# pdp8l.net
KiCad netlist of a schematic drawn in EAGLE
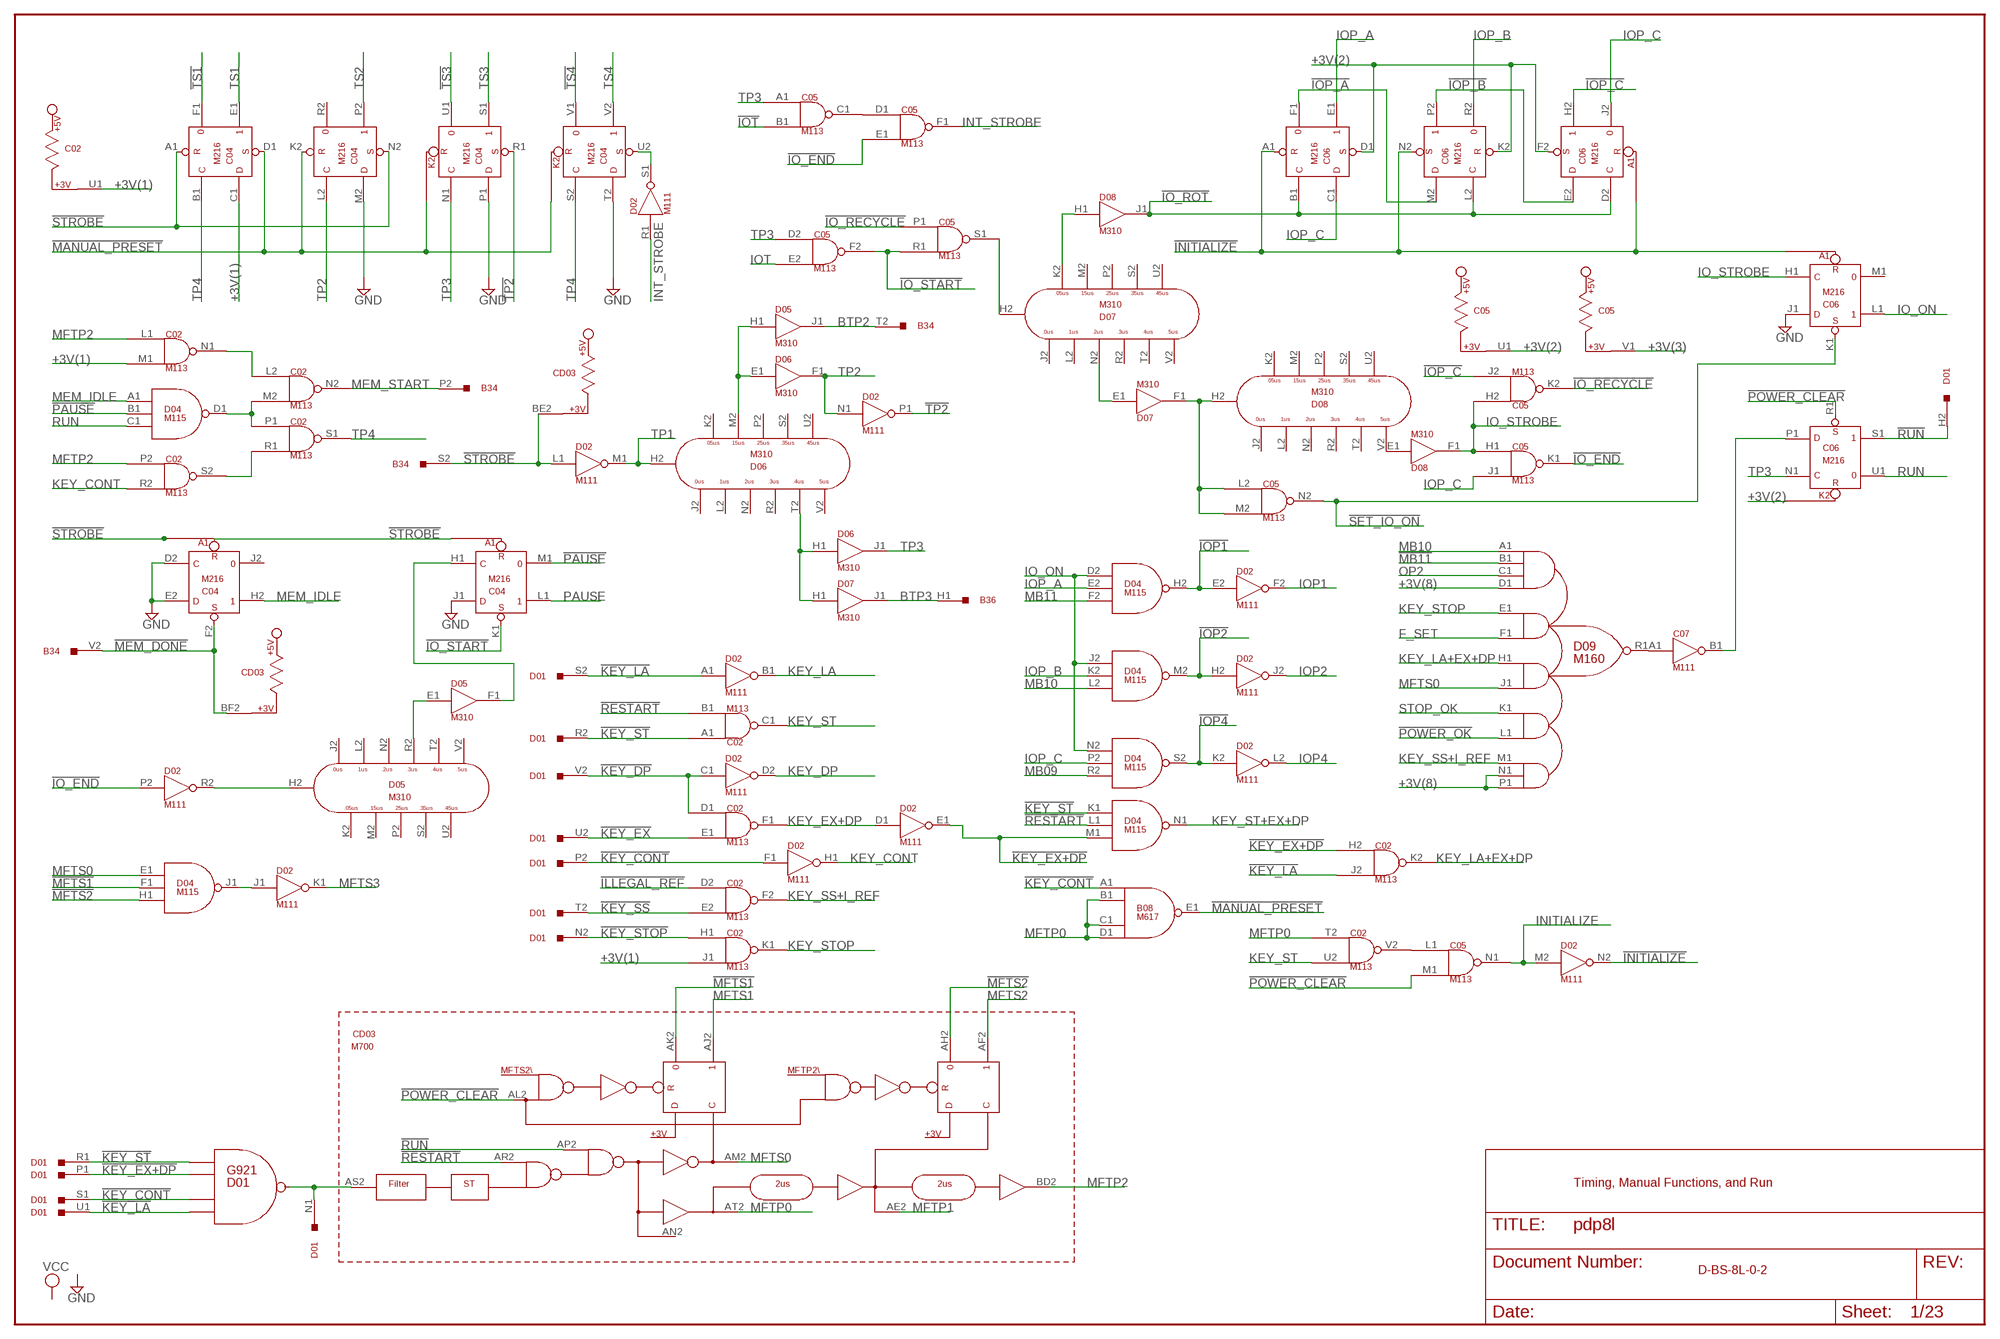
[diagram p0: schematic, sheet 1]
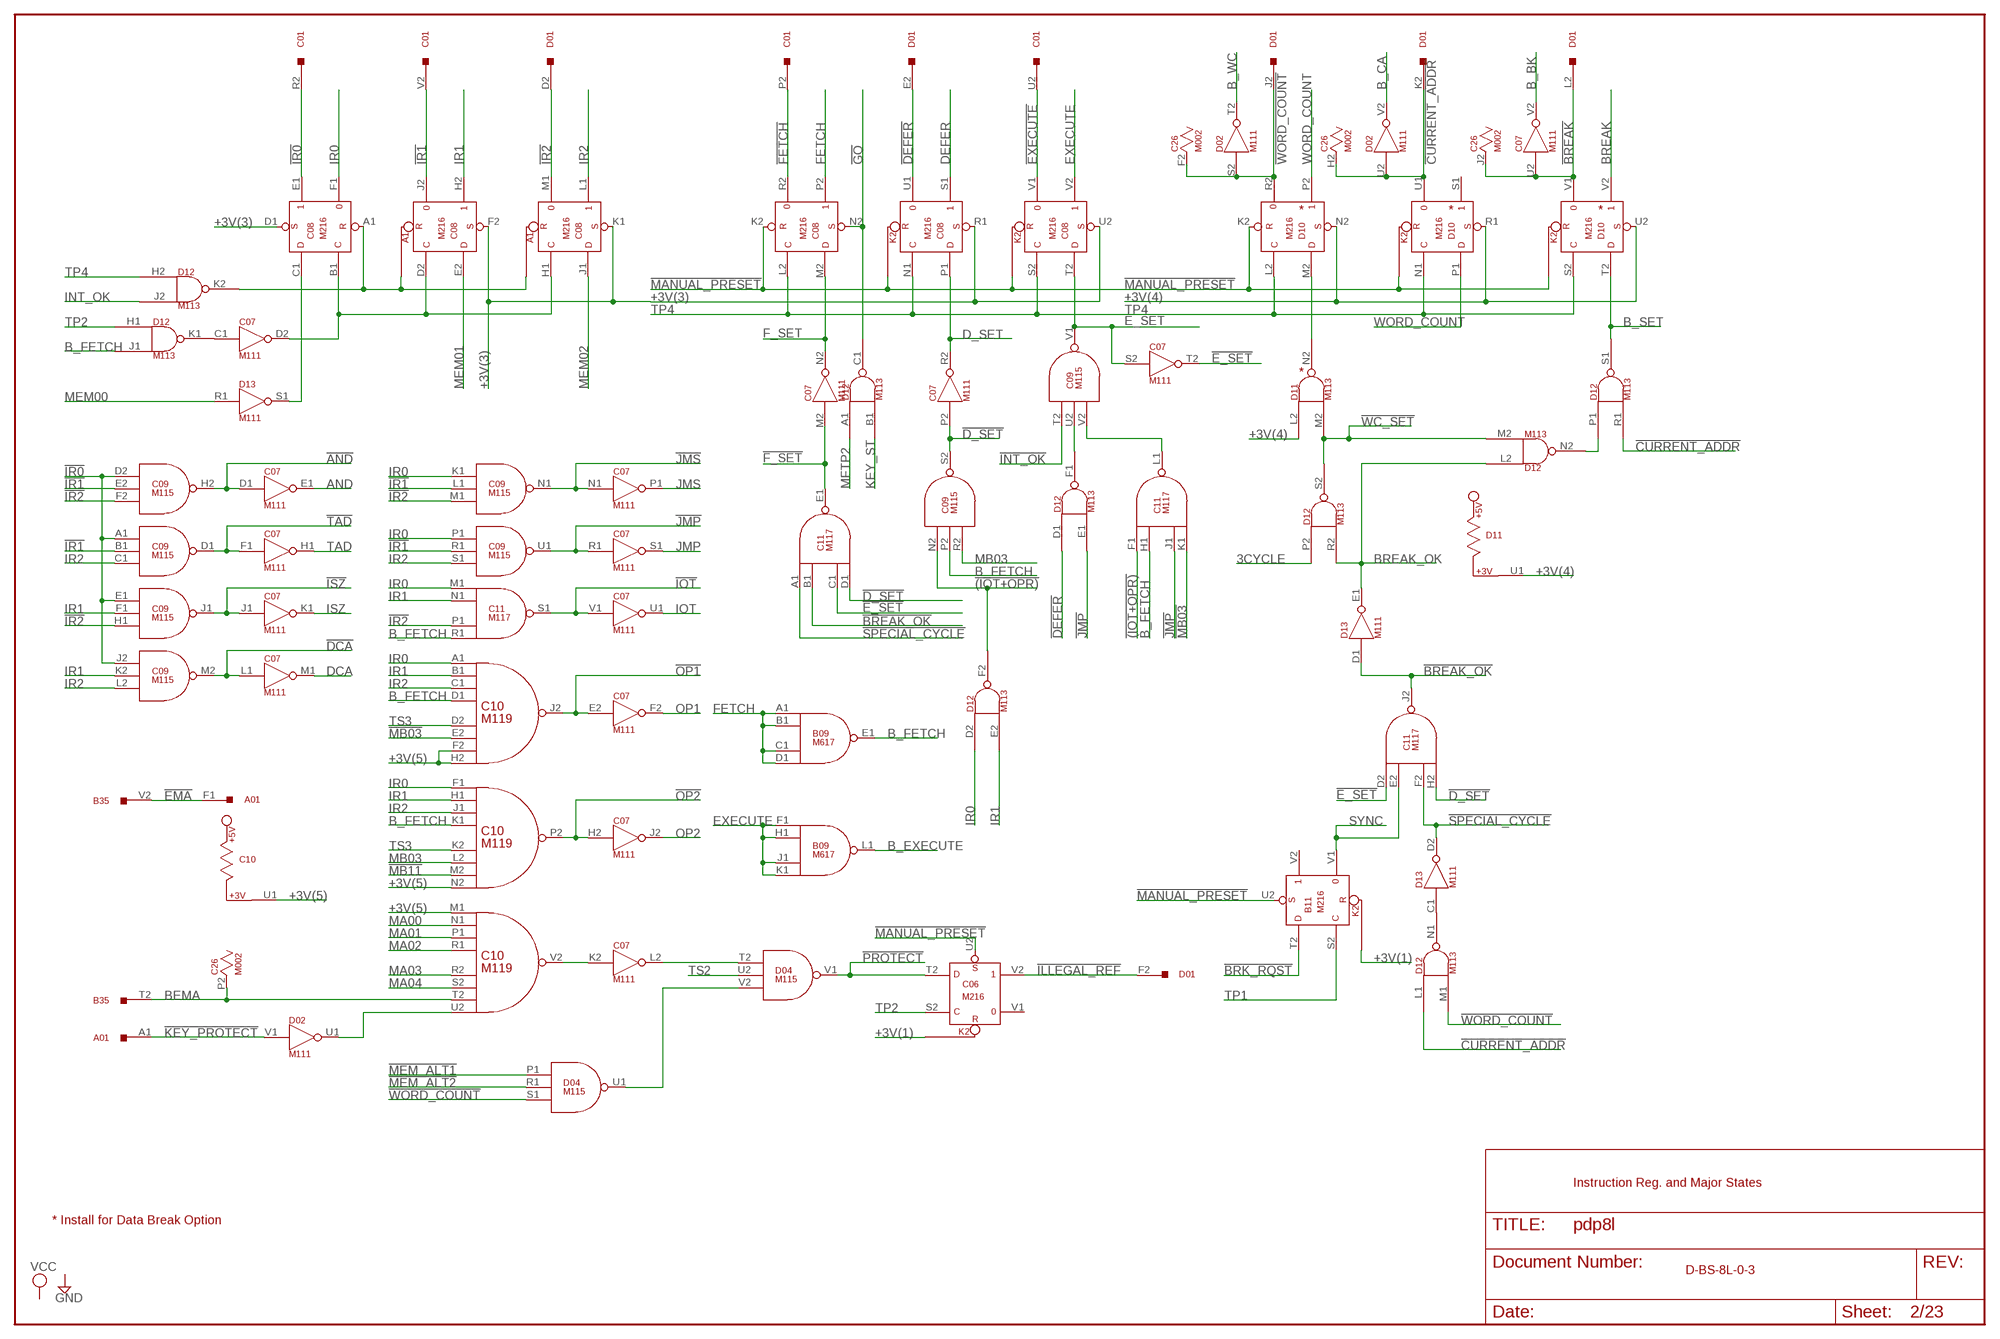
[diagram p1: schematic, sheet 2]
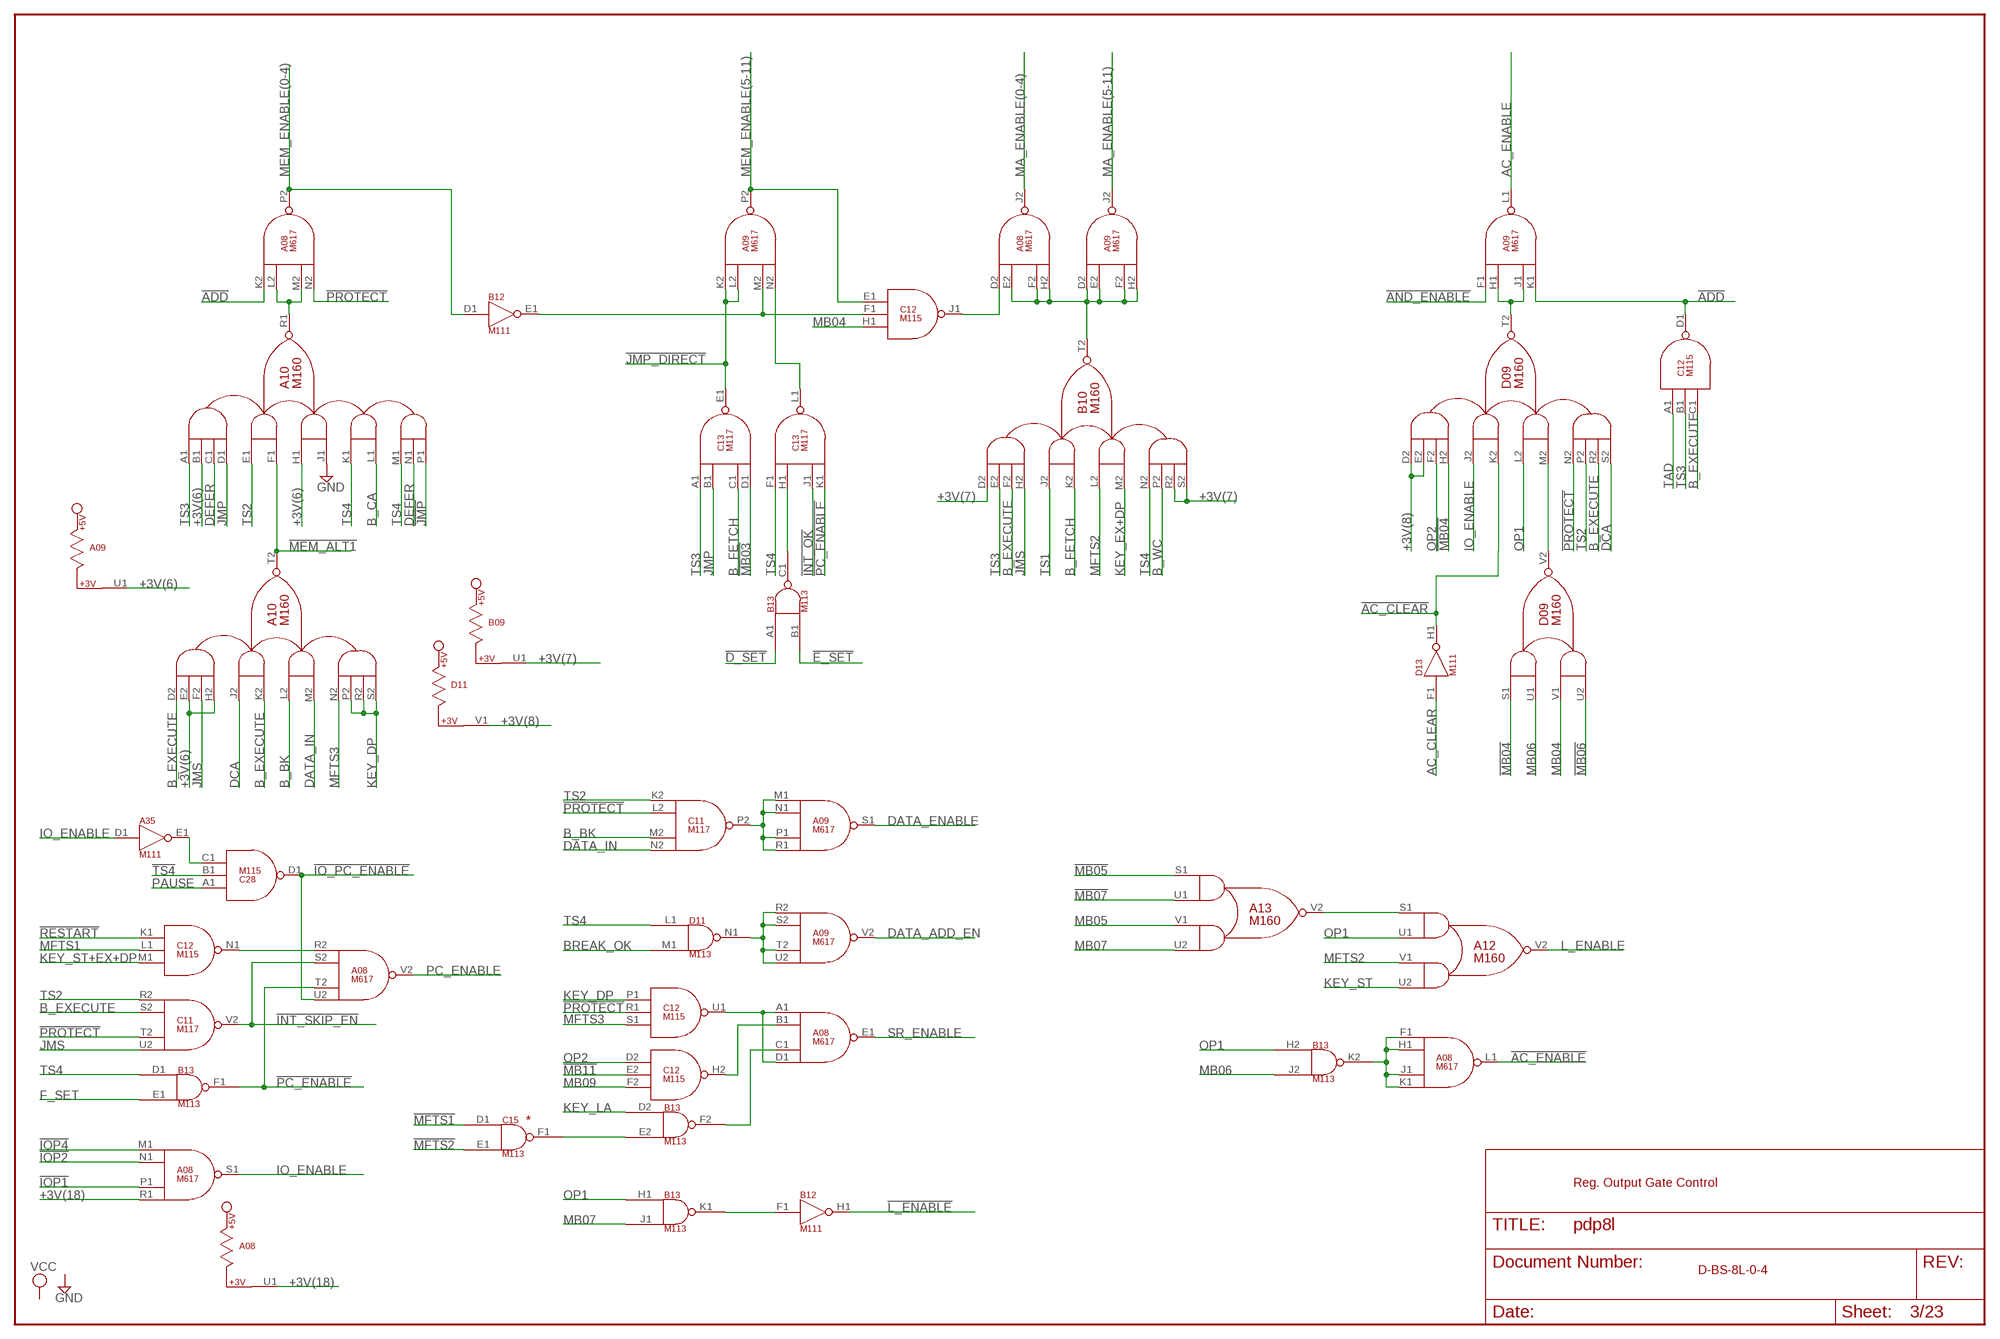
[diagram p2: schematic, sheet 3]
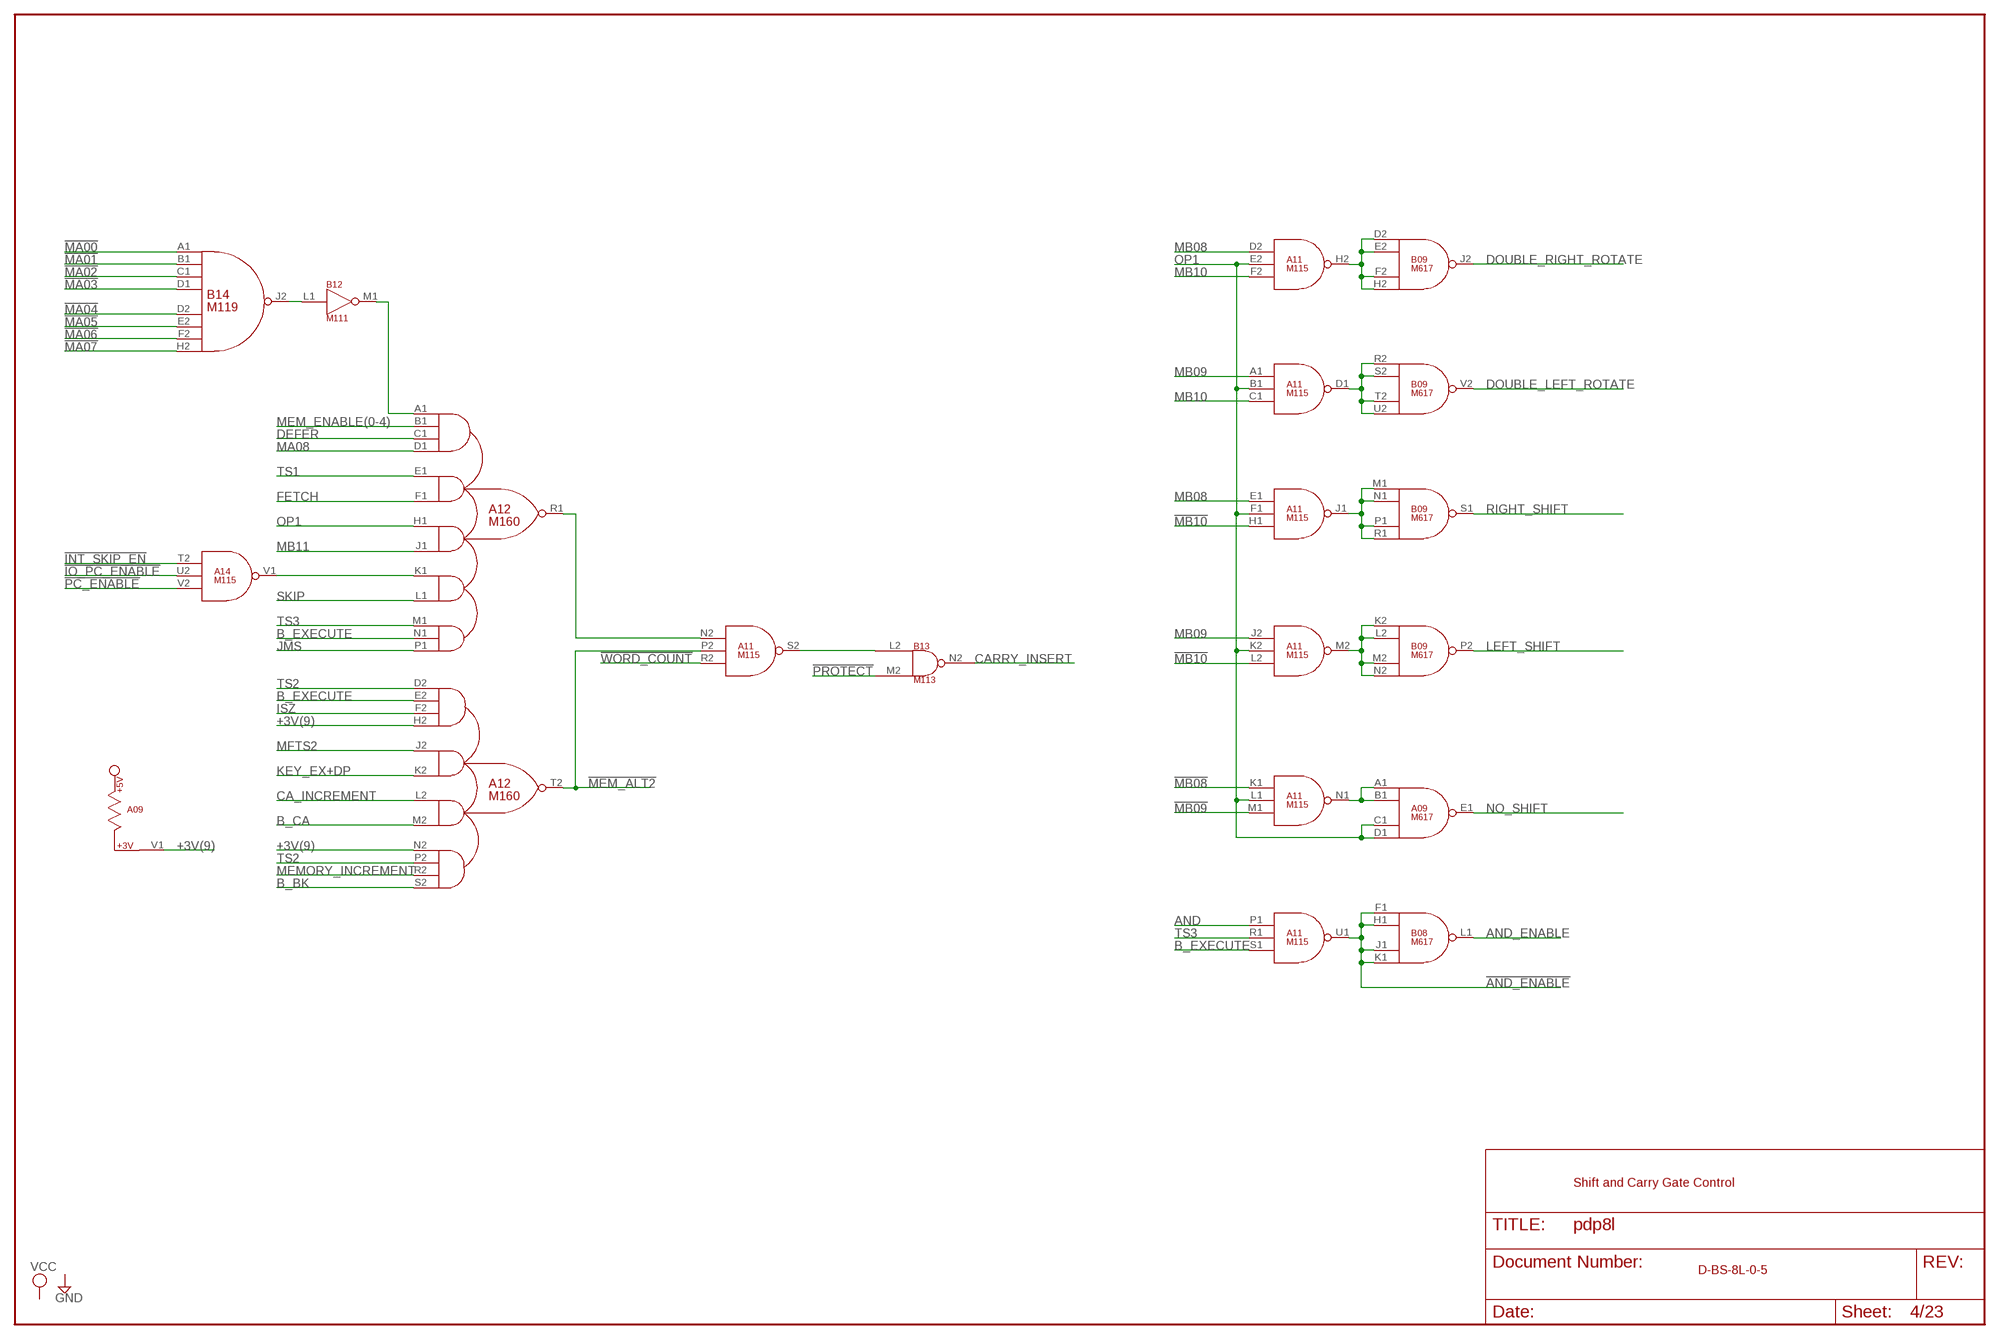
[diagram p3: schematic, sheet 4]
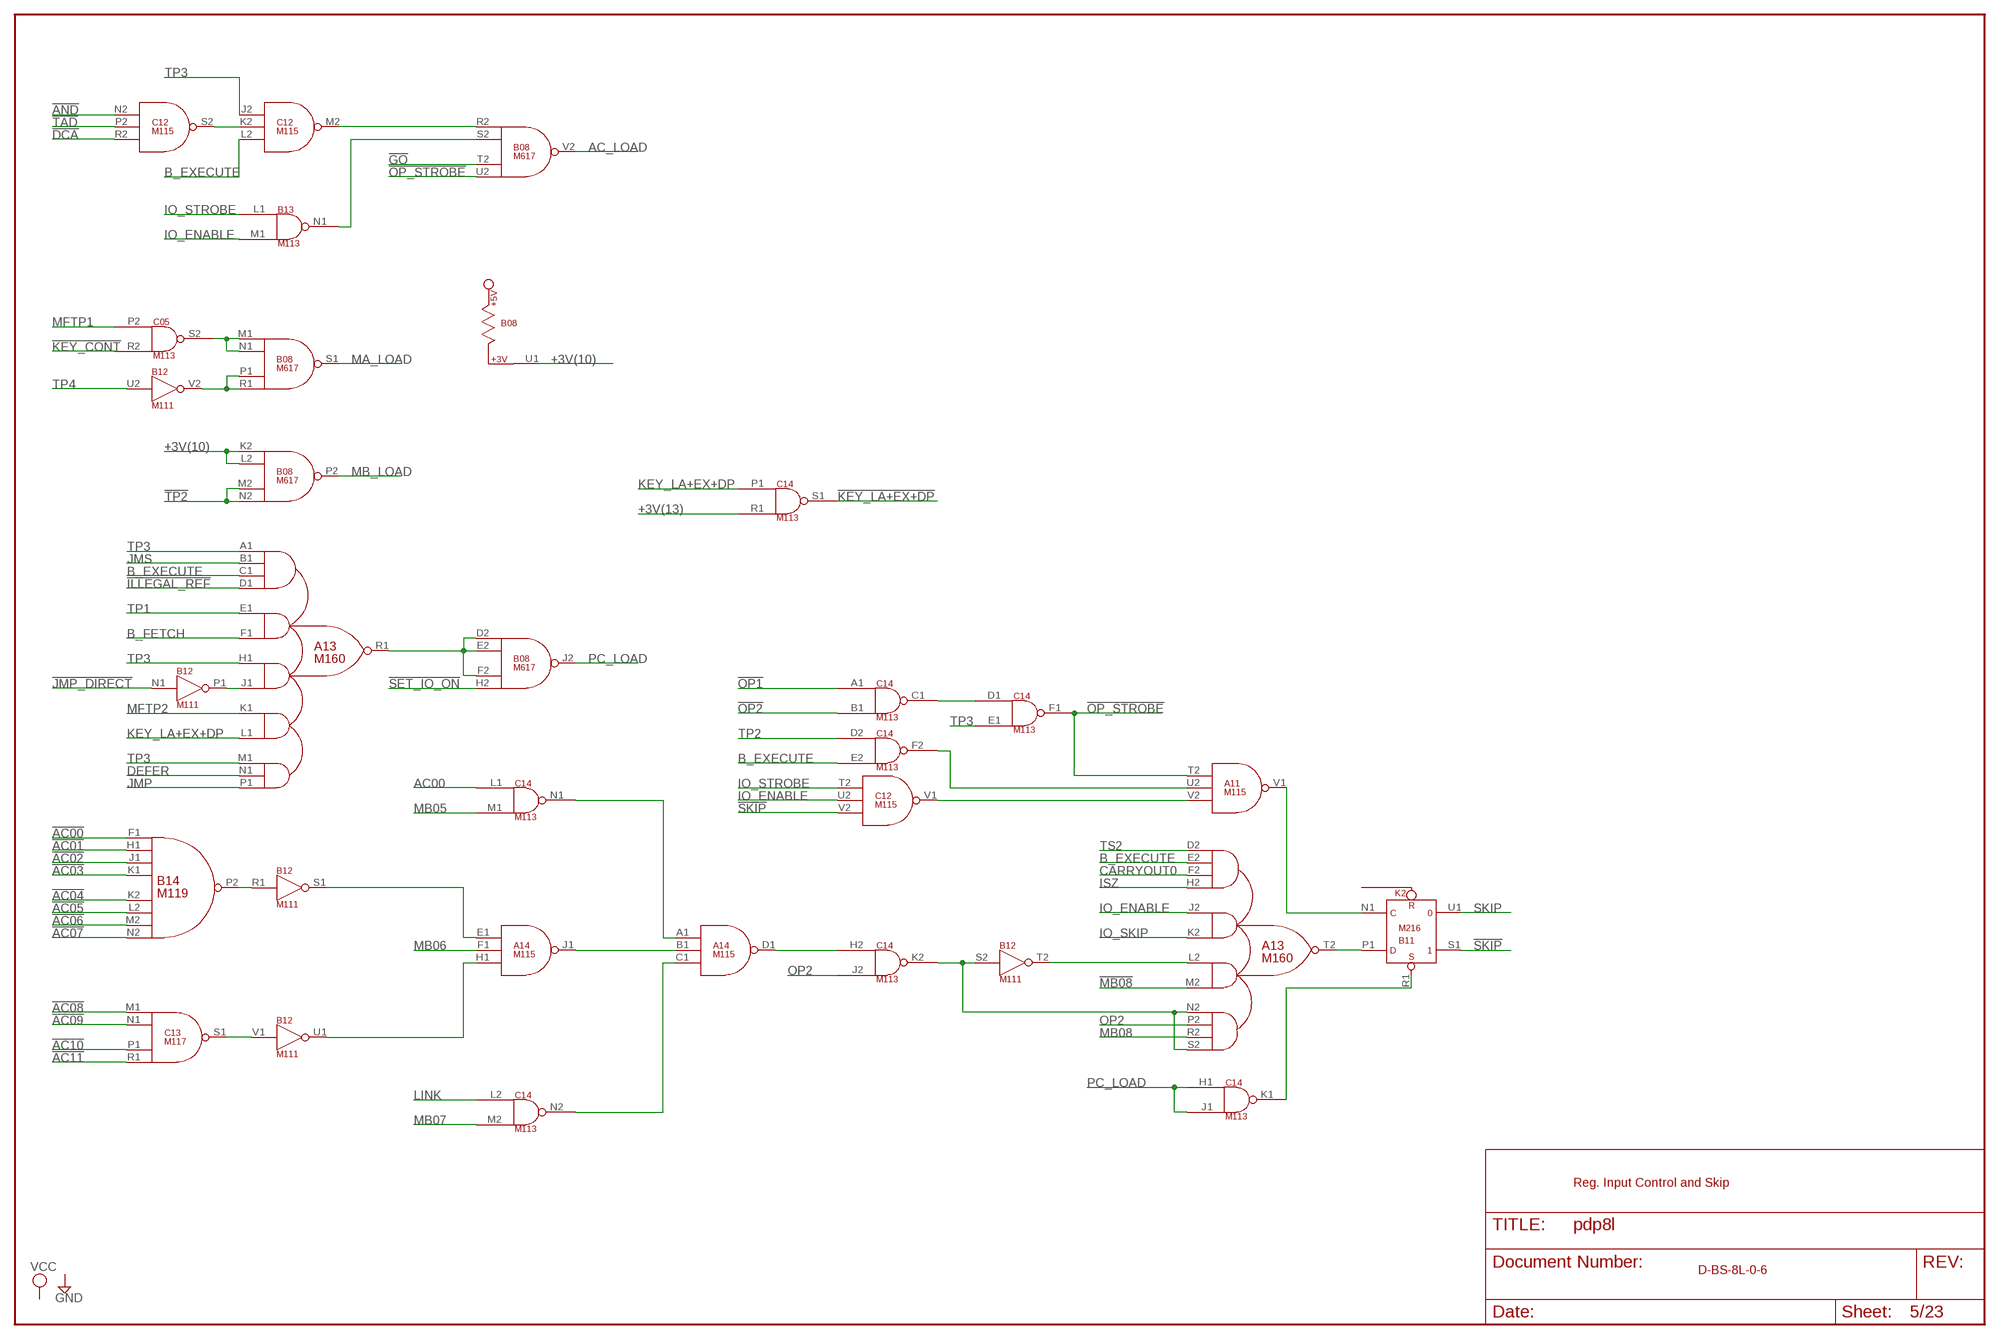
[diagram p4: schematic, sheet 5]
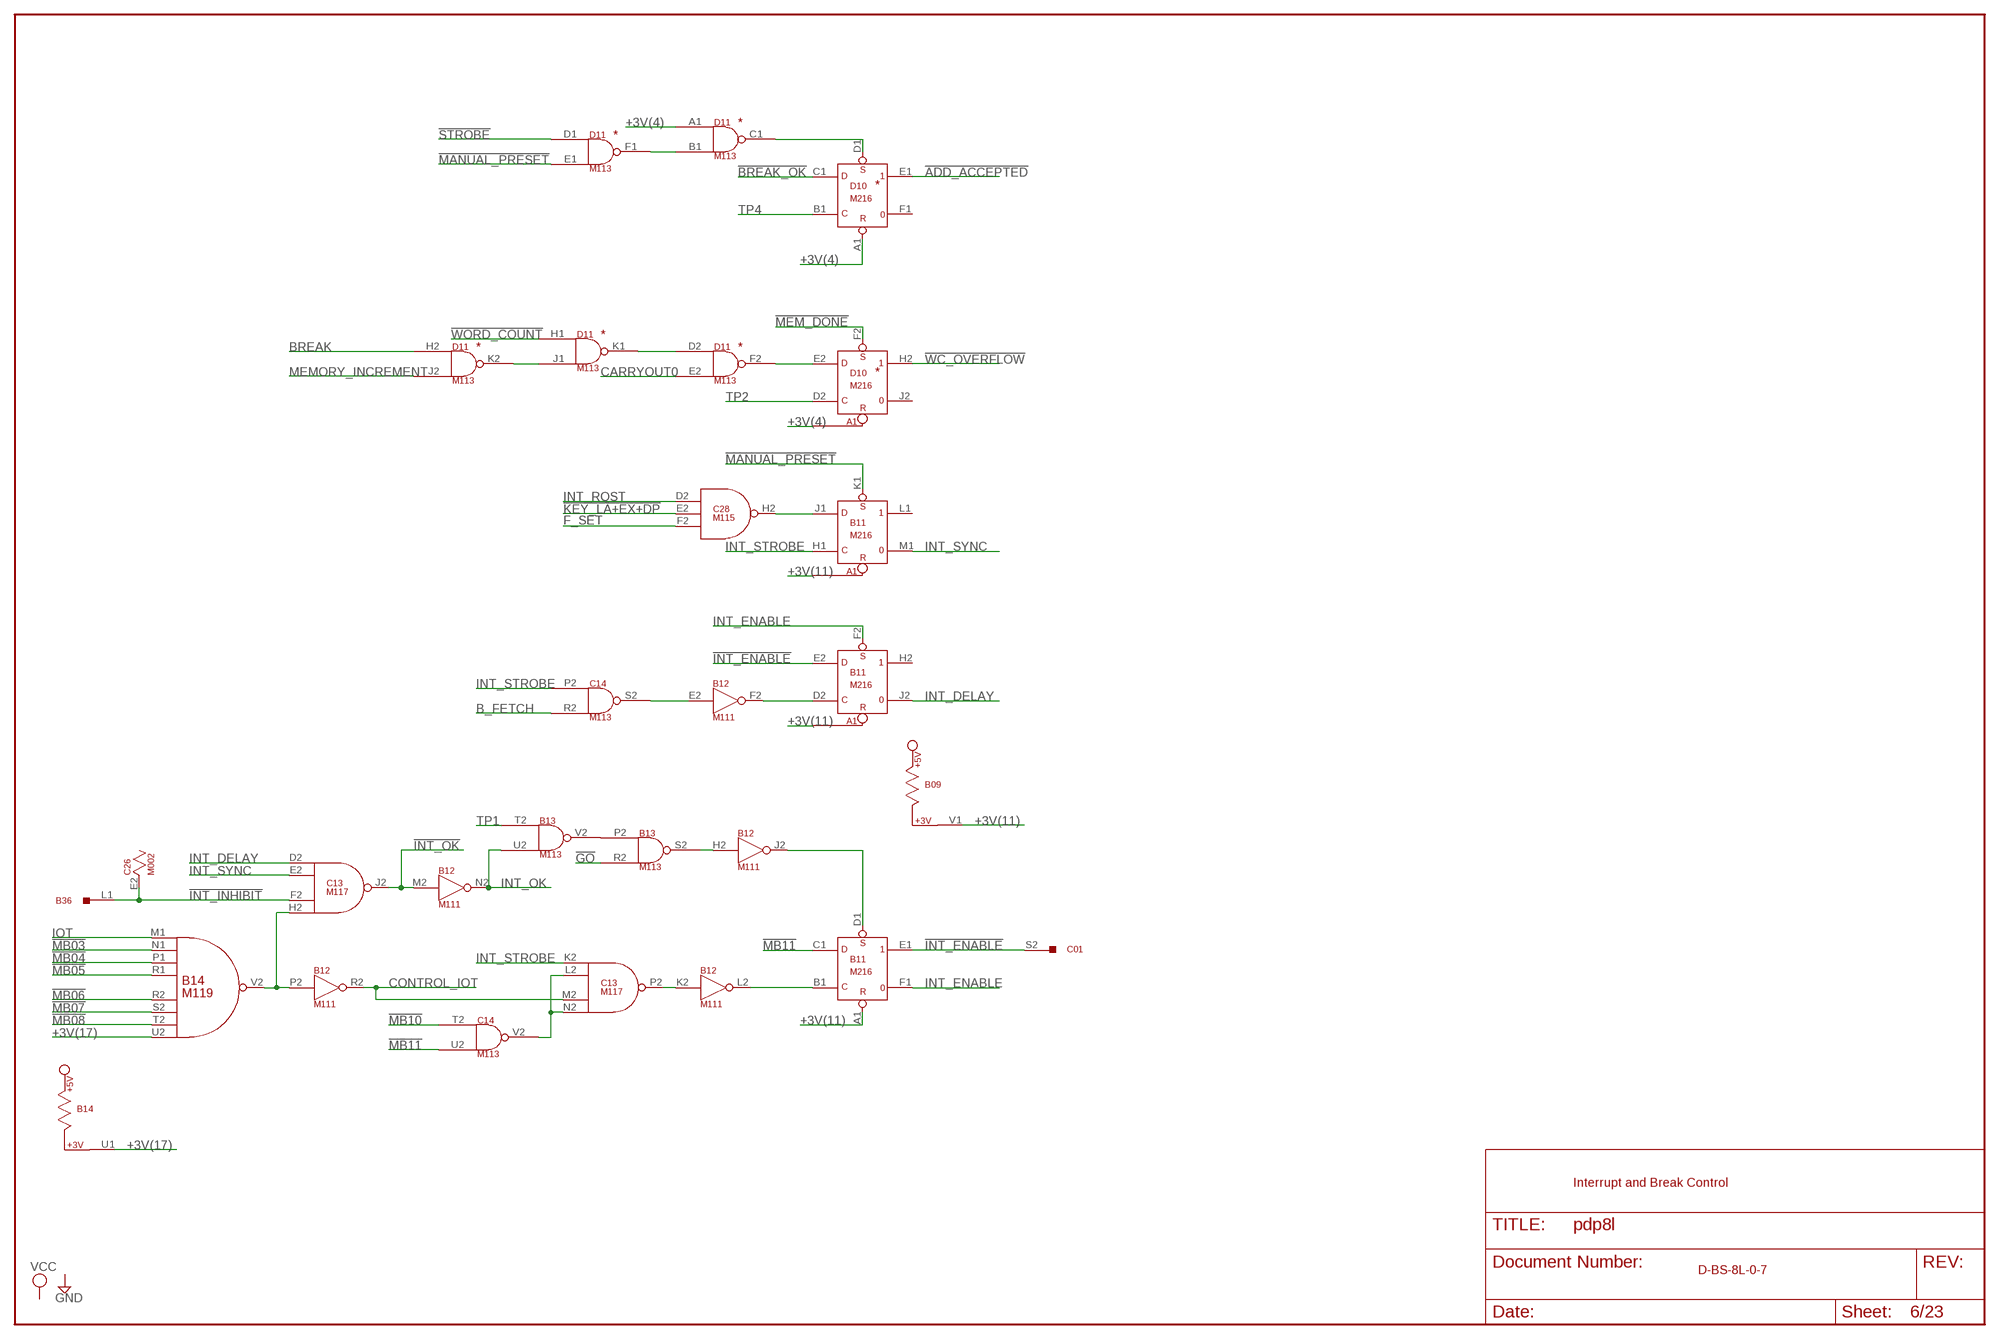
[diagram p5: schematic, sheet 6]
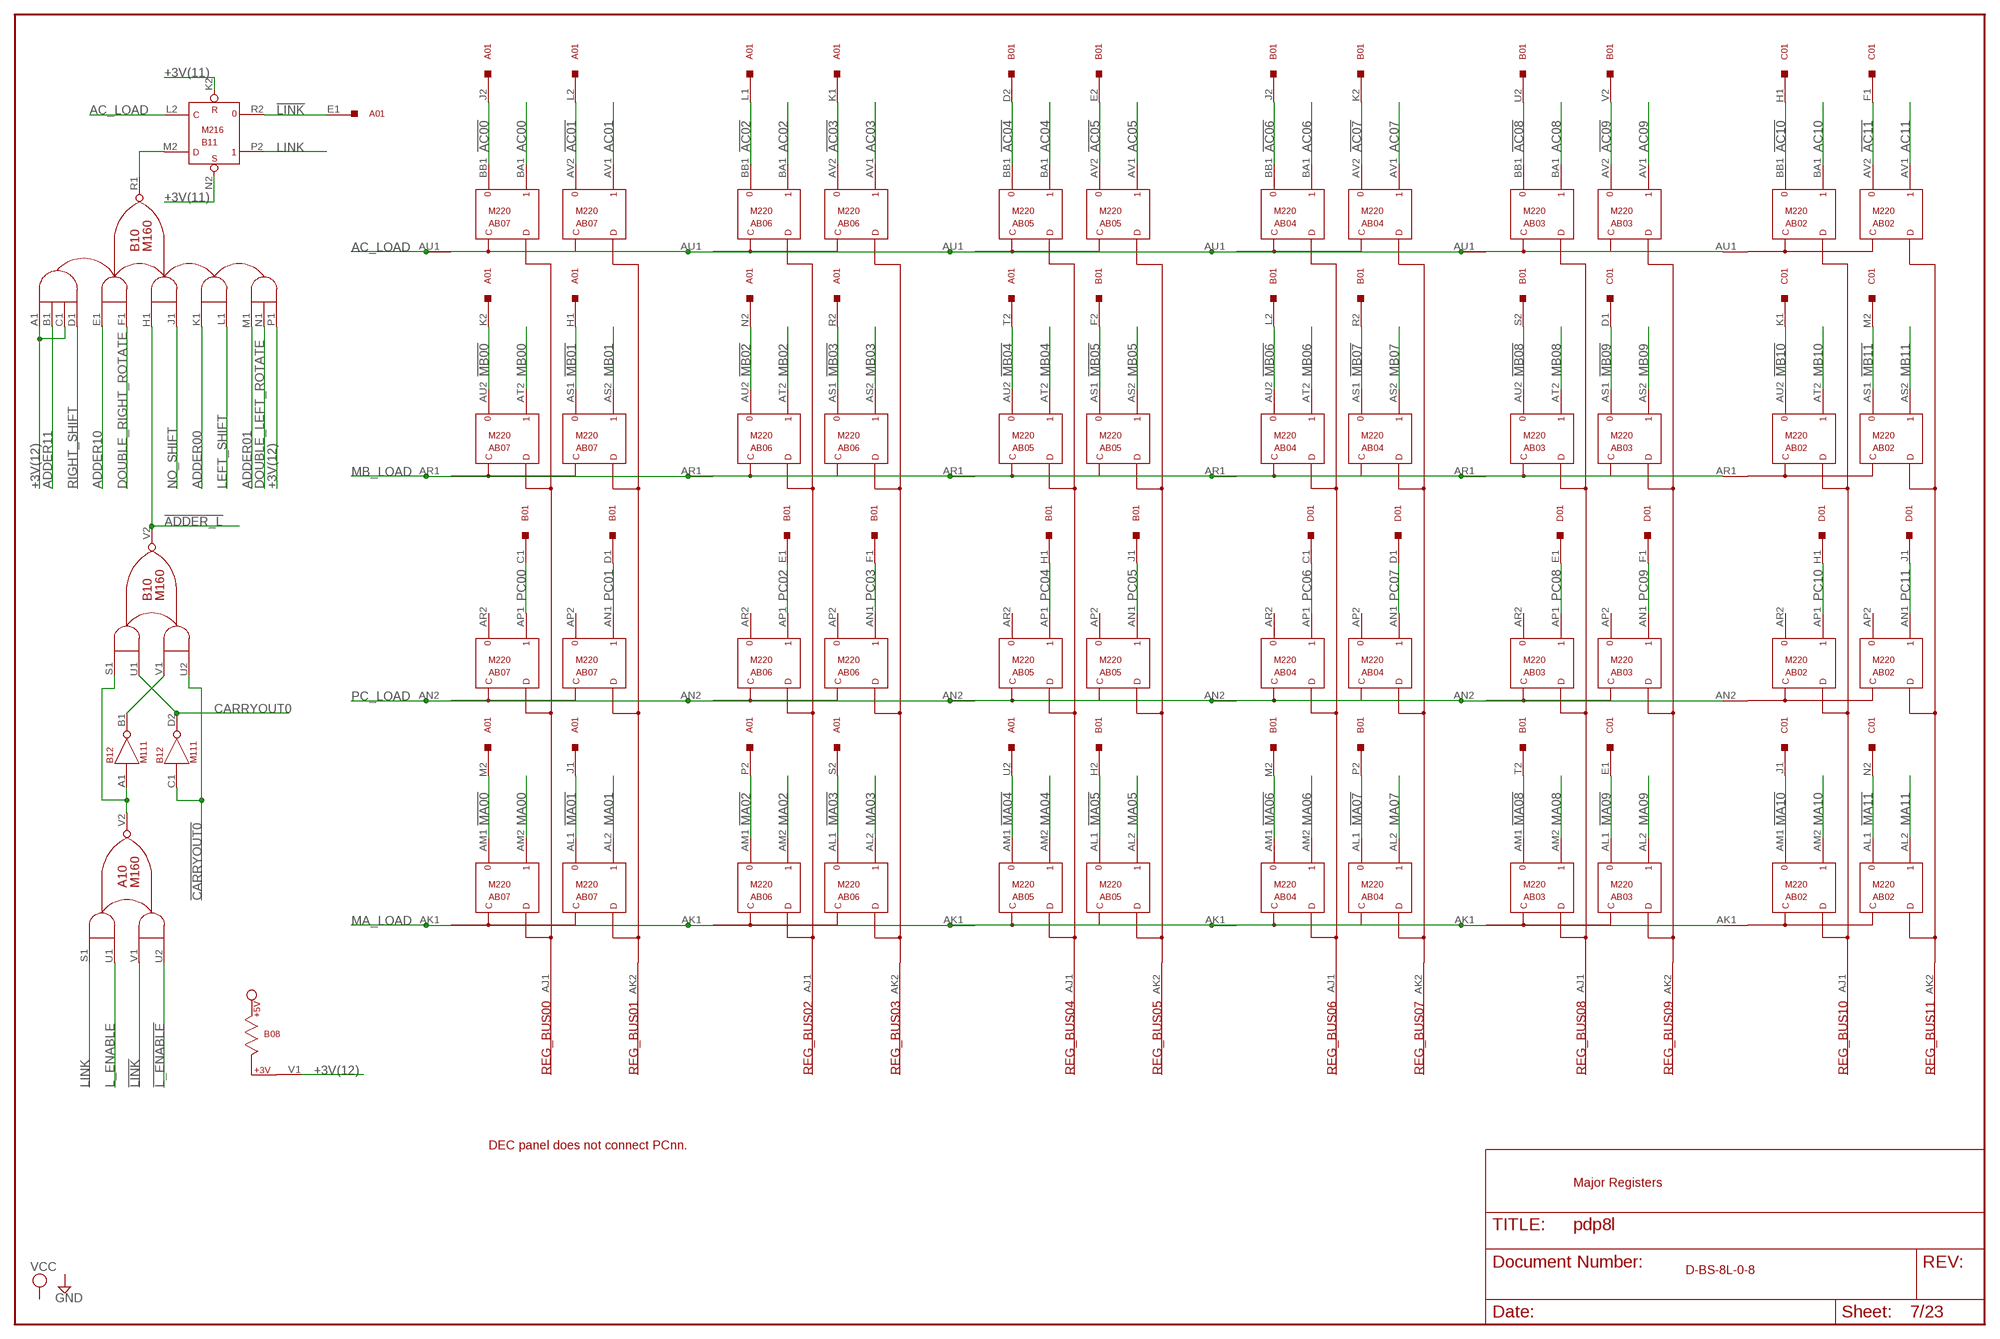
[diagram p6: schematic, sheet 7]
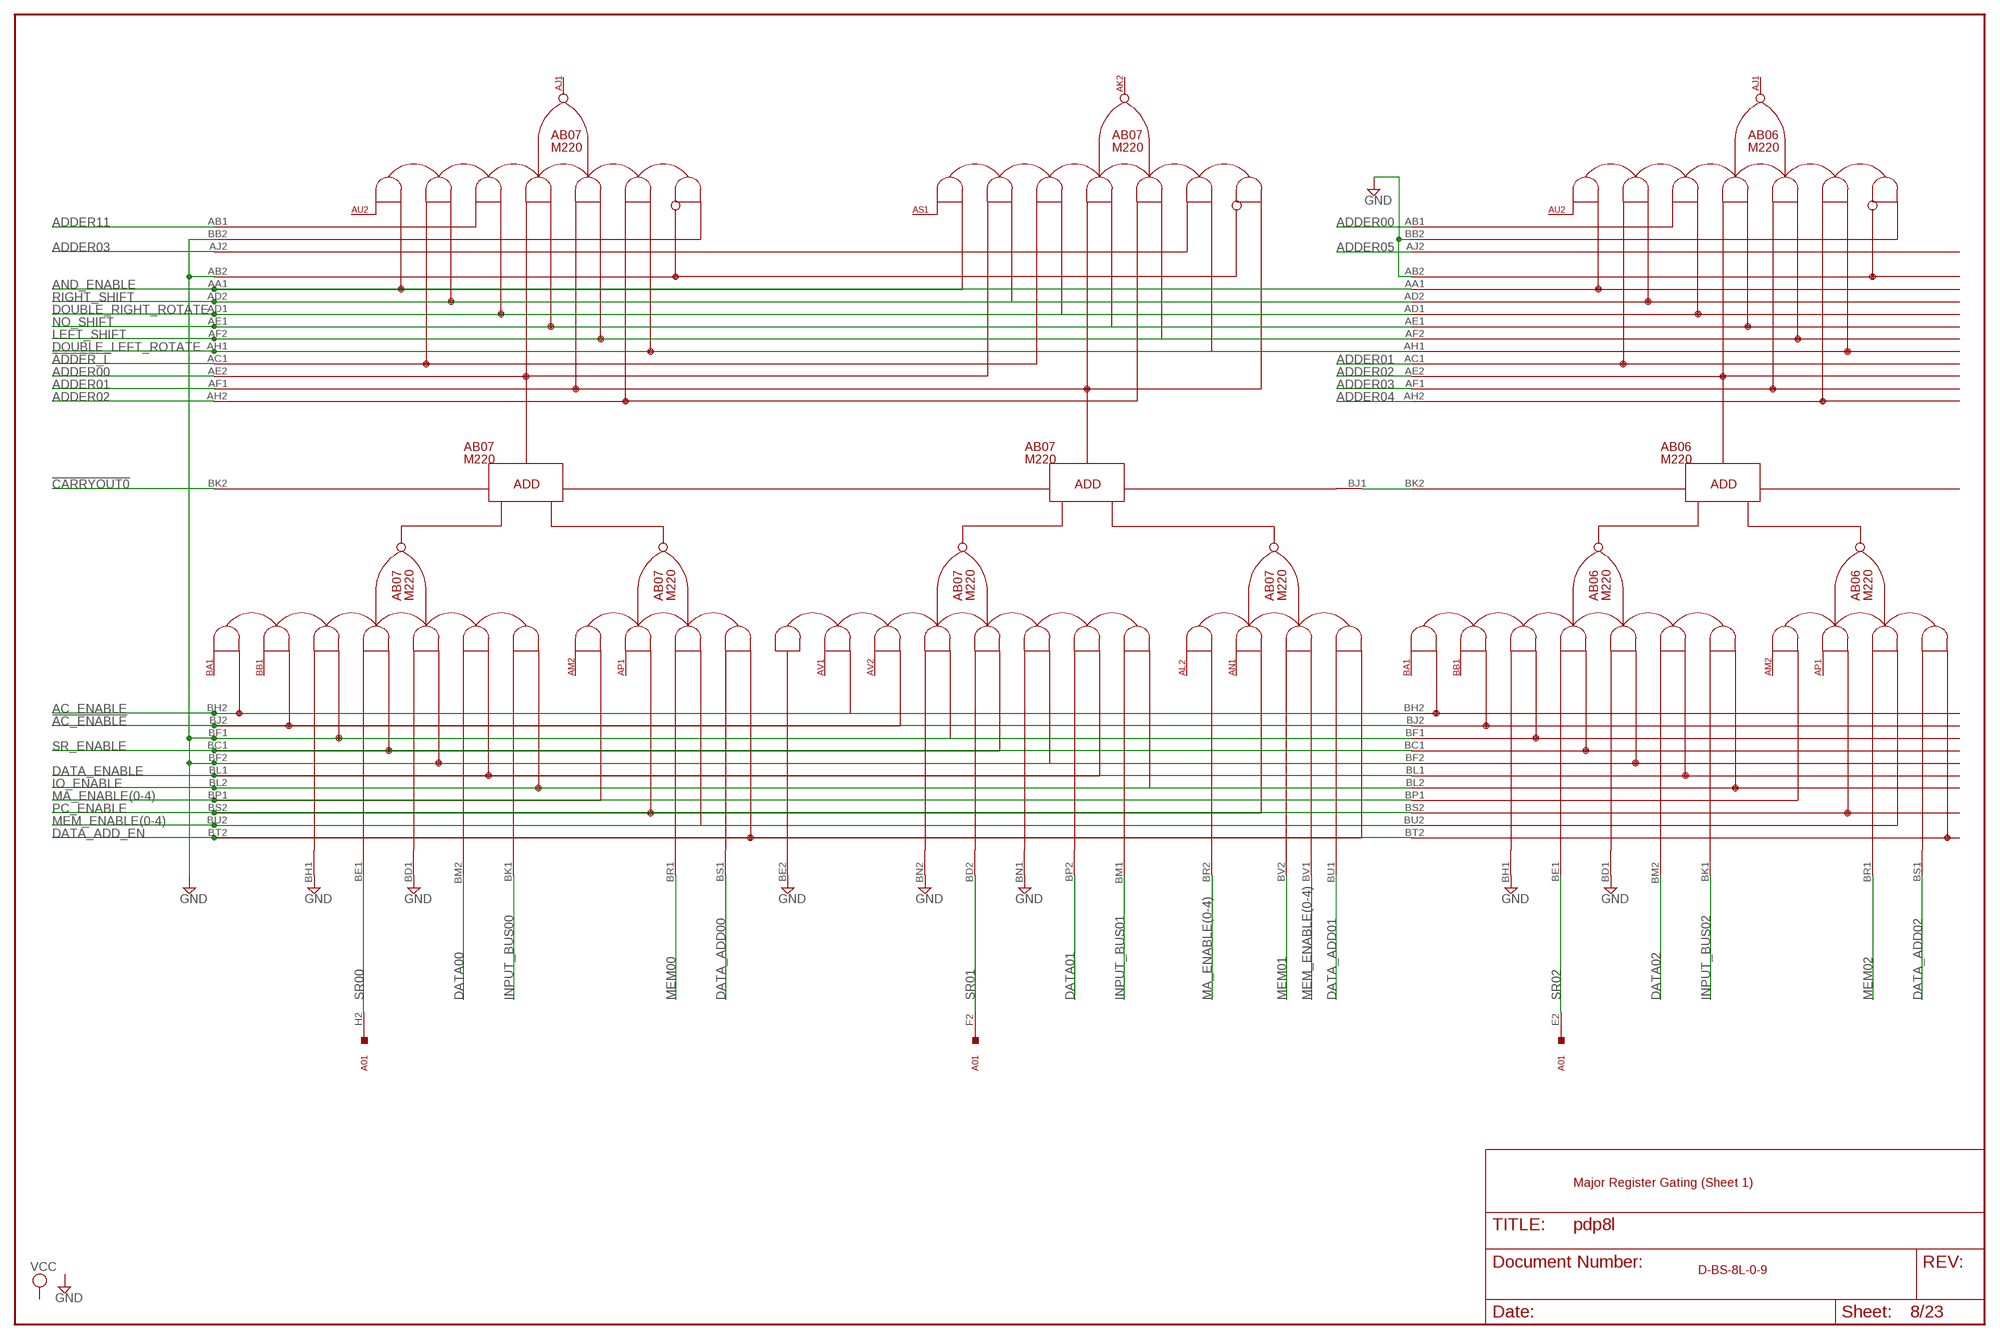
[diagram p7: schematic, sheet 8]
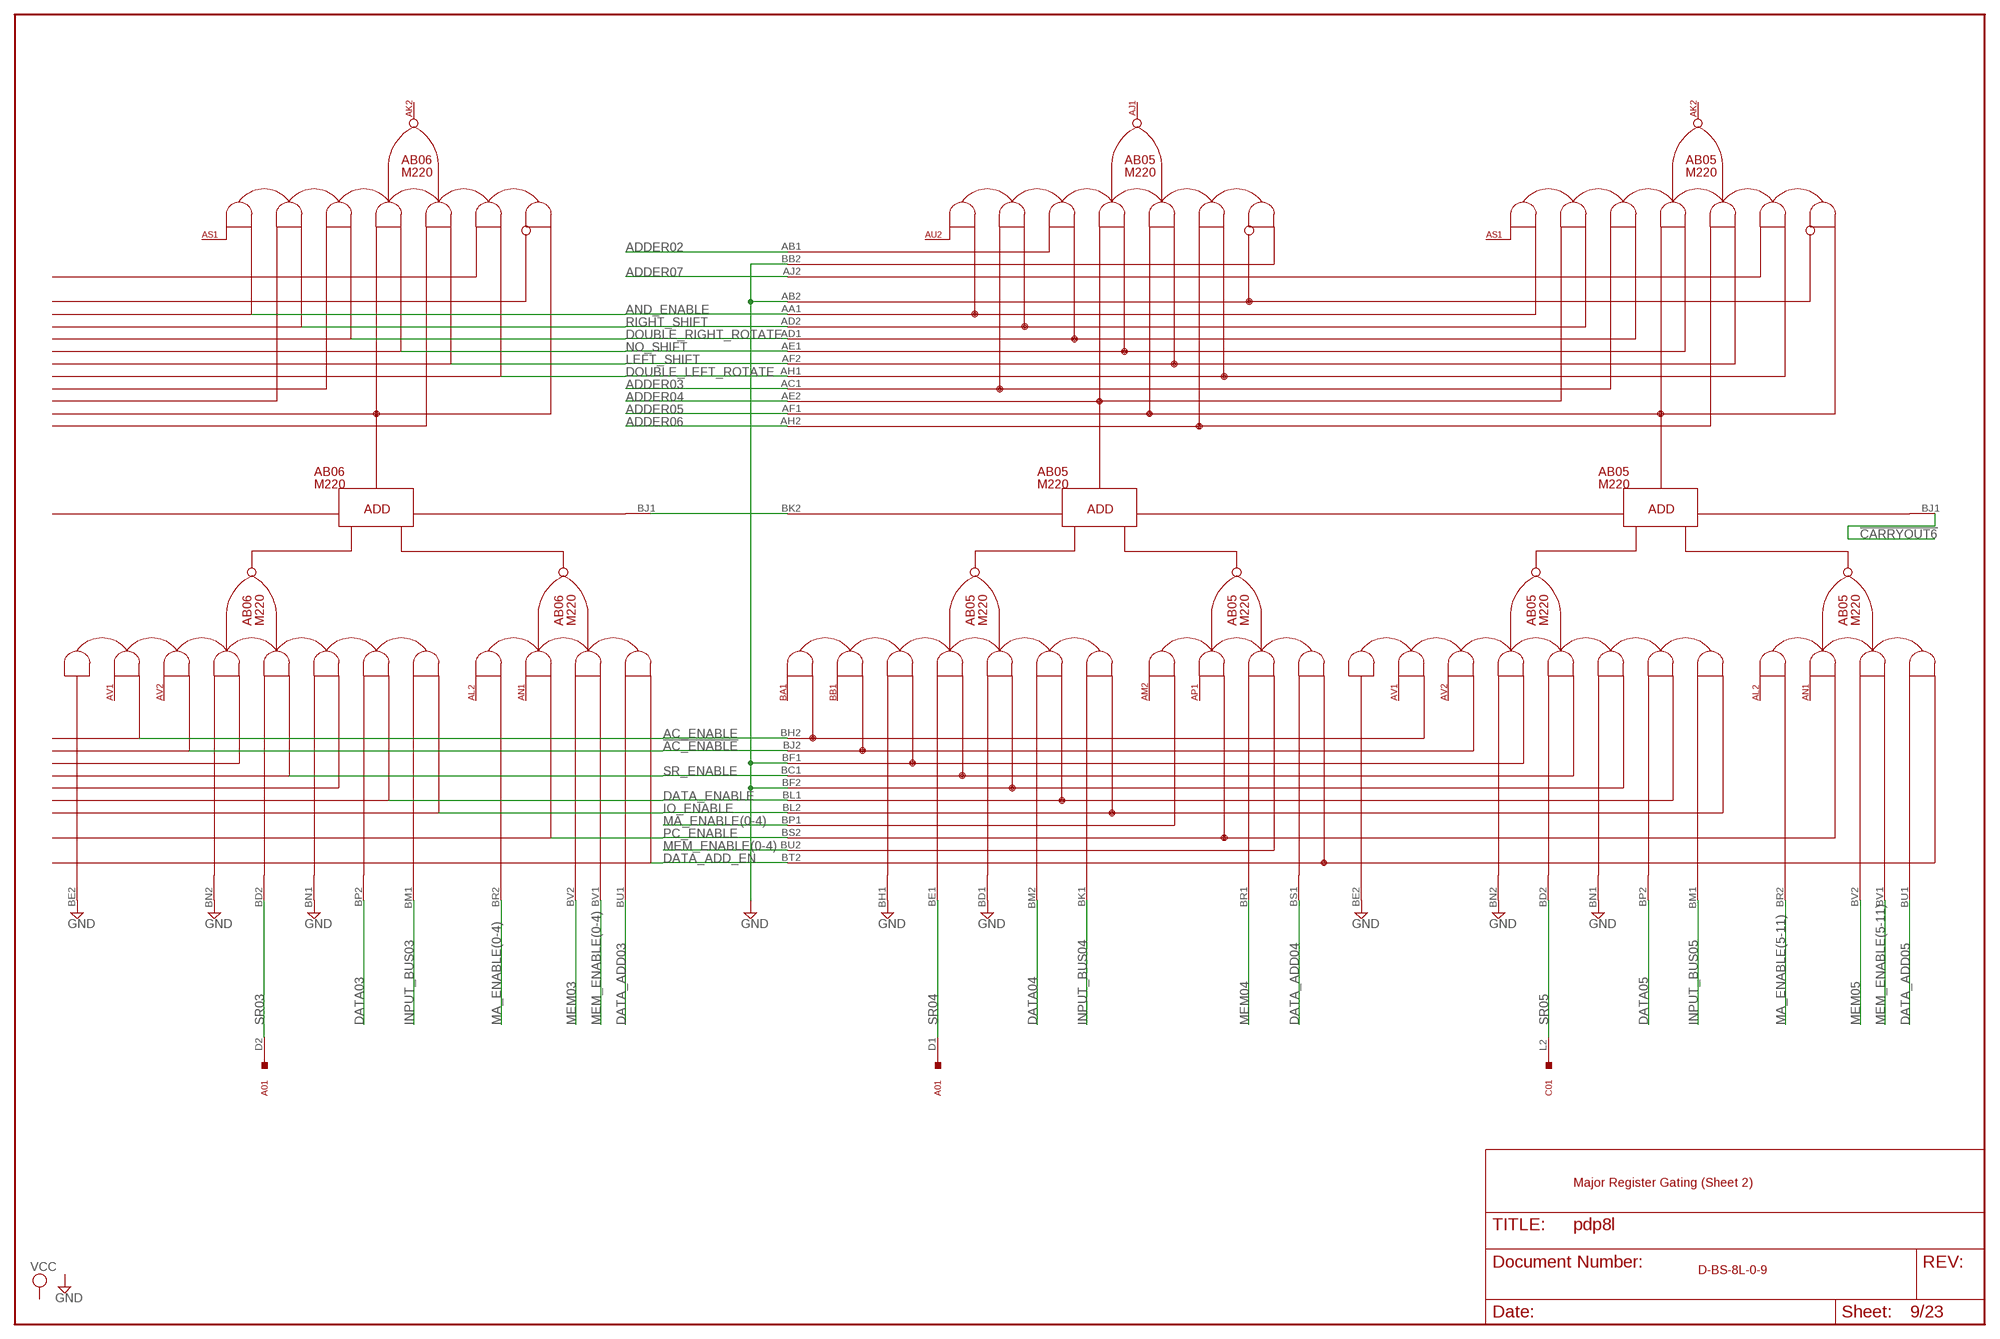
[diagram p8: schematic, sheet 9]
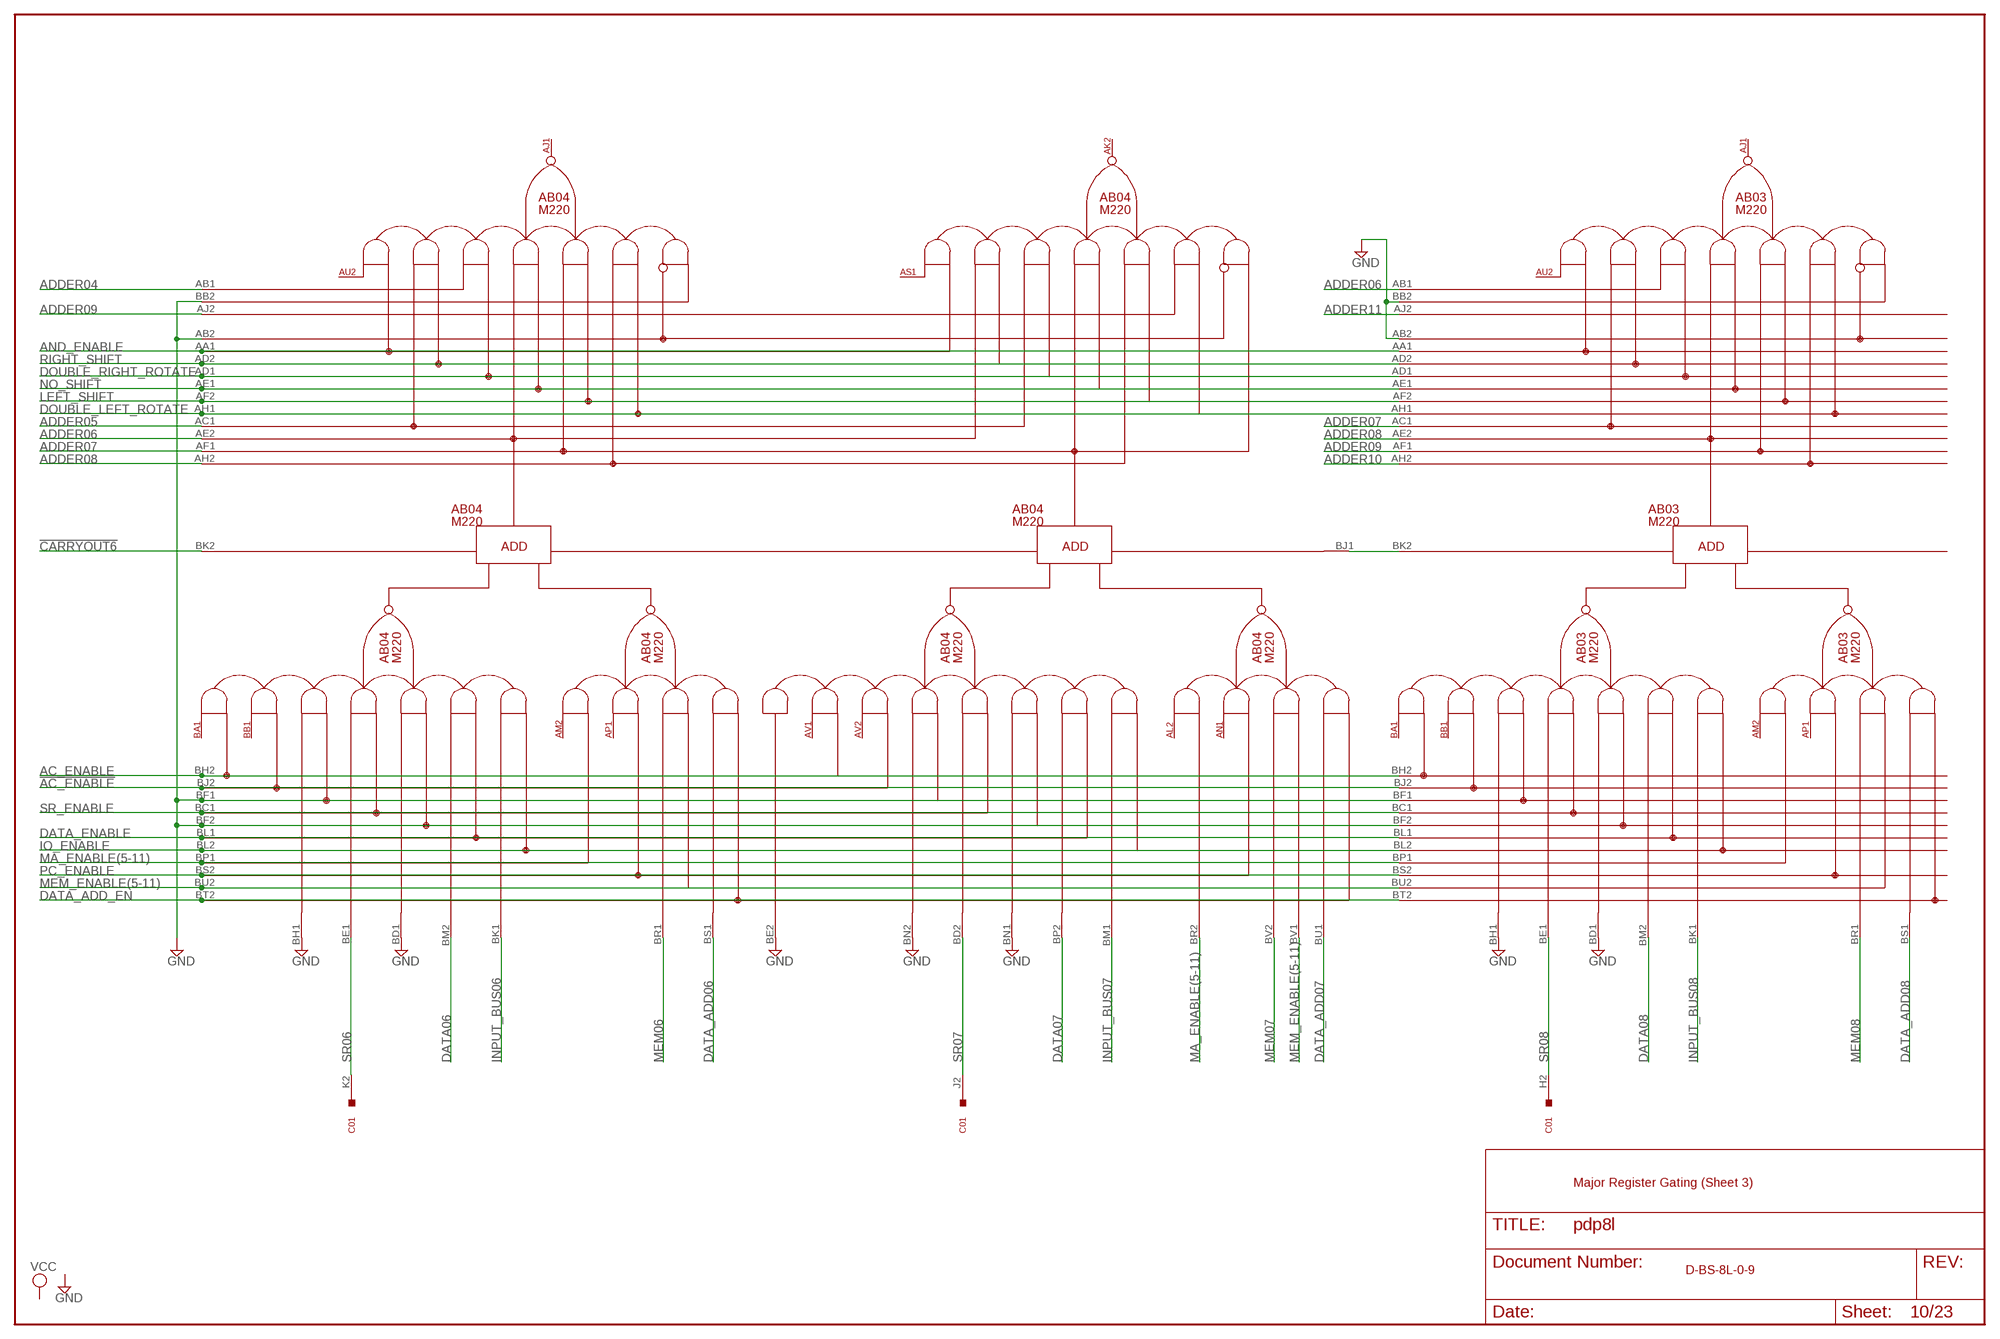
[diagram p9: schematic, sheet 10]
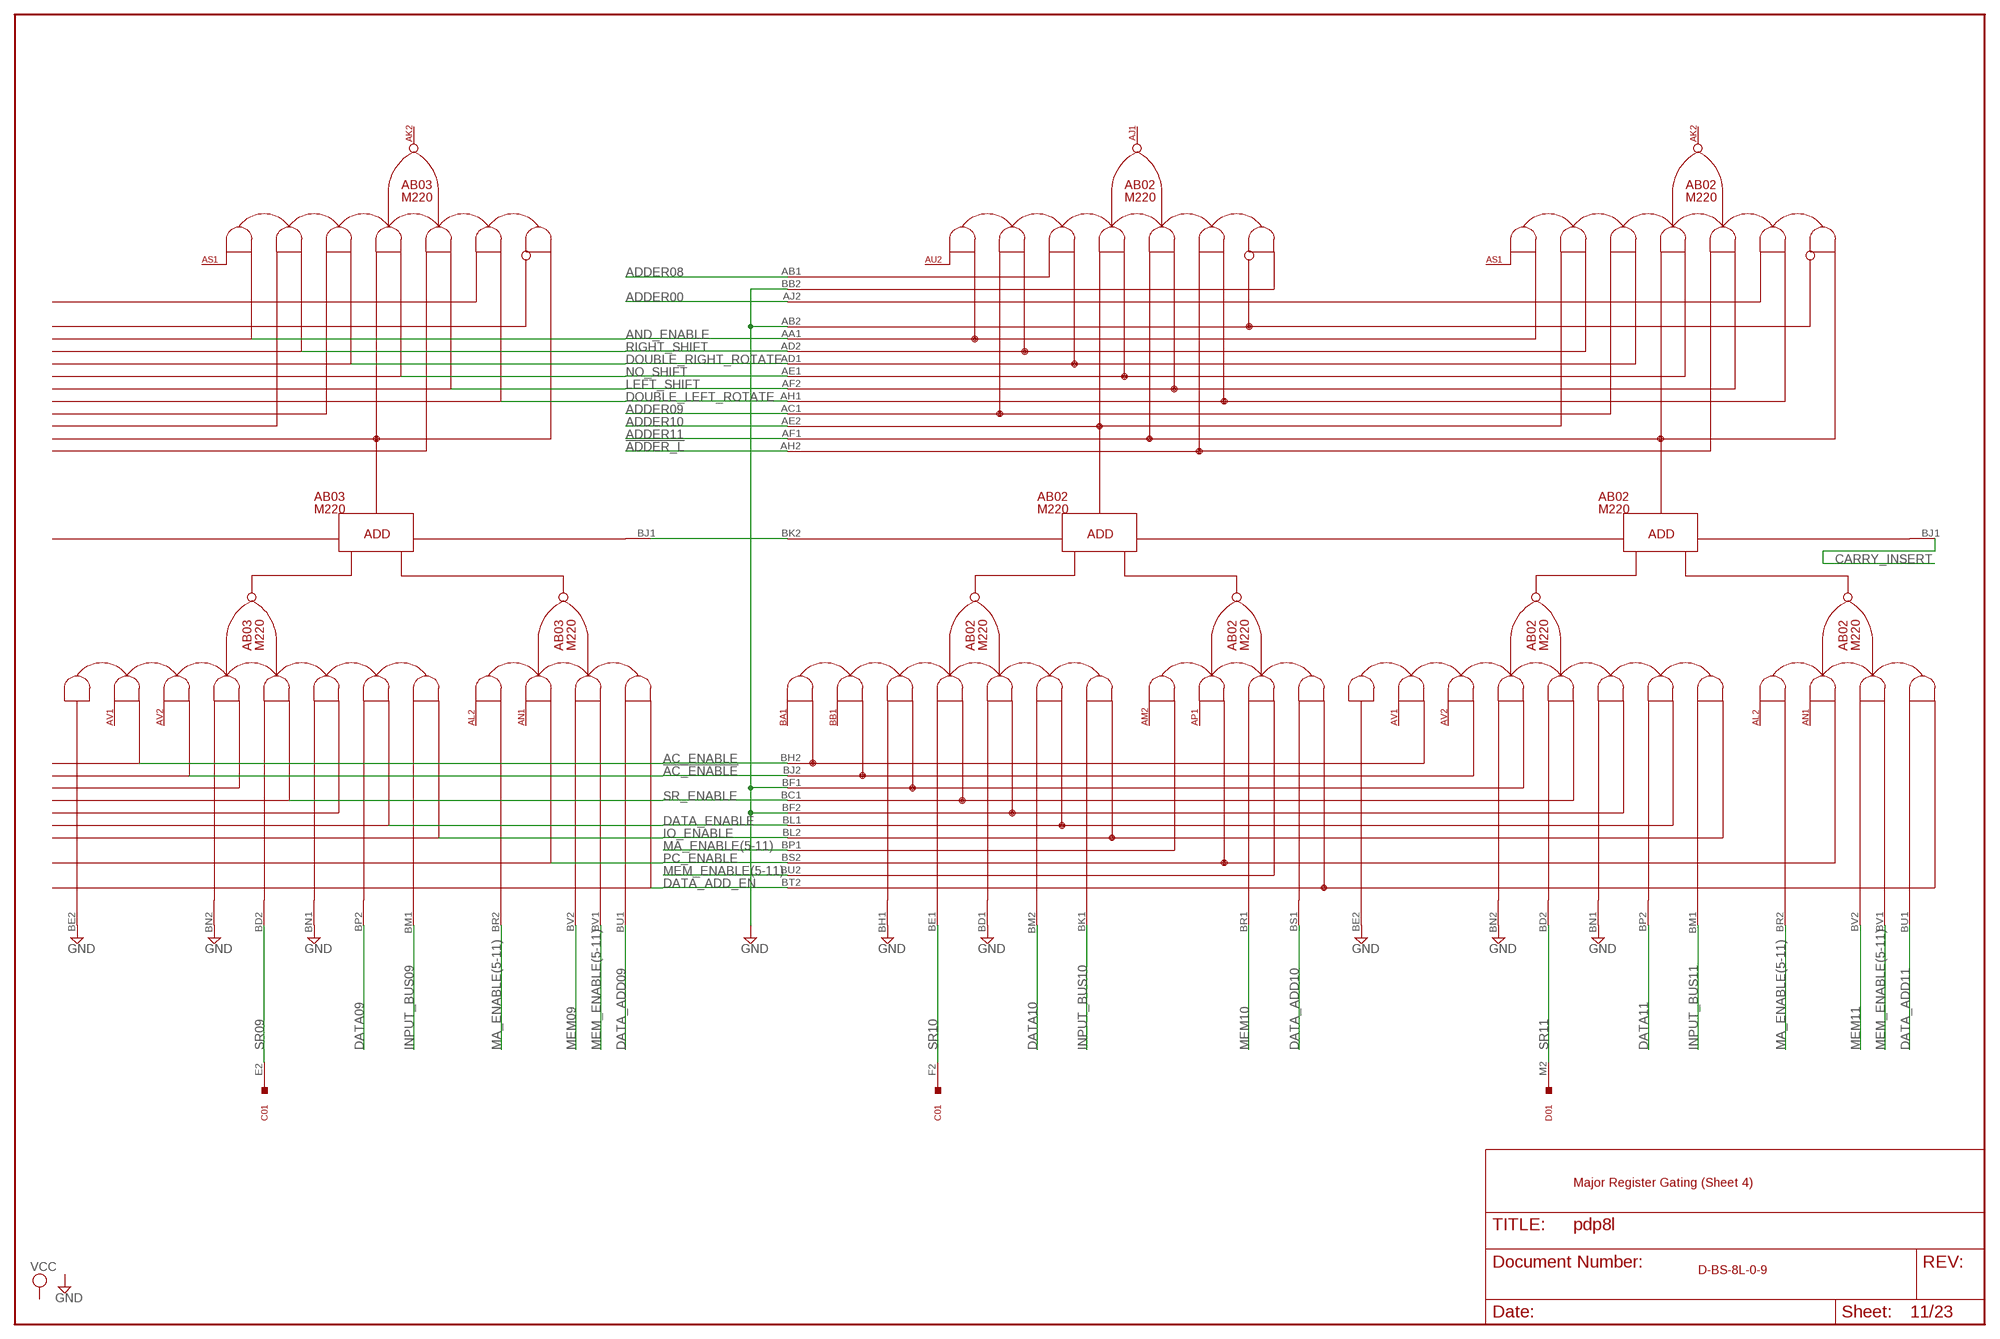
[diagram p10: schematic, sheet 11]
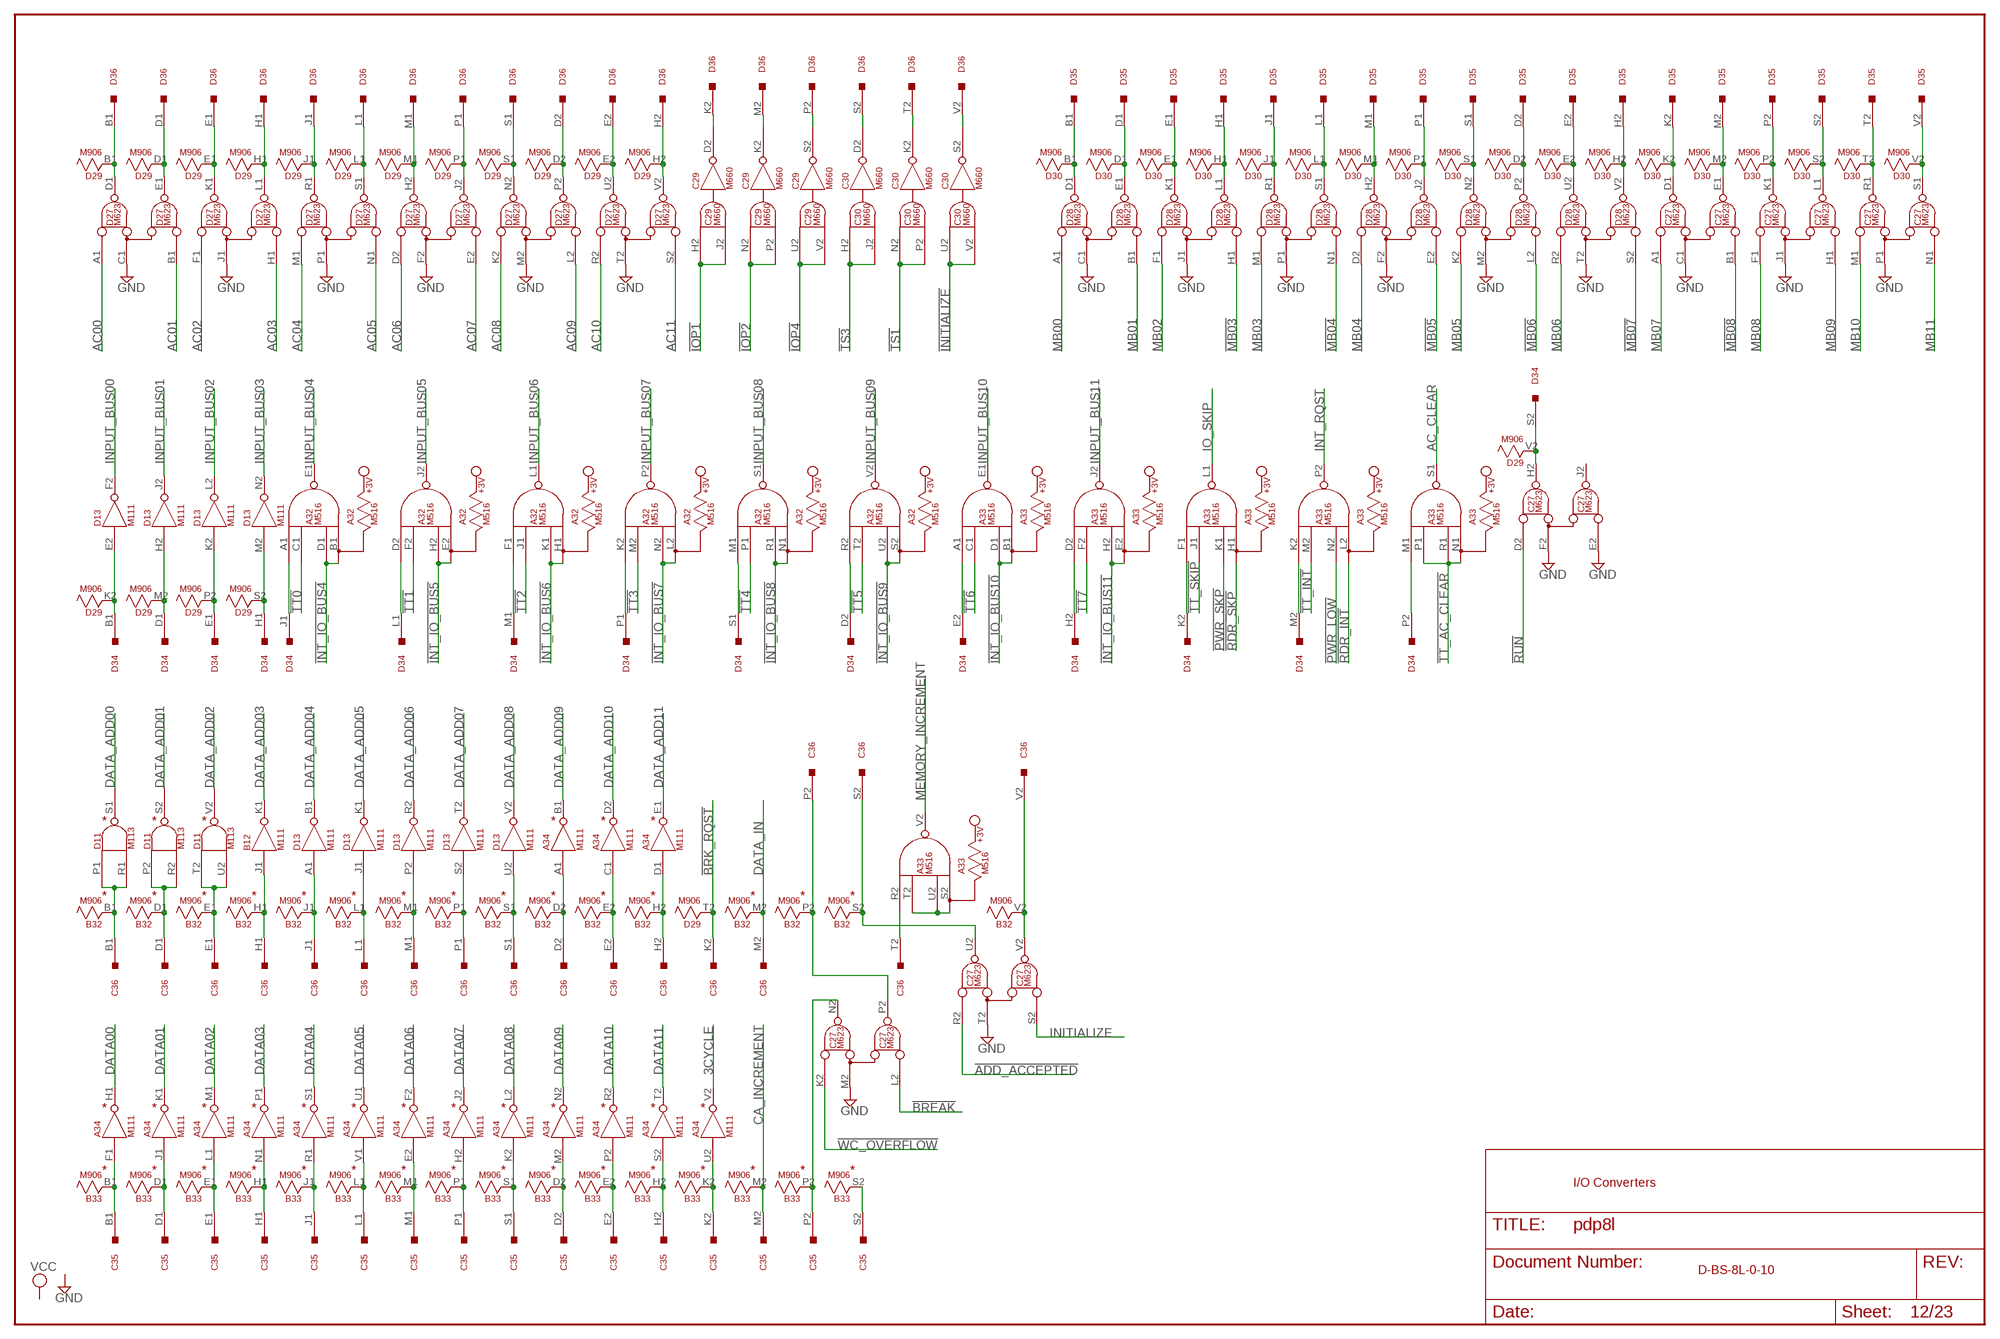
[diagram p11: schematic, sheet 12]
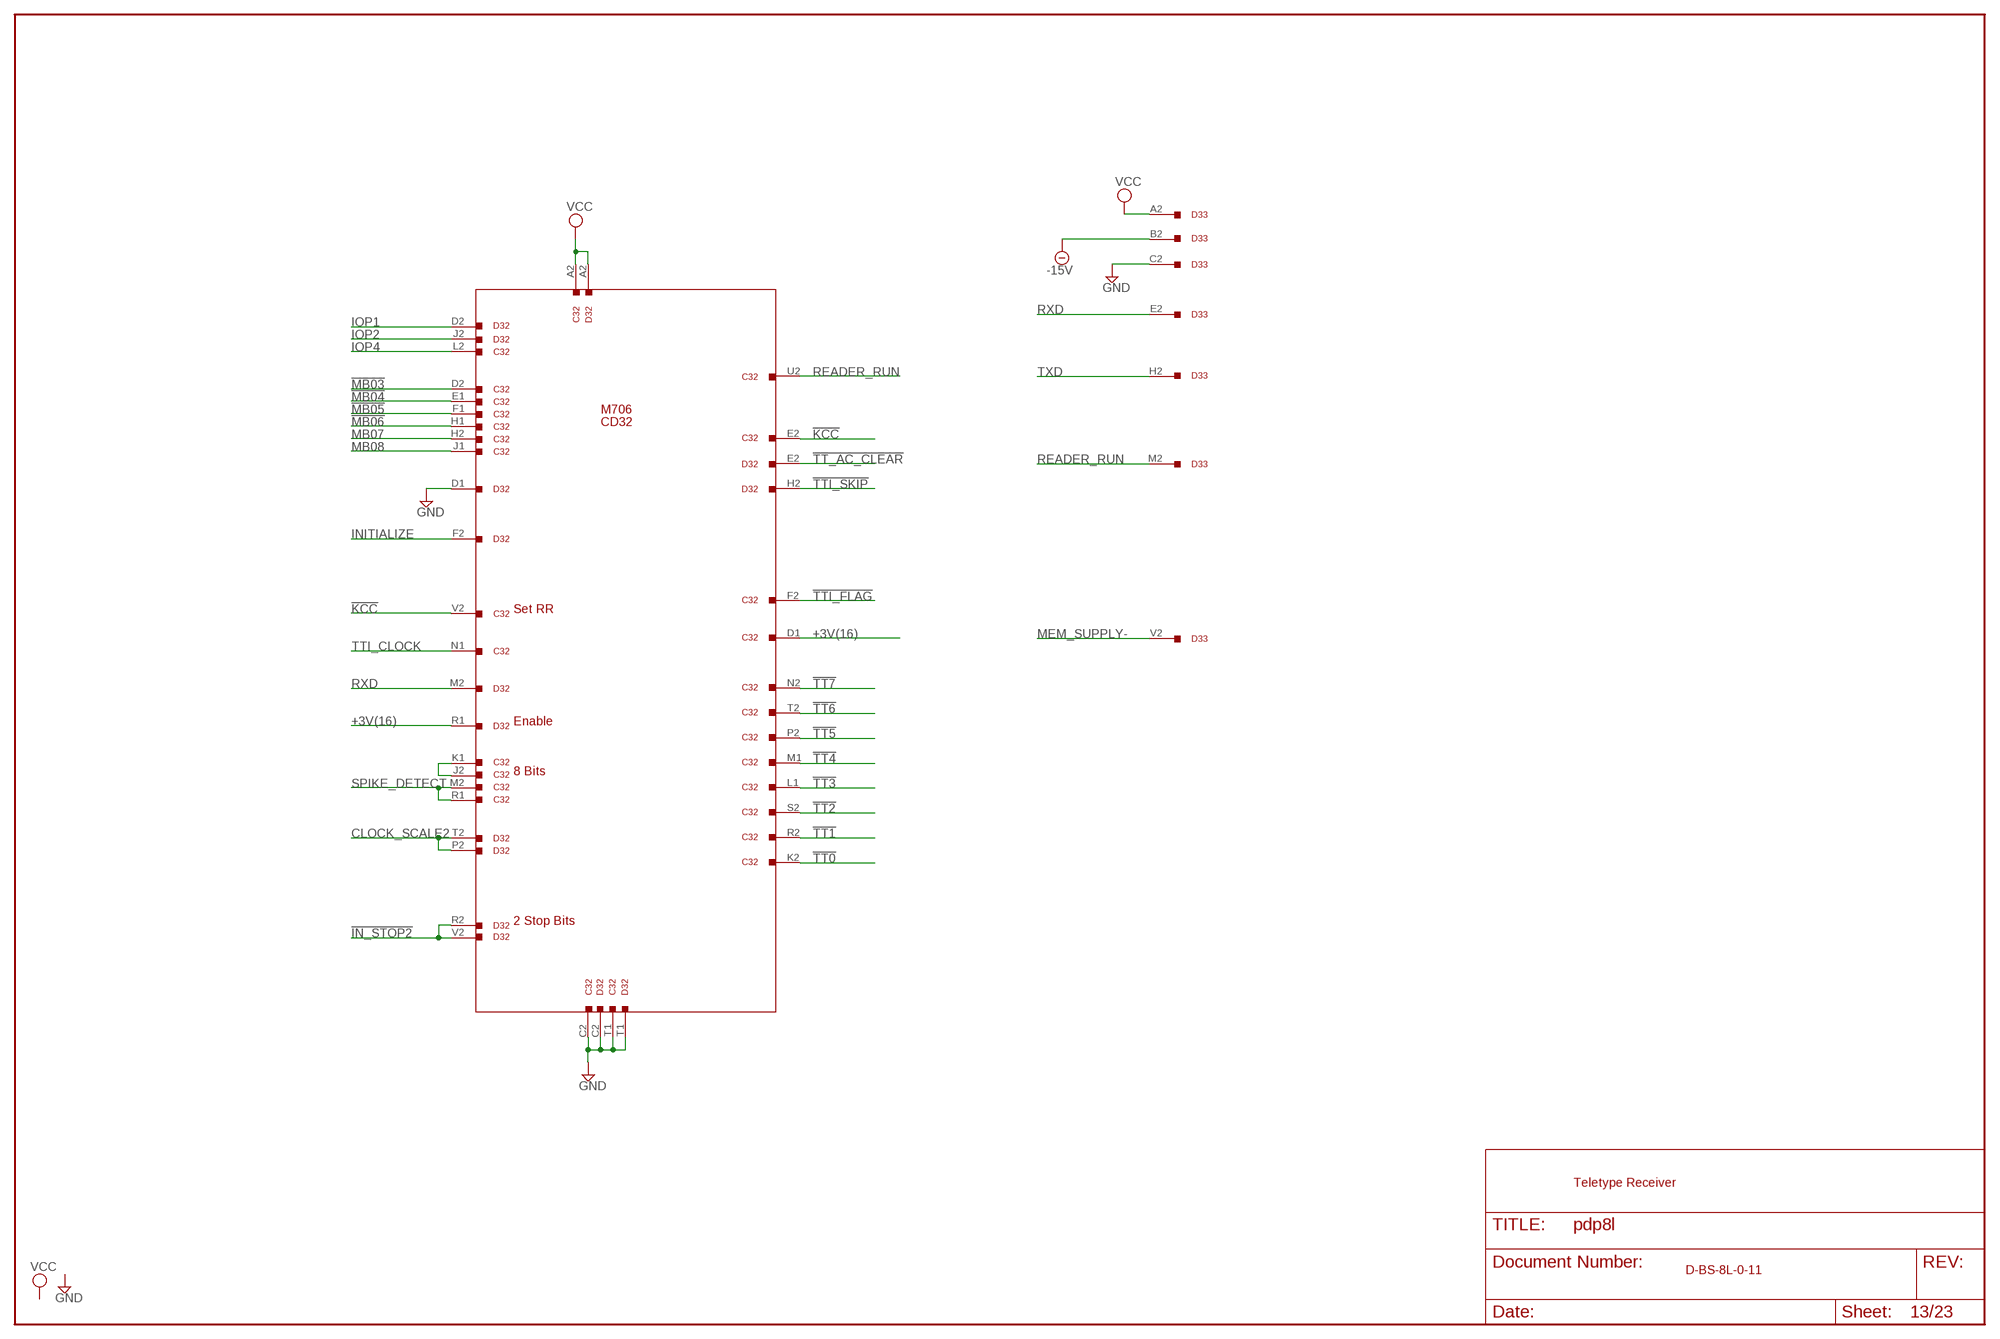
[diagram p12: schematic, sheet 13]
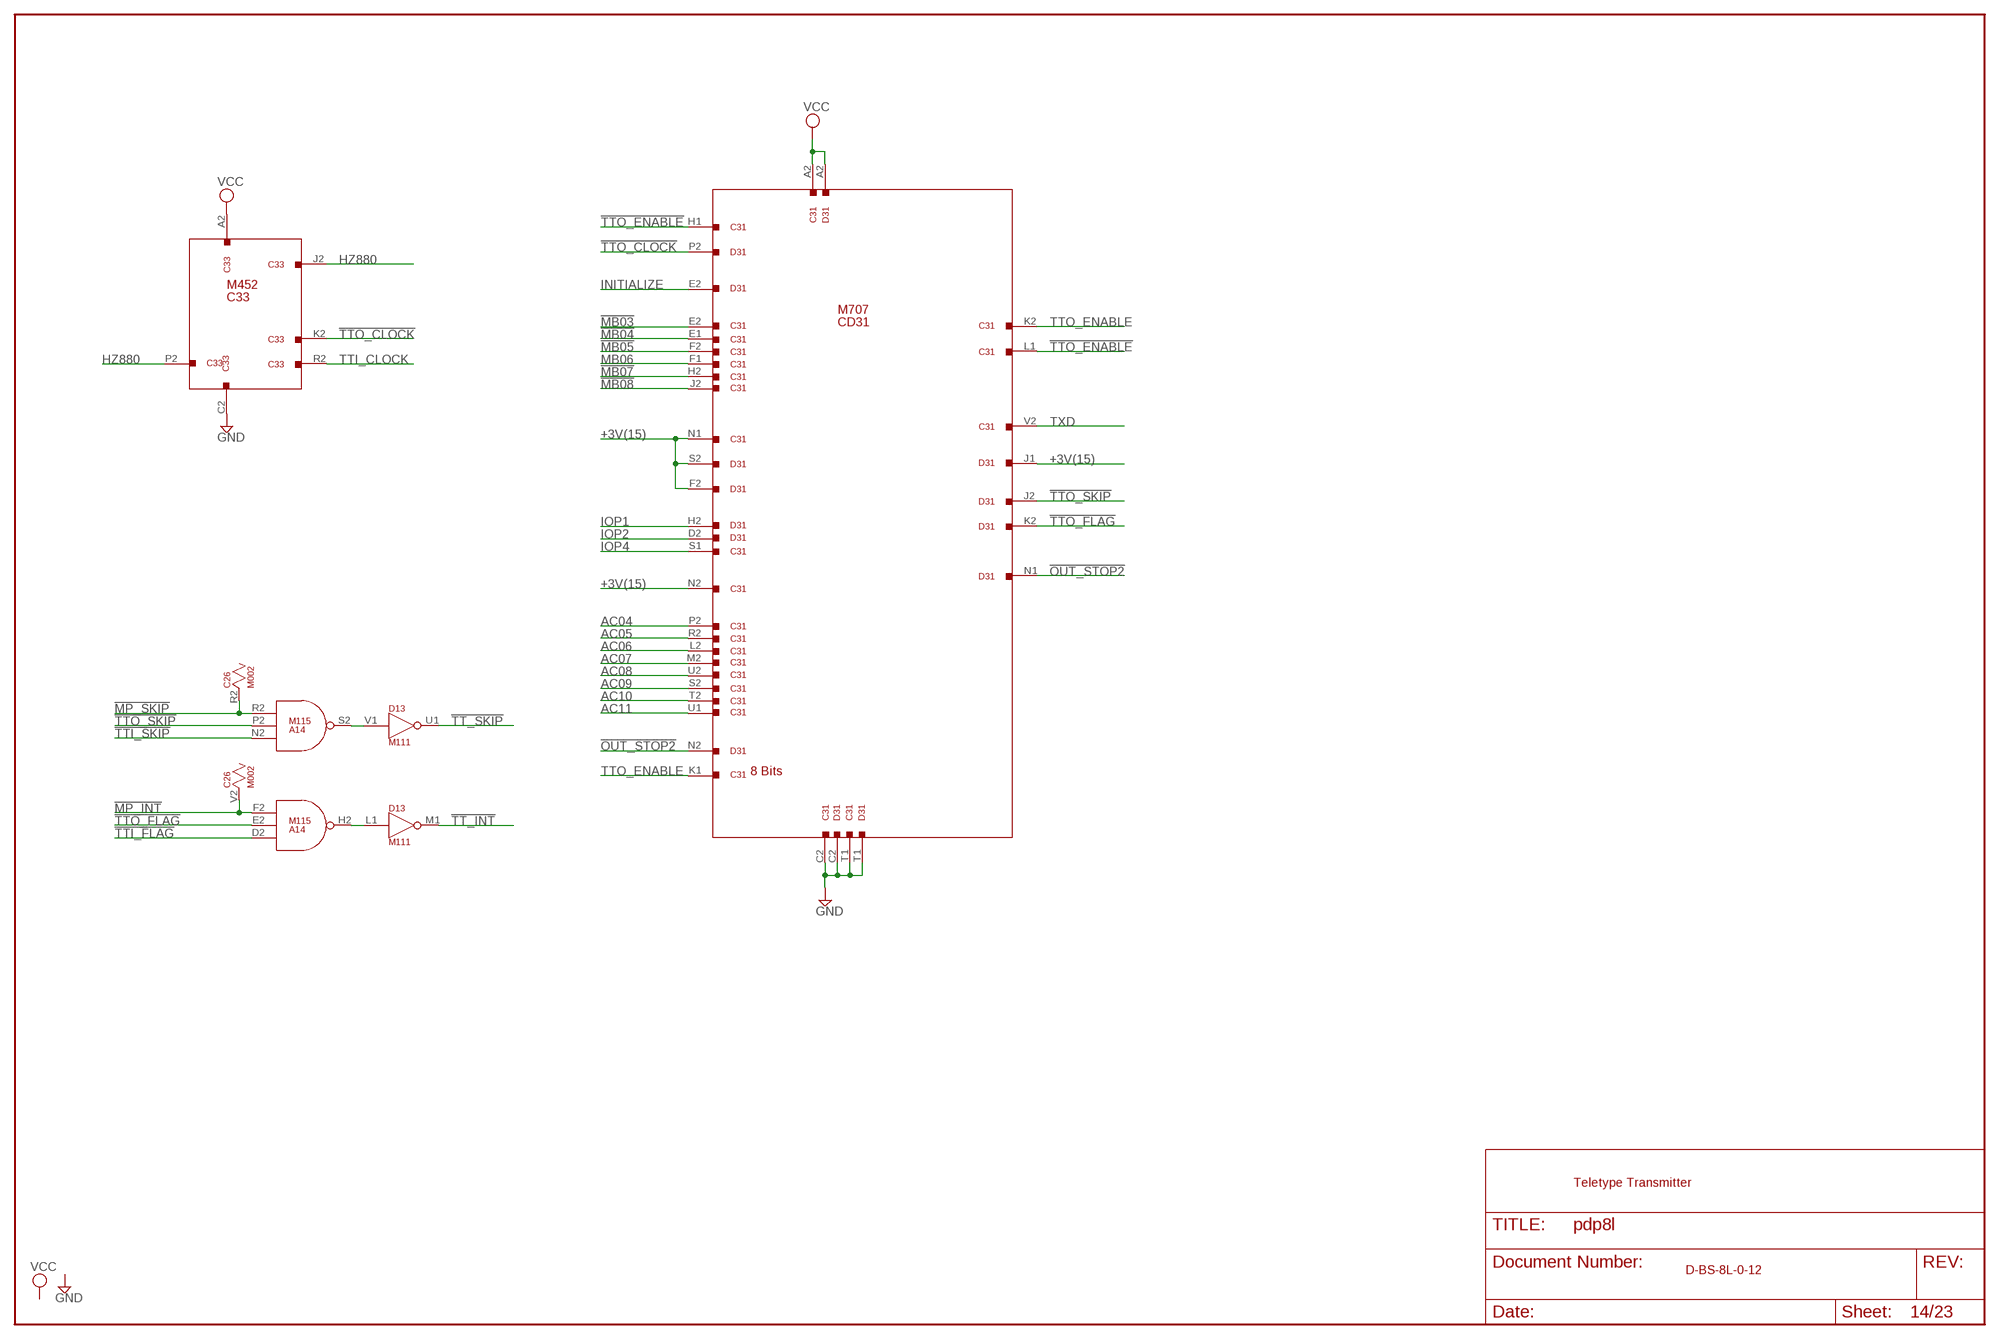
[diagram p13: schematic, sheet 14]
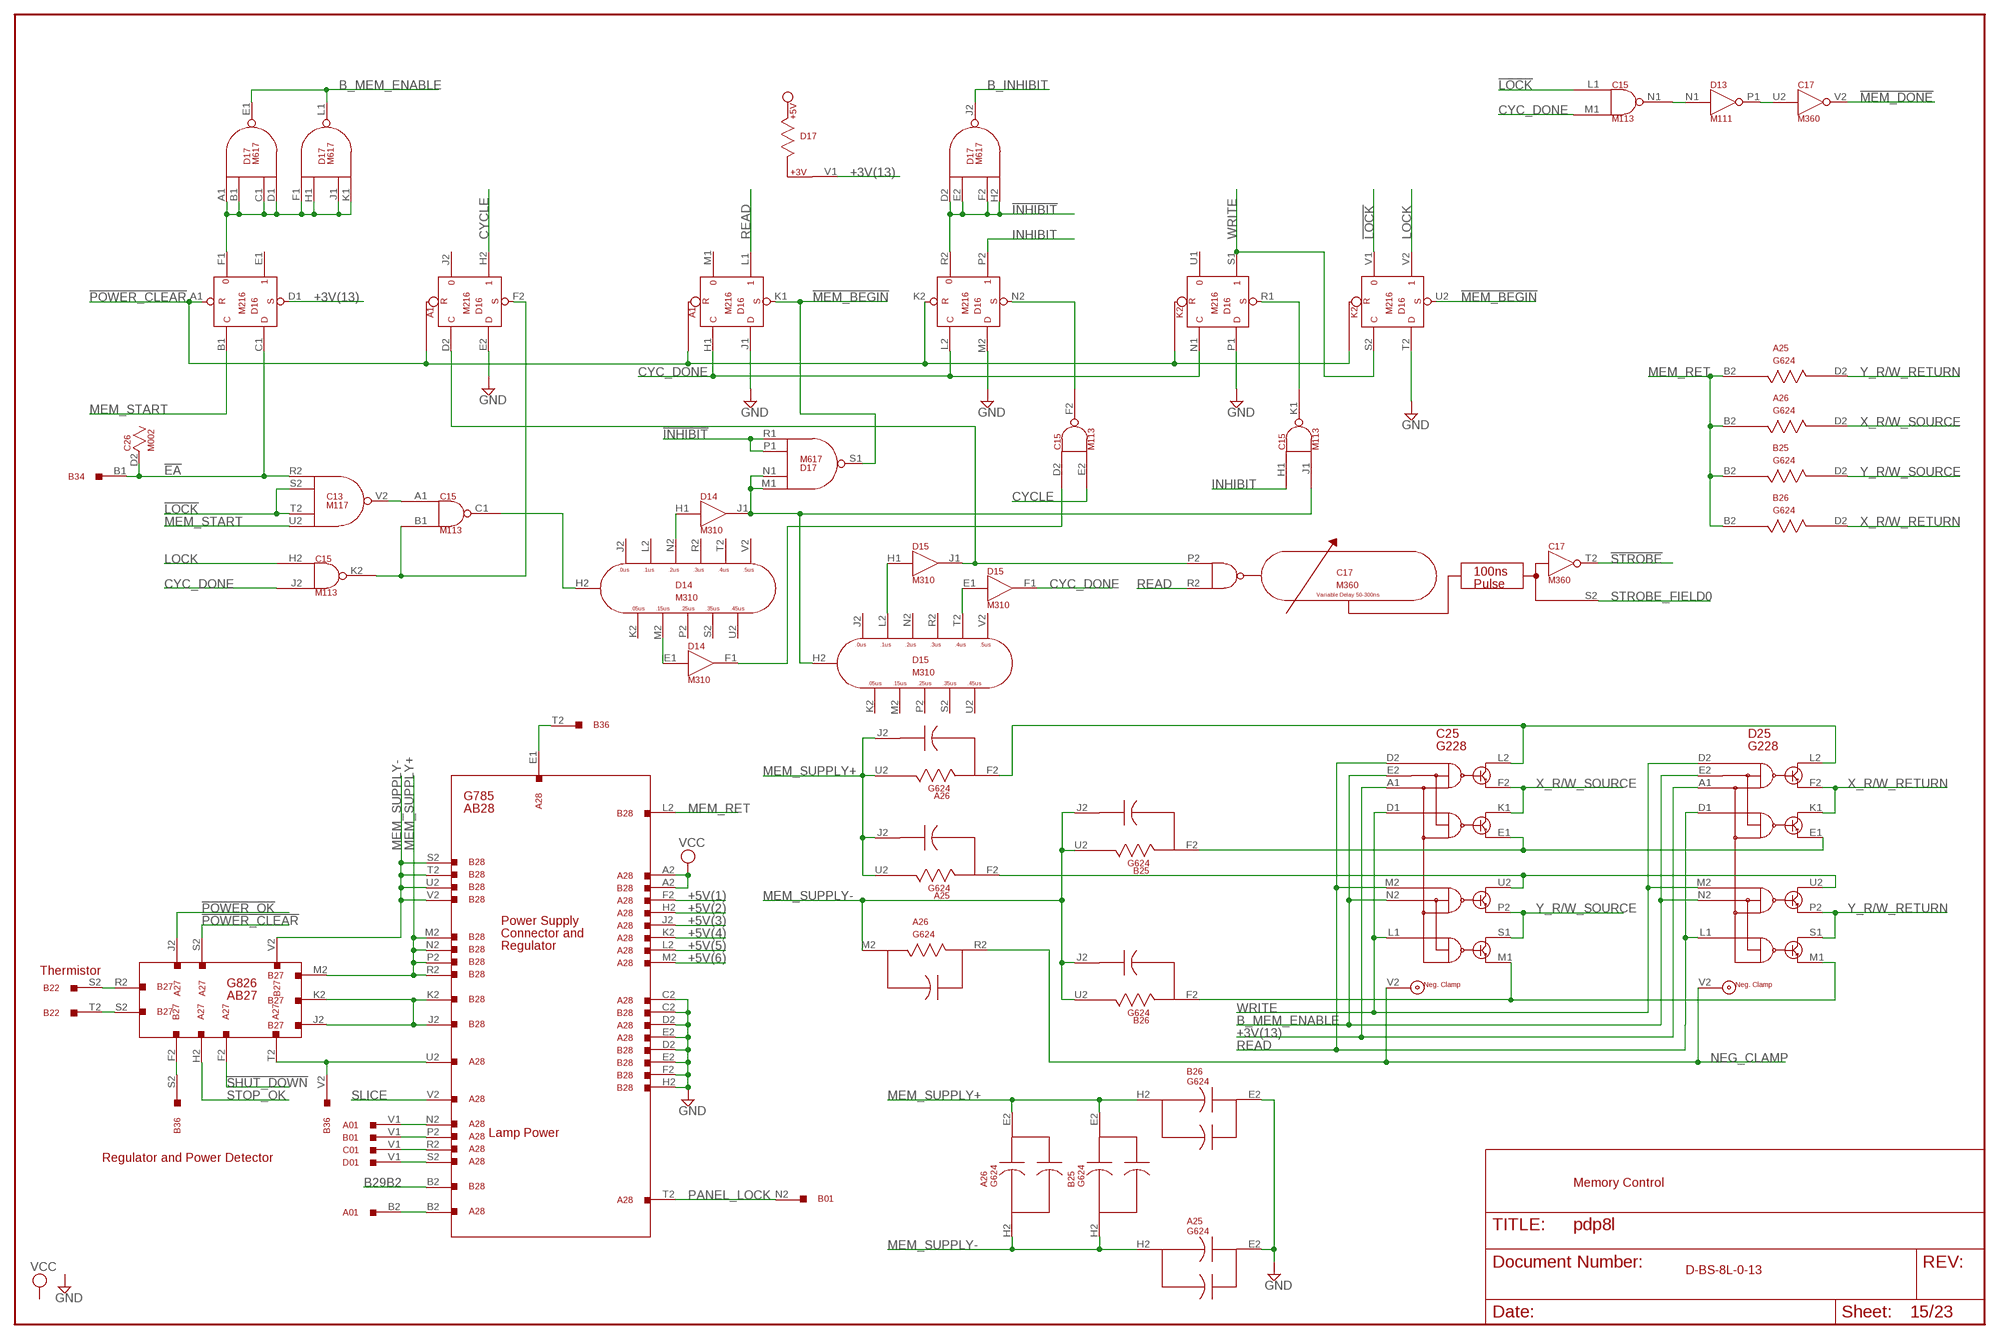
[diagram p14: schematic, sheet 15]
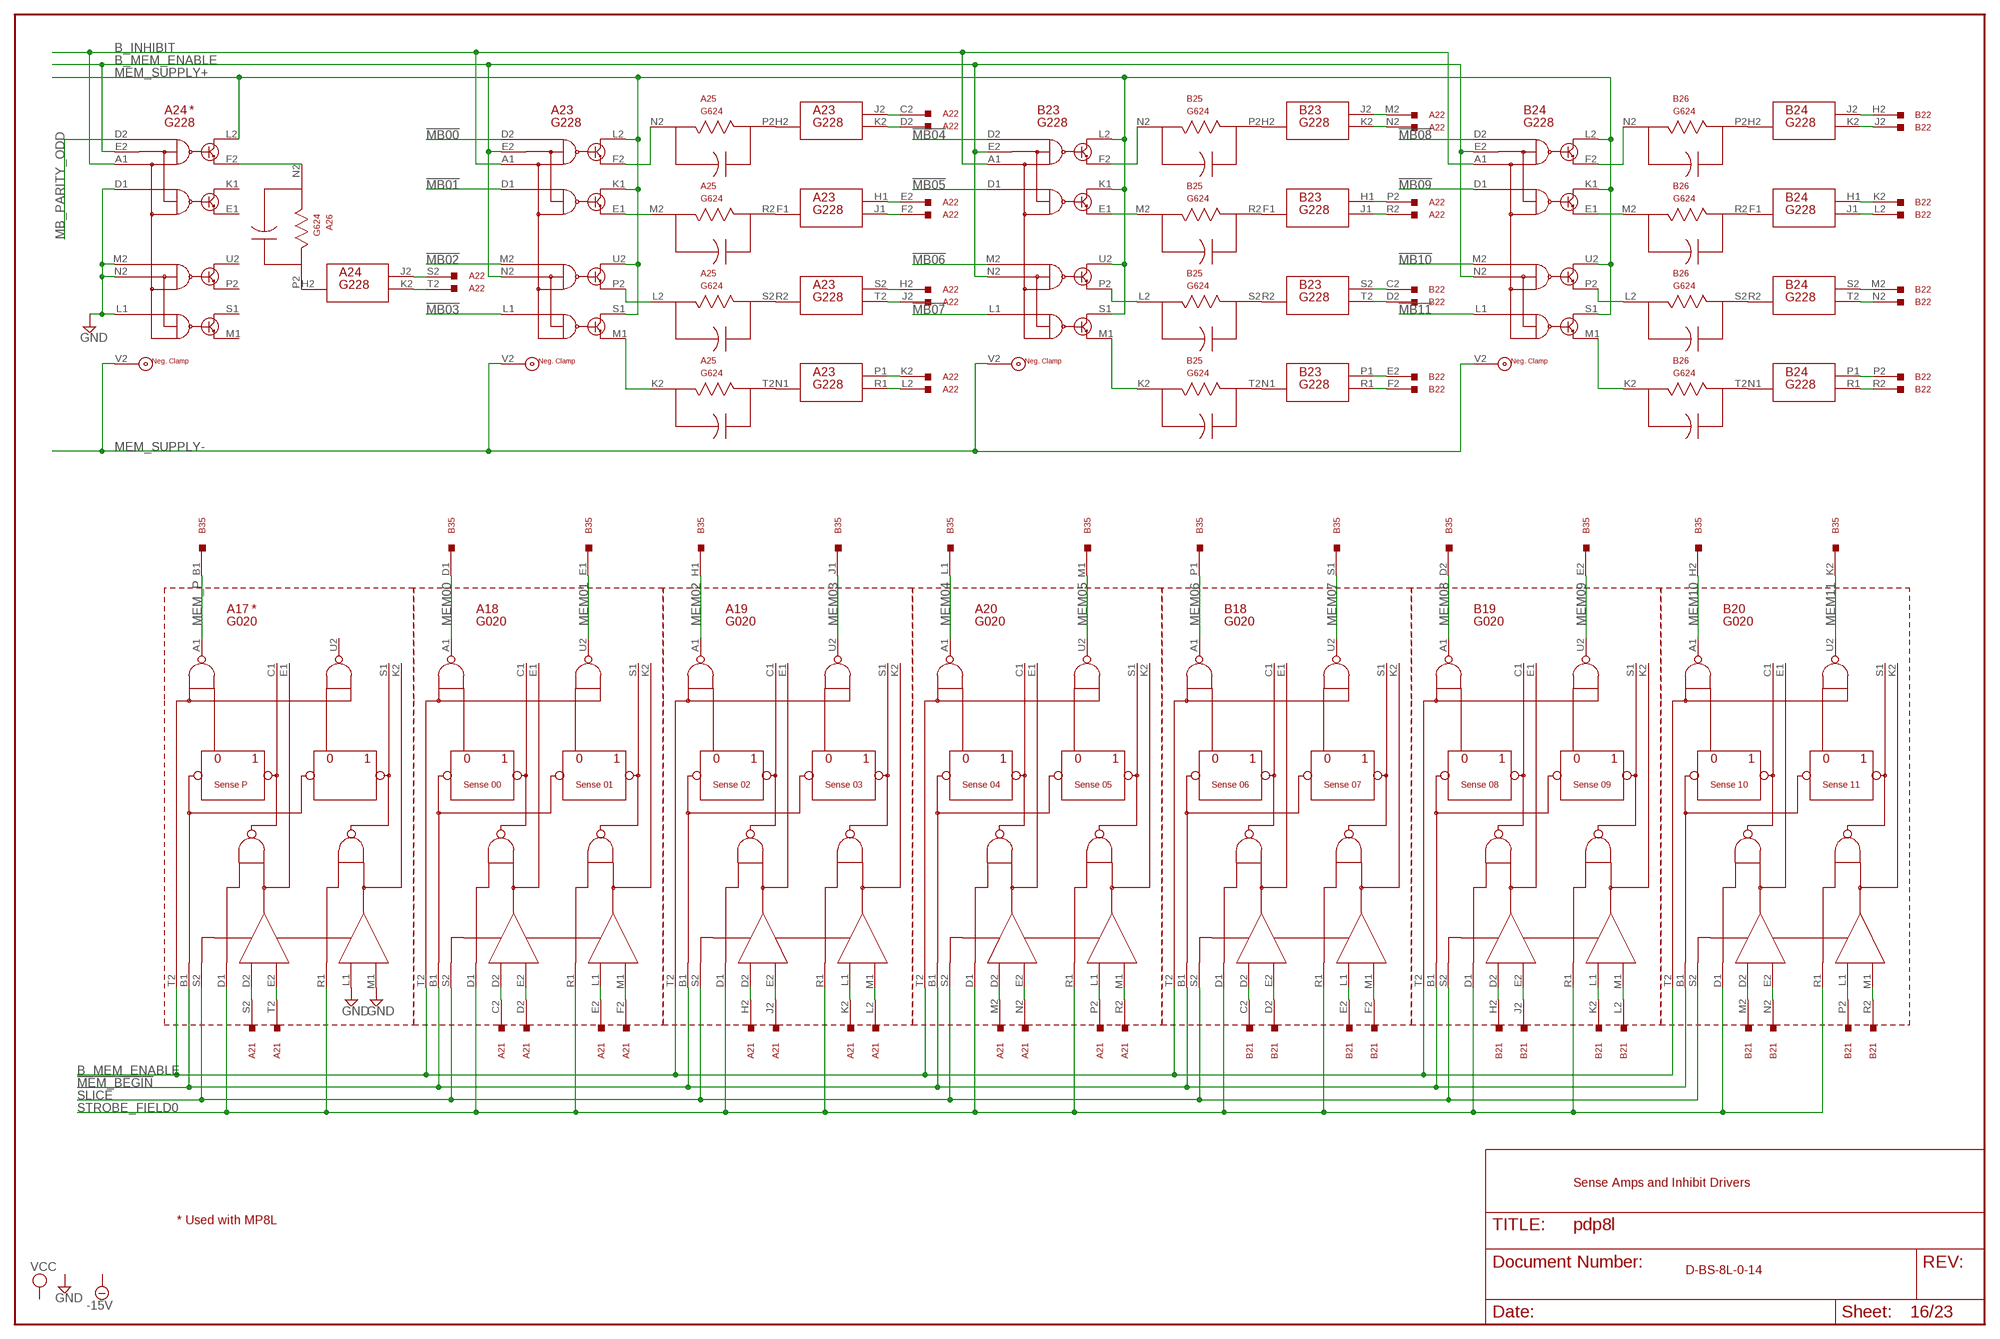
[diagram p15: schematic, sheet 16]
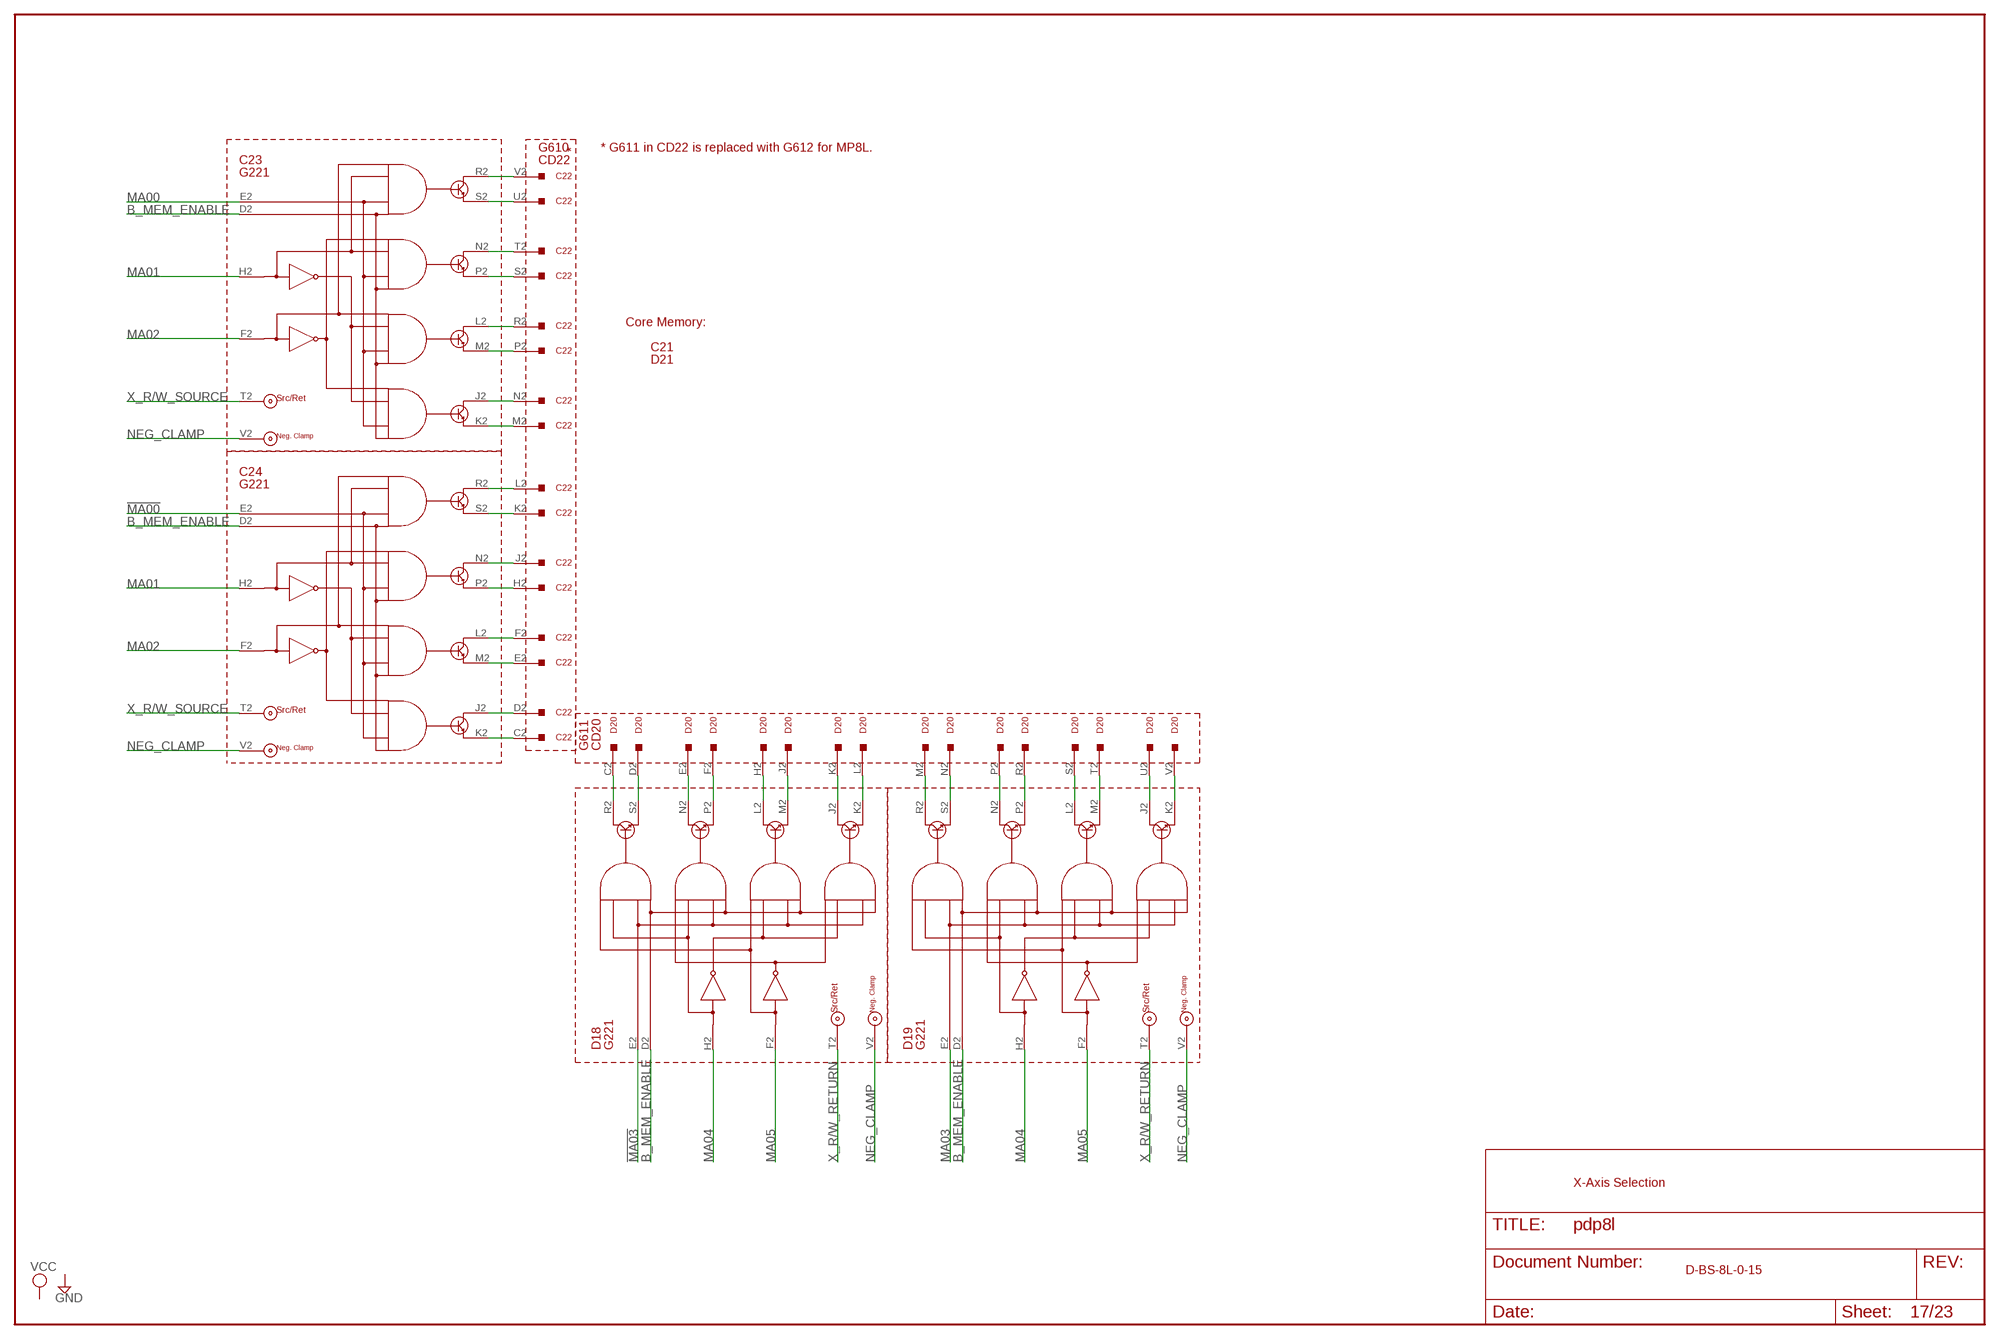
[diagram p16: schematic, sheet 17]
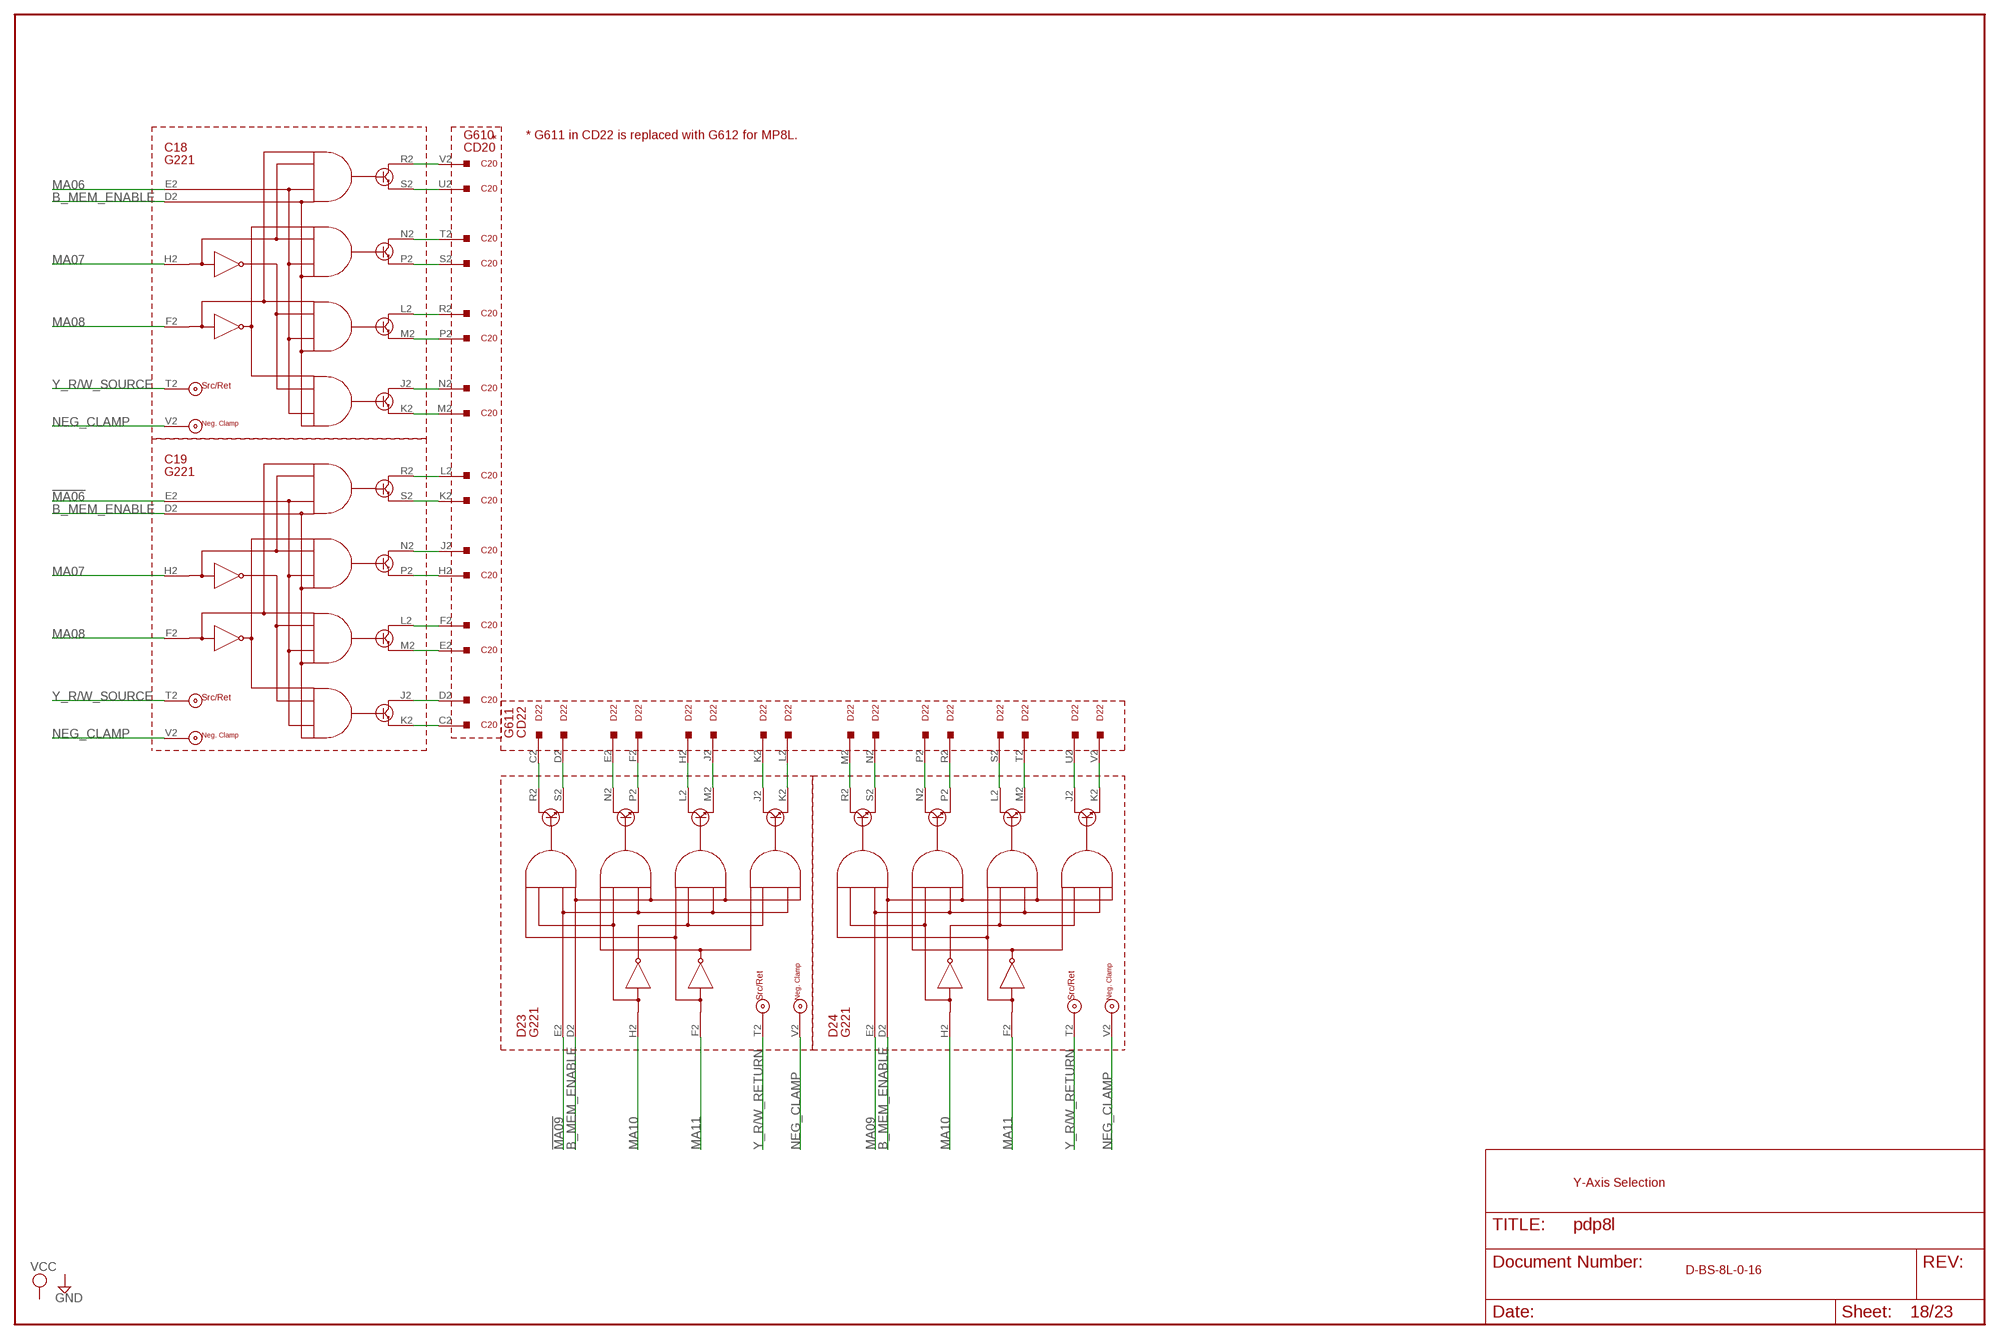
[diagram p17: schematic, sheet 18]
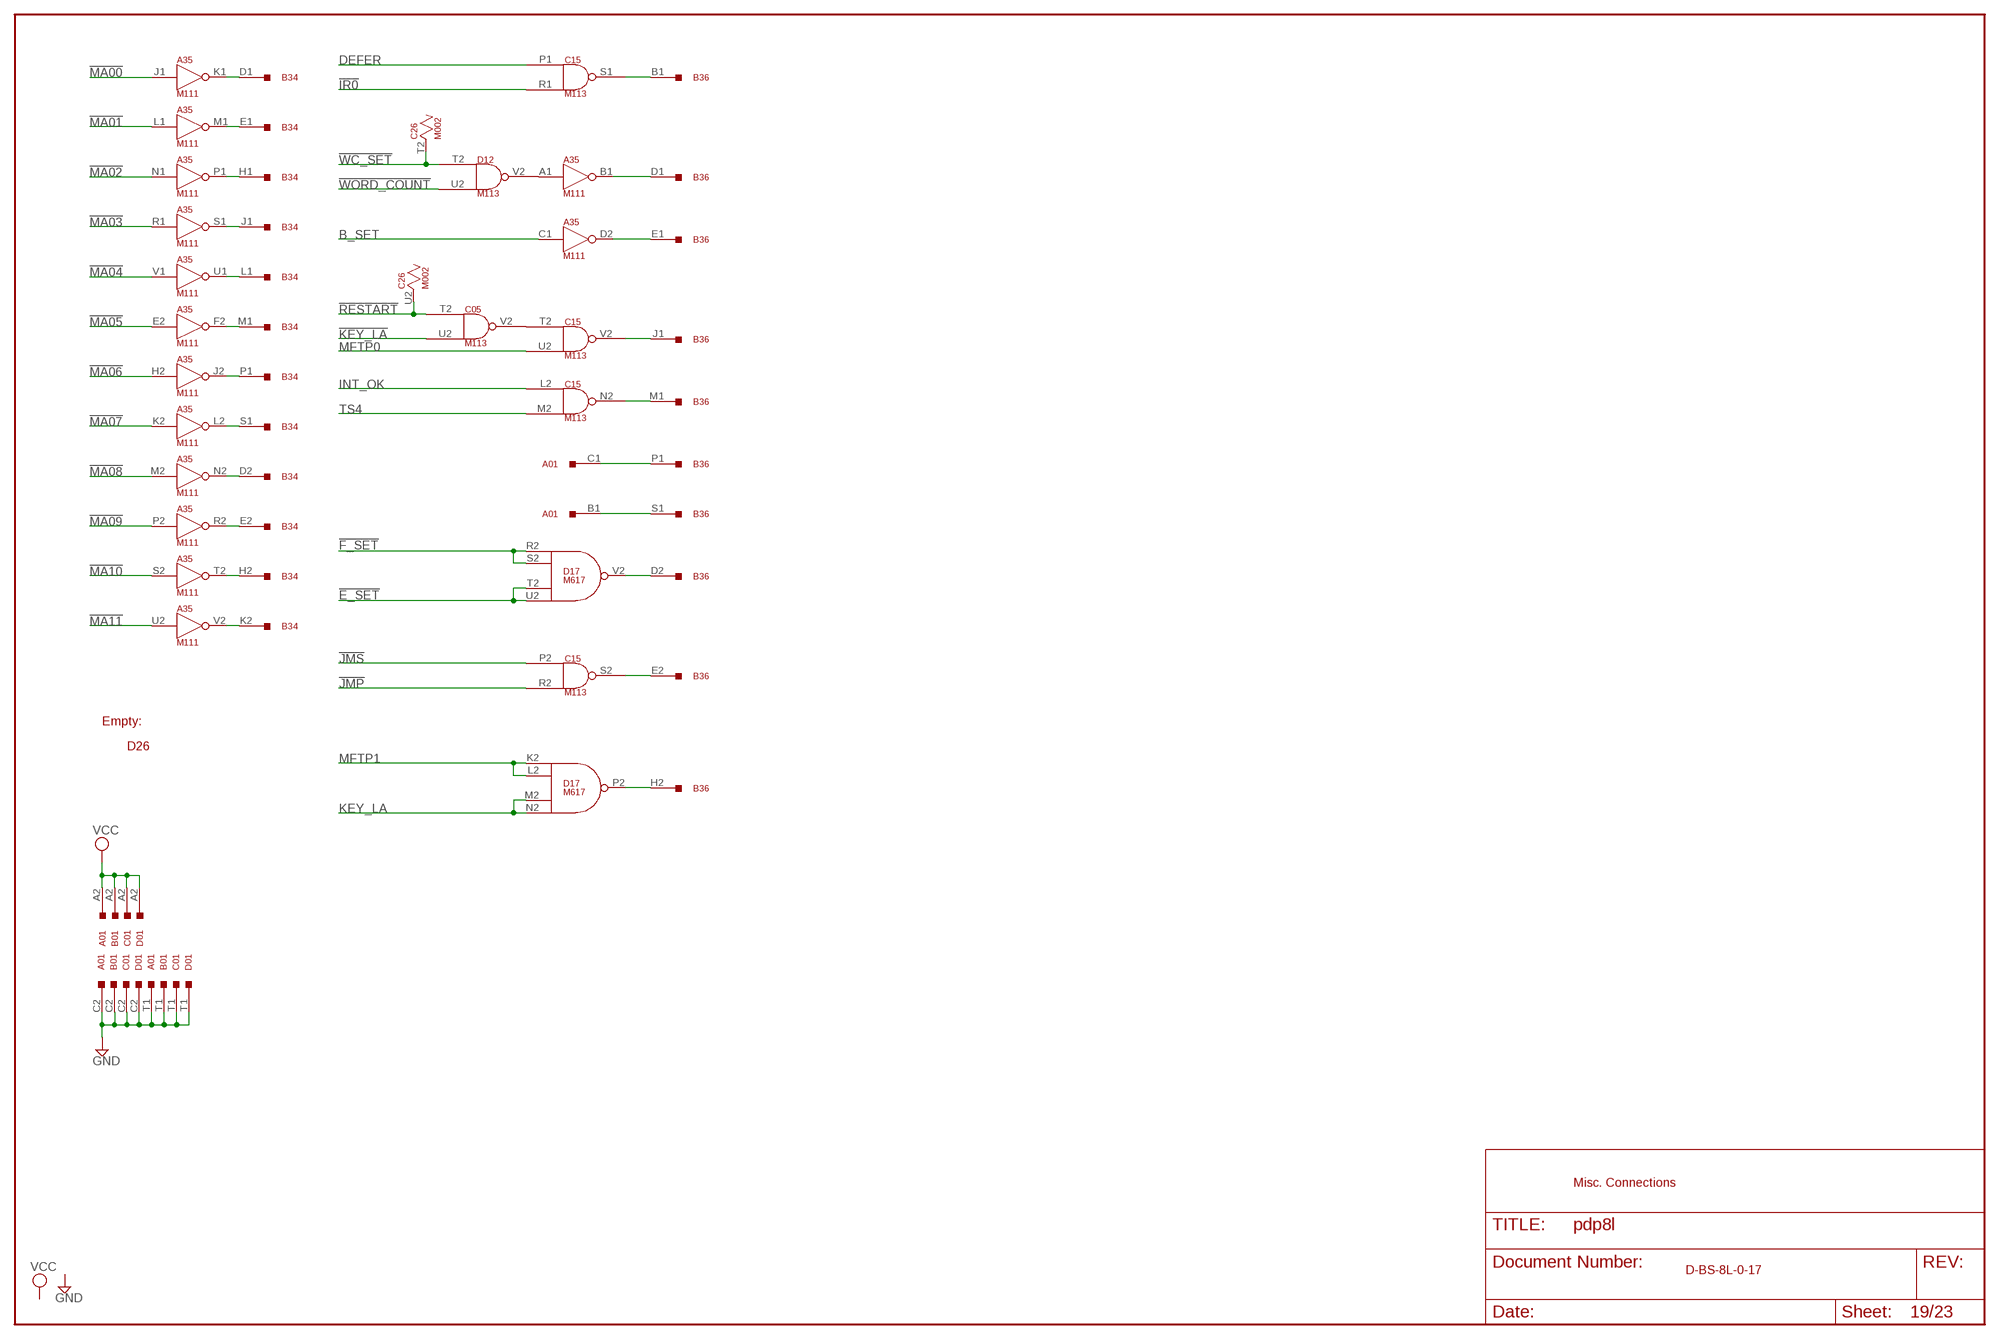
[diagram p18: schematic, sheet 19]
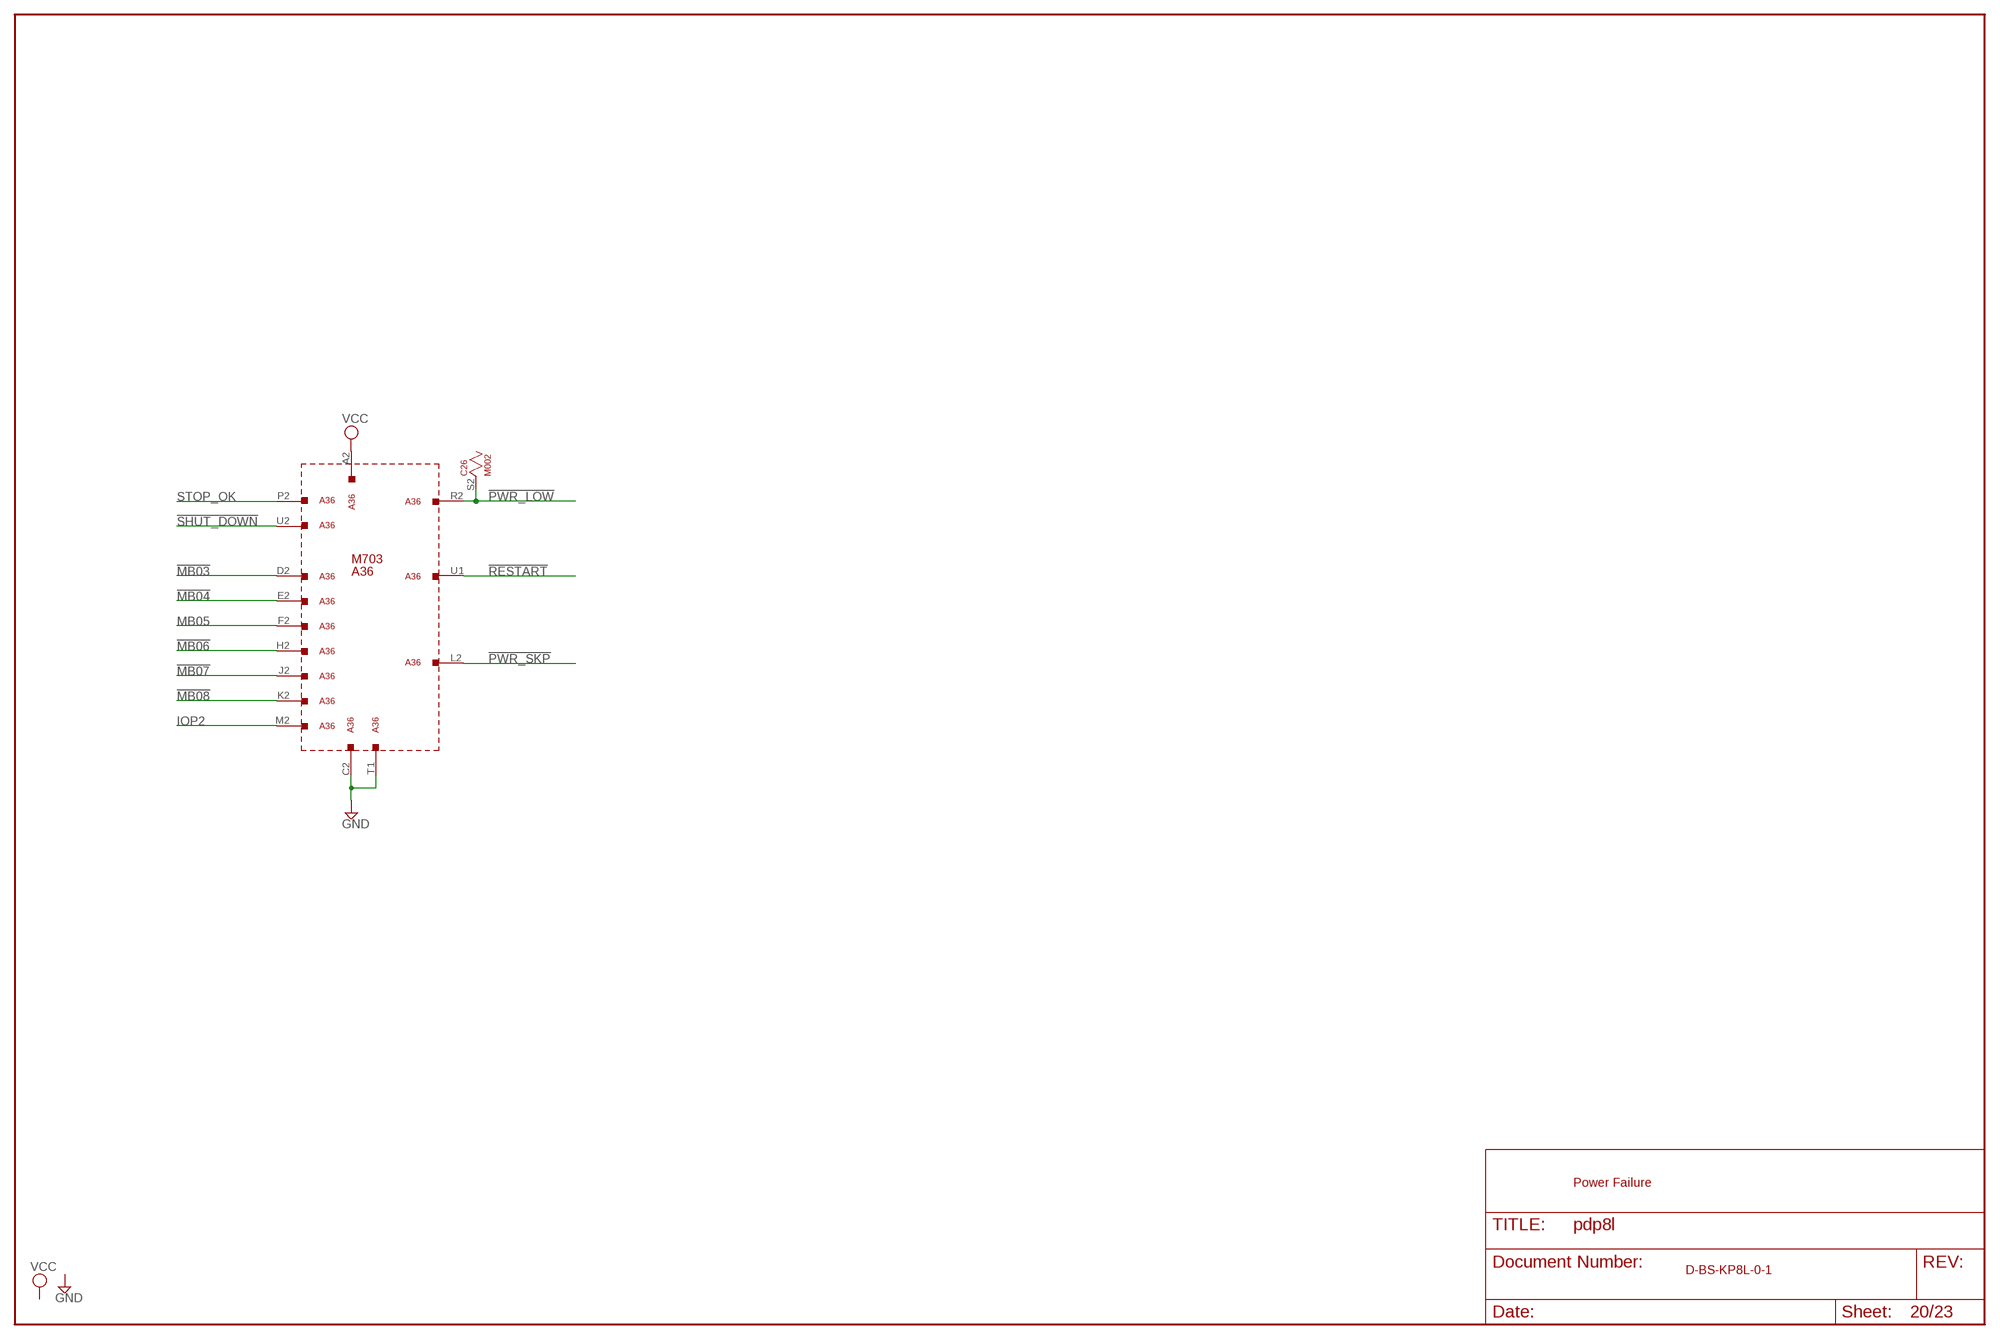
[diagram p19: schematic, sheet 20]
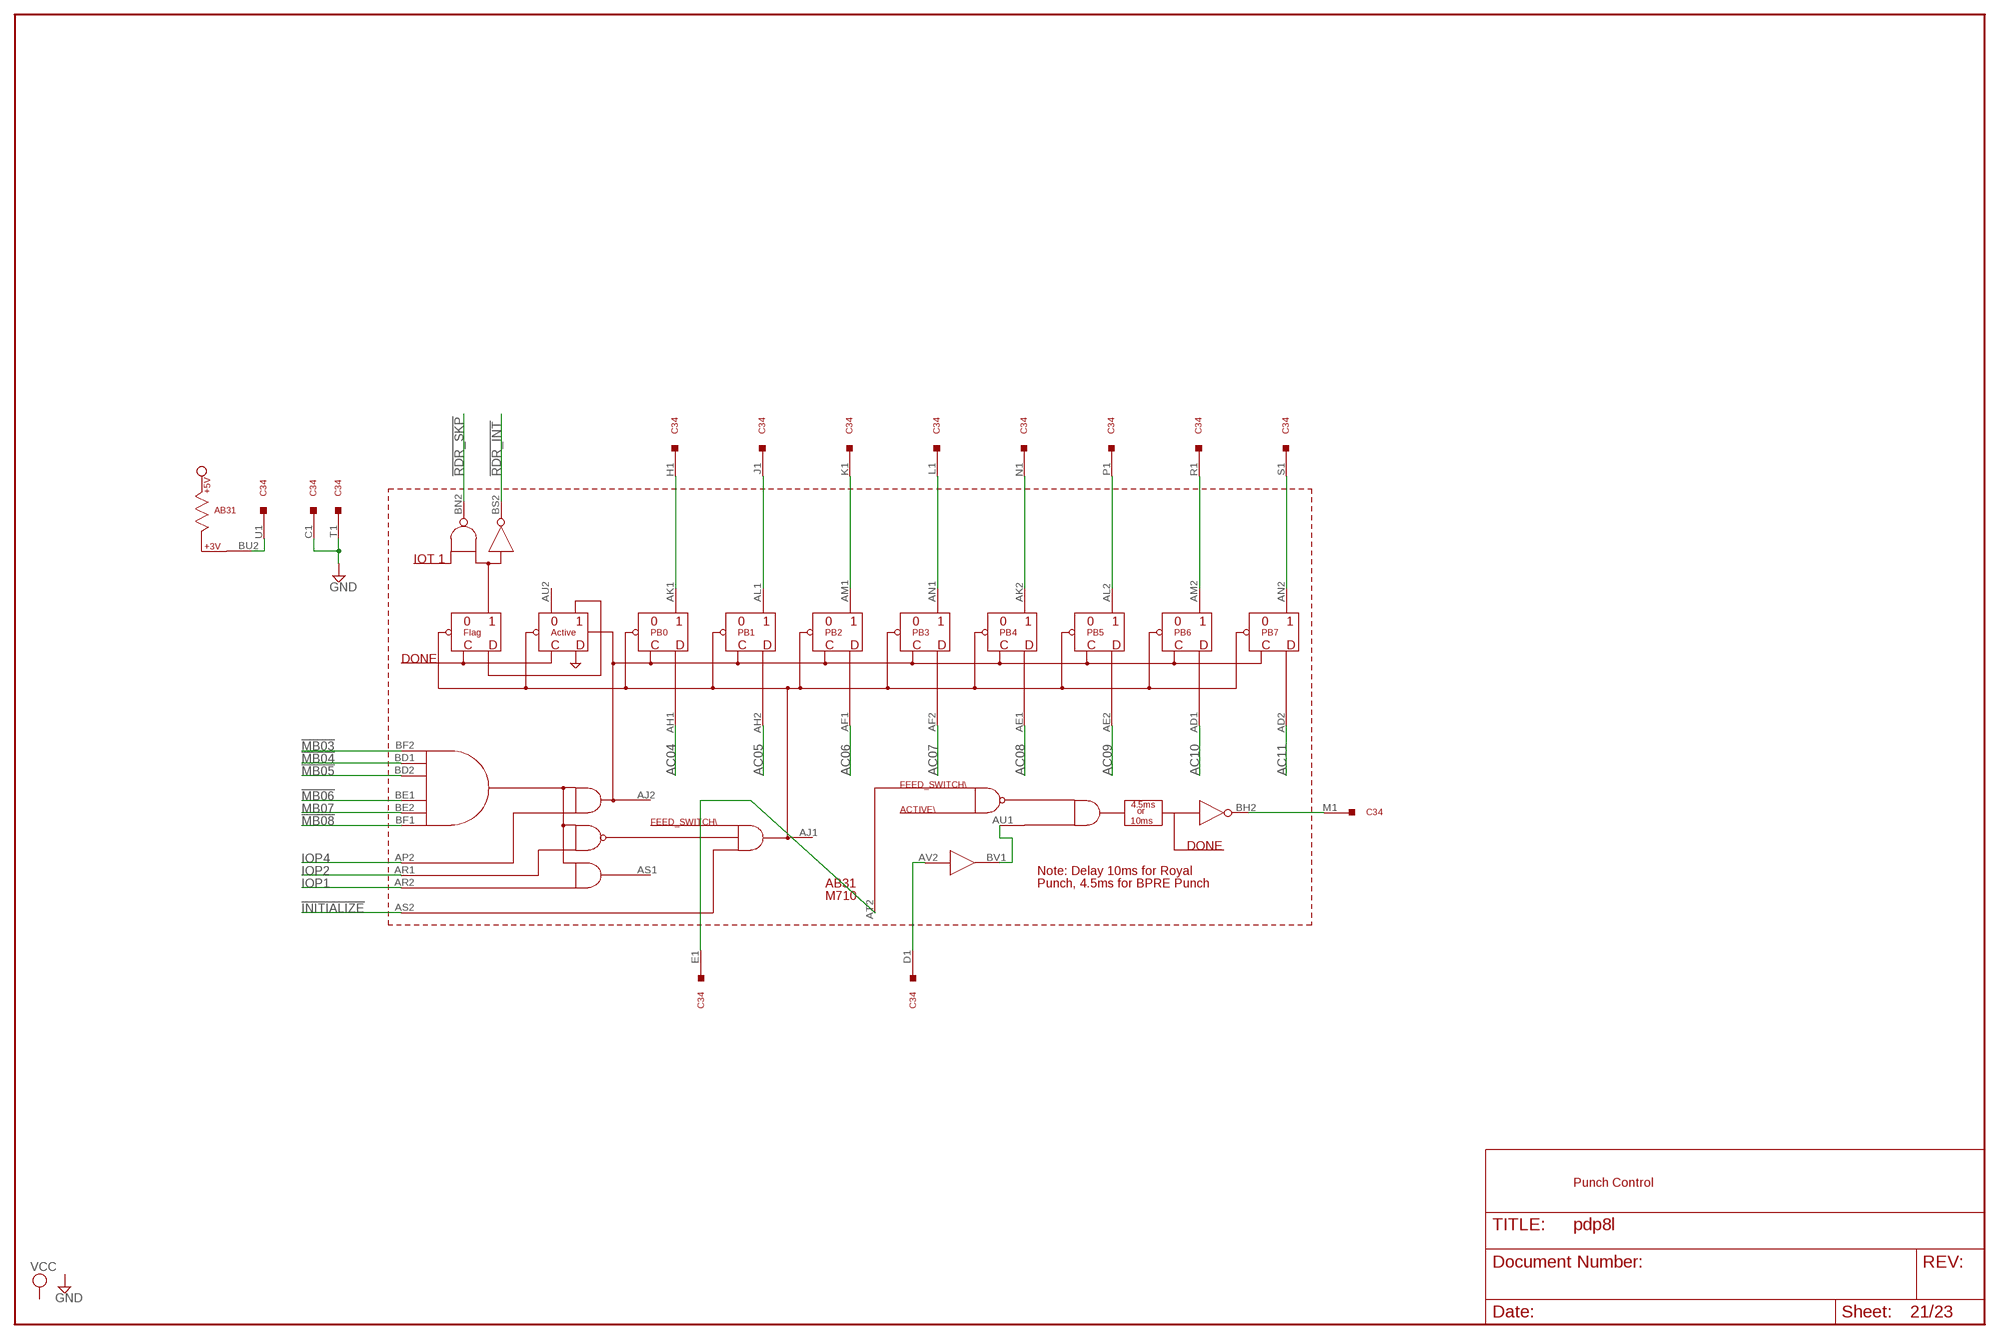
[diagram p20: schematic, sheet 21]
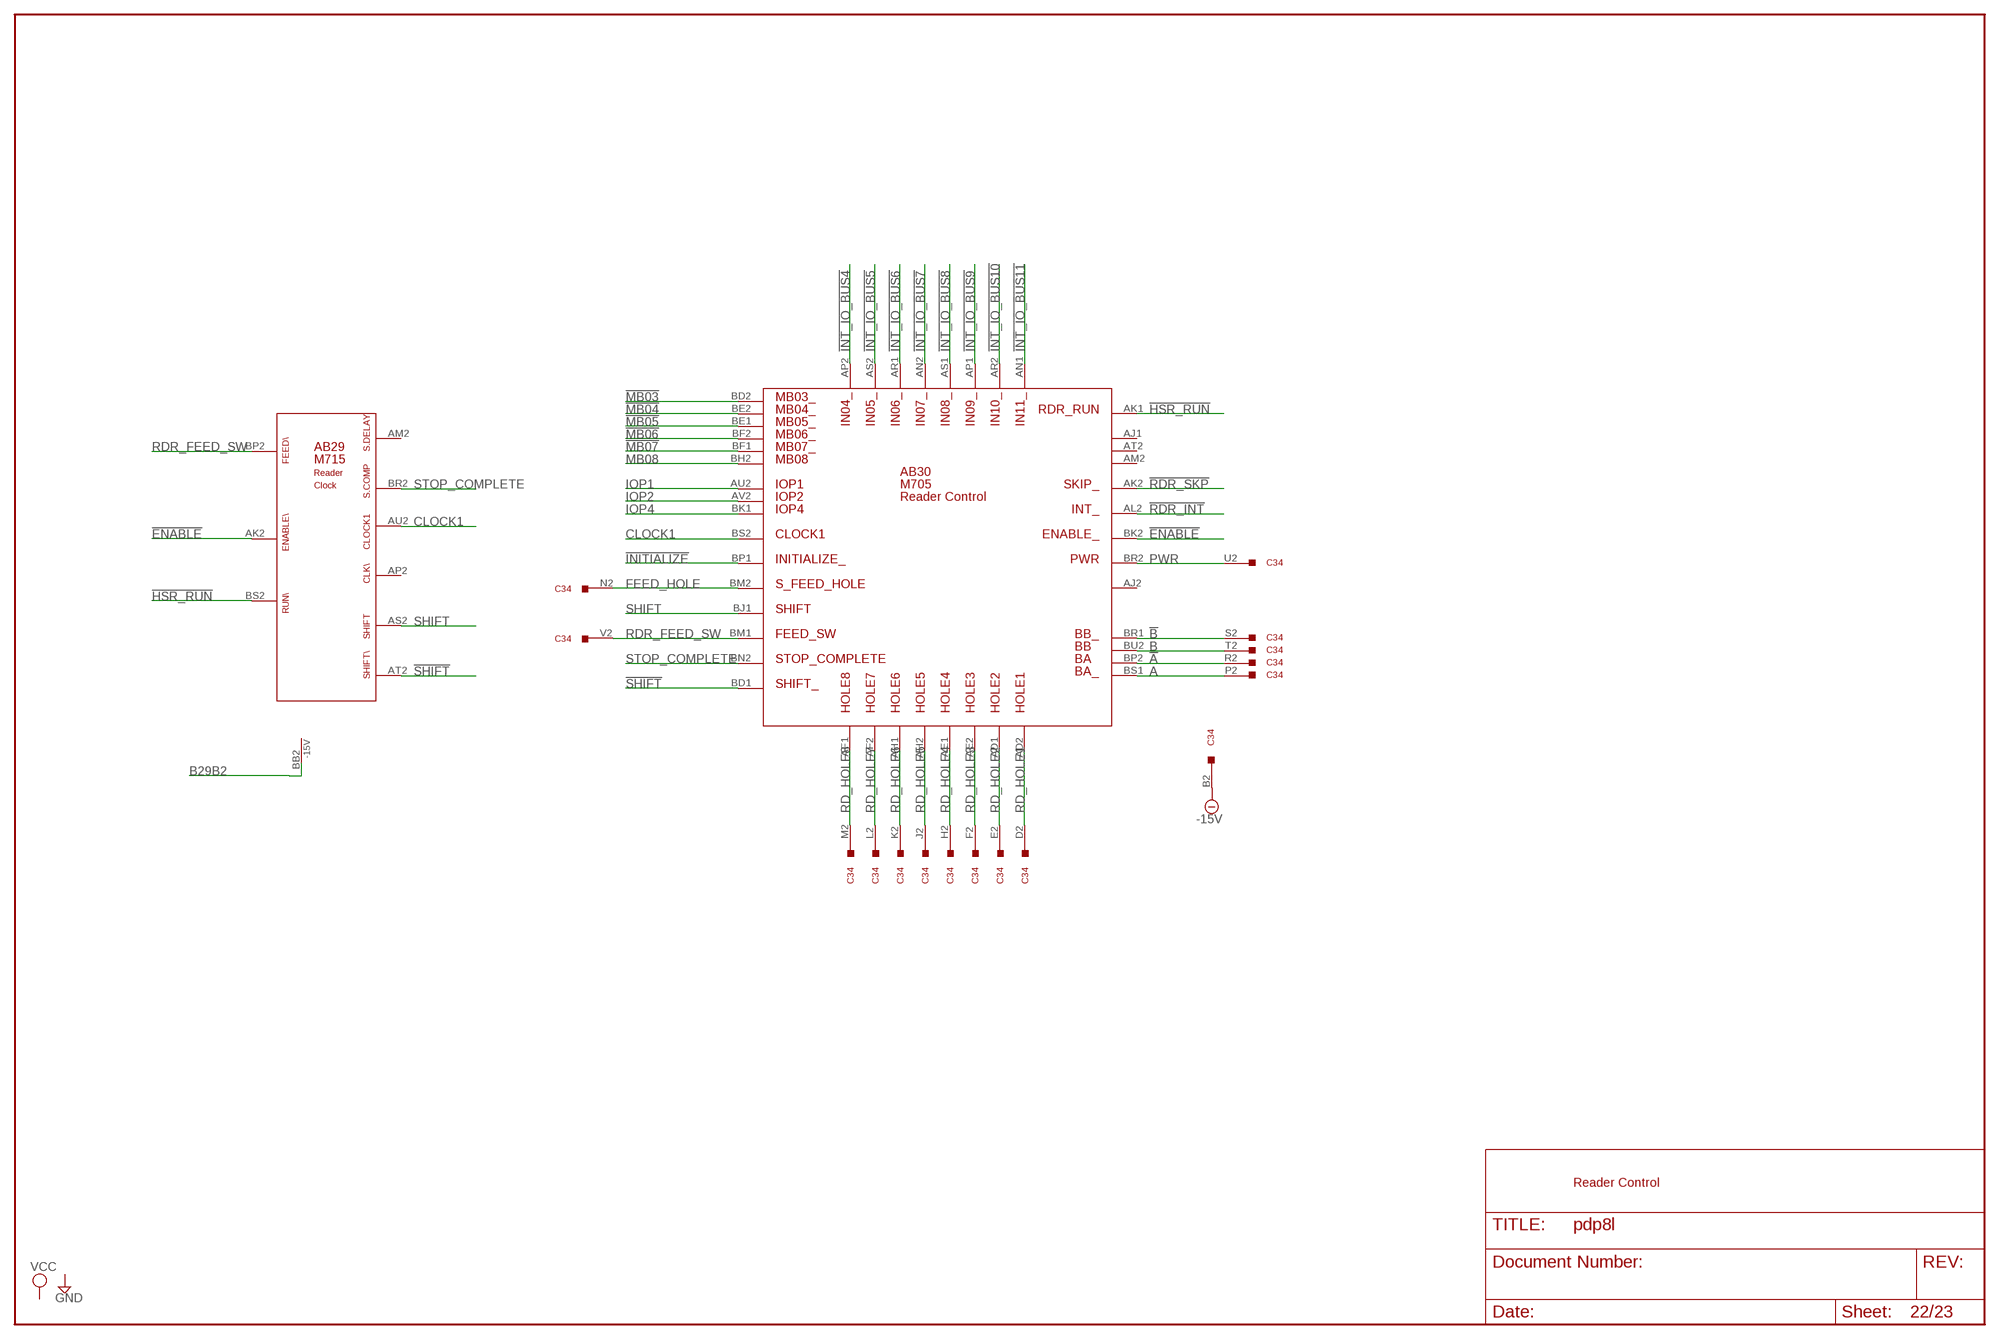
[diagram p21: schematic, sheet 22]
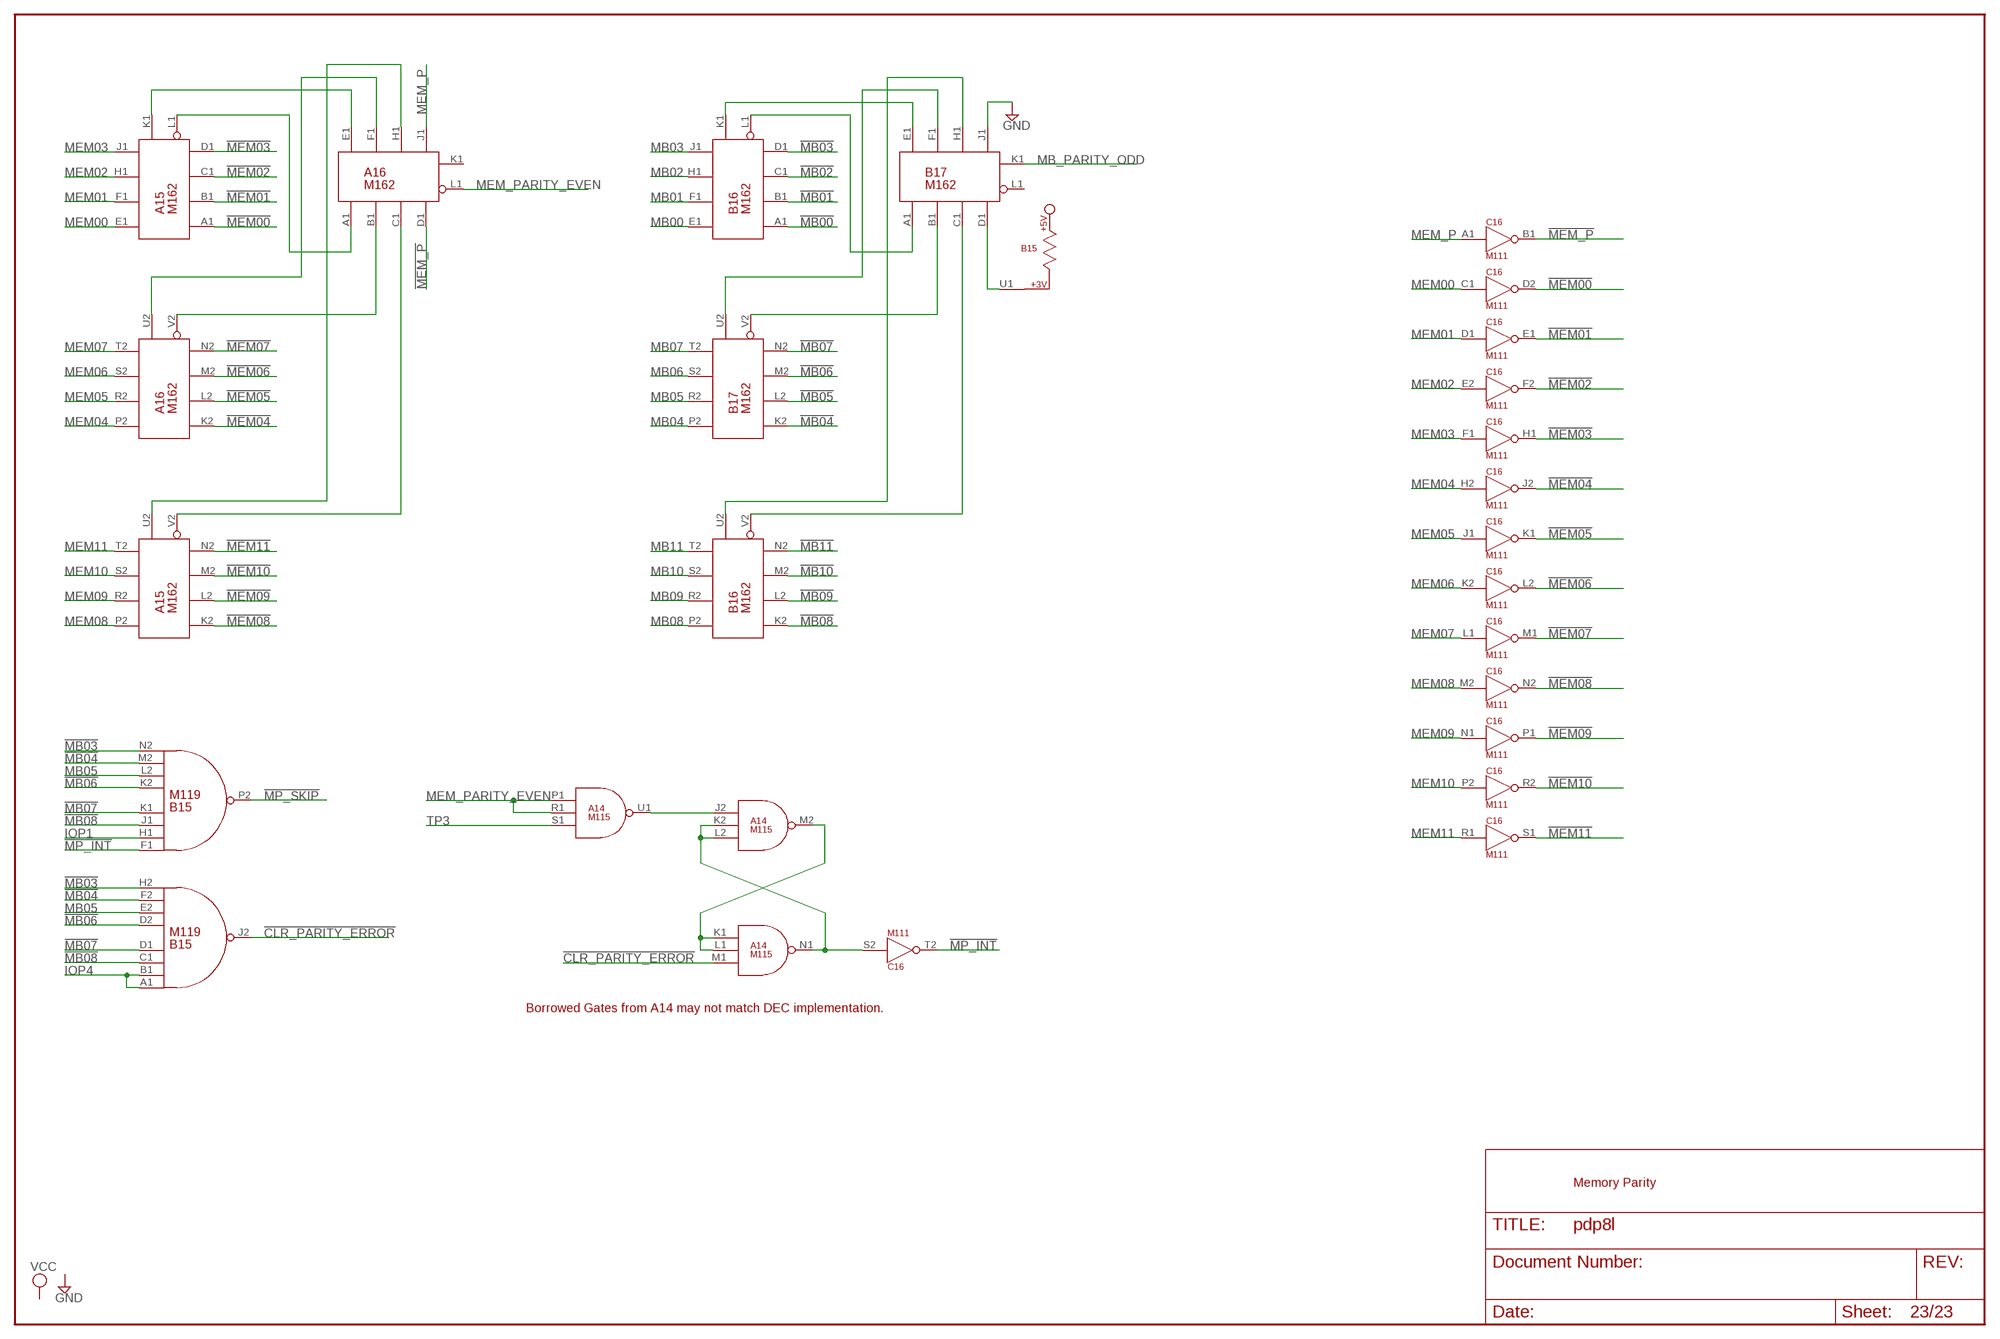
[diagram p22: schematic, sheet 23]

(export (version "E")
  (design (tool "Eeschema 10.0.6"))
  (components
    (comp (ref "A01")
      (value "G921")
      (footprint "eagle-import:H807")
      (libsource (lib "eagle-import") (part "M916"))
    )
    (comp (ref "B09")
      (value "M617")
      (footprint "eagle-import:H807")
      (libsource (lib "eagle-import") (part "M617"))
    )
    (comp (ref "B11")
      (value "M216")
      (footprint "eagle-import:H807")
      (libsource (lib "eagle-import") (part "M206X"))
    )
    (comp (ref "B35")
      (value "M903")
      (footprint "eagle-import:H807")
      (libsource (lib "eagle-import") (part "M903"))
    )
    (comp (ref "C01")
      (value "G921")
      (footprint "eagle-import:H807")
      (libsource (lib "eagle-import") (part "M916"))
    )
    (comp (ref "C06")
      (value "M216")
      (footprint "eagle-import:H807")
      (libsource (lib "eagle-import") (part "M206X"))
    )
    (comp (ref "C07")
      (value "M111")
      (footprint "eagle-import:H807")
      (libsource (lib "eagle-import") (part "M111"))
    )
    (comp (ref "C08")
      (value "M216")
      (footprint "eagle-import:H807")
      (libsource (lib "eagle-import") (part "M206X"))
    )
    (comp (ref "C09")
      (value "M115")
      (footprint "eagle-import:H807")
      (libsource (lib "eagle-import") (part "M115"))
    )
    (comp (ref "C10")
      (value "M119")
      (footprint "eagle-import:H807")
      (libsource (lib "eagle-import") (part "M119"))
    )
    (comp (ref "C11")
      (value "M117")
      (footprint "eagle-import:H807")
      (libsource (lib "eagle-import") (part "M117"))
    )
    (comp (ref "C26")
      (value "M002")
      (footprint "eagle-import:H807")
      (libsource (lib "eagle-import") (part "M002"))
    )
    (comp (ref "D01")
      (value "G921")
      (footprint "eagle-import:H807")
      (libsource (lib "eagle-import") (part "M916"))
    )
    (comp (ref "D02")
      (value "M111")
      (footprint "eagle-import:H807")
      (libsource (lib "eagle-import") (part "M111"))
    )
    (comp (ref "D04")
      (value "M115")
      (footprint "eagle-import:H807")
      (libsource (lib "eagle-import") (part "M115"))
    )
    (comp (ref "D10")
      (value "M216")
      (footprint "eagle-import:H807")
      (libsource (lib "eagle-import") (part "M206X"))
    )
    (comp (ref "D11")
      (value "M113")
      (footprint "eagle-import:H807")
      (libsource (lib "eagle-import") (part "M113"))
    )
    (comp (ref "D12")
      (value "M113")
      (footprint "eagle-import:H807")
      (libsource (lib "eagle-import") (part "M113"))
    )
    (comp (ref "D13")
      (value "M111")
      (footprint "eagle-import:H807")
      (libsource (lib "eagle-import") (part "M111"))
    )
    (comp (ref "AB06")
      (value "M220")
      (footprint "eagle-import:H807-2")
      (libsource (lib "eagle-import") (part "M220"))
    )
    (comp (ref "AB07")
      (value "M220")
      (footprint "eagle-import:H807-2")
      (libsource (lib "eagle-import") (part "M220"))
    )
    (comp (ref "A32")
      (value "M516")
      (footprint "eagle-import:H807")
      (libsource (lib "eagle-import") (part "M516"))
    )
    (comp (ref "A33")
      (value "M516")
      (footprint "eagle-import:H807")
      (libsource (lib "eagle-import") (part "M516"))
    )
    (comp (ref "A34")
      (value "M111")
      (footprint "eagle-import:H807")
      (libsource (lib "eagle-import") (part "M111"))
    )
    (comp (ref "B12")
      (value "M111")
      (footprint "eagle-import:H807")
      (libsource (lib "eagle-import") (part "M111"))
    )
    (comp (ref "B32")
      (value "M906")
      (footprint "eagle-import:H807")
      (libsource (lib "eagle-import") (part "M906"))
    )
    (comp (ref "B33")
      (value "M906")
      (footprint "eagle-import:H807")
      (libsource (lib "eagle-import") (part "M906"))
    )
    (comp (ref "C27")
      (value "M623")
      (footprint "eagle-import:H807")
      (libsource (lib "eagle-import") (part "M623"))
    )
    (comp (ref "C29")
      (value "M660")
      (footprint "eagle-import:H807")
      (libsource (lib "eagle-import") (part "M660"))
    )
    (comp (ref "C30")
      (value "M660")
      (footprint "eagle-import:H807")
      (libsource (lib "eagle-import") (part "M660"))
    )
    (comp (ref "C35")
      (value "M903")
      (footprint "eagle-import:H807")
      (libsource (lib "eagle-import") (part "M903"))
    )
    (comp (ref "C36")
      (value "M903")
      (footprint "eagle-import:H807")
      (libsource (lib "eagle-import") (part "M903"))
    )
    (comp (ref "D27")
      (value "M623")
      (footprint "eagle-import:H807")
      (libsource (lib "eagle-import") (part "M623"))
    )
    (comp (ref "D28")
      (value "M623")
      (footprint "eagle-import:H807")
      (libsource (lib "eagle-import") (part "M623"))
    )
    (comp (ref "D29")
      (value "M906")
      (footprint "eagle-import:H807")
      (libsource (lib "eagle-import") (part "M906"))
    )
    (comp (ref "D30")
      (value "M906")
      (footprint "eagle-import:H807")
      (libsource (lib "eagle-import") (part "M906"))
    )
    (comp (ref "D34")
      (value "M903")
      (footprint "eagle-import:H807")
      (libsource (lib "eagle-import") (part "M903"))
    )
    (comp (ref "D35")
      (value "M903")
      (footprint "eagle-import:H807")
      (libsource (lib "eagle-import") (part "M903"))
    )
    (comp (ref "D36")
      (value "M903")
      (footprint "eagle-import:H807")
      (libsource (lib "eagle-import") (part "M903"))
    )
    (comp (ref "B13")
      (value "M113")
      (footprint "eagle-import:H807")
      (libsource (lib "eagle-import") (part "M113"))
    )
    (comp (ref "B14")
      (value "M119")
      (footprint "eagle-import:H807")
      (libsource (lib "eagle-import") (part "M119"))
    )
    (comp (ref "B36")
      (value "M903")
      (footprint "eagle-import:H807")
      (libsource (lib "eagle-import") (part "M903"))
    )
    (comp (ref "C13")
      (value "M117")
      (footprint "eagle-import:H807")
      (libsource (lib "eagle-import") (part "M117"))
    )
    (comp (ref "C14")
      (value "M113")
      (footprint "eagle-import:H807")
      (libsource (lib "eagle-import") (part "M113"))
    )
    (comp (ref "C28")
      (value "M115")
      (footprint "eagle-import:H807")
      (libsource (lib "eagle-import") (part "M115"))
    )
    (comp (ref "A35")
      (value "M111")
      (footprint "eagle-import:H807")
      (libsource (lib "eagle-import") (part "M111"))
    )
    (comp (ref "B01")
      (value "G921")
      (footprint "eagle-import:H807")
      (libsource (lib "eagle-import") (part "M916"))
    )
    (comp (ref "B34")
      (value "M903")
      (footprint "eagle-import:H807")
      (libsource (lib "eagle-import") (part "M903"))
    )
    (comp (ref "C05")
      (value "M113")
      (footprint "eagle-import:H807")
      (libsource (lib "eagle-import") (part "M113"))
    )
    (comp (ref "C15")
      (value "M113")
      (footprint "eagle-import:H807")
      (libsource (lib "eagle-import") (part "M113"))
    )
    (comp (ref "D17")
      (value "M617")
      (footprint "eagle-import:H807")
      (libsource (lib "eagle-import") (part "M617"))
    )
    (comp (ref "D26")
      (value "H807")
      (footprint "eagle-import:H807")
      (libsource (lib "eagle-import") (part "H807"))
    )
    (comp (ref "A36")
      (value "M703")
      (footprint "eagle-import:H807")
      (libsource (lib "eagle-import") (part "M916"))
    )
    (comp (ref "AB31")
      (value "M710")
      (footprint "eagle-import:H807-2")
      (libsource (lib "eagle-import") (part "M710"))
    )
    (comp (ref "C34")
      (value "M916")
      (footprint "eagle-import:H807")
      (libsource (lib "eagle-import") (part "M916"))
    )
    (comp (ref "C32")
      (value "M706A")
      (footprint "eagle-import:H807")
      (libsource (lib "eagle-import") (part "M916"))
    )
    (comp (ref "D32")
      (value "M706B")
      (footprint "eagle-import:H807")
      (libsource (lib "eagle-import") (part "M916"))
    )
    (comp (ref "D33")
      (value "W076")
      (footprint "eagle-import:H807")
      (libsource (lib "eagle-import") (part "W023"))
    )
    (comp (ref "AB02")
      (value "M220")
      (footprint "eagle-import:H807-2")
      (libsource (lib "eagle-import") (part "M220"))
    )
    (comp (ref "AB03")
      (value "M220")
      (footprint "eagle-import:H807-2")
      (libsource (lib "eagle-import") (part "M220"))
    )
    (comp (ref "AB04")
      (value "M220")
      (footprint "eagle-import:H807-2")
      (libsource (lib "eagle-import") (part "M220"))
    )
    (comp (ref "A25")
      (value "G624")
      (footprint "eagle-import:H807")
      (libsource (lib "eagle-import") (part "G624"))
    )
    (comp (ref "A26")
      (value "G624")
      (footprint "eagle-import:H807")
      (libsource (lib "eagle-import") (part "G624"))
    )
    (comp (ref "A27")
      (value "G826A")
      (footprint "eagle-import:H807")
      (libsource (lib "eagle-import") (part "W023"))
    )
    (comp (ref "A28")
      (value "G785A")
      (footprint "eagle-import:H807")
      (libsource (lib "eagle-import") (part "M916"))
    )
    (comp (ref "B22")
      (value "W025B")
      (footprint "eagle-import:H807")
      (libsource (lib "eagle-import") (part "W023"))
    )
    (comp (ref "B25")
      (value "G624")
      (footprint "eagle-import:H807")
      (libsource (lib "eagle-import") (part "G624"))
    )
    (comp (ref "B26")
      (value "G624")
      (footprint "eagle-import:H807")
      (libsource (lib "eagle-import") (part "G624"))
    )
    (comp (ref "B27")
      (value "G826B")
      (footprint "eagle-import:H807")
      (libsource (lib "eagle-import") (part "W023"))
    )
    (comp (ref "B28")
      (value "G785B")
      (footprint "eagle-import:H807")
      (libsource (lib "eagle-import") (part "W023"))
    )
    (comp (ref "C17")
      (value "M360")
      (footprint "eagle-import:H807")
      (libsource (lib "eagle-import") (part "M360"))
    )
    (comp (ref "C25")
      (value "G228")
      (footprint "eagle-import:H807")
      (libsource (lib "eagle-import") (part "G228"))
    )
    (comp (ref "D14")
      (value "M310")
      (footprint "eagle-import:H807")
      (libsource (lib "eagle-import") (part "M310"))
    )
    (comp (ref "D15")
      (value "M310")
      (footprint "eagle-import:H807")
      (libsource (lib "eagle-import") (part "M310"))
    )
    (comp (ref "D16")
      (value "M216")
      (footprint "eagle-import:H807")
      (libsource (lib "eagle-import") (part "M206X"))
    )
    (comp (ref "D25")
      (value "G228")
      (footprint "eagle-import:H807")
      (libsource (lib "eagle-import") (part "G228"))
    )
    (comp (ref "A17")
      (value "G020")
      (footprint "eagle-import:H807")
      (libsource (lib "eagle-import") (part "G020"))
    )
    (comp (ref "A18")
      (value "G020")
      (footprint "eagle-import:H807")
      (libsource (lib "eagle-import") (part "G020"))
    )
    (comp (ref "A19")
      (value "G020")
      (footprint "eagle-import:H807")
      (libsource (lib "eagle-import") (part "G020"))
    )
    (comp (ref "A20")
      (value "G020")
      (footprint "eagle-import:H807")
      (libsource (lib "eagle-import") (part "G020"))
    )
    (comp (ref "A21")
      (value "W025A")
      (footprint "eagle-import:H807")
      (libsource (lib "eagle-import") (part "W023"))
    )
    (comp (ref "A22")
      (value "W025A")
      (footprint "eagle-import:H807")
      (libsource (lib "eagle-import") (part "W023"))
    )
    (comp (ref "A23")
      (value "G228")
      (footprint "eagle-import:H807")
      (libsource (lib "eagle-import") (part "G228"))
    )
    (comp (ref "A24")
      (value "G228")
      (footprint "eagle-import:H807")
      (libsource (lib "eagle-import") (part "G228"))
    )
    (comp (ref "B18")
      (value "G020")
      (footprint "eagle-import:H807")
      (libsource (lib "eagle-import") (part "G020"))
    )
    (comp (ref "B19")
      (value "G020")
      (footprint "eagle-import:H807")
      (libsource (lib "eagle-import") (part "G020"))
    )
    (comp (ref "B20")
      (value "G020")
      (footprint "eagle-import:H807")
      (libsource (lib "eagle-import") (part "G020"))
    )
    (comp (ref "B21")
      (value "W025B")
      (footprint "eagle-import:H807")
      (libsource (lib "eagle-import") (part "W023"))
    )
    (comp (ref "B23")
      (value "G228")
      (footprint "eagle-import:H807")
      (libsource (lib "eagle-import") (part "G228"))
    )
    (comp (ref "B24")
      (value "G228")
      (footprint "eagle-import:H807")
      (libsource (lib "eagle-import") (part "G228"))
    )
    (comp (ref "A11")
      (value "M115")
      (footprint "eagle-import:H807")
      (libsource (lib "eagle-import") (part "M115"))
    )
    (comp (ref "A13")
      (value "M160")
      (footprint "eagle-import:H807")
      (libsource (lib "eagle-import") (part "M160"))
    )
    (comp (ref "A14")
      (value "M115")
      (footprint "eagle-import:H807")
      (libsource (lib "eagle-import") (part "M115"))
    )
    (comp (ref "B08")
      (value "M617")
      (footprint "eagle-import:H807")
      (libsource (lib "eagle-import") (part "M617"))
    )
    (comp (ref "C12")
      (value "M115")
      (footprint "eagle-import:H807")
      (libsource (lib "eagle-import") (part "M115"))
    )
    (comp (ref "C21")
      (value "H807")
      (footprint "eagle-import:H807")
      (libsource (lib "eagle-import") (part "H807"))
    )
    (comp (ref "C22")
      (value "G610A")
      (footprint "eagle-import:H807")
      (libsource (lib "eagle-import") (part "W023"))
    )
    (comp (ref "C23")
      (value "G221")
      (footprint "eagle-import:H807")
      (libsource (lib "eagle-import") (part "G221"))
    )
    (comp (ref "C24")
      (value "G221")
      (footprint "eagle-import:H807")
      (libsource (lib "eagle-import") (part "G221"))
    )
    (comp (ref "D18")
      (value "G221")
      (footprint "eagle-import:H807")
      (libsource (lib "eagle-import") (part "G221"))
    )
    (comp (ref "D19")
      (value "G221")
      (footprint "eagle-import:H807")
      (libsource (lib "eagle-import") (part "G221"))
    )
    (comp (ref "D20")
      (value "G611B")
      (footprint "eagle-import:H807")
      (libsource (lib "eagle-import") (part "W023"))
    )
    (comp (ref "D21")
      (value "H807")
      (footprint "eagle-import:H807")
      (libsource (lib "eagle-import") (part "H807"))
    )
    (comp (ref "A08")
      (value "M617")
      (footprint "eagle-import:H807")
      (libsource (lib "eagle-import") (part "M617"))
    )
    (comp (ref "A09")
      (value "M617")
      (footprint "eagle-import:H807")
      (libsource (lib "eagle-import") (part "M617"))
    )
    (comp (ref "A10")
      (value "M160")
      (footprint "eagle-import:H807")
      (libsource (lib "eagle-import") (part "M160"))
    )
    (comp (ref "A12")
      (value "M160")
      (footprint "eagle-import:H807")
      (libsource (lib "eagle-import") (part "M160"))
    )
    (comp (ref "B10")
      (value "M160")
      (footprint "eagle-import:H807")
      (libsource (lib "eagle-import") (part "M160"))
    )
    (comp (ref "D09")
      (value "M160")
      (footprint "eagle-import:H807")
      (libsource (lib "eagle-import") (part "M160"))
    )
    (comp (ref "AB05")
      (value "M220")
      (footprint "eagle-import:H807-2")
      (libsource (lib "eagle-import") (part "M220"))
    )
    (comp (ref "AB29")
      (value "M715")
      (footprint "eagle-import:H807-2")
      (libsource (lib "eagle-import") (part "M715"))
    )
    (comp (ref "AB30")
      (value "M705")
      (footprint "eagle-import:H807-2")
      (libsource (lib "eagle-import") (part "M705"))
    )
    (comp (ref "C02")
      (value "M113")
      (footprint "eagle-import:H807")
      (libsource (lib "eagle-import") (part "M113"))
    )
    (comp (ref "C04")
      (value "M216")
      (footprint "eagle-import:H807")
      (libsource (lib "eagle-import") (part "M206X"))
    )
    (comp (ref "CD03")
      (value "M700")
      (footprint "eagle-import:H807-2")
      (libsource (lib "eagle-import") (part "M700"))
    )
    (comp (ref "D05")
      (value "M310")
      (footprint "eagle-import:H807")
      (libsource (lib "eagle-import") (part "M310"))
    )
    (comp (ref "D06")
      (value "M310")
      (footprint "eagle-import:H807")
      (libsource (lib "eagle-import") (part "M310"))
    )
    (comp (ref "D07")
      (value "M310")
      (footprint "eagle-import:H807")
      (libsource (lib "eagle-import") (part "M310"))
    )
    (comp (ref "D08")
      (value "M310")
      (footprint "eagle-import:H807")
      (libsource (lib "eagle-import") (part "M310"))
    )
    (comp (ref "A15")
      (value "M162")
      (footprint "eagle-import:H807")
      (libsource (lib "eagle-import") (part "M162"))
    )
    (comp (ref "A16")
      (value "M162")
      (footprint "eagle-import:H807")
      (libsource (lib "eagle-import") (part "M162"))
    )
    (comp (ref "B15")
      (value "M119")
      (footprint "eagle-import:H807")
      (libsource (lib "eagle-import") (part "M119"))
    )
    (comp (ref "B16")
      (value "M162")
      (footprint "eagle-import:H807")
      (libsource (lib "eagle-import") (part "M162"))
    )
    (comp (ref "B17")
      (value "M162")
      (footprint "eagle-import:H807")
      (libsource (lib "eagle-import") (part "M162"))
    )
    (comp (ref "C16")
      (value "M111")
      (footprint "eagle-import:H807")
      (libsource (lib "eagle-import") (part "M111"))
    )
    (comp (ref "C18")
      (value "G221")
      (footprint "eagle-import:H807")
      (libsource (lib "eagle-import") (part "G221"))
    )
    (comp (ref "C19")
      (value "G221")
      (footprint "eagle-import:H807")
      (libsource (lib "eagle-import") (part "G221"))
    )
    (comp (ref "C20")
      (value "G610A")
      (footprint "eagle-import:H807")
      (libsource (lib "eagle-import") (part "W023"))
    )
    (comp (ref "D22")
      (value "G611B")
      (footprint "eagle-import:H807")
      (libsource (lib "eagle-import") (part "W023"))
    )
    (comp (ref "D23")
      (value "G221")
      (footprint "eagle-import:H807")
      (libsource (lib "eagle-import") (part "G221"))
    )
    (comp (ref "D24")
      (value "G221")
      (footprint "eagle-import:H807")
      (libsource (lib "eagle-import") (part "G221"))
    )
    (comp (ref "C31")
      (value "M707A")
      (footprint "eagle-import:H807")
      (libsource (lib "eagle-import") (part "M916"))
    )
    (comp (ref "C33")
      (value "M452")
      (footprint "eagle-import:H807")
      (libsource (lib "eagle-import") (part "W023"))
    )
    (comp (ref "D31")
      (value "M707B")
      (footprint "eagle-import:H807")
      (libsource (lib "eagle-import") (part "M916"))
    )
  )
  (nets
    (net (code "1") (name "+3V(1)") (class "Default")
      (node (ref "C02") (pin "J1") (pinfunction "IN2_J1") (pintype "input"))
      (node (ref "C02") (pin "M1") (pinfunction "IN2_M1") (pintype "input"))
      (node (ref "C02") (pin "U1") (pinfunction "P$1_U1") (pintype "passive"))
      (node (ref "C04") (pin "C1") (pinfunction "D_C1") (pintype "input"))
    )
    (net (code "2") (name "+3V(2)") (class "Default")
      (node (ref "C05") (pin "U1") (pinfunction "P$1_U1") (pintype "passive"))
      (node (ref "C06") (pin "D1") (pinfunction "S_D1") (pintype "input"))
      (node (ref "C06") (pin "F2") (pinfunction "S_F2") (pintype "input"))
      (node (ref "C06") (pin "K2") (pinfunction "R_K2") (pintype "input"))
    )
    (net (code "3") (name "+3V(3)") (class "Default")
      (node (ref "C05") (pin "V1") (pinfunction "P$1_V1") (pintype "passive"))
      (node (ref "C08") (pin "D1") (pinfunction "S_D1") (pintype "input"))
      (node (ref "C08") (pin "F2") (pinfunction "S_F2") (pintype "input"))
      (node (ref "C08") (pin "K1") (pinfunction "S_K1") (pintype "input"))
      (node (ref "C08") (pin "R1") (pinfunction "S_R1") (pintype "input"))
      (node (ref "C08") (pin "U2") (pinfunction "S_U2") (pintype "input"))
    )
    (net (code "4") (name "+3V(4)") (class "Default")
      (node (ref "D10") (pin "A1") (pinfunction "R_A1") (pintype "input"))
      (node (ref "D10") (pin "N2") (pinfunction "S_N2") (pintype "input"))
      (node (ref "D10") (pin "R1") (pinfunction "S_R1") (pintype "input"))
      (node (ref "D10") (pin "U2") (pinfunction "S_U2") (pintype "input"))
      (node (ref "D11") (pin "A1") (pinfunction "IN1_A1") (pintype "input"))
      (node (ref "D11") (pin "L2") (pinfunction "IN1_L2") (pintype "input"))
      (node (ref "D11") (pin "U1") (pinfunction "P$1_U1") (pintype "passive"))
    )
    (net (code "5") (name "+3V(5)") (class "Default")
      (node (ref "C10") (pin "F2") (pinfunction "IN7_F2") (pintype "input"))
      (node (ref "C10") (pin "H2") (pinfunction "IN8_H2") (pintype "input"))
      (node (ref "C10") (pin "M1") (pinfunction "IN1_M1") (pintype "input"))
      (node (ref "C10") (pin "N2") (pinfunction "IN8_N2") (pintype "input"))
      (node (ref "C10") (pin "U1") (pinfunction "P$1_U1") (pintype "passive"))
    )
    (net (code "6") (name "+3V(6)") (class "Default")
      (node (ref "A09") (pin "U1") (pinfunction "P$1_U1") (pintype "passive"))
      (node (ref "A10") (pin "B1") (pinfunction "IN1B_B1") (pintype "input"))
      (node (ref "A10") (pin "E2") (pinfunction "IN1B_E2") (pintype "input"))
      (node (ref "A10") (pin "H1") (pinfunction "IN3A_H1") (pintype "input"))
      (node (ref "A10") (pin "H2") (pinfunction "IN1D_H2") (pintype "input"))
    )
    (net (code "7") (name "+3V(7)") (class "Default")
      (node (ref "B09") (pin "U1") (pinfunction "P$1_U1") (pintype "passive"))
      (node (ref "B10") (pin "D2") (pinfunction "IN1A_D2") (pintype "input"))
      (node (ref "B10") (pin "R2") (pinfunction "IN4C_R2") (pintype "input"))
      (node (ref "B10") (pin "S2") (pinfunction "IN4D_S2") (pintype "input"))
    )
    (net (code "8") (name "+3V(8)") (class "Default")
      (node (ref "D09") (pin "D1") (pinfunction "IN1D_D1") (pintype "input"))
      (node (ref "D09") (pin "D2") (pinfunction "IN1A_D2") (pintype "input"))
      (node (ref "D09") (pin "E2") (pinfunction "IN1B_E2") (pintype "input"))
      (node (ref "D09") (pin "N1") (pinfunction "IN5B_N1") (pintype "input"))
      (node (ref "D09") (pin "P1") (pinfunction "IN5C_P1") (pintype "input"))
      (node (ref "D11") (pin "V1") (pinfunction "P$1_V1") (pintype "passive"))
    )
    (net (code "9") (name "+3V(9)") (class "Default")
      (node (ref "A09") (pin "V1") (pinfunction "P$1_V1") (pintype "passive"))
      (node (ref "A12") (pin "H2") (pinfunction "IN1D_H2") (pintype "input"))
      (node (ref "A12") (pin "N2") (pinfunction "IN4A_N2") (pintype "input"))
    )
    (net (code "10") (name "+3V(10)") (class "Default")
      (node (ref "B08") (pin "K2") (pinfunction "IN1_K2") (pintype "input"))
      (node (ref "B08") (pin "L2") (pinfunction "IN2_L2") (pintype "input"))
      (node (ref "B08") (pin "U1") (pinfunction "P$1_U1") (pintype "passive"))
    )
    (net (code "11") (name "+3V(11)") (class "Default")
      (node (ref "B09") (pin "V1") (pinfunction "P$1_V1") (pintype "passive"))
      (node (ref "B11") (pin "A1") (pinfunction "R_A1") (pintype "input"))
      (node (ref "B11") (pin "K2") (pinfunction "R_K2") (pintype "input"))
      (node (ref "B11") (pin "N2") (pinfunction "S_N2") (pintype "input"))
    )
    (net (code "12") (name "+3V(12)") (class "Default")
      (node (ref "B08") (pin "V1") (pinfunction "P$1_V1") (pintype "passive"))
      (node (ref "B10") (pin "A1") (pinfunction "IN1A_A1") (pintype "input"))
      (node (ref "B10") (pin "C1") (pinfunction "IN1C_C1") (pintype "input"))
      (node (ref "B10") (pin "P1") (pinfunction "IN5C_P1") (pintype "input"))
    )
    (net (code "13") (name "+3V(13)") (class "Default")
      (node (ref "C14") (pin "R1") (pinfunction "IN2_R1") (pintype "input"))
      (node (ref "C25") (pin "A1") (pinfunction "A1_A1") (pintype "input"))
      (node (ref "D16") (pin "D1") (pinfunction "S_D1") (pintype "input"))
      (node (ref "D17") (pin "V1") (pinfunction "P$1_V1") (pintype "passive"))
      (node (ref "D25") (pin "A1") (pinfunction "A1_A1") (pintype "input"))
    )
    (net (code "14") (name "+3V(15)") (class "Default")
      (node (ref "C31") (pin "N1") (pinfunction "P$2_N1") (pintype "bidirectional"))
      (node (ref "C31") (pin "N2") (pinfunction "P$2_N2") (pintype "bidirectional"))
      (node (ref "D31") (pin "F2") (pinfunction "P$2_F2") (pintype "bidirectional"))
      (node (ref "D31") (pin "J1") (pinfunction "P$2_J1") (pintype "bidirectional"))
      (node (ref "D31") (pin "S2") (pinfunction "P$2_S2") (pintype "bidirectional"))
    )
    (net (code "15") (name "+3V(16)") (class "Default")
      (node (ref "C32") (pin "D1") (pinfunction "P$2_D1") (pintype "bidirectional"))
      (node (ref "D32") (pin "R1") (pinfunction "P$2_R1") (pintype "bidirectional"))
    )
    (net (code "16") (name "+3V(17)") (class "Default")
      (node (ref "B14") (pin "U1") (pinfunction "P$1_U1") (pintype "passive"))
      (node (ref "B14") (pin "U2") (pinfunction "IN8_U2") (pintype "input"))
    )
    (net (code "17") (name "+3V(18)") (class "Default")
      (node (ref "A08") (pin "R1") (pinfunction "IN4_R1") (pintype "input"))
      (node (ref "A08") (pin "U1") (pinfunction "P$1_U1") (pintype "passive"))
    )
    (net (code "18") (name "+5V(1)") (class "Default")
      (node (ref "A28") (pin "F2") (pinfunction "P$2_F2") (pintype "bidirectional"))
    )
    (net (code "19") (name "+5V(2)") (class "Default")
      (node (ref "A28") (pin "H2") (pinfunction "P$2_H2") (pintype "bidirectional"))
    )
    (net (code "20") (name "+5V(3)") (class "Default")
      (node (ref "A28") (pin "J2") (pinfunction "P$2_J2") (pintype "bidirectional"))
    )
    (net (code "21") (name "+5V(4)") (class "Default")
      (node (ref "A28") (pin "K2") (pinfunction "P$2_K2") (pintype "bidirectional"))
    )
    (net (code "22") (name "+5V(5)") (class "Default")
      (node (ref "A28") (pin "L2") (pinfunction "P$2_L2") (pintype "bidirectional"))
    )
    (net (code "23") (name "+5V(6)") (class "Default")
      (node (ref "A28") (pin "M2") (pinfunction "P$2_M2") (pintype "bidirectional"))
    )
    (net (code "24") (name "-15V") (class "Default")
      (node (ref "C34") (pin "B2") (pinfunction "P$2_B2") (pintype "bidirectional"))
      (node (ref "D33") (pin "B2") (pinfunction "P$2_B2") (pintype "bidirectional"))
    )
    (net (code "25") (name "3CYCLE") (class "Default")
      (node (ref "A34") (pin "V2") (pinfunction "OUT_V2") (pintype "output"))
      (node (ref "D12") (pin "P2") (pinfunction "IN1_P2") (pintype "input"))
    )
    (net (code "26") (name "A") (class "Default")
      (node (ref "AB30") (pin "BS1") (pinfunction "BS1_BS1") (pintype "output"))
      (node (ref "C34") (pin "P2") (pinfunction "P$2_P2") (pintype "bidirectional"))
    )
    (net (code "27") (name "AC00") (class "Default")
      (node (ref "AB07") (pin "BA1") (pinfunction "BA1_BA1") (pintype "output"))
      (node (ref "C14") (pin "L1") (pinfunction "IN1_L1") (pintype "input"))
      (node (ref "D27") (pin "A1") (pinfunction "A_A1") (pintype "input"))
    )
    (net (code "28") (name "AC01") (class "Default")
      (node (ref "AB07") (pin "AV1") (pinfunction "AV1_AV1") (pintype "output"))
      (node (ref "D27") (pin "B1") (pinfunction "B_B1") (pintype "input"))
    )
    (net (code "29") (name "AC02") (class "Default")
      (node (ref "AB06") (pin "BA1") (pinfunction "BA1_BA1") (pintype "output"))
      (node (ref "D27") (pin "F1") (pinfunction "A_F1") (pintype "input"))
    )
    (net (code "30") (name "AC03") (class "Default")
      (node (ref "AB06") (pin "AV1") (pinfunction "AV1_AV1") (pintype "output"))
      (node (ref "D27") (pin "H1") (pinfunction "B_H1") (pintype "input"))
    )
    (net (code "31") (name "AC04") (class "Default")
      (node (ref "AB05") (pin "BA1") (pinfunction "BA1_BA1") (pintype "output"))
      (node (ref "AB31") (pin "AH1") (pinfunction "AH1_AH1") (pintype "input"))
      (node (ref "C31") (pin "P2") (pinfunction "P$2_P2") (pintype "bidirectional"))
      (node (ref "D27") (pin "M1") (pinfunction "A_M1") (pintype "input"))
    )
    (net (code "32") (name "AC05") (class "Default")
      (node (ref "AB05") (pin "AV1") (pinfunction "AV1_AV1") (pintype "output"))
      (node (ref "AB31") (pin "AH2") (pinfunction "AH2_AH2") (pintype "input"))
      (node (ref "C31") (pin "R2") (pinfunction "P$2_R2") (pintype "bidirectional"))
      (node (ref "D27") (pin "N1") (pinfunction "B_N1") (pintype "input"))
    )
    (net (code "33") (name "AC06") (class "Default")
      (node (ref "AB04") (pin "BA1") (pinfunction "BA1_BA1") (pintype "output"))
      (node (ref "AB31") (pin "AF1") (pinfunction "AF1_AF1") (pintype "input"))
      (node (ref "C31") (pin "L2") (pinfunction "P$2_L2") (pintype "bidirectional"))
      (node (ref "D27") (pin "D2") (pinfunction "A_D2") (pintype "input"))
    )
    (net (code "34") (name "AC07") (class "Default")
      (node (ref "AB04") (pin "AV1") (pinfunction "AV1_AV1") (pintype "output"))
      (node (ref "AB31") (pin "AF2") (pinfunction "AF2_AF2") (pintype "input"))
      (node (ref "C31") (pin "M2") (pinfunction "P$2_M2") (pintype "bidirectional"))
      (node (ref "D27") (pin "E2") (pinfunction "B_E2") (pintype "input"))
    )
    (net (code "35") (name "AC08") (class "Default")
      (node (ref "AB03") (pin "BA1") (pinfunction "BA1_BA1") (pintype "output"))
      (node (ref "AB31") (pin "AE1") (pinfunction "AE1_AE1") (pintype "input"))
      (node (ref "C31") (pin "U2") (pinfunction "P$2_U2") (pintype "bidirectional"))
      (node (ref "D27") (pin "K2") (pinfunction "A_K2") (pintype "input"))
    )
    (net (code "36") (name "AC09") (class "Default")
      (node (ref "AB03") (pin "AV1") (pinfunction "AV1_AV1") (pintype "output"))
      (node (ref "AB31") (pin "AE2") (pinfunction "AE2_AE2") (pintype "input"))
      (node (ref "C31") (pin "S2") (pinfunction "P$2_S2") (pintype "bidirectional"))
      (node (ref "D27") (pin "L2") (pinfunction "B_L2") (pintype "input"))
    )
    (net (code "37") (name "AC10") (class "Default")
      (node (ref "AB02") (pin "BA1") (pinfunction "BA1_BA1") (pintype "output"))
      (node (ref "AB31") (pin "AD1") (pinfunction "AD1_AD1") (pintype "input"))
      (node (ref "C31") (pin "T2") (pinfunction "P$2_T2") (pintype "bidirectional"))
      (node (ref "D27") (pin "R2") (pinfunction "A_R2") (pintype "input"))
    )
    (net (code "38") (name "AC11") (class "Default")
      (node (ref "AB02") (pin "AV1") (pinfunction "AV1_AV1") (pintype "output"))
      (node (ref "AB31") (pin "AD2") (pinfunction "AD2_AD2") (pintype "input"))
      (node (ref "C31") (pin "U1") (pinfunction "P$2_U1") (pintype "bidirectional"))
      (node (ref "D27") (pin "S2") (pinfunction "B_S2") (pintype "input"))
    )
    (net (code "39") (name "AC_CLEAR") (class "Default")
      (node (ref "A33") (pin "S1") (pinfunction "OUT_S1") (pintype "output"))
      (node (ref "D13") (pin "F1") (pinfunction "IN_F1") (pintype "input"))
    )
    (net (code "40") (name "AC_ENABLE") (class "Default")
      (node (ref "A09") (pin "L1") (pinfunction "OUT_L1") (pintype "open_collector"))
      (node (ref "AB02") (pin "BH2") (pinfunction "BH2_BH2") (pintype "input"))
      (node (ref "AB03") (pin "BH2") (pinfunction "BH2_BH2") (pintype "input"))
      (node (ref "AB04") (pin "BH2") (pinfunction "BH2_BH2") (pintype "input"))
      (node (ref "AB05") (pin "BH2") (pinfunction "BH2_BH2") (pintype "input"))
      (node (ref "AB06") (pin "BH2") (pinfunction "BH2_BH2") (pintype "input"))
      (node (ref "AB07") (pin "BH2") (pinfunction "BH2_BH2") (pintype "input"))
    )
    (net (code "41") (name "AC_LOAD") (class "Default")
      (node (ref "AB02") (pin "AU1") (pinfunction "AU1_AU1") (pintype "input"))
      (node (ref "AB03") (pin "AU1") (pinfunction "AU1_AU1") (pintype "input"))
      (node (ref "AB04") (pin "AU1") (pinfunction "AU1_AU1") (pintype "input"))
      (node (ref "AB05") (pin "AU1") (pinfunction "AU1_AU1") (pintype "input"))
      (node (ref "AB06") (pin "AU1") (pinfunction "AU1_AU1") (pintype "input"))
      (node (ref "AB07") (pin "AU1") (pinfunction "AU1_AU1") (pintype "input"))
      (node (ref "B08") (pin "V2") (pinfunction "OUT_V2") (pintype "open_collector"))
      (node (ref "B11") (pin "L2") (pinfunction "C_L2") (pintype "input"))
    )
    (net (code "42") (name "ADDER00") (class "Default")
      (node (ref "AB02") (pin "AJ2") (pinfunction "AJ2_AJ2") (pintype "input"))
      (node (ref "AB06") (pin "AB1") (pinfunction "AB1_AB1") (pintype "input"))
      (node (ref "AB07") (pin "AE2") (pinfunction "AE2_AE2") (pintype "output"))
      (node (ref "B10") (pin "K1") (pinfunction "IN4A_K1") (pintype "input"))
    )
    (net (code "43") (name "ADDER01") (class "Default")
      (node (ref "AB06") (pin "AC1") (pinfunction "AC1_AC1") (pintype "input"))
      (node (ref "AB07") (pin "AF1") (pinfunction "AF1_AF1") (pintype "output"))
      (node (ref "B10") (pin "M1") (pinfunction "IN5A_M1") (pintype "input"))
    )
    (net (code "44") (name "ADDER02") (class "Default")
      (node (ref "AB05") (pin "AB1") (pinfunction "AB1_AB1") (pintype "input"))
      (node (ref "AB06") (pin "AE2") (pinfunction "AE2_AE2") (pintype "output"))
      (node (ref "AB07") (pin "AH2") (pinfunction "AH2_AH2") (pintype "input"))
    )
    (net (code "45") (name "ADDER03") (class "Default")
      (node (ref "AB05") (pin "AC1") (pinfunction "AC1_AC1") (pintype "input"))
      (node (ref "AB06") (pin "AF1") (pinfunction "AF1_AF1") (pintype "output"))
      (node (ref "AB07") (pin "AJ2") (pinfunction "AJ2_AJ2") (pintype "input"))
    )
    (net (code "46") (name "ADDER04") (class "Default")
      (node (ref "AB04") (pin "AB1") (pinfunction "AB1_AB1") (pintype "input"))
      (node (ref "AB05") (pin "AE2") (pinfunction "AE2_AE2") (pintype "output"))
      (node (ref "AB06") (pin "AH2") (pinfunction "AH2_AH2") (pintype "input"))
    )
    (net (code "47") (name "ADDER05") (class "Default")
      (node (ref "AB04") (pin "AC1") (pinfunction "AC1_AC1") (pintype "input"))
      (node (ref "AB05") (pin "AF1") (pinfunction "AF1_AF1") (pintype "output"))
      (node (ref "AB06") (pin "AJ2") (pinfunction "AJ2_AJ2") (pintype "input"))
    )
    (net (code "48") (name "ADDER06") (class "Default")
      (node (ref "AB03") (pin "AB1") (pinfunction "AB1_AB1") (pintype "input"))
      (node (ref "AB04") (pin "AE2") (pinfunction "AE2_AE2") (pintype "output"))
      (node (ref "AB05") (pin "AH2") (pinfunction "AH2_AH2") (pintype "input"))
    )
    (net (code "49") (name "ADDER07") (class "Default")
      (node (ref "AB03") (pin "AC1") (pinfunction "AC1_AC1") (pintype "input"))
      (node (ref "AB04") (pin "AF1") (pinfunction "AF1_AF1") (pintype "output"))
      (node (ref "AB05") (pin "AJ2") (pinfunction "AJ2_AJ2") (pintype "input"))
    )
    (net (code "50") (name "ADDER08") (class "Default")
      (node (ref "AB02") (pin "AB1") (pinfunction "AB1_AB1") (pintype "input"))
      (node (ref "AB03") (pin "AE2") (pinfunction "AE2_AE2") (pintype "output"))
      (node (ref "AB04") (pin "AH2") (pinfunction "AH2_AH2") (pintype "input"))
    )
    (net (code "51") (name "ADDER09") (class "Default")
      (node (ref "AB02") (pin "AC1") (pinfunction "AC1_AC1") (pintype "input"))
      (node (ref "AB03") (pin "AF1") (pinfunction "AF1_AF1") (pintype "output"))
      (node (ref "AB04") (pin "AJ2") (pinfunction "AJ2_AJ2") (pintype "input"))
    )
    (net (code "52") (name "ADDER10") (class "Default")
      (node (ref "AB02") (pin "AE2") (pinfunction "AE2_AE2") (pintype "output"))
      (node (ref "AB03") (pin "AH2") (pinfunction "AH2_AH2") (pintype "input"))
      (node (ref "B10") (pin "E1") (pinfunction "IN2A_E1") (pintype "input"))
    )
    (net (code "53") (name "ADDER11") (class "Default")
      (node (ref "AB02") (pin "AF1") (pinfunction "AF1_AF1") (pintype "output"))
      (node (ref "AB03") (pin "AJ2") (pinfunction "AJ2_AJ2") (pintype "input"))
      (node (ref "AB07") (pin "AB1") (pinfunction "AB1_AB1") (pintype "input"))
      (node (ref "B10") (pin "B1") (pinfunction "IN1B_B1") (pintype "input"))
    )
    (net (code "54") (name "AND") (class "Default")
      (node (ref "A11") (pin "P1") (pinfunction "IN1_P1") (pintype "input"))
      (node (ref "C07") (pin "E1") (pinfunction "OUT_E1") (pintype "output"))
    )
    (net (code "55") (name "AND_ENABLE") (class "Default")
      (node (ref "AB02") (pin "AA1") (pinfunction "AA1_AA1") (pintype "input"))
      (node (ref "AB03") (pin "AA1") (pinfunction "AA1_AA1") (pintype "input"))
      (node (ref "AB04") (pin "AA1") (pinfunction "AA1_AA1") (pintype "input"))
      (node (ref "AB05") (pin "AA1") (pinfunction "AA1_AA1") (pintype "input"))
      (node (ref "AB06") (pin "AA1") (pinfunction "AA1_AA1") (pintype "input"))
      (node (ref "AB07") (pin "AA1") (pinfunction "AA1_AA1") (pintype "input"))
      (node (ref "B08") (pin "L1") (pinfunction "OUT_L1") (pintype "open_collector"))
    )
    (net (code "56") (name "B") (class "Default")
      (node (ref "AB30") (pin "BU2") (pinfunction "BU2_BU2") (pintype "output"))
      (node (ref "C34") (pin "T2") (pinfunction "P$2_T2") (pintype "bidirectional"))
    )
    (net (code "57") (name "B29B2") (class "Default")
      (node (ref "AB29") (pin "BB2") (pinfunction "-15V_BB2") (pintype "power_in"))
      (node (ref "B28") (pin "B2") (pinfunction "P$2_B2") (pintype "bidirectional"))
    )
    (net (code "58") (name "BEMA") (class "Default")
      (node (ref "B35") (pin "T2") (pinfunction "P$2_T2") (pintype "bidirectional"))
      (node (ref "C10") (pin "T2") (pinfunction "IN7_T2") (pintype "input"))
      (node (ref "C26") (pin "P2") (pinfunction "P$1_P2") (pintype "passive"))
    )
    (net (code "59") (name "BREAK") (class "Default")
      (node (ref "D10") (pin "V2") (pinfunction "1_V2") (pintype "output"))
      (node (ref "D11") (pin "H2") (pinfunction "IN1_H2") (pintype "input"))
    )
    (net (code "60") (name "BREAK_OK") (class "Default")
      (node (ref "D11") (pin "M1") (pinfunction "IN2_M1") (pintype "input"))
      (node (ref "D12") (pin "L2") (pinfunction "IN1_L2") (pintype "input"))
      (node (ref "D12") (pin "R2") (pinfunction "IN2_R2") (pintype "input"))
      (node (ref "D13") (pin "E1") (pinfunction "OUT_E1") (pintype "output"))
    )
    (net (code "61") (name "BTP2") (class "Default")
      (node (ref "B34") (pin "T2") (pinfunction "P$2_T2") (pintype "bidirectional"))
      (node (ref "D05") (pin "J1") (pinfunction "OUT_J1") (pintype "output"))
    )
    (net (code "62") (name "BTP3") (class "Default")
      (node (ref "B36") (pin "H1") (pinfunction "P$2_H1") (pintype "bidirectional"))
      (node (ref "D07") (pin "J1") (pinfunction "OUT_J1") (pintype "output"))
    )
    (net (code "63") (name "B_BK") (class "Default")
      (node (ref "A10") (pin "L2") (pinfunction "IN3A_L2") (pintype "input"))
      (node (ref "A12") (pin "S2") (pinfunction "IN4D_S2") (pintype "input"))
      (node (ref "C07") (pin "V2") (pinfunction "OUT_V2") (pintype "output"))
      (node (ref "C11") (pin "M2") (pinfunction "IN3_M2") (pintype "input"))
    )
    (net (code "64") (name "B_CA") (class "Default")
      (node (ref "A10") (pin "L1") (pinfunction "IN4B_L1") (pintype "input"))
      (node (ref "A12") (pin "M2") (pinfunction "IN3B_M2") (pintype "input"))
      (node (ref "D02") (pin "V2") (pinfunction "OUT_V2") (pintype "output"))
    )
    (net (code "65") (name "B_EXECUTE") (class "Default")
      (node (ref "A10") (pin "D2") (pinfunction "IN1A_D2") (pintype "input"))
      (node (ref "A10") (pin "K2") (pinfunction "IN2B_K2") (pintype "input"))
      (node (ref "A11") (pin "S1") (pinfunction "IN3_S1") (pintype "input"))
      (node (ref "A12") (pin "E2") (pinfunction "IN1B_E2") (pintype "input"))
      (node (ref "A12") (pin "N1") (pinfunction "IN5B_N1") (pintype "input"))
      (node (ref "A13") (pin "C1") (pinfunction "IN1C_C1") (pintype "input"))
      (node (ref "A13") (pin "E2") (pinfunction "IN1B_E2") (pintype "input"))
      (node (ref "B09") (pin "L1") (pinfunction "OUT_L1") (pintype "open_collector"))
      (node (ref "B10") (pin "F2") (pinfunction "IN1C_F2") (pintype "input"))
      (node (ref "C11") (pin "S2") (pinfunction "IN2_S2") (pintype "input"))
      (node (ref "C12") (pin "C1") (pinfunction "IN3_C1") (pintype "input"))
      (node (ref "C12") (pin "L2") (pinfunction "IN3_L2") (pintype "input"))
      (node (ref "C14") (pin "E2") (pinfunction "IN2_E2") (pintype "input"))
      (node (ref "D09") (pin "R2") (pinfunction "IN4C_R2") (pintype "input"))
    )
    (net (code "66") (name "B_FETCH") (class "Default")
      (node (ref "A13") (pin "F1") (pinfunction "IN2B_F1") (pintype "input"))
      (node (ref "B09") (pin "E1") (pinfunction "OUT_E1") (pintype "open_collector"))
      (node (ref "B10") (pin "K2") (pinfunction "IN2B_K2") (pintype "input"))
      (node (ref "C09") (pin "P2") (pinfunction "IN2_P2") (pintype "input"))
      (node (ref "C10") (pin "D1") (pinfunction "IN4_D1") (pintype "input"))
      (node (ref "C10") (pin "K1") (pinfunction "IN4_K1") (pintype "input"))
      (node (ref "C11") (pin "H1") (pinfunction "IN2_H1") (pintype "input"))
      (node (ref "C11") (pin "R1") (pinfunction "IN4_R1") (pintype "input"))
      (node (ref "C13") (pin "C1") (pinfunction "IN3_C1") (pintype "input"))
      (node (ref "C14") (pin "R2") (pinfunction "IN2_R2") (pintype "input"))
      (node (ref "D12") (pin "J1") (pinfunction "IN2_J1") (pintype "input"))
    )
    (net (code "67") (name "B_INHIBIT") (class "Default")
      (node (ref "A23") (pin "A1") (pinfunction "A1_A1") (pintype "input"))
      (node (ref "A24") (pin "A1") (pinfunction "A1_A1") (pintype "input"))
      (node (ref "B23") (pin "A1") (pinfunction "A1_A1") (pintype "input"))
      (node (ref "B24") (pin "A1") (pinfunction "A1_A1") (pintype "input"))
      (node (ref "D17") (pin "J2") (pinfunction "OUT_J2") (pintype "open_collector"))
    )
    (net (code "68") (name "B_MEM_ENABLE") (class "Default")
      (node (ref "A17") (pin "T2") (pinfunction "T2_T2") (pintype "input"))
      (node (ref "A18") (pin "T2") (pinfunction "T2_T2") (pintype "input"))
      (node (ref "A19") (pin "T2") (pinfunction "T2_T2") (pintype "input"))
      (node (ref "A20") (pin "T2") (pinfunction "T2_T2") (pintype "input"))
      (node (ref "A23") (pin "E2") (pinfunction "E2_E2") (pintype "input"))
      (node (ref "A23") (pin "N2") (pinfunction "N2_N2") (pintype "input"))
      (node (ref "A24") (pin "E2") (pinfunction "E2_E2") (pintype "input"))
      (node (ref "B18") (pin "T2") (pinfunction "T2_T2") (pintype "input"))
      (node (ref "B19") (pin "T2") (pinfunction "T2_T2") (pintype "input"))
      (node (ref "B20") (pin "T2") (pinfunction "T2_T2") (pintype "input"))
      (node (ref "B23") (pin "E2") (pinfunction "E2_E2") (pintype "input"))
      (node (ref "B23") (pin "N2") (pinfunction "N2_N2") (pintype "input"))
      (node (ref "B24") (pin "E2") (pinfunction "E2_E2") (pintype "input"))
      (node (ref "B24") (pin "N2") (pinfunction "N2_N2") (pintype "input"))
      (node (ref "C18") (pin "D2") (pinfunction "D2_D2") (pintype "input"))
      (node (ref "C19") (pin "D2") (pinfunction "D2_D2") (pintype "input"))
      (node (ref "C23") (pin "D2") (pinfunction "D2_D2") (pintype "input"))
      (node (ref "C24") (pin "D2") (pinfunction "D2_D2") (pintype "input"))
      (node (ref "C25") (pin "E2") (pinfunction "E2_E2") (pintype "input"))
      (node (ref "C25") (pin "N2") (pinfunction "N2_N2") (pintype "input"))
      (node (ref "D17") (pin "E1") (pinfunction "OUT_E1") (pintype "open_collector"))
      (node (ref "D17") (pin "L1") (pinfunction "OUT_L1") (pintype "open_collector"))
      (node (ref "D18") (pin "D2") (pinfunction "D2_D2") (pintype "input"))
      (node (ref "D19") (pin "D2") (pinfunction "D2_D2") (pintype "input"))
      (node (ref "D23") (pin "D2") (pinfunction "D2_D2") (pintype "input"))
      (node (ref "D24") (pin "D2") (pinfunction "D2_D2") (pintype "input"))
      (node (ref "D25") (pin "E2") (pinfunction "E2_E2") (pintype "input"))
      (node (ref "D25") (pin "N2") (pinfunction "N2_N2") (pintype "input"))
    )
    (net (code "69") (name "B_SET") (class "Default")
      (node (ref "A35") (pin "C1") (pinfunction "IN_C1") (pintype "input"))
      (node (ref "D10") (pin "T2") (pinfunction "D_T2") (pintype "input"))
      (node (ref "D12") (pin "S1") (pinfunction "OUT_S1") (pintype "output"))
    )
    (net (code "70") (name "B_WC") (class "Default")
      (node (ref "B10") (pin "P2") (pinfunction "IN4B_P2") (pintype "input"))
      (node (ref "D02") (pin "T2") (pinfunction "OUT_T2") (pintype "output"))
    )
    (net (code "71") (name "CARRYOUT0") (class "Default")
      (node (ref "A13") (pin "F2") (pinfunction "IN1C_F2") (pintype "input"))
      (node (ref "B10") (pin "U1") (pinfunction "IN1B_U1") (pintype "input"))
      (node (ref "B12") (pin "D2") (pinfunction "OUT_D2") (pintype "output"))
      (node (ref "D11") (pin "E2") (pinfunction "IN2_E2") (pintype "input"))
    )
    (net (code "72") (name "CARRY_INSERT") (class "Default")
      (node (ref "AB02") (pin "BJ1") (pinfunction "BJ1_BJ1") (pintype "input"))
      (node (ref "B13") (pin "N2") (pinfunction "OUT_N2") (pintype "output"))
    )
    (net (code "73") (name "CA_INCREMENT") (class "Default")
      (node (ref "A12") (pin "L2") (pinfunction "IN3A_L2") (pintype "input"))
      (node (ref "B33") (pin "M2") (pinfunction "P$1_M2") (pintype "passive"))
      (node (ref "C35") (pin "M2") (pinfunction "P$2_M2") (pintype "bidirectional"))
    )
    (net (code "74") (name "CLOCK1") (class "Default")
      (node (ref "AB29") (pin "AU2") (pinfunction "AU_AU2") (pintype "output"))
      (node (ref "AB30") (pin "BS2") (pinfunction "BS2_BS2") (pintype "input"))
    )
    (net (code "75") (name "CLOCK_SCALE2") (class "Default")
      (node (ref "D32") (pin "P2") (pinfunction "P$2_P2") (pintype "bidirectional"))
      (node (ref "D32") (pin "T2") (pinfunction "P$2_T2") (pintype "bidirectional"))
    )
    (net (code "76") (name "CONTROL_IOT") (class "Default")
      (node (ref "B12") (pin "R2") (pinfunction "OUT_R2") (pintype "output"))
      (node (ref "C13") (pin "M2") (pinfunction "IN3_M2") (pintype "input"))
    )
    (net (code "77") (name "CYCLE") (class "Default")
      (node (ref "C15") (pin "E2") (pinfunction "IN2_E2") (pintype "input"))
      (node (ref "D16") (pin "H2") (pinfunction "1_H2") (pintype "output"))
    )
    (net (code "78") (name "CYC_DONE") (class "Default")
      (node (ref "C15") (pin "J2") (pinfunction "IN2_J2") (pintype "input"))
      (node (ref "C15") (pin "M1") (pinfunction "IN2_M1") (pintype "input"))
      (node (ref "D15") (pin "F1") (pinfunction "OUT_F1") (pintype "output"))
      (node (ref "D16") (pin "H1") (pinfunction "C_H1") (pintype "input"))
      (node (ref "D16") (pin "L2") (pinfunction "C_L2") (pintype "input"))
      (node (ref "D16") (pin "N1") (pinfunction "C_N1") (pintype "input"))
    )
    (net (code "79") (name "DATA00") (class "Default")
      (node (ref "A34") (pin "H1") (pinfunction "OUT_H1") (pintype "output"))
      (node (ref "AB07") (pin "BM2") (pinfunction "BM2_BM2") (pintype "input"))
    )
    (net (code "80") (name "DATA01") (class "Default")
      (node (ref "A34") (pin "K1") (pinfunction "OUT_K1") (pintype "output"))
      (node (ref "AB07") (pin "BP2") (pinfunction "BP2_BP2") (pintype "input"))
    )
    (net (code "81") (name "DATA02") (class "Default")
      (node (ref "A34") (pin "M1") (pinfunction "OUT_M1") (pintype "output"))
      (node (ref "AB06") (pin "BM2") (pinfunction "BM2_BM2") (pintype "input"))
    )
    (net (code "82") (name "DATA03") (class "Default")
      (node (ref "A34") (pin "P1") (pinfunction "OUT_P1") (pintype "output"))
      (node (ref "AB06") (pin "BP2") (pinfunction "BP2_BP2") (pintype "input"))
    )
    (net (code "83") (name "DATA04") (class "Default")
      (node (ref "A34") (pin "S1") (pinfunction "OUT_S1") (pintype "output"))
      (node (ref "AB05") (pin "BM2") (pinfunction "BM2_BM2") (pintype "input"))
    )
    (net (code "84") (name "DATA05") (class "Default")
      (node (ref "A34") (pin "U1") (pinfunction "OUT_U1") (pintype "output"))
      (node (ref "AB05") (pin "BP2") (pinfunction "BP2_BP2") (pintype "input"))
    )
    (net (code "85") (name "DATA06") (class "Default")
      (node (ref "A34") (pin "F2") (pinfunction "OUT_F2") (pintype "output"))
      (node (ref "AB04") (pin "BM2") (pinfunction "BM2_BM2") (pintype "input"))
    )
    (net (code "86") (name "DATA07") (class "Default")
      (node (ref "A34") (pin "J2") (pinfunction "OUT_J2") (pintype "output"))
      (node (ref "AB04") (pin "BP2") (pinfunction "BP2_BP2") (pintype "input"))
    )
    (net (code "87") (name "DATA08") (class "Default")
      (node (ref "A34") (pin "L2") (pinfunction "OUT_L2") (pintype "output"))
      (node (ref "AB03") (pin "BM2") (pinfunction "BM2_BM2") (pintype "input"))
    )
    (net (code "88") (name "DATA09") (class "Default")
      (node (ref "A34") (pin "N2") (pinfunction "OUT_N2") (pintype "output"))
      (node (ref "AB03") (pin "BP2") (pinfunction "BP2_BP2") (pintype "input"))
    )
    (net (code "89") (name "DATA10") (class "Default")
      (node (ref "A34") (pin "R2") (pinfunction "OUT_R2") (pintype "output"))
      (node (ref "AB02") (pin "BM2") (pinfunction "BM2_BM2") (pintype "input"))
    )
    (net (code "90") (name "DATA11") (class "Default")
      (node (ref "A34") (pin "T2") (pinfunction "OUT_T2") (pintype "output"))
      (node (ref "AB02") (pin "BP2") (pinfunction "BP2_BP2") (pintype "input"))
    )
    (net (code "91") (name "DATA_ADD00") (class "Default")
      (node (ref "AB07") (pin "BS1") (pinfunction "BS1_BS1") (pintype "input"))
      (node (ref "D11") (pin "S1") (pinfunction "OUT_S1") (pintype "output"))
    )
    (net (code "92") (name "DATA_ADD01") (class "Default")
      (node (ref "AB07") (pin "BU1") (pinfunction "BU1_BU1") (pintype "input"))
      (node (ref "D11") (pin "S2") (pinfunction "OUT_S2") (pintype "output"))
    )
    (net (code "93") (name "DATA_ADD02") (class "Default")
      (node (ref "AB06") (pin "BS1") (pinfunction "BS1_BS1") (pintype "input"))
      (node (ref "D11") (pin "V2") (pinfunction "OUT_V2") (pintype "output"))
    )
    (net (code "94") (name "DATA_ADD03") (class "Default")
      (node (ref "AB06") (pin "BU1") (pinfunction "BU1_BU1") (pintype "input"))
      (node (ref "B12") (pin "K1") (pinfunction "OUT_K1") (pintype "output"))
    )
    (net (code "95") (name "DATA_ADD04") (class "Default")
      (node (ref "AB05") (pin "BS1") (pinfunction "BS1_BS1") (pintype "input"))
      (node (ref "D13") (pin "B1") (pinfunction "OUT_B1") (pintype "output"))
    )
    (net (code "96") (name "DATA_ADD05") (class "Default")
      (node (ref "AB05") (pin "BU1") (pinfunction "BU1_BU1") (pintype "input"))
      (node (ref "D13") (pin "K1") (pinfunction "OUT_K1") (pintype "output"))
    )
    (net (code "97") (name "DATA_ADD06") (class "Default")
      (node (ref "AB04") (pin "BS1") (pinfunction "BS1_BS1") (pintype "input"))
      (node (ref "D13") (pin "R2") (pinfunction "OUT_R2") (pintype "output"))
    )
    (net (code "98") (name "DATA_ADD07") (class "Default")
      (node (ref "AB04") (pin "BU1") (pinfunction "BU1_BU1") (pintype "input"))
      (node (ref "D13") (pin "T2") (pinfunction "OUT_T2") (pintype "output"))
    )
    (net (code "99") (name "DATA_ADD08") (class "Default")
      (node (ref "AB03") (pin "BS1") (pinfunction "BS1_BS1") (pintype "input"))
      (node (ref "D13") (pin "V2") (pinfunction "OUT_V2") (pintype "output"))
    )
    (net (code "100") (name "DATA_ADD09") (class "Default")
      (node (ref "A34") (pin "B1") (pinfunction "OUT_B1") (pintype "output"))
      (node (ref "AB03") (pin "BU1") (pinfunction "BU1_BU1") (pintype "input"))
    )
    (net (code "101") (name "DATA_ADD10") (class "Default")
      (node (ref "A34") (pin "D2") (pinfunction "OUT_D2") (pintype "output"))
      (node (ref "AB02") (pin "BS1") (pinfunction "BS1_BS1") (pintype "input"))
    )
    (net (code "102") (name "DATA_ADD11") (class "Default")
      (node (ref "A34") (pin "E1") (pinfunction "OUT_E1") (pintype "output"))
      (node (ref "AB02") (pin "BU1") (pinfunction "BU1_BU1") (pintype "input"))
    )
    (net (code "103") (name "DATA_ADD_EN") (class "Default")
      (node (ref "A09") (pin "V2") (pinfunction "OUT_V2") (pintype "open_collector"))
      (node (ref "AB02") (pin "BT2") (pinfunction "BT2_BT2") (pintype "input"))
      (node (ref "AB03") (pin "BT2") (pinfunction "BT2_BT2") (pintype "input"))
      (node (ref "AB04") (pin "BT2") (pinfunction "BT2_BT2") (pintype "input"))
      (node (ref "AB05") (pin "BT2") (pinfunction "BT2_BT2") (pintype "input"))
      (node (ref "AB06") (pin "BT2") (pinfunction "BT2_BT2") (pintype "input"))
      (node (ref "AB07") (pin "BT2") (pinfunction "BT2_BT2") (pintype "input"))
    )
    (net (code "104") (name "DATA_ENABLE") (class "Default")
      (node (ref "A09") (pin "S1") (pinfunction "OUT_S1") (pintype "open_collector"))
      (node (ref "AB02") (pin "BL1") (pinfunction "BL1_BL1") (pintype "input"))
      (node (ref "AB03") (pin "BL1") (pinfunction "BL1_BL1") (pintype "input"))
      (node (ref "AB04") (pin "BL1") (pinfunction "BL1_BL1") (pintype "input"))
      (node (ref "AB05") (pin "BL1") (pinfunction "BL1_BL1") (pintype "input"))
      (node (ref "AB06") (pin "BL1") (pinfunction "BL1_BL1") (pintype "input"))
      (node (ref "AB07") (pin "BL1") (pinfunction "BL1_BL1") (pintype "input"))
    )
    (net (code "105") (name "DATA_IN") (class "Default")
      (node (ref "A10") (pin "M2") (pinfunction "IN3B_M2") (pintype "input"))
      (node (ref "B32") (pin "M2") (pinfunction "P$1_M2") (pintype "passive"))
      (node (ref "C11") (pin "N2") (pinfunction "IN4_N2") (pintype "input"))
      (node (ref "C36") (pin "M2") (pinfunction "P$2_M2") (pintype "bidirectional"))
    )
    (net (code "106") (name "DCA") (class "Default")
      (node (ref "A10") (pin "J2") (pinfunction "IN2A_J2") (pintype "input"))
      (node (ref "C07") (pin "M1") (pinfunction "OUT_M1") (pintype "output"))
      (node (ref "D09") (pin "S2") (pinfunction "IN4D_S2") (pintype "input"))
    )
    (net (code "107") (name "DEFER") (class "Default")
      (node (ref "A10") (pin "C1") (pinfunction "IN1C_C1") (pintype "input"))
      (node (ref "A10") (pin "N1") (pinfunction "IN5B_N1") (pintype "input"))
      (node (ref "A12") (pin "C1") (pinfunction "IN1C_C1") (pintype "input"))
      (node (ref "A13") (pin "N1") (pinfunction "IN5B_N1") (pintype "input"))
      (node (ref "C08") (pin "S1") (pinfunction "1_S1") (pintype "output"))
      (node (ref "C15") (pin "P1") (pinfunction "IN1_P1") (pintype "input"))
    )
    (net (code "108") (name "DOUBLE_LEFT_ROTATE") (class "Default")
      (node (ref "AB02") (pin "AH1") (pinfunction "AH1_AH1") (pintype "input"))
      (node (ref "AB03") (pin "AH1") (pinfunction "AH1_AH1") (pintype "input"))
      (node (ref "AB04") (pin "AH1") (pinfunction "AH1_AH1") (pintype "input"))
      (node (ref "AB05") (pin "AH1") (pinfunction "AH1_AH1") (pintype "input"))
      (node (ref "AB06") (pin "AH1") (pinfunction "AH1_AH1") (pintype "input"))
      (node (ref "AB07") (pin "AH1") (pinfunction "AH1_AH1") (pintype "input"))
      (node (ref "B09") (pin "V2") (pinfunction "OUT_V2") (pintype "open_collector"))
      (node (ref "B10") (pin "N1") (pinfunction "IN5B_N1") (pintype "input"))
    )
    (net (code "109") (name "DOUBLE_RIGHT_ROTATE") (class "Default")
      (node (ref "AB02") (pin "AD1") (pinfunction "AD1_AD1") (pintype "input"))
      (node (ref "AB03") (pin "AD1") (pinfunction "AD1_AD1") (pintype "input"))
      (node (ref "AB04") (pin "AD1") (pinfunction "AD1_AD1") (pintype "input"))
      (node (ref "AB05") (pin "AD1") (pinfunction "AD1_AD1") (pintype "input"))
      (node (ref "AB06") (pin "AD1") (pinfunction "AD1_AD1") (pintype "input"))
      (node (ref "AB07") (pin "AD1") (pinfunction "AD1_AD1") (pintype "input"))
      (node (ref "B09") (pin "J2") (pinfunction "OUT_J2") (pintype "open_collector"))
      (node (ref "B10") (pin "F1") (pinfunction "IN2B_F1") (pintype "input"))
    )
    (net (code "110") (name "D_SET") (class "Default")
      (node (ref "C07") (pin "R2") (pinfunction "OUT_R2") (pintype "output"))
      (node (ref "C08") (pin "P1") (pinfunction "D_P1") (pintype "input"))
    )
    (net (code "111") (name "EXECUTE") (class "Default")
      (node (ref "B09") (pin "F1") (pinfunction "IN1_F1") (pintype "input"))
      (node (ref "B09") (pin "H1") (pinfunction "IN2_H1") (pintype "input"))
      (node (ref "B09") (pin "J1") (pinfunction "IN3_J1") (pintype "input"))
      (node (ref "B09") (pin "K1") (pinfunction "IN4_K1") (pintype "input"))
      (node (ref "C08") (pin "V2") (pinfunction "1_V2") (pintype "output"))
    )
    (net (code "112") (name "E_SET") (class "Default")
      (node (ref "C07") (pin "S2") (pinfunction "IN_S2") (pintype "input"))
      (node (ref "C08") (pin "T2") (pinfunction "D_T2") (pintype "input"))
      (node (ref "C09") (pin "V1") (pinfunction "OUT_V1") (pintype "output"))
    )
    (net (code "113") (name "FEED_HOLE") (class "Default")
      (node (ref "AB30") (pin "BM2") (pinfunction "BM2_BM2") (pintype "input"))
      (node (ref "C34") (pin "N2") (pinfunction "P$2_N2") (pintype "bidirectional"))
    )
    (net (code "114") (name "FETCH") (class "Default")
      (node (ref "A12") (pin "F1") (pinfunction "IN2B_F1") (pintype "input"))
      (node (ref "B09") (pin "A1") (pinfunction "IN1_A1") (pintype "input"))
      (node (ref "B09") (pin "B1") (pinfunction "IN2_B1") (pintype "input"))
      (node (ref "B09") (pin "C1") (pinfunction "IN3_C1") (pintype "input"))
      (node (ref "B09") (pin "D1") (pinfunction "IN4_D1") (pintype "input"))
      (node (ref "C08") (pin "P2") (pinfunction "1_P2") (pintype "output"))
    )
    (net (code "115") (name "F_SET") (class "Default")
      (node (ref "B13") (pin "E1") (pinfunction "IN2_E1") (pintype "input"))
      (node (ref "C07") (pin "N2") (pinfunction "OUT_N2") (pintype "output"))
      (node (ref "C08") (pin "M2") (pinfunction "D_M2") (pintype "input"))
      (node (ref "C28") (pin "F2") (pinfunction "IN3_F2") (pintype "input"))
      (node (ref "D09") (pin "F1") (pinfunction "IN2B_F1") (pintype "input"))
    )
    (net (code "116") (name "GND") (class "Default")
      (node (ref "A01") (pin "C2") (pinfunction "P$2_C2") (pintype "bidirectional"))
      (node (ref "A01") (pin "T1") (pinfunction "P$2_T1") (pintype "bidirectional"))
      (node (ref "A10") (pin "J1") (pinfunction "IN3B_J1") (pintype "input"))
      (node (ref "A17") (pin "L1") (pinfunction "L1_L1") (pintype "input"))
      (node (ref "A17") (pin "M1") (pinfunction "M1_M1") (pintype "input"))
      (node (ref "A24") (pin "D1") (pinfunction "D1_D1") (pintype "input"))
      (node (ref "A24") (pin "L1") (pinfunction "L1_L1") (pintype "input"))
      (node (ref "A24") (pin "M2") (pinfunction "M2_M2") (pintype "input"))
      (node (ref "A24") (pin "N2") (pinfunction "N2_N2") (pintype "input"))
      (node (ref "A25") (pin "E2") (pinfunction "P$2_E2") (pintype "passive"))
      (node (ref "A28") (pin "C2") (pinfunction "P$2_C2") (pintype "bidirectional"))
      (node (ref "A28") (pin "D2") (pinfunction "P$2_D2") (pintype "bidirectional"))
      (node (ref "A28") (pin "E2") (pinfunction "P$2_E2") (pintype "bidirectional"))
      (node (ref "A36") (pin "C2") (pinfunction "P$2_C2") (pintype "bidirectional"))
      (node (ref "A36") (pin "T1") (pinfunction "P$2_T1") (pintype "bidirectional"))
      (node (ref "AB02") (pin "AB2") (pinfunction "AB2_AB2") (pintype "input"))
      (node (ref "AB02") (pin "BB2") (pinfunction "BB2_BB2") (pintype "input"))
      (node (ref "AB02") (pin "BD1") (pinfunction "BD1_BD1") (pintype "input"))
      (node (ref "AB02") (pin "BE2") (pinfunction "BE2_BE2") (pintype "input"))
      (node (ref "AB02") (pin "BF1") (pinfunction "BF1_BF1") (pintype "input"))
      (node (ref "AB02") (pin "BF2") (pinfunction "BF2_BF2") (pintype "input"))
      (node (ref "AB02") (pin "BH1") (pinfunction "BH1_BH1") (pintype "input"))
      (node (ref "AB02") (pin "BN1") (pinfunction "BN1_BN1") (pintype "input"))
      (node (ref "AB02") (pin "BN2") (pinfunction "BN2_BN2") (pintype "input"))
      (node (ref "AB03") (pin "AB2") (pinfunction "AB2_AB2") (pintype "input"))
      (node (ref "AB03") (pin "BB2") (pinfunction "BB2_BB2") (pintype "input"))
      (node (ref "AB03") (pin "BD1") (pinfunction "BD1_BD1") (pintype "input"))
      (node (ref "AB03") (pin "BE2") (pinfunction "BE2_BE2") (pintype "input"))
      (node (ref "AB03") (pin "BF1") (pinfunction "BF1_BF1") (pintype "input"))
      (node (ref "AB03") (pin "BF2") (pinfunction "BF2_BF2") (pintype "input"))
      (node (ref "AB03") (pin "BH1") (pinfunction "BH1_BH1") (pintype "input"))
      (node (ref "AB03") (pin "BN1") (pinfunction "BN1_BN1") (pintype "input"))
      (node (ref "AB03") (pin "BN2") (pinfunction "BN2_BN2") (pintype "input"))
      (node (ref "AB04") (pin "AB2") (pinfunction "AB2_AB2") (pintype "input"))
      (node (ref "AB04") (pin "BB2") (pinfunction "BB2_BB2") (pintype "input"))
      (node (ref "AB04") (pin "BD1") (pinfunction "BD1_BD1") (pintype "input"))
      (node (ref "AB04") (pin "BE2") (pinfunction "BE2_BE2") (pintype "input"))
      (node (ref "AB04") (pin "BF1") (pinfunction "BF1_BF1") (pintype "input"))
      (node (ref "AB04") (pin "BF2") (pinfunction "BF2_BF2") (pintype "input"))
      (node (ref "AB04") (pin "BH1") (pinfunction "BH1_BH1") (pintype "input"))
      (node (ref "AB04") (pin "BN1") (pinfunction "BN1_BN1") (pintype "input"))
      (node (ref "AB04") (pin "BN2") (pinfunction "BN2_BN2") (pintype "input"))
      (node (ref "AB05") (pin "AB2") (pinfunction "AB2_AB2") (pintype "input"))
      (node (ref "AB05") (pin "BB2") (pinfunction "BB2_BB2") (pintype "input"))
      (node (ref "AB05") (pin "BD1") (pinfunction "BD1_BD1") (pintype "input"))
      (node (ref "AB05") (pin "BE2") (pinfunction "BE2_BE2") (pintype "input"))
      (node (ref "AB05") (pin "BF1") (pinfunction "BF1_BF1") (pintype "input"))
      (node (ref "AB05") (pin "BF2") (pinfunction "BF2_BF2") (pintype "input"))
      (node (ref "AB05") (pin "BH1") (pinfunction "BH1_BH1") (pintype "input"))
      (node (ref "AB05") (pin "BN1") (pinfunction "BN1_BN1") (pintype "input"))
      (node (ref "AB05") (pin "BN2") (pinfunction "BN2_BN2") (pintype "input"))
      (node (ref "AB06") (pin "AB2") (pinfunction "AB2_AB2") (pintype "input"))
      (node (ref "AB06") (pin "BB2") (pinfunction "BB2_BB2") (pintype "input"))
      (node (ref "AB06") (pin "BD1") (pinfunction "BD1_BD1") (pintype "input"))
      (node (ref "AB06") (pin "BE2") (pinfunction "BE2_BE2") (pintype "input"))
      (node (ref "AB06") (pin "BF1") (pinfunction "BF1_BF1") (pintype "input"))
      (node (ref "AB06") (pin "BF2") (pinfunction "BF2_BF2") (pintype "input"))
      (node (ref "AB06") (pin "BH1") (pinfunction "BH1_BH1") (pintype "input"))
      (node (ref "AB06") (pin "BN1") (pinfunction "BN1_BN1") (pintype "input"))
      (node (ref "AB06") (pin "BN2") (pinfunction "BN2_BN2") (pintype "input"))
      (node (ref "AB07") (pin "AB2") (pinfunction "AB2_AB2") (pintype "input"))
      (node (ref "AB07") (pin "BB2") (pinfunction "BB2_BB2") (pintype "input"))
      (node (ref "AB07") (pin "BD1") (pinfunction "BD1_BD1") (pintype "input"))
      (node (ref "AB07") (pin "BE2") (pinfunction "BE2_BE2") (pintype "input"))
      (node (ref "AB07") (pin "BF1") (pinfunction "BF1_BF1") (pintype "input"))
      (node (ref "AB07") (pin "BF2") (pinfunction "BF2_BF2") (pintype "input"))
      (node (ref "AB07") (pin "BH1") (pinfunction "BH1_BH1") (pintype "input"))
      (node (ref "AB07") (pin "BN1") (pinfunction "BN1_BN1") (pintype "input"))
      (node (ref "AB07") (pin "BN2") (pinfunction "BN2_BN2") (pintype "input"))
      (node (ref "B01") (pin "C2") (pinfunction "P$2_C2") (pintype "bidirectional"))
      (node (ref "B01") (pin "T1") (pinfunction "P$2_T1") (pintype "bidirectional"))
      (node (ref "B17") (pin "J1") (pinfunction "8A_J1") (pintype "input"))
      (node (ref "B26") (pin "E2") (pinfunction "P$2_E2") (pintype "passive"))
      (node (ref "B28") (pin "C2") (pinfunction "P$2_C2") (pintype "bidirectional"))
      (node (ref "B28") (pin "D2") (pinfunction "P$2_D2") (pintype "bidirectional"))
      (node (ref "B28") (pin "E2") (pinfunction "P$2_E2") (pintype "bidirectional"))
      (node (ref "B28") (pin "F2") (pinfunction "P$2_F2") (pintype "bidirectional"))
      (node (ref "B28") (pin "H2") (pinfunction "P$2_H2") (pintype "bidirectional"))
      (node (ref "C01") (pin "C2") (pinfunction "P$2_C2") (pintype "bidirectional"))
      (node (ref "C01") (pin "T1") (pinfunction "P$2_T1") (pintype "bidirectional"))
      (node (ref "C04") (pin "D2") (pinfunction "C_D2") (pintype "input"))
      (node (ref "C04") (pin "E2") (pinfunction "D_E2") (pintype "input"))
      (node (ref "C04") (pin "J1") (pinfunction "D_J1") (pintype "input"))
      (node (ref "C04") (pin "M2") (pinfunction "D_M2") (pintype "input"))
      (node (ref "C04") (pin "P1") (pinfunction "D_P1") (pintype "input"))
      (node (ref "C04") (pin "T2") (pinfunction "D_T2") (pintype "input"))
      (node (ref "C06") (pin "J1") (pinfunction "D_J1") (pintype "input"))
      (node (ref "C27") (pin "C1") (pinfunction "C_C1") (pintype "input"))
      (node (ref "C27") (pin "E2") (pinfunction "B_E2") (pintype "input"))
      (node (ref "C27") (pin "F2") (pinfunction "C_F2") (pintype "input"))
      (node (ref "C27") (pin "J1") (pinfunction "C_J1") (pintype "input"))
      (node (ref "C27") (pin "M2") (pinfunction "C_M2") (pintype "input"))
      (node (ref "C27") (pin "P1") (pinfunction "C_P1") (pintype "input"))
      (node (ref "C27") (pin "T2") (pinfunction "C_T2") (pintype "input"))
      (node (ref "C31") (pin "C2") (pinfunction "P$2_C2") (pintype "bidirectional"))
      (node (ref "C31") (pin "T1") (pinfunction "P$2_T1") (pintype "bidirectional"))
      (node (ref "C32") (pin "C2") (pinfunction "P$2_C2") (pintype "bidirectional"))
      (node (ref "C32") (pin "T1") (pinfunction "P$2_T1") (pintype "bidirectional"))
      (node (ref "C33") (pin "C2") (pinfunction "P$2_C2") (pintype "bidirectional"))
      (node (ref "C34") (pin "C1") (pinfunction "P$2_C1") (pintype "bidirectional"))
      (node (ref "C34") (pin "T1") (pinfunction "P$2_T1") (pintype "bidirectional"))
      (node (ref "D01") (pin "C2") (pinfunction "P$2_C2") (pintype "bidirectional"))
      (node (ref "D01") (pin "T1") (pinfunction "P$2_T1") (pintype "bidirectional"))
      (node (ref "D16") (pin "E2") (pinfunction "D_E2") (pintype "input"))
      (node (ref "D16") (pin "J1") (pinfunction "D_J1") (pintype "input"))
      (node (ref "D16") (pin "M2") (pinfunction "D_M2") (pintype "input"))
      (node (ref "D16") (pin "P1") (pinfunction "D_P1") (pintype "input"))
      (node (ref "D16") (pin "T2") (pinfunction "D_T2") (pintype "input"))
      (node (ref "D27") (pin "C1") (pinfunction "C_C1") (pintype "input"))
      (node (ref "D27") (pin "F2") (pinfunction "C_F2") (pintype "input"))
      (node (ref "D27") (pin "J1") (pinfunction "C_J1") (pintype "input"))
      (node (ref "D27") (pin "M2") (pinfunction "C_M2") (pintype "input"))
      (node (ref "D27") (pin "P1") (pinfunction "C_P1") (pintype "input"))
      (node (ref "D27") (pin "T2") (pinfunction "C_T2") (pintype "input"))
      (node (ref "D28") (pin "C1") (pinfunction "C_C1") (pintype "input"))
      (node (ref "D28") (pin "F2") (pinfunction "C_F2") (pintype "input"))
      (node (ref "D28") (pin "J1") (pinfunction "C_J1") (pintype "input"))
      (node (ref "D28") (pin "M2") (pinfunction "C_M2") (pintype "input"))
      (node (ref "D28") (pin "P1") (pinfunction "C_P1") (pintype "input"))
      (node (ref "D28") (pin "T2") (pinfunction "C_T2") (pintype "input"))
      (node (ref "D31") (pin "C2") (pinfunction "P$2_C2") (pintype "bidirectional"))
      (node (ref "D31") (pin "T1") (pinfunction "P$2_T1") (pintype "bidirectional"))
      (node (ref "D32") (pin "C2") (pinfunction "P$2_C2") (pintype "bidirectional"))
      (node (ref "D32") (pin "D1") (pinfunction "P$2_D1") (pintype "bidirectional"))
      (node (ref "D32") (pin "T1") (pinfunction "P$2_T1") (pintype "bidirectional"))
      (node (ref "D33") (pin "C2") (pinfunction "P$2_C2") (pintype "bidirectional"))
    )
    (net (code "117") (name "HZ880") (class "Default")
      (node (ref "C33") (pin "J2") (pinfunction "P$2_J2") (pintype "bidirectional"))
      (node (ref "C33") (pin "P2") (pinfunction "P$2_P2") (pintype "bidirectional"))
    )
    (net (code "118") (name "INHIBIT") (class "Default")
      (node (ref "C15") (pin "H1") (pinfunction "IN1_H1") (pintype "input"))
      (node (ref "D16") (pin "P2") (pinfunction "1_P2") (pintype "output"))
    )
    (net (code "119") (name "INITIALIZE") (class "Default")
      (node (ref "C05") (pin "N1") (pinfunction "OUT_N1") (pintype "output"))
      (node (ref "C27") (pin "S2") (pinfunction "B_S2") (pintype "input"))
      (node (ref "D02") (pin "M2") (pinfunction "IN_M2") (pintype "input"))
      (node (ref "D31") (pin "E2") (pinfunction "P$2_E2") (pintype "bidirectional"))
      (node (ref "D32") (pin "F2") (pinfunction "P$2_F2") (pintype "bidirectional"))
    )
    (net (code "120") (name "INPUT_BUS00") (class "Default")
      (node (ref "AB07") (pin "BK1") (pinfunction "BK1_BK1") (pintype "input"))
      (node (ref "D13") (pin "F2") (pinfunction "OUT_F2") (pintype "output"))
    )
    (net (code "121") (name "INPUT_BUS01") (class "Default")
      (node (ref "AB07") (pin "BM1") (pinfunction "BM1_BM1") (pintype "input"))
      (node (ref "D13") (pin "J2") (pinfunction "OUT_J2") (pintype "output"))
    )
    (net (code "122") (name "INPUT_BUS02") (class "Default")
      (node (ref "AB06") (pin "BK1") (pinfunction "BK1_BK1") (pintype "input"))
      (node (ref "D13") (pin "L2") (pinfunction "OUT_L2") (pintype "output"))
    )
    (net (code "123") (name "INPUT_BUS03") (class "Default")
      (node (ref "AB06") (pin "BM1") (pinfunction "BM1_BM1") (pintype "input"))
      (node (ref "D13") (pin "N2") (pinfunction "OUT_N2") (pintype "output"))
    )
    (net (code "124") (name "INPUT_BUS04") (class "Default")
      (node (ref "A32") (pin "E1") (pinfunction "OUT_E1") (pintype "output"))
      (node (ref "AB05") (pin "BK1") (pinfunction "BK1_BK1") (pintype "input"))
    )
    (net (code "125") (name "INPUT_BUS05") (class "Default")
      (node (ref "A32") (pin "J2") (pinfunction "OUT_J2") (pintype "output"))
      (node (ref "AB05") (pin "BM1") (pinfunction "BM1_BM1") (pintype "input"))
    )
    (net (code "126") (name "INPUT_BUS06") (class "Default")
      (node (ref "A32") (pin "L1") (pinfunction "OUT_L1") (pintype "output"))
      (node (ref "AB04") (pin "BK1") (pinfunction "BK1_BK1") (pintype "input"))
    )
    (net (code "127") (name "INPUT_BUS07") (class "Default")
      (node (ref "A32") (pin "P2") (pinfunction "OUT_P2") (pintype "output"))
      (node (ref "AB04") (pin "BM1") (pinfunction "BM1_BM1") (pintype "input"))
    )
    (net (code "128") (name "INPUT_BUS08") (class "Default")
      (node (ref "A32") (pin "S1") (pinfunction "OUT_S1") (pintype "output"))
      (node (ref "AB03") (pin "BK1") (pinfunction "BK1_BK1") (pintype "input"))
    )
    (net (code "129") (name "INPUT_BUS09") (class "Default")
      (node (ref "A32") (pin "V2") (pinfunction "OUT_V2") (pintype "output"))
      (node (ref "AB03") (pin "BM1") (pinfunction "BM1_BM1") (pintype "input"))
    )
    (net (code "130") (name "INPUT_BUS10") (class "Default")
      (node (ref "A33") (pin "E1") (pinfunction "OUT_E1") (pintype "output"))
      (node (ref "AB02") (pin "BK1") (pinfunction "BK1_BK1") (pintype "input"))
    )
    (net (code "131") (name "INPUT_BUS11") (class "Default")
      (node (ref "A33") (pin "J2") (pinfunction "OUT_J2") (pintype "output"))
      (node (ref "AB02") (pin "BM1") (pinfunction "BM1_BM1") (pintype "input"))
    )
    (net (code "132") (name "INT_DELAY") (class "Default")
      (node (ref "B11") (pin "J2") (pinfunction "0_J2") (pintype "output"))
      (node (ref "C13") (pin "D2") (pinfunction "IN1_D2") (pintype "input"))
    )
    (net (code "133") (name "INT_ENABLE") (class "Default")
      (node (ref "B11") (pin "F1") (pinfunction "0_F1") (pintype "output"))
      (node (ref "B11") (pin "F2") (pinfunction "S_F2") (pintype "input"))
    )
    (net (code "134") (name "INT_OK") (class "Default")
      (node (ref "B12") (pin "N2") (pinfunction "OUT_N2") (pintype "output"))
      (node (ref "B13") (pin "U2") (pinfunction "IN2_U2") (pintype "input"))
      (node (ref "C15") (pin "L2") (pinfunction "IN1_L2") (pintype "input"))
      (node (ref "D12") (pin "J2") (pinfunction "IN2_J2") (pintype "input"))
    )
    (net (code "135") (name "INT_RQST") (class "Default")
      (node (ref "A33") (pin "P2") (pinfunction "OUT_P2") (pintype "output"))
      (node (ref "C28") (pin "D2") (pinfunction "IN1_D2") (pintype "input"))
    )
    (net (code "136") (name "INT_STROBE") (class "Default")
      (node (ref "B11") (pin "H1") (pinfunction "C_H1") (pintype "input"))
      (node (ref "C05") (pin "F1") (pinfunction "OUT_F1") (pintype "output"))
      (node (ref "C13") (pin "K2") (pinfunction "IN1_K2") (pintype "input"))
      (node (ref "C14") (pin "P2") (pinfunction "IN1_P2") (pintype "input"))
      (node (ref "D02") (pin "R1") (pinfunction "IN_R1") (pintype "input"))
    )
    (net (code "137") (name "INT_SYNC") (class "Default")
      (node (ref "B11") (pin "M1") (pinfunction "0_M1") (pintype "output"))
      (node (ref "C13") (pin "E2") (pinfunction "IN2_E2") (pintype "input"))
    )
    (net (code "138") (name "IOP1") (class "Default")
      (node (ref "AB30") (pin "AU2") (pinfunction "AU2_AU2") (pintype "input"))
      (node (ref "AB31") (pin "AR2") (pinfunction "AR2_AR2") (pintype "input"))
      (node (ref "B15") (pin "H1") (pinfunction "IN2_H1") (pintype "input"))
      (node (ref "D02") (pin "F2") (pinfunction "OUT_F2") (pintype "output"))
      (node (ref "D31") (pin "H2") (pinfunction "P$2_H2") (pintype "bidirectional"))
      (node (ref "D32") (pin "D2") (pinfunction "P$2_D2") (pintype "bidirectional"))
    )
    (net (code "139") (name "IOP2") (class "Default")
      (node (ref "A36") (pin "M2") (pinfunction "P$2_M2") (pintype "bidirectional"))
      (node (ref "AB30") (pin "AV2") (pinfunction "AV2_AV2") (pintype "input"))
      (node (ref "AB31") (pin "AR1") (pinfunction "AR1_AR1") (pintype "input"))
      (node (ref "D02") (pin "J2") (pinfunction "OUT_J2") (pintype "output"))
      (node (ref "D31") (pin "D2") (pinfunction "P$2_D2") (pintype "bidirectional"))
      (node (ref "D32") (pin "J2") (pinfunction "P$2_J2") (pintype "bidirectional"))
    )
    (net (code "140") (name "IOP4") (class "Default")
      (node (ref "AB30") (pin "BK1") (pinfunction "BK1_BK1") (pintype "input"))
      (node (ref "AB31") (pin "AP2") (pinfunction "AP2_AP2") (pintype "input"))
      (node (ref "B15") (pin "A1") (pinfunction "IN1_A1") (pintype "input"))
      (node (ref "B15") (pin "B1") (pinfunction "IN2_B1") (pintype "input"))
      (node (ref "C31") (pin "S1") (pinfunction "P$2_S1") (pintype "bidirectional"))
      (node (ref "C32") (pin "L2") (pinfunction "P$2_L2") (pintype "bidirectional"))
      (node (ref "D02") (pin "L2") (pinfunction "OUT_L2") (pintype "output"))
    )
    (net (code "141") (name "IOP_A") (class "Default")
      (node (ref "C06") (pin "E1") (pinfunction "1_E1") (pintype "output"))
      (node (ref "D04") (pin "E2") (pinfunction "IN2_E2") (pintype "input"))
    )
    (net (code "142") (name "IOP_B") (class "Default")
      (node (ref "C06") (pin "R2") (pinfunction "0_R2") (pintype "output"))
      (node (ref "D04") (pin "K2") (pinfunction "IN2_K2") (pintype "input"))
    )
    (net (code "143") (name "IOP_C") (class "Default")
      (node (ref "C05") (pin "J1") (pinfunction "IN2_J1") (pintype "input"))
      (node (ref "C06") (pin "C1") (pinfunction "D_C1") (pintype "input"))
      (node (ref "C06") (pin "J2") (pinfunction "0_J2") (pintype "output"))
      (node (ref "D04") (pin "P2") (pinfunction "IN2_P2") (pintype "input"))
    )
    (net (code "144") (name "IOT") (class "Default")
      (node (ref "B14") (pin "M1") (pinfunction "IN1_M1") (pintype "input"))
      (node (ref "C05") (pin "E2") (pinfunction "IN2_E2") (pintype "input"))
      (node (ref "C07") (pin "U1") (pinfunction "OUT_U1") (pintype "output"))
    )
    (net (code "145") (name "IO_ENABLE") (class "Default")
      (node (ref "A08") (pin "S1") (pinfunction "OUT_S1") (pintype "open_collector"))
      (node (ref "A13") (pin "J2") (pinfunction "IN2A_J2") (pintype "input"))
      (node (ref "A35") (pin "D1") (pinfunction "IN_D1") (pintype "input"))
      (node (ref "AB02") (pin "BL2") (pinfunction "BL2_BL2") (pintype "input"))
      (node (ref "AB03") (pin "BL2") (pinfunction "BL2_BL2") (pintype "input"))
      (node (ref "AB04") (pin "BL2") (pinfunction "BL2_BL2") (pintype "input"))
      (node (ref "AB05") (pin "BL2") (pinfunction "BL2_BL2") (pintype "input"))
      (node (ref "AB06") (pin "BL2") (pinfunction "BL2_BL2") (pintype "input"))
      (node (ref "AB07") (pin "BL2") (pinfunction "BL2_BL2") (pintype "input"))
      (node (ref "B13") (pin "M1") (pinfunction "IN2_M1") (pintype "input"))
      (node (ref "C12") (pin "U2") (pinfunction "IN2_U2") (pintype "input"))
      (node (ref "D09") (pin "J2") (pinfunction "IN2A_J2") (pintype "input"))
    )
    (net (code "146") (name "IO_ON") (class "Default")
      (node (ref "C06") (pin "L1") (pinfunction "1_L1") (pintype "output"))
      (node (ref "D04") (pin "D2") (pinfunction "IN1_D2") (pintype "input"))
      (node (ref "D04") (pin "J2") (pinfunction "IN1_J2") (pintype "input"))
      (node (ref "D04") (pin "N2") (pinfunction "IN1_N2") (pintype "input"))
    )
    (net (code "147") (name "IO_SKIP") (class "Default")
      (node (ref "A13") (pin "K2") (pinfunction "IN2B_K2") (pintype "input"))
      (node (ref "A33") (pin "L1") (pinfunction "OUT_L1") (pintype "output"))
    )
    (net (code "148") (name "IO_STROBE") (class "Default")
      (node (ref "B13") (pin "L1") (pinfunction "IN1_L1") (pintype "input"))
      (node (ref "C05") (pin "H1") (pinfunction "IN1_H1") (pintype "input"))
      (node (ref "C05") (pin "H2") (pinfunction "IN1_H2") (pintype "input"))
      (node (ref "C06") (pin "H1") (pinfunction "C_H1") (pintype "input"))
      (node (ref "C12") (pin "T2") (pinfunction "IN1_T2") (pintype "input"))
      (node (ref "D08") (pin "F1") (pinfunction "OUT_F1") (pintype "output"))
    )
    (net (code "149") (name "IR0") (class "Default")
      (node (ref "C08") (pin "F1") (pinfunction "0_F1") (pintype "output"))
      (node (ref "C09") (pin "K1") (pinfunction "IN1_K1") (pintype "input"))
      (node (ref "C09") (pin "P1") (pinfunction "IN1_P1") (pintype "input"))
      (node (ref "C10") (pin "A1") (pinfunction "IN1_A1") (pintype "input"))
      (node (ref "C10") (pin "F1") (pinfunction "IN1_F1") (pintype "input"))
      (node (ref "C11") (pin "M1") (pinfunction "IN1_M1") (pintype "input"))
      (node (ref "D12") (pin "D2") (pinfunction "IN1_D2") (pintype "input"))
    )
    (net (code "150") (name "IR1") (class "Default")
      (node (ref "C08") (pin "H2") (pinfunction "1_H2") (pintype "output"))
      (node (ref "C09") (pin "F1") (pinfunction "IN2_F1") (pintype "input"))
      (node (ref "C09") (pin "K2") (pinfunction "IN2_K2") (pintype "input"))
      (node (ref "C10") (pin "B1") (pinfunction "IN2_B1") (pintype "input"))
      (node (ref "C10") (pin "H1") (pinfunction "IN2_H1") (pintype "input"))
      (node (ref "C11") (pin "N1") (pinfunction "IN2_N1") (pintype "input"))
      (node (ref "D12") (pin "E2") (pinfunction "IN2_E2") (pintype "input"))
    )
    (net (code "151") (name "IR2") (class "Default")
      (node (ref "C08") (pin "L1") (pinfunction "1_L1") (pintype "output"))
      (node (ref "C09") (pin "C1") (pinfunction "IN3_C1") (pintype "input"))
      (node (ref "C09") (pin "L2") (pinfunction "IN3_L2") (pintype "input"))
      (node (ref "C09") (pin "S1") (pinfunction "IN3_S1") (pintype "input"))
      (node (ref "C10") (pin "C1") (pinfunction "IN3_C1") (pintype "input"))
      (node (ref "C10") (pin "J1") (pinfunction "IN3_J1") (pintype "input"))
    )
    (net (code "152") (name "ISZ") (class "Default")
      (node (ref "A12") (pin "F2") (pinfunction "IN1C_F2") (pintype "input"))
      (node (ref "A13") (pin "H2") (pinfunction "IN1D_H2") (pintype "input"))
      (node (ref "C07") (pin "K1") (pinfunction "OUT_K1") (pintype "output"))
    )
    (net (code "153") (name "JMP") (class "Default")
      (node (ref "A10") (pin "D1") (pinfunction "IN1D_D1") (pintype "input"))
      (node (ref "A13") (pin "P1") (pinfunction "IN5C_P1") (pintype "input"))
      (node (ref "C07") (pin "S1") (pinfunction "OUT_S1") (pintype "output"))
      (node (ref "C13") (pin "B1") (pinfunction "IN2_B1") (pintype "input"))
    )
    (net (code "154") (name "JMS") (class "Default")
      (node (ref "A10") (pin "F2") (pinfunction "IN1C_F2") (pintype "input"))
      (node (ref "A12") (pin "P1") (pinfunction "IN5C_P1") (pintype "input"))
      (node (ref "A13") (pin "B1") (pinfunction "IN1B_B1") (pintype "input"))
      (node (ref "B10") (pin "H2") (pinfunction "IN1D_H2") (pintype "input"))
      (node (ref "C07") (pin "P1") (pinfunction "OUT_P1") (pintype "output"))
      (node (ref "C11") (pin "U2") (pinfunction "IN4_U2") (pintype "input"))
    )
    (net (code "155") (name "KEY_CONT") (class "Default")
      (node (ref "C02") (pin "R2") (pinfunction "IN2_R2") (pintype "input"))
      (node (ref "D02") (pin "H1") (pinfunction "OUT_H1") (pintype "output"))
    )
    (net (code "156") (name "KEY_DP") (class "Default")
      (node (ref "A10") (pin "P2") (pinfunction "IN4B_P2") (pintype "input"))
      (node (ref "A10") (pin "R2") (pinfunction "IN4C_R2") (pintype "input"))
      (node (ref "A10") (pin "S2") (pinfunction "IN4D_S2") (pintype "input"))
      (node (ref "C12") (pin "P1") (pinfunction "IN1_P1") (pintype "input"))
      (node (ref "D02") (pin "D2") (pinfunction "OUT_D2") (pintype "output"))
    )
    (net (code "157") (name "KEY_EX+DP") (class "Default")
      (node (ref "A12") (pin "K2") (pinfunction "IN2B_K2") (pintype "input"))
      (node (ref "B10") (pin "M2") (pinfunction "IN3B_M2") (pintype "input"))
      (node (ref "C02") (pin "F1") (pinfunction "OUT_F1") (pintype "output"))
      (node (ref "D02") (pin "D1") (pinfunction "IN_D1") (pintype "input"))
    )
    (net (code "158") (name "KEY_LA") (class "Default")
      (node (ref "B13") (pin "D2") (pinfunction "IN1_D2") (pintype "input"))
      (node (ref "D02") (pin "B1") (pinfunction "OUT_B1") (pintype "output"))
      (node (ref "D17") (pin "M2") (pinfunction "IN3_M2") (pintype "input"))
      (node (ref "D17") (pin "N2") (pinfunction "IN4_N2") (pintype "input"))
    )
    (net (code "159") (name "KEY_LA+EX+DP") (class "Default")
      (node (ref "A13") (pin "L1") (pinfunction "IN4B_L1") (pintype "input"))
      (node (ref "C02") (pin "K2") (pinfunction "OUT_K2") (pintype "output"))
      (node (ref "C14") (pin "P1") (pinfunction "IN1_P1") (pintype "input"))
      (node (ref "D09") (pin "H1") (pinfunction "IN3A_H1") (pintype "input"))
    )
    (net (code "160") (name "KEY_SS+I_REF") (class "Default")
      (node (ref "C02") (pin "F2") (pinfunction "OUT_F2") (pintype "output"))
      (node (ref "D09") (pin "M1") (pinfunction "IN5A_M1") (pintype "input"))
    )
    (net (code "161") (name "KEY_ST") (class "Default")
      (node (ref "A12") (pin "U2") (pinfunction "IN2B_U2") (pintype "input"))
      (node (ref "C02") (pin "C1") (pinfunction "OUT_C1") (pintype "output"))
      (node (ref "C02") (pin "U2") (pinfunction "IN2_U2") (pintype "input"))
      (node (ref "D12") (pin "B1") (pinfunction "IN2_B1") (pintype "input"))
    )
    (net (code "162") (name "KEY_ST+EX+DP") (class "Default")
      (node (ref "C12") (pin "M1") (pinfunction "IN3_M1") (pintype "input"))
      (node (ref "D04") (pin "N1") (pinfunction "OUT_N1") (pintype "output"))
    )
    (net (code "163") (name "KEY_STOP") (class "Default")
      (node (ref "C02") (pin "K1") (pinfunction "OUT_K1") (pintype "output"))
      (node (ref "D09") (pin "E1") (pinfunction "IN2A_E1") (pintype "input"))
    )
    (net (code "164") (name "LEFT_SHIFT") (class "Default")
      (node (ref "AB02") (pin "AF2") (pinfunction "AF2_AF2") (pintype "input"))
      (node (ref "AB03") (pin "AF2") (pinfunction "AF2_AF2") (pintype "input"))
      (node (ref "AB04") (pin "AF2") (pinfunction "AF2_AF2") (pintype "input"))
      (node (ref "AB05") (pin "AF2") (pinfunction "AF2_AF2") (pintype "input"))
      (node (ref "AB06") (pin "AF2") (pinfunction "AF2_AF2") (pintype "input"))
      (node (ref "AB07") (pin "AF2") (pinfunction "AF2_AF2") (pintype "input"))
      (node (ref "B09") (pin "P2") (pinfunction "OUT_P2") (pintype "open_collector"))
      (node (ref "B10") (pin "L1") (pinfunction "IN4B_L1") (pintype "input"))
    )
    (net (code "165") (name "LINK") (class "Default")
      (node (ref "A10") (pin "S1") (pinfunction "IN1A_S1") (pintype "input"))
      (node (ref "B11") (pin "P2") (pinfunction "1_P2") (pintype "output"))
      (node (ref "C14") (pin "L2") (pinfunction "IN1_L2") (pintype "input"))
    )
    (net (code "166") (name "LOCK") (class "Default")
      (node (ref "C15") (pin "H2") (pinfunction "IN1_H2") (pintype "input"))
      (node (ref "D16") (pin "V2") (pinfunction "1_V2") (pintype "output"))
    )
    (net (code "167") (name "L_ENABLE") (class "Default")
      (node (ref "A10") (pin "U1") (pinfunction "IN1B_U1") (pintype "input"))
      (node (ref "A12") (pin "V2") (pinfunction "OUT_V2") (pintype "output"))
    )
    (net (code "168") (name "MA00") (class "Default")
      (node (ref "AB07") (pin "AM2") (pinfunction "AM2_AM2") (pintype "output"))
      (node (ref "C10") (pin "N1") (pinfunction "IN2_N1") (pintype "input"))
      (node (ref "C23") (pin "E2") (pinfunction "E2_E2") (pintype "input"))
    )
    (net (code "169") (name "MA01") (class "Default")
      (node (ref "AB07") (pin "AL2") (pinfunction "AL2_AL2") (pintype "output"))
      (node (ref "C10") (pin "P1") (pinfunction "IN3_P1") (pintype "input"))
      (node (ref "C23") (pin "H2") (pinfunction "H2_H2") (pintype "input"))
      (node (ref "C24") (pin "H2") (pinfunction "H2_H2") (pintype "input"))
    )
    (net (code "170") (name "MA02") (class "Default")
      (node (ref "AB06") (pin "AM2") (pinfunction "AM2_AM2") (pintype "output"))
      (node (ref "C10") (pin "R1") (pinfunction "IN4_R1") (pintype "input"))
      (node (ref "C23") (pin "F2") (pinfunction "F2_F2") (pintype "input"))
      (node (ref "C24") (pin "F2") (pinfunction "F2_F2") (pintype "input"))
    )
    (net (code "171") (name "MA03") (class "Default")
      (node (ref "AB06") (pin "AL2") (pinfunction "AL2_AL2") (pintype "output"))
      (node (ref "C10") (pin "R2") (pinfunction "IN5_R2") (pintype "input"))
      (node (ref "D19") (pin "E2") (pinfunction "E2_E2") (pintype "input"))
    )
    (net (code "172") (name "MA04") (class "Default")
      (node (ref "AB05") (pin "AM2") (pinfunction "AM2_AM2") (pintype "output"))
      (node (ref "C10") (pin "S2") (pinfunction "IN6_S2") (pintype "input"))
      (node (ref "D18") (pin "H2") (pinfunction "H2_H2") (pintype "input"))
      (node (ref "D19") (pin "H2") (pinfunction "H2_H2") (pintype "input"))
    )
    (net (code "173") (name "MA05") (class "Default")
      (node (ref "AB05") (pin "AL2") (pinfunction "AL2_AL2") (pintype "output"))
      (node (ref "D18") (pin "F2") (pinfunction "F2_F2") (pintype "input"))
      (node (ref "D19") (pin "F2") (pinfunction "F2_F2") (pintype "input"))
    )
    (net (code "174") (name "MA06") (class "Default")
      (node (ref "AB04") (pin "AM2") (pinfunction "AM2_AM2") (pintype "output"))
      (node (ref "C18") (pin "E2") (pinfunction "E2_E2") (pintype "input"))
    )
    (net (code "175") (name "MA07") (class "Default")
      (node (ref "AB04") (pin "AL2") (pinfunction "AL2_AL2") (pintype "output"))
      (node (ref "C18") (pin "H2") (pinfunction "H2_H2") (pintype "input"))
      (node (ref "C19") (pin "H2") (pinfunction "H2_H2") (pintype "input"))
    )
    (net (code "176") (name "MA08") (class "Default")
      (node (ref "A12") (pin "D1") (pinfunction "IN1D_D1") (pintype "input"))
      (node (ref "AB03") (pin "AM2") (pinfunction "AM2_AM2") (pintype "output"))
      (node (ref "C18") (pin "F2") (pinfunction "F2_F2") (pintype "input"))
      (node (ref "C19") (pin "F2") (pinfunction "F2_F2") (pintype "input"))
    )
    (net (code "177") (name "MA09") (class "Default")
      (node (ref "AB03") (pin "AL2") (pinfunction "AL2_AL2") (pintype "output"))
      (node (ref "D24") (pin "E2") (pinfunction "E2_E2") (pintype "input"))
    )
    (net (code "178") (name "MA10") (class "Default")
      (node (ref "AB02") (pin "AM2") (pinfunction "AM2_AM2") (pintype "output"))
      (node (ref "D23") (pin "H2") (pinfunction "H2_H2") (pintype "input"))
      (node (ref "D24") (pin "H2") (pinfunction "H2_H2") (pintype "input"))
    )
    (net (code "179") (name "MA11") (class "Default")
      (node (ref "AB02") (pin "AL2") (pinfunction "AL2_AL2") (pintype "output"))
      (node (ref "D23") (pin "F2") (pinfunction "F2_F2") (pintype "input"))
      (node (ref "D24") (pin "F2") (pinfunction "F2_F2") (pintype "input"))
    )
    (net (code "180") (name "MA_ENABLE(0-4)") (class "Default")
      (node (ref "A08") (pin "J2") (pinfunction "OUT_J2") (pintype "open_collector"))
      (node (ref "AB05") (pin "BP1") (pinfunction "BP1_BP1") (pintype "input"))
      (node (ref "AB06") (pin "BP1") (pinfunction "BP1_BP1") (pintype "input"))
      (node (ref "AB06") (pin "BR2") (pinfunction "BR2_BR2") (pintype "input"))
      (node (ref "AB07") (pin "BP1") (pinfunction "BP1_BP1") (pintype "input"))
      (node (ref "AB07") (pin "BR2") (pinfunction "BR2_BR2") (pintype "input"))
    )
    (net (code "181") (name "MA_ENABLE(5-11)") (class "Default")
      (node (ref "A09") (pin "J2") (pinfunction "OUT_J2") (pintype "open_collector"))
      (node (ref "AB02") (pin "BP1") (pinfunction "BP1_BP1") (pintype "input"))
      (node (ref "AB02") (pin "BR2") (pinfunction "BR2_BR2") (pintype "input"))
      (node (ref "AB03") (pin "BP1") (pinfunction "BP1_BP1") (pintype "input"))
      (node (ref "AB03") (pin "BR2") (pinfunction "BR2_BR2") (pintype "input"))
      (node (ref "AB04") (pin "BP1") (pinfunction "BP1_BP1") (pintype "input"))
      (node (ref "AB04") (pin "BR2") (pinfunction "BR2_BR2") (pintype "input"))
      (node (ref "AB05") (pin "BR2") (pinfunction "BR2_BR2") (pintype "input"))
    )
    (net (code "182") (name "MA_LOAD") (class "Default")
      (node (ref "AB02") (pin "AK1") (pinfunction "AK1_AK1") (pintype "input"))
      (node (ref "AB03") (pin "AK1") (pinfunction "AK1_AK1") (pintype "input"))
      (node (ref "AB04") (pin "AK1") (pinfunction "AK1_AK1") (pintype "input"))
      (node (ref "AB05") (pin "AK1") (pinfunction "AK1_AK1") (pintype "input"))
      (node (ref "AB06") (pin "AK1") (pinfunction "AK1_AK1") (pintype "input"))
      (node (ref "AB07") (pin "AK1") (pinfunction "AK1_AK1") (pintype "input"))
      (node (ref "B08") (pin "S1") (pinfunction "OUT_S1") (pintype "open_collector"))
    )
    (net (code "183") (name "MB00") (class "Default")
      (node (ref "AB07") (pin "AT2") (pinfunction "AT2_AT2") (pintype "output"))
      (node (ref "B16") (pin "E1") (pinfunction "1A_E1") (pintype "input"))
      (node (ref "D28") (pin "A1") (pinfunction "A_A1") (pintype "input"))
    )
    (net (code "184") (name "MB01") (class "Default")
      (node (ref "AB07") (pin "AS2") (pinfunction "AS2_AS2") (pintype "output"))
      (node (ref "B16") (pin "F1") (pinfunction "2A_F1") (pintype "input"))
      (node (ref "D28") (pin "B1") (pinfunction "B_B1") (pintype "input"))
    )
    (net (code "185") (name "MB02") (class "Default")
      (node (ref "AB06") (pin "AT2") (pinfunction "AT2_AT2") (pintype "output"))
      (node (ref "B16") (pin "H1") (pinfunction "4A_H1") (pintype "input"))
      (node (ref "D28") (pin "F1") (pinfunction "A_F1") (pintype "input"))
    )
    (net (code "186") (name "MB03") (class "Default")
      (node (ref "AB06") (pin "AS2") (pinfunction "AS2_AS2") (pintype "output"))
      (node (ref "B16") (pin "J1") (pinfunction "8A_J1") (pintype "input"))
      (node (ref "C09") (pin "R2") (pinfunction "IN3_R2") (pintype "input"))
      (node (ref "C10") (pin "L2") (pinfunction "IN6_L2") (pintype "input"))
      (node (ref "D28") (pin "M1") (pinfunction "A_M1") (pintype "input"))
    )
    (net (code "187") (name "MB04") (class "Default")
      (node (ref "AB05") (pin "AT2") (pinfunction "AT2_AT2") (pintype "output"))
      (node (ref "B17") (pin "P2") (pinfunction "1A_P2") (pintype "input"))
      (node (ref "C12") (pin "H1") (pinfunction "IN3_H1") (pintype "input"))
      (node (ref "D09") (pin "V1") (pinfunction "IN2A_V1") (pintype "input"))
      (node (ref "D28") (pin "D2") (pinfunction "A_D2") (pintype "input"))
    )
    (net (code "188") (name "MB05") (class "Default")
      (node (ref "A13") (pin "V1") (pinfunction "IN2A_V1") (pintype "input"))
      (node (ref "A36") (pin "F2") (pinfunction "P$2_F2") (pintype "bidirectional"))
      (node (ref "AB05") (pin "AS2") (pinfunction "AS2_AS2") (pintype "output"))
      (node (ref "B15") (pin "E2") (pinfunction "IN6_E2") (pintype "input"))
      (node (ref "B15") (pin "L2") (pinfunction "IN6_L2") (pintype "input"))
      (node (ref "B17") (pin "R2") (pinfunction "2A_R2") (pintype "input"))
      (node (ref "C14") (pin "M1") (pinfunction "IN2_M1") (pintype "input"))
      (node (ref "D28") (pin "K2") (pinfunction "A_K2") (pintype "input"))
    )
    (net (code "189") (name "MB06") (class "Default")
      (node (ref "A14") (pin "F1") (pinfunction "IN2_F1") (pintype "input"))
      (node (ref "AB04") (pin "AT2") (pinfunction "AT2_AT2") (pintype "output"))
      (node (ref "B13") (pin "J2") (pinfunction "IN2_J2") (pintype "input"))
      (node (ref "B17") (pin "S2") (pinfunction "4A_S2") (pintype "input"))
      (node (ref "C31") (pin "F1") (pinfunction "P$2_F1") (pintype "bidirectional"))
      (node (ref "D09") (pin "U1") (pinfunction "IN1B_U1") (pintype "input"))
      (node (ref "D28") (pin "R2") (pinfunction "A_R2") (pintype "input"))
    )
    (net (code "190") (name "MB07") (class "Default")
      (node (ref "A13") (pin "U2") (pinfunction "IN2B_U2") (pintype "input"))
      (node (ref "AB04") (pin "AS2") (pinfunction "AS2_AS2") (pintype "output"))
      (node (ref "AB31") (pin "BE2") (pinfunction "BE2_BE2") (pintype "input"))
      (node (ref "B13") (pin "J1") (pinfunction "IN2_J1") (pintype "input"))
      (node (ref "B17") (pin "T2") (pinfunction "8A_T2") (pintype "input"))
      (node (ref "C14") (pin "M2") (pinfunction "IN2_M2") (pintype "input"))
      (node (ref "C27") (pin "A1") (pinfunction "A_A1") (pintype "input"))
      (node (ref "C32") (pin "H2") (pinfunction "P$2_H2") (pintype "bidirectional"))
    )
    (net (code "191") (name "MB08") (class "Default")
      (node (ref "A11") (pin "D2") (pinfunction "IN1_D2") (pintype "input"))
      (node (ref "A11") (pin "E1") (pinfunction "IN1_E1") (pintype "input"))
      (node (ref "A13") (pin "R2") (pinfunction "IN4C_R2") (pintype "input"))
      (node (ref "AB03") (pin "AT2") (pinfunction "AT2_AT2") (pintype "output"))
      (node (ref "AB30") (pin "BH2") (pinfunction "BH2_BH2") (pintype "input"))
      (node (ref "B16") (pin "P2") (pinfunction "1A_P2") (pintype "input"))
      (node (ref "C27") (pin "F1") (pinfunction "A_F1") (pintype "input"))
      (node (ref "C32") (pin "J1") (pinfunction "P$2_J1") (pintype "bidirectional"))
    )
    (net (code "192") (name "MB09") (class "Default")
      (node (ref "A11") (pin "A1") (pinfunction "IN1_A1") (pintype "input"))
      (node (ref "A11") (pin "J2") (pinfunction "IN1_J2") (pintype "input"))
      (node (ref "AB03") (pin "AS2") (pinfunction "AS2_AS2") (pintype "output"))
      (node (ref "B16") (pin "R2") (pinfunction "2A_R2") (pintype "input"))
      (node (ref "C12") (pin "F2") (pinfunction "IN3_F2") (pintype "input"))
      (node (ref "C27") (pin "H1") (pinfunction "B_H1") (pintype "input"))
      (node (ref "D04") (pin "R2") (pinfunction "IN3_R2") (pintype "input"))
    )
    (net (code "193") (name "MB10") (class "Default")
      (node (ref "A11") (pin "C1") (pinfunction "IN3_C1") (pintype "input"))
      (node (ref "A11") (pin "F2") (pinfunction "IN3_F2") (pintype "input"))
      (node (ref "AB02") (pin "AT2") (pinfunction "AT2_AT2") (pintype "output"))
      (node (ref "B16") (pin "S2") (pinfunction "4A_S2") (pintype "input"))
      (node (ref "C27") (pin "M1") (pinfunction "A_M1") (pintype "input"))
      (node (ref "D04") (pin "L2") (pinfunction "IN3_L2") (pintype "input"))
      (node (ref "D09") (pin "A1") (pinfunction "IN1A_A1") (pintype "input"))
    )
    (net (code "194") (name "MB11") (class "Default")
      (node (ref "A12") (pin "J1") (pinfunction "IN3B_J1") (pintype "input"))
      (node (ref "AB02") (pin "AS2") (pinfunction "AS2_AS2") (pintype "output"))
      (node (ref "B16") (pin "T2") (pinfunction "8A_T2") (pintype "input"))
      (node (ref "C27") (pin "N1") (pinfunction "B_N1") (pintype "input"))
      (node (ref "D04") (pin "F2") (pinfunction "IN3_F2") (pintype "input"))
    )
    (net (code "195") (name "MB_LOAD") (class "Default")
      (node (ref "AB02") (pin "AR1") (pinfunction "AR1_AR1") (pintype "input"))
      (node (ref "AB03") (pin "AR1") (pinfunction "AR1_AR1") (pintype "input"))
      (node (ref "AB04") (pin "AR1") (pinfunction "AR1_AR1") (pintype "input"))
      (node (ref "AB05") (pin "AR1") (pinfunction "AR1_AR1") (pintype "input"))
      (node (ref "AB06") (pin "AR1") (pinfunction "AR1_AR1") (pintype "input"))
      (node (ref "AB07") (pin "AR1") (pinfunction "AR1_AR1") (pintype "input"))
      (node (ref "B08") (pin "P2") (pinfunction "OUT_P2") (pintype "open_collector"))
    )
    (net (code "196") (name "MB_PARITY_ODD") (class "Default")
      (node (ref "A24") (pin "D2") (pinfunction "D2_D2") (pintype "input"))
      (node (ref "B17") (pin "K1") (pinfunction "ODD_K1") (pintype "output"))
    )
    (net (code "197") (name "MEM00") (class "Default")
      (node (ref "A15") (pin "E1") (pinfunction "1A_E1") (pintype "input"))
      (node (ref "A18") (pin "A1") (pinfunction "A1_A1") (pintype "open_collector"))
      (node (ref "AB07") (pin "BR1") (pinfunction "BR1_BR1") (pintype "input"))
      (node (ref "B35") (pin "D1") (pinfunction "P$2_D1") (pintype "bidirectional"))
      (node (ref "C16") (pin "C1") (pinfunction "IN_C1") (pintype "input"))
      (node (ref "D13") (pin "R1") (pinfunction "IN_R1") (pintype "input"))
    )
    (net (code "198") (name "MEM01") (class "Default")
      (node (ref "A15") (pin "F1") (pinfunction "2A_F1") (pintype "input"))
      (node (ref "A18") (pin "U2") (pinfunction "U2_U2") (pintype "open_collector"))
      (node (ref "AB07") (pin "BV2") (pinfunction "BV2_BV2") (pintype "input"))
      (node (ref "B35") (pin "E1") (pinfunction "P$2_E1") (pintype "bidirectional"))
      (node (ref "C08") (pin "E2") (pinfunction "D_E2") (pintype "input"))
      (node (ref "C16") (pin "D1") (pinfunction "IN_D1") (pintype "input"))
    )
    (net (code "199") (name "MEM02") (class "Default")
      (node (ref "A15") (pin "H1") (pinfunction "4A_H1") (pintype "input"))
      (node (ref "A19") (pin "A1") (pinfunction "A1_A1") (pintype "open_collector"))
      (node (ref "AB06") (pin "BR1") (pinfunction "BR1_BR1") (pintype "input"))
      (node (ref "B35") (pin "H1") (pinfunction "P$2_H1") (pintype "bidirectional"))
      (node (ref "C08") (pin "J1") (pinfunction "D_J1") (pintype "input"))
      (node (ref "C16") (pin "E2") (pinfunction "IN_E2") (pintype "input"))
    )
    (net (code "200") (name "MEM03") (class "Default")
      (node (ref "A15") (pin "J1") (pinfunction "8A_J1") (pintype "input"))
      (node (ref "A19") (pin "U2") (pinfunction "U2_U2") (pintype "open_collector"))
      (node (ref "AB06") (pin "BV2") (pinfunction "BV2_BV2") (pintype "input"))
      (node (ref "B35") (pin "J1") (pinfunction "P$2_J1") (pintype "bidirectional"))
      (node (ref "C16") (pin "F1") (pinfunction "IN_F1") (pintype "input"))
    )
    (net (code "201") (name "MEM04") (class "Default")
      (node (ref "A16") (pin "P2") (pinfunction "1A_P2") (pintype "input"))
      (node (ref "A20") (pin "A1") (pinfunction "A1_A1") (pintype "open_collector"))
      (node (ref "AB05") (pin "BR1") (pinfunction "BR1_BR1") (pintype "input"))
      (node (ref "B35") (pin "L1") (pinfunction "P$2_L1") (pintype "bidirectional"))
      (node (ref "C16") (pin "H2") (pinfunction "IN_H2") (pintype "input"))
    )
    (net (code "202") (name "MEM05") (class "Default")
      (node (ref "A16") (pin "R2") (pinfunction "2A_R2") (pintype "input"))
      (node (ref "A20") (pin "U2") (pinfunction "U2_U2") (pintype "open_collector"))
      (node (ref "AB05") (pin "BV2") (pinfunction "BV2_BV2") (pintype "input"))
      (node (ref "B35") (pin "M1") (pinfunction "P$2_M1") (pintype "bidirectional"))
      (node (ref "C16") (pin "J1") (pinfunction "IN_J1") (pintype "input"))
    )
    (net (code "203") (name "MEM06") (class "Default")
      (node (ref "A16") (pin "S2") (pinfunction "4A_S2") (pintype "input"))
      (node (ref "AB04") (pin "BR1") (pinfunction "BR1_BR1") (pintype "input"))
      (node (ref "B18") (pin "A1") (pinfunction "A1_A1") (pintype "open_collector"))
      (node (ref "B35") (pin "P1") (pinfunction "P$2_P1") (pintype "bidirectional"))
      (node (ref "C16") (pin "K2") (pinfunction "IN_K2") (pintype "input"))
    )
    (net (code "204") (name "MEM07") (class "Default")
      (node (ref "A16") (pin "T2") (pinfunction "8A_T2") (pintype "input"))
      (node (ref "AB04") (pin "BV2") (pinfunction "BV2_BV2") (pintype "input"))
      (node (ref "B18") (pin "U2") (pinfunction "U2_U2") (pintype "open_collector"))
      (node (ref "B35") (pin "S1") (pinfunction "P$2_S1") (pintype "bidirectional"))
      (node (ref "C16") (pin "L1") (pinfunction "IN_L1") (pintype "input"))
    )
    (net (code "205") (name "MEM08") (class "Default")
      (node (ref "A15") (pin "P2") (pinfunction "1A_P2") (pintype "input"))
      (node (ref "AB03") (pin "BR1") (pinfunction "BR1_BR1") (pintype "input"))
      (node (ref "B19") (pin "A1") (pinfunction "A1_A1") (pintype "open_collector"))
      (node (ref "B35") (pin "D2") (pinfunction "P$2_D2") (pintype "bidirectional"))
      (node (ref "C16") (pin "M2") (pinfunction "IN_M2") (pintype "input"))
    )
    (net (code "206") (name "MEM09") (class "Default")
      (node (ref "A15") (pin "R2") (pinfunction "2A_R2") (pintype "input"))
      (node (ref "AB03") (pin "BV2") (pinfunction "BV2_BV2") (pintype "input"))
      (node (ref "B19") (pin "U2") (pinfunction "U2_U2") (pintype "open_collector"))
      (node (ref "B35") (pin "E2") (pinfunction "P$2_E2") (pintype "bidirectional"))
      (node (ref "C16") (pin "N1") (pinfunction "IN_N1") (pintype "input"))
    )
    (net (code "207") (name "MEM10") (class "Default")
      (node (ref "A15") (pin "S2") (pinfunction "4A_S2") (pintype "input"))
      (node (ref "AB02") (pin "BR1") (pinfunction "BR1_BR1") (pintype "input"))
      (node (ref "B20") (pin "A1") (pinfunction "A1_A1") (pintype "open_collector"))
      (node (ref "B35") (pin "H2") (pinfunction "P$2_H2") (pintype "bidirectional"))
      (node (ref "C16") (pin "P2") (pinfunction "IN_P2") (pintype "input"))
    )
    (net (code "208") (name "MEM11") (class "Default")
      (node (ref "A15") (pin "T2") (pinfunction "8A_T2") (pintype "input"))
      (node (ref "AB02") (pin "BV2") (pinfunction "BV2_BV2") (pintype "input"))
      (node (ref "B20") (pin "U2") (pinfunction "U2_U2") (pintype "open_collector"))
      (node (ref "B35") (pin "K2") (pinfunction "P$2_K2") (pintype "bidirectional"))
      (node (ref "C16") (pin "R1") (pinfunction "IN_R1") (pintype "input"))
    )
    (net (code "209") (name "MEMORY_INCREMENT") (class "Default")
      (node (ref "A12") (pin "R2") (pinfunction "IN4C_R2") (pintype "input"))
      (node (ref "A33") (pin "V2") (pinfunction "OUT_V2") (pintype "output"))
      (node (ref "D11") (pin "J2") (pinfunction "IN2_J2") (pintype "input"))
    )
    (net (code "210") (name "MEM_ENABLE(0-4)") (class "Default")
      (node (ref "A08") (pin "P2") (pinfunction "OUT_P2") (pintype "open_collector"))
      (node (ref "A12") (pin "B1") (pinfunction "IN1B_B1") (pintype "input"))
      (node (ref "AB05") (pin "BU2") (pinfunction "BU2_BU2") (pintype "input"))
      (node (ref "AB06") (pin "BU2") (pinfunction "BU2_BU2") (pintype "input"))
      (node (ref "AB06") (pin "BV1") (pinfunction "BV1_BV1") (pintype "input"))
      (node (ref "AB07") (pin "BU2") (pinfunction "BU2_BU2") (pintype "input"))
      (node (ref "AB07") (pin "BV1") (pinfunction "BV1_BV1") (pintype "input"))
      (node (ref "B12") (pin "D1") (pinfunction "IN_D1") (pintype "input"))
    )
    (net (code "211") (name "MEM_ENABLE(5-11)") (class "Default")
      (node (ref "A09") (pin "P2") (pinfunction "OUT_P2") (pintype "open_collector"))
      (node (ref "AB02") (pin "BU2") (pinfunction "BU2_BU2") (pintype "input"))
      (node (ref "AB02") (pin "BV1") (pinfunction "BV1_BV1") (pintype "input"))
      (node (ref "AB03") (pin "BU2") (pinfunction "BU2_BU2") (pintype "input"))
      (node (ref "AB03") (pin "BV1") (pinfunction "BV1_BV1") (pintype "input"))
      (node (ref "AB04") (pin "BU2") (pinfunction "BU2_BU2") (pintype "input"))
      (node (ref "AB04") (pin "BV1") (pinfunction "BV1_BV1") (pintype "input"))
      (node (ref "AB05") (pin "BV1") (pinfunction "BV1_BV1") (pintype "input"))
      (node (ref "C12") (pin "E1") (pinfunction "IN1_E1") (pintype "input"))
    )
    (net (code "212") (name "MEM_IDLE") (class "Default")
      (node (ref "C04") (pin "H2") (pinfunction "1_H2") (pintype "output"))
      (node (ref "D04") (pin "A1") (pinfunction "IN1_A1") (pintype "input"))
    )
    (net (code "213") (name "MEM_P") (class "Default")
      (node (ref "A16") (pin "J1") (pinfunction "8A_J1") (pintype "input"))
      (node (ref "A17") (pin "A1") (pinfunction "A1_A1") (pintype "open_collector"))
      (node (ref "B35") (pin "B1") (pinfunction "P$2_B1") (pintype "bidirectional"))
      (node (ref "C16") (pin "A1") (pinfunction "IN_A1") (pintype "input"))
    )
    (net (code "214") (name "MEM_PARITY_EVEN") (class "Default")
      (node (ref "A14") (pin "P1") (pinfunction "IN1_P1") (pintype "input"))
      (node (ref "A14") (pin "R1") (pinfunction "IN2_R1") (pintype "input"))
      (node (ref "A16") (pin "L1") (pinfunction "EVEN_L1") (pintype "output"))
    )
    (net (code "215") (name "MEM_RET") (class "Default")
      (node (ref "A25") (pin "B2") (pinfunction "P$1_B2") (pintype "passive"))
      (node (ref "A26") (pin "B2") (pinfunction "P$1_B2") (pintype "passive"))
      (node (ref "B25") (pin "B2") (pinfunction "P$1_B2") (pintype "passive"))
      (node (ref "B26") (pin "B2") (pinfunction "P$1_B2") (pintype "passive"))
      (node (ref "B28") (pin "L2") (pinfunction "P$2_L2") (pintype "bidirectional"))
    )
    (net (code "216") (name "MEM_START") (class "Default")
      (node (ref "B34") (pin "P2") (pinfunction "P$2_P2") (pintype "bidirectional"))
      (node (ref "C02") (pin "N2") (pinfunction "OUT_N2") (pintype "output"))
      (node (ref "C13") (pin "U2") (pinfunction "IN4_U2") (pintype "input"))
      (node (ref "D16") (pin "B1") (pinfunction "C_B1") (pintype "input"))
    )
    (net (code "217") (name "MEM_SUPPLY+") (class "Default")
      (node (ref "A23") (pin "K1") (pinfunction "K1_K1") (pintype "passive"))
      (node (ref "A23") (pin "L2") (pinfunction "L2_L2") (pintype "passive"))
      (node (ref "A23") (pin "S1") (pinfunction "S1_S1") (pintype "passive"))
      (node (ref "A23") (pin "U2") (pinfunction "U2_U2") (pintype "passive"))
      (node (ref "A24") (pin "L2") (pinfunction "L2_L2") (pintype "passive"))
      (node (ref "A25") (pin "J2") (pinfunction "P$3_J2") (pintype "passive"))
      (node (ref "A25") (pin "U2") (pinfunction "P$2_U2") (pintype "passive"))
      (node (ref "A26") (pin "E2") (pinfunction "P$2_E2") (pintype "passive"))
      (node (ref "A26") (pin "J2") (pinfunction "P$3_J2") (pintype "passive"))
      (node (ref "A26") (pin "U2") (pinfunction "P$2_U2") (pintype "passive"))
      (node (ref "B23") (pin "K1") (pinfunction "K1_K1") (pintype "passive"))
      (node (ref "B23") (pin "L2") (pinfunction "L2_L2") (pintype "passive"))
      (node (ref "B23") (pin "S1") (pinfunction "S1_S1") (pintype "passive"))
      (node (ref "B23") (pin "U2") (pinfunction "U2_U2") (pintype "passive"))
      (node (ref "B24") (pin "K1") (pinfunction "K1_K1") (pintype "passive"))
      (node (ref "B24") (pin "L2") (pinfunction "L2_L2") (pintype "passive"))
      (node (ref "B24") (pin "S1") (pinfunction "S1_S1") (pintype "passive"))
      (node (ref "B24") (pin "U2") (pinfunction "U2_U2") (pintype "passive"))
      (node (ref "B25") (pin "E2") (pinfunction "P$2_E2") (pintype "passive"))
      (node (ref "B26") (pin "H2") (pinfunction "P$1_H2") (pintype "passive"))
      (node (ref "B27") (pin "M2") (pinfunction "P$2_M2") (pintype "bidirectional"))
      (node (ref "B28") (pin "M2") (pinfunction "P$2_M2") (pintype "bidirectional"))
      (node (ref "B28") (pin "N2") (pinfunction "P$2_N2") (pintype "bidirectional"))
      (node (ref "B28") (pin "P2") (pinfunction "P$2_P2") (pintype "bidirectional"))
      (node (ref "B28") (pin "R2") (pinfunction "P$2_R2") (pintype "bidirectional"))
    )
    (net (code "218") (name "MEM_SUPPLY-") (class "Default")
      (node (ref "A23") (pin "V2") (pinfunction "V2_V2") (pintype "input"))
      (node (ref "A24") (pin "V2") (pinfunction "V2_V2") (pintype "input"))
      (node (ref "A25") (pin "H2") (pinfunction "P$1_H2") (pintype "passive"))
      (node (ref "A26") (pin "H2") (pinfunction "P$1_H2") (pintype "passive"))
      (node (ref "A26") (pin "M2") (pinfunction "P$1_M2") (pintype "passive"))
      (node (ref "B23") (pin "V2") (pinfunction "V2_V2") (pintype "input"))
      (node (ref "B24") (pin "V2") (pinfunction "V2_V2") (pintype "input"))
      (node (ref "B25") (pin "H2") (pinfunction "P$1_H2") (pintype "passive"))
      (node (ref "B25") (pin "J2") (pinfunction "P$3_J2") (pintype "passive"))
      (node (ref "B25") (pin "U2") (pinfunction "P$2_U2") (pintype "passive"))
      (node (ref "B26") (pin "J2") (pinfunction "P$3_J2") (pintype "passive"))
      (node (ref "B26") (pin "U2") (pinfunction "P$2_U2") (pintype "passive"))
      (node (ref "B27") (pin "V2") (pinfunction "P$2_V2") (pintype "bidirectional"))
      (node (ref "B28") (pin "S2") (pinfunction "P$2_S2") (pintype "bidirectional"))
      (node (ref "B28") (pin "T2") (pinfunction "P$2_T2") (pintype "bidirectional"))
      (node (ref "B28") (pin "U2") (pinfunction "P$2_U2") (pintype "bidirectional"))
      (node (ref "B28") (pin "V2") (pinfunction "P$2_V2") (pintype "bidirectional"))
      (node (ref "D33") (pin "V2") (pinfunction "P$2_V2") (pintype "bidirectional"))
    )
    (net (code "219") (name "MFTP0") (class "Default")
      (node (ref "B08") (pin "B1") (pinfunction "IN2_B1") (pintype "input"))
      (node (ref "B08") (pin "C1") (pinfunction "IN3_C1") (pintype "input"))
      (node (ref "B08") (pin "D1") (pinfunction "IN4_D1") (pintype "input"))
      (node (ref "C02") (pin "T2") (pinfunction "IN1_T2") (pintype "input"))
      (node (ref "C15") (pin "U2") (pinfunction "IN2_U2") (pintype "input"))
      (node (ref "CD03") (pin "AT2") (pinfunction "CT2_AT2") (pintype "output"))
    )
    (net (code "220") (name "MFTP1") (class "Default")
      (node (ref "C05") (pin "P2") (pinfunction "IN1_P2") (pintype "input"))
      (node (ref "CD03") (pin "AE2") (pinfunction "CE2_AE2") (pintype "output"))
      (node (ref "D17") (pin "K2") (pinfunction "IN1_K2") (pintype "input"))
      (node (ref "D17") (pin "L2") (pinfunction "IN2_L2") (pintype "input"))
    )
    (net (code "221") (name "MFTP2") (class "Default")
      (node (ref "A13") (pin "K1") (pinfunction "IN4A_K1") (pintype "input"))
      (node (ref "C02") (pin "L1") (pinfunction "IN1_L1") (pintype "input"))
      (node (ref "C02") (pin "P2") (pinfunction "IN1_P2") (pintype "input"))
      (node (ref "CD03") (pin "BD2") (pinfunction "DD2_BD2") (pintype "output"))
      (node (ref "D12") (pin "A1") (pinfunction "IN1_A1") (pintype "input"))
    )
    (net (code "222") (name "MFTS0") (class "Default")
      (node (ref "CD03") (pin "AM2") (pinfunction "CM2_AM2") (pintype "output"))
      (node (ref "D04") (pin "E1") (pinfunction "IN1_E1") (pintype "input"))
      (node (ref "D09") (pin "J1") (pinfunction "IN3B_J1") (pintype "input"))
    )
    (net (code "223") (name "MFTS1") (class "Default")
      (node (ref "C12") (pin "L1") (pinfunction "IN2_L1") (pintype "input"))
      (node (ref "CD03") (pin "AJ2") (pinfunction "CJ2_AJ2") (pintype "output"))
    )
    (net (code "224") (name "MFTS2") (class "Default")
      (node (ref "A12") (pin "J2") (pinfunction "IN2A_J2") (pintype "input"))
      (node (ref "A12") (pin "V1") (pinfunction "IN2A_V1") (pintype "input"))
      (node (ref "B10") (pin "L2") (pinfunction "IN3A_L2") (pintype "input"))
      (node (ref "CD03") (pin "AF2") (pinfunction "CF2_AF2") (pintype "output"))
    )
    (net (code "225") (name "MFTS3") (class "Default")
      (node (ref "A10") (pin "N2") (pinfunction "IN4A_N2") (pintype "input"))
      (node (ref "C12") (pin "S1") (pinfunction "IN3_S1") (pintype "input"))
      (node (ref "D02") (pin "K1") (pinfunction "OUT_K1") (pintype "output"))
    )
    (net (code "226") (name "NEG_CLAMP") (class "Default")
      (node (ref "A26") (pin "R2") (pinfunction "P$2_R2") (pintype "passive"))
      (node (ref "C18") (pin "V2") (pinfunction "V2_V2") (pintype "input"))
      (node (ref "C19") (pin "V2") (pinfunction "V2_V2") (pintype "input"))
      (node (ref "C23") (pin "V2") (pinfunction "V2_V2") (pintype "input"))
      (node (ref "C24") (pin "V2") (pinfunction "V2_V2") (pintype "input"))
      (node (ref "C25") (pin "V2") (pinfunction "V2_V2") (pintype "input"))
      (node (ref "D18") (pin "V2") (pinfunction "V2_V2") (pintype "input"))
      (node (ref "D19") (pin "V2") (pinfunction "V2_V2") (pintype "input"))
      (node (ref "D23") (pin "V2") (pinfunction "V2_V2") (pintype "input"))
      (node (ref "D24") (pin "V2") (pinfunction "V2_V2") (pintype "input"))
      (node (ref "D25") (pin "V2") (pinfunction "V2_V2") (pintype "input"))
    )
    (net (code "227") (name "NO_SHIFT") (class "Default")
      (node (ref "A09") (pin "E1") (pinfunction "OUT_E1") (pintype "open_collector"))
      (node (ref "AB02") (pin "AE1") (pinfunction "AE1_AE1") (pintype "input"))
      (node (ref "AB03") (pin "AE1") (pinfunction "AE1_AE1") (pintype "input"))
      (node (ref "AB04") (pin "AE1") (pinfunction "AE1_AE1") (pintype "input"))
      (node (ref "AB05") (pin "AE1") (pinfunction "AE1_AE1") (pintype "input"))
      (node (ref "AB06") (pin "AE1") (pinfunction "AE1_AE1") (pintype "input"))
      (node (ref "AB07") (pin "AE1") (pinfunction "AE1_AE1") (pintype "input"))
      (node (ref "B10") (pin "J1") (pinfunction "IN3B_J1") (pintype "input"))
    )
    (net (code "228") (name "Net-(A01AI-P$2)") (class "Default")
      (node (ref "A01") (pin "V1") (pinfunction "P$2_V1") (pintype "bidirectional"))
      (node (ref "A28") (pin "N2") (pinfunction "P$2_N2") (pintype "bidirectional"))
    )
    (net (code "229") (name "Net-(A01C-P$2)") (class "Default")
      (node (ref "A01") (pin "B1") (pinfunction "P$2_B1") (pintype "bidirectional"))
      (node (ref "B36") (pin "S1") (pinfunction "P$2_S1") (pintype "bidirectional"))
    )
    (net (code "230") (name "Net-(A01D-P$2)") (class "Default")
      (node (ref "A01") (pin "B2") (pinfunction "P$2_B2") (pintype "bidirectional"))
      (node (ref "A28") (pin "B2") (pinfunction "P$2_B2") (pintype "bidirectional"))
    )
    (net (code "231") (name "Net-(A01E-P$2)") (class "Default")
      (node (ref "A01") (pin "C1") (pinfunction "P$2_C1") (pintype "bidirectional"))
      (node (ref "B36") (pin "P1") (pinfunction "P$2_P1") (pintype "bidirectional"))
    )
    (net (code "232") (name "Net-(A08A-IN1)") (class "Default")
      (node (ref "A08") (pin "A1") (pinfunction "IN1_A1") (pintype "input"))
      (node (ref "A08") (pin "D1") (pinfunction "IN4_D1") (pintype "input"))
      (node (ref "C12") (pin "U1") (pinfunction "OUT_U1") (pintype "output"))
    )
    (net (code "233") (name "Net-(A08A-IN2)") (class "Default")
      (node (ref "A08") (pin "B1") (pinfunction "IN2_B1") (pintype "input"))
      (node (ref "C12") (pin "H2") (pinfunction "OUT_H2") (pintype "output"))
    )
    (net (code "234") (name "Net-(A08A-IN3)") (class "Default")
      (node (ref "A08") (pin "C1") (pinfunction "IN3_C1") (pintype "input"))
      (node (ref "B13") (pin "F2") (pinfunction "OUT_F2") (pintype "output"))
    )
    (net (code "235") (name "Net-(A08D-IN1)") (class "Default")
      (node (ref "A08") (pin "D2") (pinfunction "IN1_D2") (pintype "input"))
      (node (ref "C12") (pin "J1") (pinfunction "OUT_J1") (pintype "output"))
    )
    (net (code "236") (name "Net-(A08D-IN2)") (class "Default")
      (node (ref "A08") (pin "E2") (pinfunction "IN2_E2") (pintype "input"))
      (node (ref "A08") (pin "F2") (pinfunction "IN3_F2") (pintype "input"))
      (node (ref "A08") (pin "H2") (pinfunction "IN4_H2") (pintype "input"))
      (node (ref "A09") (pin "D2") (pinfunction "IN1_D2") (pintype "input"))
      (node (ref "A09") (pin "E2") (pinfunction "IN2_E2") (pintype "input"))
      (node (ref "A09") (pin "F2") (pinfunction "IN3_F2") (pintype "input"))
      (node (ref "A09") (pin "H2") (pinfunction "IN4_H2") (pintype "input"))
      (node (ref "B10") (pin "T2") (pinfunction "OUT_T2") (pintype "output"))
    )
    (net (code "237") (name "Net-(A08E-IN1)") (class "Default")
      (node (ref "A08") (pin "F1") (pinfunction "IN1_F1") (pintype "input"))
      (node (ref "A08") (pin "H1") (pinfunction "IN2_H1") (pintype "input"))
      (node (ref "A08") (pin "J1") (pinfunction "IN3_J1") (pintype "input"))
      (node (ref "A08") (pin "K1") (pinfunction "IN4_K1") (pintype "input"))
      (node (ref "B13") (pin "K2") (pinfunction "OUT_K2") (pintype "output"))
    )
    (net (code "238") (name "Net-(A08F-IN2)") (class "Default")
      (node (ref "A08") (pin "L2") (pinfunction "IN2_L2") (pintype "input"))
      (node (ref "A08") (pin "M2") (pinfunction "IN3_M2") (pintype "input"))
      (node (ref "A10") (pin "R1") (pinfunction "OUT_R1") (pintype "output"))
    )
    (net (code "239") (name "Net-(A08J-IN1)") (class "Default")
      (node (ref "A08") (pin "R2") (pinfunction "IN1_R2") (pintype "input"))
      (node (ref "C12") (pin "N1") (pinfunction "OUT_N1") (pintype "output"))
    )
    (net (code "240") (name "Net-(A09A-IN1)") (class "Default")
      (node (ref "A09") (pin "A1") (pinfunction "IN1_A1") (pintype "input"))
      (node (ref "A09") (pin "B1") (pinfunction "IN2_B1") (pintype "input"))
      (node (ref "A11") (pin "N1") (pinfunction "OUT_N1") (pintype "output"))
    )
    (net (code "241") (name "Net-(A09E-IN2)") (class "Default")
      (node (ref "A09") (pin "H1") (pinfunction "IN2_H1") (pintype "input"))
      (node (ref "A09") (pin "J1") (pinfunction "IN3_J1") (pintype "input"))
      (node (ref "D09") (pin "T2") (pinfunction "OUT_T2") (pintype "output"))
    )
    (net (code "242") (name "Net-(A09F-IN3)") (class "Default")
      (node (ref "A09") (pin "M2") (pinfunction "IN3_M2") (pintype "input"))
      (node (ref "B12") (pin "E1") (pinfunction "OUT_E1") (pintype "output"))
      (node (ref "C12") (pin "F1") (pinfunction "IN2_F1") (pintype "input"))
    )
    (net (code "243") (name "Net-(A09F-IN4)") (class "Default")
      (node (ref "A09") (pin "N2") (pinfunction "IN4_N2") (pintype "input"))
      (node (ref "C13") (pin "L1") (pinfunction "OUT_L1") (pintype "output"))
    )
    (net (code "244") (name "Net-(A09G-IN1)") (class "Default")
      (node (ref "A09") (pin "M1") (pinfunction "IN1_M1") (pintype "input"))
      (node (ref "A09") (pin "N1") (pinfunction "IN2_N1") (pintype "input"))
      (node (ref "A09") (pin "P1") (pinfunction "IN3_P1") (pintype "input"))
      (node (ref "A09") (pin "R1") (pinfunction "IN4_R1") (pintype "input"))
      (node (ref "C11") (pin "P2") (pinfunction "OUT_P2") (pintype "output"))
    )
    (net (code "245") (name "Net-(A09J-IN1)") (class "Default")
      (node (ref "A09") (pin "R2") (pinfunction "IN1_R2") (pintype "input"))
      (node (ref "A09") (pin "S2") (pinfunction "IN2_S2") (pintype "input"))
      (node (ref "A09") (pin "T2") (pinfunction "IN3_T2") (pintype "input"))
      (node (ref "A09") (pin "U2") (pinfunction "IN4_U2") (pintype "input"))
      (node (ref "D11") (pin "N1") (pinfunction "OUT_N1") (pintype "output"))
    )
    (net (code "246") (name "Net-(A10E-OUT)") (class "Default")
      (node (ref "A10") (pin "V2") (pinfunction "OUT_V2") (pintype "output"))
      (node (ref "B10") (pin "S1") (pinfunction "IN1A_S1") (pintype "input"))
      (node (ref "B12") (pin "A1") (pinfunction "IN_A1") (pintype "input"))
    )
    (net (code "247") (name "Net-(A11A-OUT)") (class "Default")
      (node (ref "A11") (pin "D1") (pinfunction "OUT_D1") (pintype "output"))
      (node (ref "B09") (pin "R2") (pinfunction "IN1_R2") (pintype "input"))
      (node (ref "B09") (pin "S2") (pinfunction "IN2_S2") (pintype "input"))
      (node (ref "B09") (pin "T2") (pinfunction "IN3_T2") (pintype "input"))
      (node (ref "B09") (pin "U2") (pinfunction "IN4_U2") (pintype "input"))
    )
    (net (code "248") (name "Net-(A11D-OUT)") (class "Default")
      (node (ref "A11") (pin "H2") (pinfunction "OUT_H2") (pintype "output"))
      (node (ref "B09") (pin "D2") (pinfunction "IN1_D2") (pintype "input"))
      (node (ref "B09") (pin "E2") (pinfunction "IN2_E2") (pintype "input"))
      (node (ref "B09") (pin "F2") (pinfunction "IN3_F2") (pintype "input"))
      (node (ref "B09") (pin "H2") (pinfunction "IN4_H2") (pintype "input"))
    )
    (net (code "249") (name "Net-(A11E-OUT)") (class "Default")
      (node (ref "A11") (pin "J1") (pinfunction "OUT_J1") (pintype "output"))
      (node (ref "B09") (pin "M1") (pinfunction "IN1_M1") (pintype "input"))
      (node (ref "B09") (pin "N1") (pinfunction "IN2_N1") (pintype "input"))
      (node (ref "B09") (pin "P1") (pinfunction "IN3_P1") (pintype "input"))
      (node (ref "B09") (pin "R1") (pinfunction "IN4_R1") (pintype "input"))
    )
    (net (code "250") (name "Net-(A11F-OUT)") (class "Default")
      (node (ref "A11") (pin "M2") (pinfunction "OUT_M2") (pintype "output"))
      (node (ref "B09") (pin "K2") (pinfunction "IN1_K2") (pintype "input"))
      (node (ref "B09") (pin "L2") (pinfunction "IN2_L2") (pintype "input"))
      (node (ref "B09") (pin "M2") (pinfunction "IN3_M2") (pintype "input"))
      (node (ref "B09") (pin "N2") (pinfunction "IN4_N2") (pintype "input"))
    )
    (net (code "251") (name "Net-(A11H-IN1)") (class "Default")
      (node (ref "A11") (pin "N2") (pinfunction "IN1_N2") (pintype "input"))
      (node (ref "A12") (pin "R1") (pinfunction "OUT_R1") (pintype "output"))
    )
    (net (code "252") (name "Net-(A11H-OUT)") (class "Default")
      (node (ref "A11") (pin "S2") (pinfunction "OUT_S2") (pintype "output"))
      (node (ref "B13") (pin "L2") (pinfunction "IN1_L2") (pintype "input"))
    )
    (net (code "253") (name "Net-(A11J-IN2)") (class "Default")
      (node (ref "A11") (pin "U2") (pinfunction "IN2_U2") (pintype "input"))
      (node (ref "C14") (pin "F2") (pinfunction "OUT_F2") (pintype "output"))
    )
    (net (code "254") (name "Net-(A11J-IN3)") (class "Default")
      (node (ref "A11") (pin "V2") (pinfunction "IN3_V2") (pintype "input"))
      (node (ref "C12") (pin "V1") (pinfunction "OUT_V1") (pintype "output"))
    )
    (net (code "255") (name "Net-(A11J-OUT)") (class "Default")
      (node (ref "A11") (pin "V1") (pinfunction "OUT_V1") (pintype "output"))
      (node (ref "B11") (pin "N1") (pinfunction "C_N1") (pintype "input"))
    )
    (net (code "256") (name "Net-(A12C-IN1A)") (class "Default")
      (node (ref "A12") (pin "A1") (pinfunction "IN1A_A1") (pintype "input"))
      (node (ref "B12") (pin "M1") (pinfunction "OUT_M1") (pintype "output"))
    )
    (net (code "257") (name "Net-(A12C-IN4A)") (class "Default")
      (node (ref "A12") (pin "K1") (pinfunction "IN4A_K1") (pintype "input"))
      (node (ref "A14") (pin "V1") (pinfunction "OUT_V1") (pintype "output"))
    )
    (net (code "258") (name "Net-(A12E-IN1A)") (class "Default")
      (node (ref "A12") (pin "S1") (pinfunction "IN1A_S1") (pintype "input"))
      (node (ref "A13") (pin "V2") (pinfunction "OUT_V2") (pintype "output"))
    )
    (net (code "259") (name "Net-(A13C-IN3B)") (class "Default")
      (node (ref "A13") (pin "J1") (pinfunction "IN3B_J1") (pintype "input"))
      (node (ref "B12") (pin "P1") (pinfunction "OUT_P1") (pintype "output"))
    )
    (net (code "260") (name "Net-(A13C-OUT)") (class "Default")
      (node (ref "A13") (pin "R1") (pinfunction "OUT_R1") (pintype "output"))
      (node (ref "B08") (pin "D2") (pinfunction "IN1_D2") (pintype "input"))
      (node (ref "B08") (pin "E2") (pinfunction "IN2_E2") (pintype "input"))
      (node (ref "B08") (pin "F2") (pinfunction "IN3_F2") (pintype "input"))
    )
    (net (code "261") (name "Net-(A13D-IN3A)") (class "Default")
      (node (ref "A13") (pin "L2") (pinfunction "IN3A_L2") (pintype "input"))
      (node (ref "B12") (pin "T2") (pinfunction "OUT_T2") (pintype "output"))
    )
    (net (code "262") (name "Net-(A13D-IN4A)") (class "Default")
      (node (ref "A13") (pin "N2") (pinfunction "IN4A_N2") (pintype "input"))
      (node (ref "A13") (pin "S2") (pinfunction "IN4D_S2") (pintype "input"))
      (node (ref "B12") (pin "S2") (pinfunction "IN_S2") (pintype "input"))
      (node (ref "C14") (pin "K2") (pinfunction "OUT_K2") (pintype "output"))
    )
    (net (code "263") (name "Net-(A13D-OUT)") (class "Default")
      (node (ref "A13") (pin "T2") (pinfunction "OUT_T2") (pintype "output"))
      (node (ref "B11") (pin "P1") (pinfunction "D_P1") (pintype "input"))
    )
    (net (code "264") (name "Net-(A14A-IN1)") (class "Default")
      (node (ref "A14") (pin "A1") (pinfunction "IN1_A1") (pintype "input"))
      (node (ref "C14") (pin "N1") (pinfunction "OUT_N1") (pintype "output"))
    )
    (net (code "265") (name "Net-(A14A-IN2)") (class "Default")
      (node (ref "A14") (pin "B1") (pinfunction "IN2_B1") (pintype "input"))
      (node (ref "A14") (pin "J1") (pinfunction "OUT_J1") (pintype "output"))
    )
    (net (code "266") (name "Net-(A14A-IN3)") (class "Default")
      (node (ref "A14") (pin "C1") (pinfunction "IN3_C1") (pintype "input"))
      (node (ref "C14") (pin "N2") (pinfunction "OUT_N2") (pintype "output"))
    )
    (net (code "267") (name "Net-(A14A-OUT)") (class "Default")
      (node (ref "A14") (pin "D1") (pinfunction "OUT_D1") (pintype "output"))
      (node (ref "C14") (pin "H2") (pinfunction "IN1_H2") (pintype "input"))
    )
    (net (code "268") (name "Net-(A14D-OUT)") (class "Default")
      (node (ref "A14") (pin "H2") (pinfunction "OUT_H2") (pintype "output"))
      (node (ref "D13") (pin "L1") (pinfunction "IN_L1") (pintype "input"))
    )
    (net (code "269") (name "Net-(A14E-IN1)") (class "Default")
      (node (ref "A14") (pin "E1") (pinfunction "IN1_E1") (pintype "input"))
      (node (ref "B12") (pin "S1") (pinfunction "OUT_S1") (pintype "output"))
    )
    (net (code "270") (name "Net-(A14E-IN3)") (class "Default")
      (node (ref "A14") (pin "H1") (pinfunction "IN3_H1") (pintype "input"))
      (node (ref "B12") (pin "U1") (pinfunction "OUT_U1") (pintype "output"))
    )
    (net (code "271") (name "Net-(A14F-IN1)") (class "Default")
      (node (ref "A14") (pin "J2") (pinfunction "IN1_J2") (pintype "input"))
      (node (ref "A14") (pin "U1") (pinfunction "OUT_U1") (pintype "output"))
    )
    (net (code "272") (name "Net-(A14F-IN2)") (class "Default")
      (node (ref "A14") (pin "K2") (pinfunction "IN2_K2") (pintype "input"))
      (node (ref "A14") (pin "L2") (pinfunction "IN3_L2") (pintype "input"))
      (node (ref "A14") (pin "N1") (pinfunction "OUT_N1") (pintype "output"))
      (node (ref "C16") (pin "S2") (pinfunction "IN_S2") (pintype "input"))
    )
    (net (code "273") (name "Net-(A14F-OUT)") (class "Default")
      (node (ref "A14") (pin "K1") (pinfunction "IN1_K1") (pintype "input"))
      (node (ref "A14") (pin "L1") (pinfunction "IN2_L1") (pintype "input"))
      (node (ref "A14") (pin "M2") (pinfunction "OUT_M2") (pintype "output"))
    )
    (net (code "274") (name "Net-(A14H-OUT)") (class "Default")
      (node (ref "A14") (pin "S2") (pinfunction "OUT_S2") (pintype "output"))
      (node (ref "D13") (pin "V1") (pinfunction "IN_V1") (pintype "input"))
    )
    (net (code "275") (name "Net-(A15C-EVEN)") (class "Default")
      (node (ref "A15") (pin "L1") (pinfunction "EVEN_L1") (pintype "output"))
      (node (ref "A16") (pin "A1") (pinfunction "1B_A1") (pintype "input"))
    )
    (net (code "276") (name "Net-(A15C-ODD)") (class "Default")
      (node (ref "A15") (pin "K1") (pinfunction "ODD_K1") (pintype "output"))
      (node (ref "A16") (pin "E1") (pinfunction "1A_E1") (pintype "input"))
    )
    (net (code "277") (name "Net-(A15D-EVEN)") (class "Default")
      (node (ref "A15") (pin "V2") (pinfunction "EVEN_V2") (pintype "output"))
      (node (ref "A16") (pin "C1") (pinfunction "4B_C1") (pintype "input"))
    )
    (net (code "278") (name "Net-(A15D-ODD)") (class "Default")
      (node (ref "A15") (pin "U2") (pinfunction "ODD_U2") (pintype "output"))
      (node (ref "A16") (pin "H1") (pinfunction "4A_H1") (pintype "input"))
    )
    (net (code "279") (name "Net-(A16C-2A)") (class "Default")
      (node (ref "A16") (pin "F1") (pinfunction "2A_F1") (pintype "input"))
      (node (ref "A16") (pin "U2") (pinfunction "ODD_U2") (pintype "output"))
    )
    (net (code "280") (name "Net-(A16C-2B)") (class "Default")
      (node (ref "A16") (pin "B1") (pinfunction "2B_B1") (pintype "input"))
      (node (ref "A16") (pin "V2") (pinfunction "EVEN_V2") (pintype "output"))
    )
    (net (code "281") (name "Net-(A21C-P$2)") (class "Default")
      (node (ref "A18") (pin "D2") (pinfunction "D2_D2") (pintype "input"))
      (node (ref "A21") (pin "C2") (pinfunction "P$2_C2") (pintype "bidirectional"))
    )
    (net (code "282") (name "Net-(A21D-P$2)") (class "Default")
      (node (ref "A18") (pin "E2") (pinfunction "E2_E2") (pintype "input"))
      (node (ref "A21") (pin "D2") (pinfunction "P$2_D2") (pintype "bidirectional"))
    )
    (net (code "283") (name "Net-(A21E-P$2)") (class "Default")
      (node (ref "A18") (pin "L1") (pinfunction "L1_L1") (pintype "input"))
      (node (ref "A21") (pin "E2") (pinfunction "P$2_E2") (pintype "bidirectional"))
    )
    (net (code "284") (name "Net-(A21F-P$2)") (class "Default")
      (node (ref "A18") (pin "M1") (pinfunction "M1_M1") (pintype "input"))
      (node (ref "A21") (pin "F2") (pinfunction "P$2_F2") (pintype "bidirectional"))
    )
    (net (code "285") (name "Net-(A21G-P$2)") (class "Default")
      (node (ref "A19") (pin "D2") (pinfunction "D2_D2") (pintype "input"))
      (node (ref "A21") (pin "H2") (pinfunction "P$2_H2") (pintype "bidirectional"))
    )
    (net (code "286") (name "Net-(A21H-P$2)") (class "Default")
      (node (ref "A19") (pin "E2") (pinfunction "E2_E2") (pintype "input"))
      (node (ref "A21") (pin "J2") (pinfunction "P$2_J2") (pintype "bidirectional"))
    )
    (net (code "287") (name "Net-(A21I-P$2)") (class "Default")
      (node (ref "A19") (pin "L1") (pinfunction "L1_L1") (pintype "input"))
      (node (ref "A21") (pin "K2") (pinfunction "P$2_K2") (pintype "bidirectional"))
    )
    (net (code "288") (name "Net-(A21J-P$2)") (class "Default")
      (node (ref "A19") (pin "M1") (pinfunction "M1_M1") (pintype "input"))
      (node (ref "A21") (pin "L2") (pinfunction "P$2_L2") (pintype "bidirectional"))
    )
    (net (code "289") (name "Net-(A21K-P$2)") (class "Default")
      (node (ref "A20") (pin "D2") (pinfunction "D2_D2") (pintype "input"))
      (node (ref "A21") (pin "M2") (pinfunction "P$2_M2") (pintype "bidirectional"))
    )
    (net (code "290") (name "Net-(A21L-P$2)") (class "Default")
      (node (ref "A20") (pin "E2") (pinfunction "E2_E2") (pintype "input"))
      (node (ref "A21") (pin "N2") (pinfunction "P$2_N2") (pintype "bidirectional"))
    )
    (net (code "291") (name "Net-(A21M-P$2)") (class "Default")
      (node (ref "A20") (pin "L1") (pinfunction "L1_L1") (pintype "input"))
      (node (ref "A21") (pin "P2") (pinfunction "P$2_P2") (pintype "bidirectional"))
    )
    (net (code "292") (name "Net-(A21N-P$2)") (class "Default")
      (node (ref "A20") (pin "M1") (pinfunction "M1_M1") (pintype "input"))
      (node (ref "A21") (pin "R2") (pinfunction "P$2_R2") (pintype "bidirectional"))
    )
    (net (code "293") (name "Net-(A21O-P$2)") (class "Default")
      (node (ref "A17") (pin "D2") (pinfunction "D2_D2") (pintype "input"))
      (node (ref "A21") (pin "S2") (pinfunction "P$2_S2") (pintype "bidirectional"))
    )
    (net (code "294") (name "Net-(A21P-P$2)") (class "Default")
      (node (ref "A17") (pin "E2") (pinfunction "E2_E2") (pintype "input"))
      (node (ref "A21") (pin "T2") (pinfunction "P$2_T2") (pintype "bidirectional"))
    )
    (net (code "295") (name "Net-(A22C-P$2)") (class "Default")
      (node (ref "A22") (pin "C2") (pinfunction "P$2_C2") (pintype "bidirectional"))
      (node (ref "A23") (pin "J2") (pinfunction "J_J2") (pintype "passive"))
    )
    (net (code "296") (name "Net-(A22D-P$2)") (class "Default")
      (node (ref "A22") (pin "D2") (pinfunction "P$2_D2") (pintype "bidirectional"))
      (node (ref "A23") (pin "K2") (pinfunction "K_K2") (pintype "passive"))
    )
    (net (code "297") (name "Net-(A22E-P$2)") (class "Default")
      (node (ref "A22") (pin "E2") (pinfunction "P$2_E2") (pintype "bidirectional"))
      (node (ref "A23") (pin "H1") (pinfunction "J_H1") (pintype "passive"))
    )
    (net (code "298") (name "Net-(A22F-P$2)") (class "Default")
      (node (ref "A22") (pin "F2") (pinfunction "P$2_F2") (pintype "bidirectional"))
      (node (ref "A23") (pin "J1") (pinfunction "K_J1") (pintype "passive"))
    )
    (net (code "299") (name "Net-(A22G-P$2)") (class "Default")
      (node (ref "A22") (pin "H2") (pinfunction "P$2_H2") (pintype "bidirectional"))
      (node (ref "A23") (pin "S2") (pinfunction "J_S2") (pintype "passive"))
    )
    (net (code "300") (name "Net-(A22H-P$2)") (class "Default")
      (node (ref "A22") (pin "J2") (pinfunction "P$2_J2") (pintype "bidirectional"))
      (node (ref "A23") (pin "T2") (pinfunction "K_T2") (pintype "passive"))
    )
    (net (code "301") (name "Net-(A22I-P$2)") (class "Default")
      (node (ref "A22") (pin "K2") (pinfunction "P$2_K2") (pintype "bidirectional"))
      (node (ref "A23") (pin "P1") (pinfunction "J_P1") (pintype "passive"))
    )
    (net (code "302") (name "Net-(A22J-P$2)") (class "Default")
      (node (ref "A22") (pin "L2") (pinfunction "P$2_L2") (pintype "bidirectional"))
      (node (ref "A23") (pin "R1") (pinfunction "K_R1") (pintype "passive"))
    )
    (net (code "303") (name "Net-(A22K-P$2)") (class "Default")
      (node (ref "A22") (pin "M2") (pinfunction "P$2_M2") (pintype "bidirectional"))
      (node (ref "B23") (pin "J2") (pinfunction "J_J2") (pintype "passive"))
    )
    (net (code "304") (name "Net-(A22L-P$2)") (class "Default")
      (node (ref "A22") (pin "N2") (pinfunction "P$2_N2") (pintype "bidirectional"))
      (node (ref "B23") (pin "K2") (pinfunction "K_K2") (pintype "passive"))
    )
    (net (code "305") (name "Net-(A22M-P$2)") (class "Default")
      (node (ref "A22") (pin "P2") (pinfunction "P$2_P2") (pintype "bidirectional"))
      (node (ref "B23") (pin "H1") (pinfunction "J_H1") (pintype "passive"))
    )
    (net (code "306") (name "Net-(A22N-P$2)") (class "Default")
      (node (ref "A22") (pin "R2") (pinfunction "P$2_R2") (pintype "bidirectional"))
      (node (ref "B23") (pin "J1") (pinfunction "K_J1") (pintype "passive"))
    )
    (net (code "307") (name "Net-(A22O-P$2)") (class "Default")
      (node (ref "A22") (pin "S2") (pinfunction "P$2_S2") (pintype "bidirectional"))
      (node (ref "A24") (pin "J2") (pinfunction "J_J2") (pintype "passive"))
    )
    (net (code "308") (name "Net-(A22P-P$2)") (class "Default")
      (node (ref "A22") (pin "T2") (pinfunction "P$2_T2") (pintype "bidirectional"))
      (node (ref "A24") (pin "K2") (pinfunction "K_K2") (pintype "passive"))
    )
    (net (code "309") (name "Net-(A23B-H)") (class "Default")
      (node (ref "A23") (pin "F1") (pinfunction "H_F1") (pintype "input"))
      (node (ref "A25") (pin "R2") (pinfunction "P$2_R2") (pintype "passive"))
    )
    (net (code "310") (name "Net-(A23D-H)") (class "Default")
      (node (ref "A23") (pin "H2") (pinfunction "H_H2") (pintype "input"))
      (node (ref "A25") (pin "P2") (pinfunction "P$2_P2") (pintype "passive"))
    )
    (net (code "311") (name "Net-(A23E-H)") (class "Default")
      (node (ref "A23") (pin "N1") (pinfunction "H_N1") (pintype "input"))
      (node (ref "A25") (pin "T2") (pinfunction "P$2_T2") (pintype "passive"))
    )
    (net (code "312") (name "Net-(A23F-H)") (class "Default")
      (node (ref "A23") (pin "R2") (pinfunction "H_R2") (pintype "input"))
      (node (ref "A25") (pin "S2") (pinfunction "P$2_S2") (pintype "passive"))
    )
    (net (code "313") (name "Net-(A24D-H)") (class "Default")
      (node (ref "A24") (pin "H2") (pinfunction "H_H2") (pintype "input"))
      (node (ref "A26") (pin "P2") (pinfunction "P$2_P2") (pintype "passive"))
    )
    (net (code "314") (name "Net-(A25D-P$1)") (class "Default")
      (node (ref "A23") (pin "F2") (pinfunction "F2_F2") (pintype "passive"))
      (node (ref "A25") (pin "N2") (pinfunction "P$1_N2") (pintype "passive"))
    )
    (net (code "315") (name "Net-(A25E-P$1)") (class "Default")
      (node (ref "A23") (pin "E1") (pinfunction "E1_E1") (pintype "passive"))
      (node (ref "A25") (pin "M2") (pinfunction "P$1_M2") (pintype "passive"))
    )
    (net (code "316") (name "Net-(A25F-P$1)") (class "Default")
      (node (ref "A23") (pin "P2") (pinfunction "P2_P2") (pintype "passive"))
      (node (ref "A25") (pin "L2") (pinfunction "P$1_L2") (pintype "passive"))
    )
    (net (code "317") (name "Net-(A25G-P$1)") (class "Default")
      (node (ref "A23") (pin "M1") (pinfunction "M1_M1") (pintype "passive"))
      (node (ref "A25") (pin "K2") (pinfunction "P$1_K2") (pintype "passive"))
    )
    (net (code "318") (name "Net-(A25H-P$1)") (class "Default")
      (node (ref "A25") (pin "F2") (pinfunction "P$1_F2") (pintype "passive"))
      (node (ref "C25") (pin "U2") (pinfunction "U2_U2") (pintype "passive"))
      (node (ref "D25") (pin "U2") (pinfunction "U2_U2") (pintype "passive"))
    )
    (net (code "319") (name "Net-(A26D-P$1)") (class "Default")
      (node (ref "A24") (pin "F2") (pinfunction "F2_F2") (pintype "passive"))
      (node (ref "A26") (pin "N2") (pinfunction "P$1_N2") (pintype "passive"))
    )
    (net (code "320") (name "Net-(A26H-P$1)") (class "Default")
      (node (ref "A26") (pin "F2") (pinfunction "P$1_F2") (pintype "passive"))
      (node (ref "C25") (pin "L2") (pinfunction "L2_L2") (pintype "passive"))
      (node (ref "D25") (pin "L2") (pinfunction "L2_L2") (pintype "passive"))
    )
    (net (code "321") (name "Net-(A27P-P$2)") (class "Default")
      (node (ref "A27") (pin "T2") (pinfunction "P$2_T2") (pintype "bidirectional"))
      (node (ref "A28") (pin "U2") (pinfunction "P$2_U2") (pintype "bidirectional"))
      (node (ref "B36") (pin "V2") (pinfunction "P$2_V2") (pintype "bidirectional"))
    )
    (net (code "322") (name "Net-(A28AB-P$2)") (class "Default")
      (node (ref "A28") (pin "R2") (pinfunction "P$2_R2") (pintype "bidirectional"))
      (node (ref "C01") (pin "V1") (pinfunction "P$2_V1") (pintype "bidirectional"))
    )
    (net (code "323") (name "Net-(A28AD-P$2)") (class "Default")
      (node (ref "A28") (pin "S2") (pinfunction "P$2_S2") (pintype "bidirectional"))
      (node (ref "D01") (pin "V1") (pinfunction "P$2_V1") (pintype "bidirectional"))
    )
    (net (code "324") (name "Net-(A28I-P$2)") (class "Default")
      (node (ref "A28") (pin "E1") (pinfunction "P$2_E1") (pintype "bidirectional"))
      (node (ref "B36") (pin "T2") (pinfunction "P$2_T2") (pintype "bidirectional"))
    )
    (net (code "325") (name "Net-(A28Z-P$2)") (class "Default")
      (node (ref "A28") (pin "P2") (pinfunction "P$2_P2") (pintype "bidirectional"))
      (node (ref "B01") (pin "V1") (pinfunction "P$2_V1") (pintype "bidirectional"))
    )
    (net (code "326") (name "Net-(A32A-IN)") (class "Default")
      (node (ref "A32") (pin "A1") (pinfunction "IN_A1") (pintype "input"))
      (node (ref "D34") (pin "J1") (pinfunction "P$2_J1") (pintype "bidirectional"))
    )
    (net (code "327") (name "Net-(A32D-IN)") (class "Default")
      (node (ref "A32") (pin "D2") (pinfunction "IN_D2") (pintype "input"))
      (node (ref "D34") (pin "L1") (pinfunction "P$2_L1") (pintype "bidirectional"))
    )
    (net (code "328") (name "Net-(A32E-IN)") (class "Default")
      (node (ref "A32") (pin "F1") (pinfunction "IN_F1") (pintype "input"))
      (node (ref "D34") (pin "M1") (pinfunction "P$2_M1") (pintype "bidirectional"))
    )
    (net (code "329") (name "Net-(A32F-IN)") (class "Default")
      (node (ref "A32") (pin "K2") (pinfunction "IN_K2") (pintype "input"))
      (node (ref "D34") (pin "P1") (pinfunction "P$2_P1") (pintype "bidirectional"))
    )
    (net (code "330") (name "Net-(A32G-IN)") (class "Default")
      (node (ref "A32") (pin "M1") (pinfunction "IN_M1") (pintype "input"))
      (node (ref "D34") (pin "S1") (pinfunction "P$2_S1") (pintype "bidirectional"))
    )
    (net (code "331") (name "Net-(A32H-IN)") (class "Default")
      (node (ref "A32") (pin "R2") (pinfunction "IN_R2") (pintype "input"))
      (node (ref "D34") (pin "D2") (pinfunction "P$2_D2") (pintype "bidirectional"))
    )
    (net (code "332") (name "Net-(A33A-IN)") (class "Default")
      (node (ref "A33") (pin "A1") (pinfunction "IN_A1") (pintype "input"))
      (node (ref "D34") (pin "E2") (pinfunction "P$2_E2") (pintype "bidirectional"))
    )
    (net (code "333") (name "Net-(A33D-IN)") (class "Default")
      (node (ref "A33") (pin "D2") (pinfunction "IN_D2") (pintype "input"))
      (node (ref "D34") (pin "H2") (pinfunction "P$2_H2") (pintype "bidirectional"))
    )
    (net (code "334") (name "Net-(A33E-IN)") (class "Default")
      (node (ref "A33") (pin "F1") (pinfunction "IN_F1") (pintype "input"))
      (node (ref "D34") (pin "K2") (pinfunction "P$2_K2") (pintype "bidirectional"))
    )
    (net (code "335") (name "Net-(A33F-IN)") (class "Default")
      (node (ref "A33") (pin "K2") (pinfunction "IN_K2") (pintype "input"))
      (node (ref "D34") (pin "M2") (pinfunction "P$2_M2") (pintype "bidirectional"))
    )
    (net (code "336") (name "Net-(A33G-IN)") (class "Default")
      (node (ref "A33") (pin "M1") (pinfunction "IN_M1") (pintype "input"))
      (node (ref "D34") (pin "P2") (pinfunction "P$2_P2") (pintype "bidirectional"))
    )
    (net (code "337") (name "Net-(A33H-IN)") (class "Default")
      (node (ref "A33") (pin "R2") (pinfunction "IN_R2") (pintype "input"))
      (node (ref "C36") (pin "T2") (pinfunction "P$2_T2") (pintype "bidirectional"))
    )
    (net (code "338") (name "Net-(A33H-IN2)") (class "Default")
      (node (ref "A33") (pin "S2") (pinfunction "IN2_S2") (pintype "bidirectional"))
      (node (ref "A33") (pin "T2") (pinfunction "IN3_T2") (pintype "input"))
      (node (ref "A33") (pin "U2") (pinfunction "IN4_U2") (pintype "input"))
    )
    (net (code "339") (name "Net-(A34A-IN)") (class "Default")
      (node (ref "A34") (pin "A1") (pinfunction "IN_A1") (pintype "input"))
      (node (ref "B32") (pin "D2") (pinfunction "P$1_D2") (pintype "passive"))
      (node (ref "C36") (pin "D2") (pinfunction "P$2_D2") (pintype "bidirectional"))
    )
    (net (code "340") (name "Net-(A34B-IN)") (class "Default")
      (node (ref "A34") (pin "C1") (pinfunction "IN_C1") (pintype "input"))
      (node (ref "B32") (pin "E2") (pinfunction "P$1_E2") (pintype "passive"))
      (node (ref "C36") (pin "E2") (pinfunction "P$2_E2") (pintype "bidirectional"))
    )
    (net (code "341") (name "Net-(A34C-IN)") (class "Default")
      (node (ref "A34") (pin "D1") (pinfunction "IN_D1") (pintype "input"))
      (node (ref "B32") (pin "H2") (pinfunction "P$1_H2") (pintype "passive"))
      (node (ref "C36") (pin "H2") (pinfunction "P$2_H2") (pintype "bidirectional"))
    )
    (net (code "342") (name "Net-(A34D-IN)") (class "Default")
      (node (ref "A34") (pin "E2") (pinfunction "IN_E2") (pintype "input"))
      (node (ref "B33") (pin "M1") (pinfunction "P$1_M1") (pintype "passive"))
      (node (ref "C35") (pin "M1") (pinfunction "P$2_M1") (pintype "bidirectional"))
    )
    (net (code "343") (name "Net-(A34G-IN)") (class "Default")
      (node (ref "A34") (pin "F1") (pinfunction "IN_F1") (pintype "input"))
      (node (ref "B33") (pin "B1") (pinfunction "P$1_B1") (pintype "passive"))
      (node (ref "C35") (pin "B1") (pinfunction "P$2_B1") (pintype "bidirectional"))
    )
    (net (code "344") (name "Net-(A34H-IN)") (class "Default")
      (node (ref "A34") (pin "H2") (pinfunction "IN_H2") (pintype "input"))
      (node (ref "B33") (pin "P1") (pinfunction "P$1_P1") (pintype "passive"))
      (node (ref "C35") (pin "P1") (pinfunction "P$2_P1") (pintype "bidirectional"))
    )
    (net (code "345") (name "Net-(A34I-IN)") (class "Default")
      (node (ref "A34") (pin "J1") (pinfunction "IN_J1") (pintype "input"))
      (node (ref "B33") (pin "D1") (pinfunction "P$1_D1") (pintype "passive"))
      (node (ref "C35") (pin "D1") (pinfunction "P$2_D1") (pintype "bidirectional"))
    )
    (net (code "346") (name "Net-(A34J-IN)") (class "Default")
      (node (ref "A34") (pin "K2") (pinfunction "IN_K2") (pintype "input"))
      (node (ref "B33") (pin "S1") (pinfunction "P$1_S1") (pintype "passive"))
      (node (ref "C35") (pin "S1") (pinfunction "P$2_S1") (pintype "bidirectional"))
    )
    (net (code "347") (name "Net-(A34K-IN)") (class "Default")
      (node (ref "A34") (pin "L1") (pinfunction "IN_L1") (pintype "input"))
      (node (ref "B33") (pin "E1") (pinfunction "P$1_E1") (pintype "passive"))
      (node (ref "C35") (pin "E1") (pinfunction "P$2_E1") (pintype "bidirectional"))
    )
    (net (code "348") (name "Net-(A34L-IN)") (class "Default")
      (node (ref "A34") (pin "M2") (pinfunction "IN_M2") (pintype "input"))
      (node (ref "B33") (pin "D2") (pinfunction "P$1_D2") (pintype "passive"))
      (node (ref "C35") (pin "D2") (pinfunction "P$2_D2") (pintype "bidirectional"))
    )
    (net (code "349") (name "Net-(A34M-IN)") (class "Default")
      (node (ref "A34") (pin "N1") (pinfunction "IN_N1") (pintype "input"))
      (node (ref "B33") (pin "H1") (pinfunction "P$1_H1") (pintype "passive"))
      (node (ref "C35") (pin "H1") (pinfunction "P$2_H1") (pintype "bidirectional"))
    )
    (net (code "350") (name "Net-(A34N-IN)") (class "Default")
      (node (ref "A34") (pin "P2") (pinfunction "IN_P2") (pintype "input"))
      (node (ref "B33") (pin "E2") (pinfunction "P$1_E2") (pintype "passive"))
      (node (ref "C35") (pin "E2") (pinfunction "P$2_E2") (pintype "bidirectional"))
    )
    (net (code "351") (name "Net-(A34O-IN)") (class "Default")
      (node (ref "A34") (pin "R1") (pinfunction "IN_R1") (pintype "input"))
      (node (ref "B33") (pin "J1") (pinfunction "P$1_J1") (pintype "passive"))
      (node (ref "C35") (pin "J1") (pinfunction "P$2_J1") (pintype "bidirectional"))
    )
    (net (code "352") (name "Net-(A34P-IN)") (class "Default")
      (node (ref "A34") (pin "S2") (pinfunction "IN_S2") (pintype "input"))
      (node (ref "B33") (pin "H2") (pinfunction "P$1_H2") (pintype "passive"))
      (node (ref "C35") (pin "H2") (pinfunction "P$2_H2") (pintype "bidirectional"))
    )
    (net (code "353") (name "Net-(A34Q-IN)") (class "Default")
      (node (ref "A34") (pin "V1") (pinfunction "IN_V1") (pintype "input"))
      (node (ref "B33") (pin "L1") (pinfunction "P$1_L1") (pintype "passive"))
      (node (ref "C35") (pin "L1") (pinfunction "P$2_L1") (pintype "bidirectional"))
    )
    (net (code "354") (name "Net-(A34R-IN)") (class "Default")
      (node (ref "A34") (pin "U2") (pinfunction "IN_U2") (pintype "input"))
      (node (ref "B33") (pin "K2") (pinfunction "P$1_K2") (pintype "passive"))
      (node (ref "C35") (pin "K2") (pinfunction "P$2_K2") (pintype "bidirectional"))
    )
    (net (code "355") (name "Net-(A35A-IN)") (class "Default")
      (node (ref "A35") (pin "A1") (pinfunction "IN_A1") (pintype "input"))
      (node (ref "D12") (pin "V2") (pinfunction "OUT_V2") (pintype "output"))
    )
    (net (code "356") (name "Net-(A35A-OUT)") (class "Default")
      (node (ref "A35") (pin "B1") (pinfunction "OUT_B1") (pintype "output"))
      (node (ref "B36") (pin "D1") (pinfunction "P$2_D1") (pintype "bidirectional"))
    )
    (net (code "357") (name "Net-(A35B-OUT)") (class "Default")
      (node (ref "A35") (pin "D2") (pinfunction "OUT_D2") (pintype "output"))
      (node (ref "B36") (pin "E1") (pinfunction "P$2_E1") (pintype "bidirectional"))
    )
    (net (code "358") (name "Net-(A35C-OUT)") (class "Default")
      (node (ref "A35") (pin "E1") (pinfunction "OUT_E1") (pintype "output"))
      (node (ref "C28") (pin "C1") (pinfunction "IN3_C1") (pintype "input"))
    )
    (net (code "359") (name "Net-(A35D-OUT)") (class "Default")
      (node (ref "A35") (pin "F2") (pinfunction "OUT_F2") (pintype "output"))
      (node (ref "B34") (pin "M1") (pinfunction "P$2_M1") (pintype "bidirectional"))
    )
    (net (code "360") (name "Net-(A35H-OUT)") (class "Default")
      (node (ref "A35") (pin "J2") (pinfunction "OUT_J2") (pintype "output"))
      (node (ref "B34") (pin "P1") (pinfunction "P$2_P1") (pintype "bidirectional"))
    )
    (net (code "361") (name "Net-(A35I-OUT)") (class "Default")
      (node (ref "A35") (pin "K1") (pinfunction "OUT_K1") (pintype "output"))
      (node (ref "B34") (pin "D1") (pinfunction "P$2_D1") (pintype "bidirectional"))
    )
    (net (code "362") (name "Net-(A35J-OUT)") (class "Default")
      (node (ref "A35") (pin "L2") (pinfunction "OUT_L2") (pintype "output"))
      (node (ref "B34") (pin "S1") (pinfunction "P$2_S1") (pintype "bidirectional"))
    )
    (net (code "363") (name "Net-(A35K-OUT)") (class "Default")
      (node (ref "A35") (pin "M1") (pinfunction "OUT_M1") (pintype "output"))
      (node (ref "B34") (pin "E1") (pinfunction "P$2_E1") (pintype "bidirectional"))
    )
    (net (code "364") (name "Net-(A35L-OUT)") (class "Default")
      (node (ref "A35") (pin "N2") (pinfunction "OUT_N2") (pintype "output"))
      (node (ref "B34") (pin "D2") (pinfunction "P$2_D2") (pintype "bidirectional"))
    )
    (net (code "365") (name "Net-(A35M-OUT)") (class "Default")
      (node (ref "A35") (pin "P1") (pinfunction "OUT_P1") (pintype "output"))
      (node (ref "B34") (pin "H1") (pinfunction "P$2_H1") (pintype "bidirectional"))
    )
    (net (code "366") (name "Net-(A35N-OUT)") (class "Default")
      (node (ref "A35") (pin "R2") (pinfunction "OUT_R2") (pintype "output"))
      (node (ref "B34") (pin "E2") (pinfunction "P$2_E2") (pintype "bidirectional"))
    )
    (net (code "367") (name "Net-(A35O-OUT)") (class "Default")
      (node (ref "A35") (pin "S1") (pinfunction "OUT_S1") (pintype "output"))
      (node (ref "B34") (pin "J1") (pinfunction "P$2_J1") (pintype "bidirectional"))
    )
    (net (code "368") (name "Net-(A35P-OUT)") (class "Default")
      (node (ref "A35") (pin "T2") (pinfunction "OUT_T2") (pintype "output"))
      (node (ref "B34") (pin "H2") (pinfunction "P$2_H2") (pintype "bidirectional"))
    )
    (net (code "369") (name "Net-(A35Q-OUT)") (class "Default")
      (node (ref "A35") (pin "U1") (pinfunction "OUT_U1") (pintype "output"))
      (node (ref "B34") (pin "L1") (pinfunction "P$2_L1") (pintype "bidirectional"))
    )
    (net (code "370") (name "Net-(A35R-OUT)") (class "Default")
      (node (ref "A35") (pin "V2") (pinfunction "OUT_V2") (pintype "output"))
      (node (ref "B34") (pin "K2") (pinfunction "P$2_K2") (pintype "bidirectional"))
    )
    (net (code "371") (name "Net-(AB02-PadBK2)") (class "Default")
      (node (ref "AB02") (pin "BK2") (pinfunction "BK2_BK2") (pintype "output"))
      (node (ref "AB03") (pin "BJ1") (pinfunction "BJ1_BJ1") (pintype "input"))
    )
    (net (code "372") (name "Net-(AB03-PadBK2)") (class "Default")
      (node (ref "AB03") (pin "BK2") (pinfunction "BK2_BK2") (pintype "output"))
      (node (ref "AB04") (pin "BJ1") (pinfunction "BJ1_BJ1") (pintype "input"))
    )
    (net (code "373") (name "Net-(AB05-PadBK2)") (class "Default")
      (node (ref "AB05") (pin "BK2") (pinfunction "BK2_BK2") (pintype "output"))
      (node (ref "AB06") (pin "BJ1") (pinfunction "BJ1_BJ1") (pintype "input"))
    )
    (net (code "374") (name "Net-(AB06-PadBK2)") (class "Default")
      (node (ref "AB06") (pin "BK2") (pinfunction "BK2_BK2") (pintype "output"))
      (node (ref "AB07") (pin "BJ1") (pinfunction "BJ1_BJ1") (pintype "input"))
    )
    (net (code "375") (name "Net-(AB31-PadAU1)") (class "Default")
      (node (ref "AB31") (pin "AU1") (pinfunction "AU1_AU1") (pintype "input"))
      (node (ref "AB31") (pin "BV1") (pinfunction "BV1_BV1") (pintype "output"))
    )
    (net (code "376") (name "Net-(AB31A-P$1)") (class "Default")
      (node (ref "AB31") (pin "BU2") (pinfunction "P$1_BU2") (pintype "passive"))
      (node (ref "C34") (pin "U1") (pinfunction "P$2_U1") (pintype "bidirectional"))
    )
    (net (code "377") (name "Net-(B08G-IN1)") (class "Default")
      (node (ref "B08") (pin "M1") (pinfunction "IN1_M1") (pintype "input"))
      (node (ref "B08") (pin "N1") (pinfunction "IN2_N1") (pintype "input"))
      (node (ref "C05") (pin "S2") (pinfunction "OUT_S2") (pintype "output"))
    )
    (net (code "378") (name "Net-(B08G-IN3)") (class "Default")
      (node (ref "B08") (pin "P1") (pinfunction "IN3_P1") (pintype "input"))
      (node (ref "B08") (pin "R1") (pinfunction "IN4_R1") (pintype "input"))
      (node (ref "B12") (pin "V2") (pinfunction "OUT_V2") (pintype "output"))
    )
    (net (code "379") (name "Net-(B08J-IN1)") (class "Default")
      (node (ref "B08") (pin "R2") (pinfunction "IN1_R2") (pintype "input"))
      (node (ref "C12") (pin "M2") (pinfunction "OUT_M2") (pintype "output"))
    )
    (net (code "380") (name "Net-(B08J-IN2)") (class "Default")
      (node (ref "B08") (pin "S2") (pinfunction "IN2_S2") (pintype "input"))
      (node (ref "B13") (pin "N1") (pinfunction "OUT_N1") (pintype "output"))
    )
    (net (code "381") (name "Net-(B10C-OUT)") (class "Default")
      (node (ref "B10") (pin "R1") (pinfunction "OUT_R1") (pintype "output"))
      (node (ref "B11") (pin "M2") (pinfunction "D_M2") (pintype "input"))
    )
    (net (code "382") (name "Net-(B10E-IN2A)") (class "Default")
      (node (ref "B10") (pin "V1") (pinfunction "IN2A_V1") (pintype "input"))
      (node (ref "B12") (pin "B1") (pinfunction "OUT_B1") (pintype "output"))
    )
    (net (code "383") (name "Net-(B11A-C)") (class "Default")
      (node (ref "B11") (pin "B1") (pinfunction "C_B1") (pintype "input"))
      (node (ref "B12") (pin "L2") (pinfunction "OUT_L2") (pintype "output"))
    )
    (net (code "384") (name "Net-(B11A-S)") (class "Default")
      (node (ref "B11") (pin "D1") (pinfunction "S_D1") (pintype "input"))
      (node (ref "B12") (pin "J2") (pinfunction "OUT_J2") (pintype "output"))
    )
    (net (code "385") (name "Net-(B11D-C)") (class "Default")
      (node (ref "B11") (pin "D2") (pinfunction "C_D2") (pintype "input"))
      (node (ref "B12") (pin "F2") (pinfunction "OUT_F2") (pintype "output"))
    )
    (net (code "386") (name "Net-(B11E-D)") (class "Default")
      (node (ref "B11") (pin "J1") (pinfunction "D_J1") (pintype "input"))
      (node (ref "C28") (pin "H2") (pinfunction "OUT_H2") (pintype "output"))
    )
    (net (code "387") (name "Net-(B11G-S)") (class "Default")
      (node (ref "B11") (pin "R1") (pinfunction "S_R1") (pintype "input"))
      (node (ref "C14") (pin "K1") (pinfunction "OUT_K1") (pintype "output"))
    )
    (net (code "388") (name "Net-(B12D-IN)") (class "Default")
      (node (ref "B12") (pin "E2") (pinfunction "IN_E2") (pintype "input"))
      (node (ref "C14") (pin "S2") (pinfunction "OUT_S2") (pintype "output"))
    )
    (net (code "389") (name "Net-(B12G-IN)") (class "Default")
      (node (ref "B12") (pin "F1") (pinfunction "IN_F1") (pintype "input"))
      (node (ref "B13") (pin "K1") (pinfunction "OUT_K1") (pintype "output"))
    )
    (net (code "390") (name "Net-(B12H-IN)") (class "Default")
      (node (ref "B12") (pin "H2") (pinfunction "IN_H2") (pintype "input"))
      (node (ref "B13") (pin "S2") (pinfunction "OUT_S2") (pintype "output"))
    )
    (net (code "391") (name "Net-(B12I-IN)") (class "Default")
      (node (ref "B12") (pin "J1") (pinfunction "IN_J1") (pintype "input"))
      (node (ref "B32") (pin "H1") (pinfunction "P$1_H1") (pintype "passive"))
      (node (ref "C36") (pin "H1") (pinfunction "P$2_H1") (pintype "bidirectional"))
    )
    (net (code "392") (name "Net-(B12J-IN)") (class "Default")
      (node (ref "B12") (pin "K2") (pinfunction "IN_K2") (pintype "input"))
      (node (ref "C13") (pin "P2") (pinfunction "OUT_P2") (pintype "output"))
    )
    (net (code "393") (name "Net-(B12K-IN)") (class "Default")
      (node (ref "B12") (pin "L1") (pinfunction "IN_L1") (pintype "input"))
      (node (ref "B14") (pin "J2") (pinfunction "OUT_J2") (pintype "output"))
    )
    (net (code "394") (name "Net-(B12N-IN)") (class "Default")
      (node (ref "B12") (pin "P2") (pinfunction "IN_P2") (pintype "input"))
      (node (ref "B14") (pin "V2") (pinfunction "OUT_V2") (pintype "output"))
      (node (ref "C13") (pin "H2") (pinfunction "IN4_H2") (pintype "input"))
    )
    (net (code "395") (name "Net-(B12O-IN)") (class "Default")
      (node (ref "B12") (pin "R1") (pinfunction "IN_R1") (pintype "input"))
      (node (ref "B14") (pin "P2") (pinfunction "OUT_P2") (pintype "output"))
    )
    (net (code "396") (name "Net-(B12Q-IN)") (class "Default")
      (node (ref "B12") (pin "V1") (pinfunction "IN_V1") (pintype "input"))
      (node (ref "C13") (pin "S1") (pinfunction "OUT_S1") (pintype "output"))
    )
    (net (code "397") (name "Net-(B13A-OUT)") (class "Default")
      (node (ref "B13") (pin "C1") (pinfunction "OUT_C1") (pintype "output"))
      (node (ref "C13") (pin "H1") (pinfunction "IN2_H1") (pintype "input"))
    )
    (net (code "398") (name "Net-(B13C-IN2)") (class "Default")
      (node (ref "B13") (pin "E2") (pinfunction "IN2_E2") (pintype "input"))
      (node (ref "C15") (pin "F1") (pinfunction "OUT_F1") (pintype "output"))
    )
    (net (code "399") (name "Net-(B13K-IN1)") (class "Default")
      (node (ref "B13") (pin "P2") (pinfunction "IN1_P2") (pintype "input"))
      (node (ref "B13") (pin "V2") (pinfunction "OUT_V2") (pintype "output"))
    )
    (net (code "400") (name "Net-(B15E-P$1)") (class "Default")
      (node (ref "B15") (pin "U1") (pinfunction "P$1_U1") (pintype "passive"))
      (node (ref "B17") (pin "D1") (pinfunction "8B_D1") (pintype "input"))
    )
    (net (code "401") (name "Net-(B16C-EVEN)") (class "Default")
      (node (ref "B16") (pin "L1") (pinfunction "EVEN_L1") (pintype "output"))
      (node (ref "B17") (pin "A1") (pinfunction "1B_A1") (pintype "input"))
    )
    (net (code "402") (name "Net-(B16C-ODD)") (class "Default")
      (node (ref "B16") (pin "K1") (pinfunction "ODD_K1") (pintype "output"))
      (node (ref "B17") (pin "E1") (pinfunction "1A_E1") (pintype "input"))
    )
    (net (code "403") (name "Net-(B16D-EVEN)") (class "Default")
      (node (ref "B16") (pin "V2") (pinfunction "EVEN_V2") (pintype "output"))
      (node (ref "B17") (pin "C1") (pinfunction "4B_C1") (pintype "input"))
    )
    (net (code "404") (name "Net-(B16D-ODD)") (class "Default")
      (node (ref "B16") (pin "U2") (pinfunction "ODD_U2") (pintype "output"))
      (node (ref "B17") (pin "H1") (pinfunction "4A_H1") (pintype "input"))
    )
    (net (code "405") (name "Net-(B17C-2A)") (class "Default")
      (node (ref "B17") (pin "F1") (pinfunction "2A_F1") (pintype "input"))
      (node (ref "B17") (pin "U2") (pinfunction "ODD_U2") (pintype "output"))
    )
    (net (code "406") (name "Net-(B17C-2B)") (class "Default")
      (node (ref "B17") (pin "B1") (pinfunction "2B_B1") (pintype "input"))
      (node (ref "B17") (pin "V2") (pinfunction "EVEN_V2") (pintype "output"))
    )
    (net (code "407") (name "Net-(B21C-P$2)") (class "Default")
      (node (ref "B18") (pin "D2") (pinfunction "D2_D2") (pintype "input"))
      (node (ref "B21") (pin "C2") (pinfunction "P$2_C2") (pintype "bidirectional"))
    )
    (net (code "408") (name "Net-(B21D-P$2)") (class "Default")
      (node (ref "B18") (pin "E2") (pinfunction "E2_E2") (pintype "input"))
      (node (ref "B21") (pin "D2") (pinfunction "P$2_D2") (pintype "bidirectional"))
    )
    (net (code "409") (name "Net-(B21E-P$2)") (class "Default")
      (node (ref "B18") (pin "L1") (pinfunction "L1_L1") (pintype "input"))
      (node (ref "B21") (pin "E2") (pinfunction "P$2_E2") (pintype "bidirectional"))
    )
    (net (code "410") (name "Net-(B21F-P$2)") (class "Default")
      (node (ref "B18") (pin "M1") (pinfunction "M1_M1") (pintype "input"))
      (node (ref "B21") (pin "F2") (pinfunction "P$2_F2") (pintype "bidirectional"))
    )
    (net (code "411") (name "Net-(B21G-P$2)") (class "Default")
      (node (ref "B19") (pin "D2") (pinfunction "D2_D2") (pintype "input"))
      (node (ref "B21") (pin "H2") (pinfunction "P$2_H2") (pintype "bidirectional"))
    )
    (net (code "412") (name "Net-(B21H-P$2)") (class "Default")
      (node (ref "B19") (pin "E2") (pinfunction "E2_E2") (pintype "input"))
      (node (ref "B21") (pin "J2") (pinfunction "P$2_J2") (pintype "bidirectional"))
    )
    (net (code "413") (name "Net-(B21I-P$2)") (class "Default")
      (node (ref "B19") (pin "L1") (pinfunction "L1_L1") (pintype "input"))
      (node (ref "B21") (pin "K2") (pinfunction "P$2_K2") (pintype "bidirectional"))
    )
    (net (code "414") (name "Net-(B21J-P$2)") (class "Default")
      (node (ref "B19") (pin "M1") (pinfunction "M1_M1") (pintype "input"))
      (node (ref "B21") (pin "L2") (pinfunction "P$2_L2") (pintype "bidirectional"))
    )
    (net (code "415") (name "Net-(B21K-P$2)") (class "Default")
      (node (ref "B20") (pin "D2") (pinfunction "D2_D2") (pintype "input"))
      (node (ref "B21") (pin "M2") (pinfunction "P$2_M2") (pintype "bidirectional"))
    )
    (net (code "416") (name "Net-(B21L-P$2)") (class "Default")
      (node (ref "B20") (pin "E2") (pinfunction "E2_E2") (pintype "input"))
      (node (ref "B21") (pin "N2") (pinfunction "P$2_N2") (pintype "bidirectional"))
    )
    (net (code "417") (name "Net-(B21M-P$2)") (class "Default")
      (node (ref "B20") (pin "L1") (pinfunction "L1_L1") (pintype "input"))
      (node (ref "B21") (pin "P2") (pinfunction "P$2_P2") (pintype "bidirectional"))
    )
    (net (code "418") (name "Net-(B21N-P$2)") (class "Default")
      (node (ref "B20") (pin "M1") (pinfunction "M1_M1") (pintype "input"))
      (node (ref "B21") (pin "R2") (pinfunction "P$2_R2") (pintype "bidirectional"))
    )
    (net (code "419") (name "Net-(B22C-P$2)") (class "Default")
      (node (ref "B22") (pin "C2") (pinfunction "P$2_C2") (pintype "bidirectional"))
      (node (ref "B23") (pin "S2") (pinfunction "J_S2") (pintype "passive"))
    )
    (net (code "420") (name "Net-(B22D-P$2)") (class "Default")
      (node (ref "B22") (pin "D2") (pinfunction "P$2_D2") (pintype "bidirectional"))
      (node (ref "B23") (pin "T2") (pinfunction "K_T2") (pintype "passive"))
    )
    (net (code "421") (name "Net-(B22E-P$2)") (class "Default")
      (node (ref "B22") (pin "E2") (pinfunction "P$2_E2") (pintype "bidirectional"))
      (node (ref "B23") (pin "P1") (pinfunction "J_P1") (pintype "passive"))
    )
    (net (code "422") (name "Net-(B22F-P$2)") (class "Default")
      (node (ref "B22") (pin "F2") (pinfunction "P$2_F2") (pintype "bidirectional"))
      (node (ref "B23") (pin "R1") (pinfunction "K_R1") (pintype "passive"))
    )
    (net (code "423") (name "Net-(B22G-P$2)") (class "Default")
      (node (ref "B22") (pin "H2") (pinfunction "P$2_H2") (pintype "bidirectional"))
      (node (ref "B24") (pin "J2") (pinfunction "J_J2") (pintype "passive"))
    )
    (net (code "424") (name "Net-(B22H-P$2)") (class "Default")
      (node (ref "B22") (pin "J2") (pinfunction "P$2_J2") (pintype "bidirectional"))
      (node (ref "B24") (pin "K2") (pinfunction "K_K2") (pintype "passive"))
    )
    (net (code "425") (name "Net-(B22I-P$2)") (class "Default")
      (node (ref "B22") (pin "K2") (pinfunction "P$2_K2") (pintype "bidirectional"))
      (node (ref "B24") (pin "H1") (pinfunction "J_H1") (pintype "passive"))
    )
    (net (code "426") (name "Net-(B22J-P$2)") (class "Default")
      (node (ref "B22") (pin "L2") (pinfunction "P$2_L2") (pintype "bidirectional"))
      (node (ref "B24") (pin "J1") (pinfunction "K_J1") (pintype "passive"))
    )
    (net (code "427") (name "Net-(B22K-P$2)") (class "Default")
      (node (ref "B22") (pin "M2") (pinfunction "P$2_M2") (pintype "bidirectional"))
      (node (ref "B24") (pin "S2") (pinfunction "J_S2") (pintype "passive"))
    )
    (net (code "428") (name "Net-(B22L-P$2)") (class "Default")
      (node (ref "B22") (pin "N2") (pinfunction "P$2_N2") (pintype "bidirectional"))
      (node (ref "B24") (pin "T2") (pinfunction "K_T2") (pintype "passive"))
    )
    (net (code "429") (name "Net-(B22M-P$2)") (class "Default")
      (node (ref "B22") (pin "P2") (pinfunction "P$2_P2") (pintype "bidirectional"))
      (node (ref "B24") (pin "P1") (pinfunction "J_P1") (pintype "passive"))
    )
    (net (code "430") (name "Net-(B22N-P$2)") (class "Default")
      (node (ref "B22") (pin "R2") (pinfunction "P$2_R2") (pintype "bidirectional"))
      (node (ref "B24") (pin "R1") (pinfunction "K_R1") (pintype "passive"))
    )
    (net (code "431") (name "Net-(B22O-P$2)") (class "Default")
      (node (ref "B22") (pin "S2") (pinfunction "P$2_S2") (pintype "bidirectional"))
      (node (ref "B27") (pin "R2") (pinfunction "P$2_R2") (pintype "bidirectional"))
    )
    (net (code "432") (name "Net-(B22P-P$2)") (class "Default")
      (node (ref "B22") (pin "T2") (pinfunction "P$2_T2") (pintype "bidirectional"))
      (node (ref "B27") (pin "S2") (pinfunction "P$2_S2") (pintype "bidirectional"))
    )
    (net (code "433") (name "Net-(B23B-H)") (class "Default")
      (node (ref "B23") (pin "F1") (pinfunction "H_F1") (pintype "input"))
      (node (ref "B25") (pin "R2") (pinfunction "P$2_R2") (pintype "passive"))
    )
    (net (code "434") (name "Net-(B23D-H)") (class "Default")
      (node (ref "B23") (pin "H2") (pinfunction "H_H2") (pintype "input"))
      (node (ref "B25") (pin "P2") (pinfunction "P$2_P2") (pintype "passive"))
    )
    (net (code "435") (name "Net-(B23E-H)") (class "Default")
      (node (ref "B23") (pin "N1") (pinfunction "H_N1") (pintype "input"))
      (node (ref "B25") (pin "T2") (pinfunction "P$2_T2") (pintype "passive"))
    )
    (net (code "436") (name "Net-(B23F-H)") (class "Default")
      (node (ref "B23") (pin "R2") (pinfunction "H_R2") (pintype "input"))
      (node (ref "B25") (pin "S2") (pinfunction "P$2_S2") (pintype "passive"))
    )
    (net (code "437") (name "Net-(B24B-H)") (class "Default")
      (node (ref "B24") (pin "F1") (pinfunction "H_F1") (pintype "input"))
      (node (ref "B26") (pin "R2") (pinfunction "P$2_R2") (pintype "passive"))
    )
    (net (code "438") (name "Net-(B24D-H)") (class "Default")
      (node (ref "B24") (pin "H2") (pinfunction "H_H2") (pintype "input"))
      (node (ref "B26") (pin "P2") (pinfunction "P$2_P2") (pintype "passive"))
    )
    (net (code "439") (name "Net-(B24E-H)") (class "Default")
      (node (ref "B24") (pin "N1") (pinfunction "H_N1") (pintype "input"))
      (node (ref "B26") (pin "T2") (pinfunction "P$2_T2") (pintype "passive"))
    )
    (net (code "440") (name "Net-(B24F-H)") (class "Default")
      (node (ref "B24") (pin "R2") (pinfunction "H_R2") (pintype "input"))
      (node (ref "B26") (pin "S2") (pinfunction "P$2_S2") (pintype "passive"))
    )
    (net (code "441") (name "Net-(B25D-P$1)") (class "Default")
      (node (ref "B23") (pin "F2") (pinfunction "F2_F2") (pintype "passive"))
      (node (ref "B25") (pin "N2") (pinfunction "P$1_N2") (pintype "passive"))
    )
    (net (code "442") (name "Net-(B25E-P$1)") (class "Default")
      (node (ref "B23") (pin "E1") (pinfunction "E1_E1") (pintype "passive"))
      (node (ref "B25") (pin "M2") (pinfunction "P$1_M2") (pintype "passive"))
    )
    (net (code "443") (name "Net-(B25F-P$1)") (class "Default")
      (node (ref "B23") (pin "P2") (pinfunction "P2_P2") (pintype "passive"))
      (node (ref "B25") (pin "L2") (pinfunction "P$1_L2") (pintype "passive"))
    )
    (net (code "444") (name "Net-(B25G-P$1)") (class "Default")
      (node (ref "B23") (pin "M1") (pinfunction "M1_M1") (pintype "passive"))
      (node (ref "B25") (pin "K2") (pinfunction "P$1_K2") (pintype "passive"))
    )
    (net (code "445") (name "Net-(B25H-P$1)") (class "Default")
      (node (ref "B25") (pin "F2") (pinfunction "P$1_F2") (pintype "passive"))
      (node (ref "C25") (pin "E1") (pinfunction "E1_E1") (pintype "passive"))
      (node (ref "D25") (pin "E1") (pinfunction "E1_E1") (pintype "passive"))
    )
    (net (code "446") (name "Net-(B26D-P$1)") (class "Default")
      (node (ref "B24") (pin "F2") (pinfunction "F2_F2") (pintype "passive"))
      (node (ref "B26") (pin "N2") (pinfunction "P$1_N2") (pintype "passive"))
    )
    (net (code "447") (name "Net-(B26E-P$1)") (class "Default")
      (node (ref "B24") (pin "E1") (pinfunction "E1_E1") (pintype "passive"))
      (node (ref "B26") (pin "M2") (pinfunction "P$1_M2") (pintype "passive"))
    )
    (net (code "448") (name "Net-(B26F-P$1)") (class "Default")
      (node (ref "B24") (pin "P2") (pinfunction "P2_P2") (pintype "passive"))
      (node (ref "B26") (pin "L2") (pinfunction "P$1_L2") (pintype "passive"))
    )
    (net (code "449") (name "Net-(B26G-P$1)") (class "Default")
      (node (ref "B24") (pin "M1") (pinfunction "M1_M1") (pintype "passive"))
      (node (ref "B26") (pin "K2") (pinfunction "P$1_K2") (pintype "passive"))
    )
    (net (code "450") (name "Net-(B26H-P$1)") (class "Default")
      (node (ref "B26") (pin "F2") (pinfunction "P$1_F2") (pintype "passive"))
      (node (ref "C25") (pin "M1") (pinfunction "M1_M1") (pintype "passive"))
      (node (ref "D25") (pin "M1") (pinfunction "M1_M1") (pintype "passive"))
    )
    (net (code "451") (name "Net-(B27F-P$2)") (class "Default")
      (node (ref "B27") (pin "F2") (pinfunction "P$2_F2") (pintype "bidirectional"))
      (node (ref "B36") (pin "S2") (pinfunction "P$2_S2") (pintype "bidirectional"))
    )
    (net (code "452") (name "Net-(B27H-P$2)") (class "Default")
      (node (ref "B27") (pin "J2") (pinfunction "P$2_J2") (pintype "bidirectional"))
      (node (ref "B27") (pin "K2") (pinfunction "P$2_K2") (pintype "bidirectional"))
      (node (ref "B28") (pin "J2") (pinfunction "P$2_J2") (pintype "bidirectional"))
      (node (ref "B28") (pin "K2") (pinfunction "P$2_K2") (pintype "bidirectional"))
    )
    (net (code "453") (name "Net-(B32AA-P$1)") (class "Default")
      (node (ref "B32") (pin "S1") (pinfunction "P$1_S1") (pintype "passive"))
      (node (ref "C36") (pin "S1") (pinfunction "P$2_S1") (pintype "bidirectional"))
      (node (ref "D13") (pin "U2") (pinfunction "IN_U2") (pintype "input"))
    )
    (net (code "454") (name "Net-(B32AB-P$1)") (class "Default")
      (node (ref "B32") (pin "S2") (pinfunction "P$1_S2") (pintype "passive"))
      (node (ref "C27") (pin "U2") (pinfunction "D_U2") (pintype "open_collector"))
      (node (ref "C36") (pin "S2") (pinfunction "P$2_S2") (pintype "bidirectional"))
    )
    (net (code "455") (name "Net-(B32AF-P$1)") (class "Default")
      (node (ref "B32") (pin "V2") (pinfunction "P$1_V2") (pintype "passive"))
      (node (ref "C27") (pin "V2") (pinfunction "E_V2") (pintype "open_collector"))
      (node (ref "C36") (pin "V2") (pinfunction "P$2_V2") (pintype "bidirectional"))
    )
    (net (code "456") (name "Net-(B32B-P$1)") (class "Default")
      (node (ref "B32") (pin "B1") (pinfunction "P$1_B1") (pintype "passive"))
      (node (ref "C36") (pin "B1") (pinfunction "P$2_B1") (pintype "bidirectional"))
      (node (ref "D11") (pin "P1") (pinfunction "IN1_P1") (pintype "input"))
      (node (ref "D11") (pin "R1") (pinfunction "IN2_R1") (pintype "input"))
    )
    (net (code "457") (name "Net-(B32D-P$1)") (class "Default")
      (node (ref "B32") (pin "D1") (pinfunction "P$1_D1") (pintype "passive"))
      (node (ref "C36") (pin "D1") (pinfunction "P$2_D1") (pintype "bidirectional"))
      (node (ref "D11") (pin "P2") (pinfunction "IN1_P2") (pintype "input"))
      (node (ref "D11") (pin "R2") (pinfunction "IN2_R2") (pintype "input"))
    )
    (net (code "458") (name "Net-(B32F-P$1)") (class "Default")
      (node (ref "B32") (pin "E1") (pinfunction "P$1_E1") (pintype "passive"))
      (node (ref "C36") (pin "E1") (pinfunction "P$2_E1") (pintype "bidirectional"))
      (node (ref "D11") (pin "T2") (pinfunction "IN1_T2") (pintype "input"))
      (node (ref "D11") (pin "U2") (pinfunction "IN2_U2") (pintype "input"))
    )
    (net (code "459") (name "Net-(B32M-P$1)") (class "Default")
      (node (ref "B32") (pin "J1") (pinfunction "P$1_J1") (pintype "passive"))
      (node (ref "C36") (pin "J1") (pinfunction "P$2_J1") (pintype "bidirectional"))
      (node (ref "D13") (pin "A1") (pinfunction "IN_A1") (pintype "input"))
    )
    (net (code "460") (name "Net-(B32Q-P$1)") (class "Default")
      (node (ref "B32") (pin "L1") (pinfunction "P$1_L1") (pintype "passive"))
      (node (ref "C36") (pin "L1") (pinfunction "P$2_L1") (pintype "bidirectional"))
      (node (ref "D13") (pin "J1") (pinfunction "IN_J1") (pintype "input"))
    )
    (net (code "461") (name "Net-(B32S-P$1)") (class "Default")
      (node (ref "B32") (pin "M1") (pinfunction "P$1_M1") (pintype "passive"))
      (node (ref "C36") (pin "M1") (pinfunction "P$2_M1") (pintype "bidirectional"))
      (node (ref "D13") (pin "P2") (pinfunction "IN_P2") (pintype "input"))
    )
    (net (code "462") (name "Net-(B32W-P$1)") (class "Default")
      (node (ref "B32") (pin "P1") (pinfunction "P$1_P1") (pintype "passive"))
      (node (ref "C36") (pin "P1") (pinfunction "P$2_P1") (pintype "bidirectional"))
      (node (ref "D13") (pin "S2") (pinfunction "IN_S2") (pintype "input"))
    )
    (net (code "463") (name "Net-(B32X-P$1)") (class "Default")
      (node (ref "B32") (pin "P2") (pinfunction "P$1_P2") (pintype "passive"))
      (node (ref "C27") (pin "P2") (pinfunction "E_P2") (pintype "open_collector"))
      (node (ref "C36") (pin "P2") (pinfunction "P$2_P2") (pintype "bidirectional"))
    )
    (net (code "464") (name "Net-(B33AB-P$1)") (class "Default")
      (node (ref "B33") (pin "S2") (pinfunction "P$1_S2") (pintype "passive"))
      (node (ref "C35") (pin "S2") (pinfunction "P$2_S2") (pintype "bidirectional"))
    )
    (net (code "465") (name "Net-(B33X-P$1)") (class "Default")
      (node (ref "B33") (pin "P2") (pinfunction "P$1_P2") (pintype "passive"))
      (node (ref "C27") (pin "N2") (pinfunction "D_N2") (pintype "open_collector"))
      (node (ref "C35") (pin "P2") (pinfunction "P$2_P2") (pintype "bidirectional"))
    )
    (net (code "466") (name "Net-(B36B-P$2)") (class "Default")
      (node (ref "B36") (pin "B1") (pinfunction "P$2_B1") (pintype "bidirectional"))
      (node (ref "C15") (pin "S1") (pinfunction "OUT_S1") (pintype "output"))
    )
    (net (code "467") (name "Net-(B36F-P$2)") (class "Default")
      (node (ref "B36") (pin "D2") (pinfunction "P$2_D2") (pintype "bidirectional"))
      (node (ref "D17") (pin "V2") (pinfunction "OUT_V2") (pintype "open_collector"))
    )
    (net (code "468") (name "Net-(B36H-P$2)") (class "Default")
      (node (ref "B36") (pin "E2") (pinfunction "P$2_E2") (pintype "bidirectional"))
      (node (ref "C15") (pin "S2") (pinfunction "OUT_S2") (pintype "output"))
    )
    (net (code "469") (name "Net-(B36L-P$2)") (class "Default")
      (node (ref "B36") (pin "H2") (pinfunction "P$2_H2") (pintype "bidirectional"))
      (node (ref "D17") (pin "P2") (pinfunction "OUT_P2") (pintype "open_collector"))
    )
    (net (code "470") (name "Net-(B36M-P$2)") (class "Default")
      (node (ref "B36") (pin "J1") (pinfunction "P$2_J1") (pintype "bidirectional"))
      (node (ref "C15") (pin "V2") (pinfunction "OUT_V2") (pintype "output"))
    )
    (net (code "471") (name "Net-(B36S-P$2)") (class "Default")
      (node (ref "B36") (pin "M1") (pinfunction "P$2_M1") (pintype "bidirectional"))
      (node (ref "C15") (pin "N2") (pinfunction "OUT_N2") (pintype "output"))
    )
    (net (code "472") (name "Net-(C02H-OUT)") (class "Default")
      (node (ref "C02") (pin "L2") (pinfunction "IN1_L2") (pintype "input"))
      (node (ref "C02") (pin "N1") (pinfunction "OUT_N1") (pintype "output"))
    )
    (net (code "473") (name "Net-(C02I-IN2)") (class "Default")
      (node (ref "C02") (pin "M2") (pinfunction "IN2_M2") (pintype "input"))
      (node (ref "C02") (pin "P1") (pinfunction "IN1_P1") (pintype "input"))
      (node (ref "D04") (pin "D1") (pinfunction "OUT_D1") (pintype "output"))
    )
    (net (code "474") (name "Net-(C02J-IN2)") (class "Default")
      (node (ref "C02") (pin "R1") (pinfunction "IN2_R1") (pintype "input"))
      (node (ref "C02") (pin "S2") (pinfunction "OUT_S2") (pintype "output"))
    )
    (net (code "475") (name "Net-(C02N-OUT)") (class "Default")
      (node (ref "C02") (pin "V2") (pinfunction "OUT_V2") (pintype "output"))
      (node (ref "C05") (pin "L1") (pinfunction "IN1_L1") (pintype "input"))
    )
    (net (code "476") (name "Net-(C04E-C)") (class "Default")
      (node (ref "C04") (pin "H1") (pinfunction "C_H1") (pintype "input"))
      (node (ref "D05") (pin "F1") (pinfunction "OUT_F1") (pintype "output"))
    )
    (net (code "477") (name "Net-(C04H-S)") (class "Default")
      (node (ref "C04") (pin "U2") (pinfunction "S_U2") (pintype "input"))
      (node (ref "D02") (pin "S1") (pinfunction "OUT_S1") (pintype "output"))
    )
    (net (code "478") (name "Net-(C05A-OUT)") (class "Default")
      (node (ref "C05") (pin "C1") (pinfunction "OUT_C1") (pintype "output"))
      (node (ref "C05") (pin "D1") (pinfunction "IN1_D1") (pintype "input"))
    )
    (net (code "479") (name "Net-(C05I-IN1)") (class "Default")
      (node (ref "C05") (pin "L2") (pinfunction "IN1_L2") (pintype "input"))
      (node (ref "C05") (pin "M2") (pinfunction "IN2_M2") (pintype "input"))
      (node (ref "D07") (pin "F1") (pinfunction "OUT_F1") (pintype "output"))
      (node (ref "D08") (pin "H2") (pinfunction "H2_H2") (pintype "input"))
    )
    (net (code "480") (name "Net-(C05J-OUT)") (class "Default")
      (node (ref "C05") (pin "S1") (pinfunction "OUT_S1") (pintype "output"))
      (node (ref "D07") (pin "H2") (pinfunction "H2_H2") (pintype "input"))
    )
    (net (code "481") (name "Net-(C05N-OUT)") (class "Default")
      (node (ref "C05") (pin "V2") (pinfunction "OUT_V2") (pintype "output"))
      (node (ref "C15") (pin "T2") (pinfunction "IN1_T2") (pintype "input"))
    )
    (net (code "482") (name "Net-(C06G-D)") (class "Default")
      (node (ref "C06") (pin "P1") (pinfunction "D_P1") (pintype "input"))
      (node (ref "C07") (pin "B1") (pinfunction "OUT_B1") (pintype "output"))
    )
    (net (code "483") (name "Net-(C07A-IN)") (class "Default")
      (node (ref "C07") (pin "A1") (pinfunction "IN_A1") (pintype "input"))
      (node (ref "D09") (pin "R1") (pinfunction "OUT_R1") (pintype "output"))
    )
    (net (code "484") (name "Net-(C07B-IN)") (class "Default")
      (node (ref "C07") (pin "C1") (pinfunction "IN_C1") (pintype "input"))
      (node (ref "D12") (pin "K1") (pinfunction "OUT_K1") (pintype "output"))
    )
    (net (code "485") (name "Net-(C07B-OUT)") (class "Default")
      (node (ref "C07") (pin "D2") (pinfunction "OUT_D2") (pintype "output"))
      (node (ref "C08") (pin "B1") (pinfunction "C_B1") (pintype "input"))
      (node (ref "C08") (pin "D2") (pinfunction "C_D2") (pintype "input"))
      (node (ref "C08") (pin "H1") (pinfunction "C_H1") (pintype "input"))
    )
    (net (code "486") (name "Net-(C07J-IN)") (class "Default")
      (node (ref "C07") (pin "K2") (pinfunction "IN_K2") (pintype "input"))
      (node (ref "C10") (pin "V2") (pinfunction "OUT_V2") (pintype "output"))
    )
    (net (code "487") (name "Net-(C07J-OUT)") (class "Default")
      (node (ref "C07") (pin "L2") (pinfunction "OUT_L2") (pintype "output"))
      (node (ref "D04") (pin "T2") (pinfunction "IN1_T2") (pintype "input"))
    )
    (net (code "488") (name "Net-(C08A-D)") (class "Default")
      (node (ref "C08") (pin "C1") (pinfunction "D_C1") (pintype "input"))
      (node (ref "D13") (pin "S1") (pinfunction "OUT_S1") (pintype "output"))
    )
    (net (code "489") (name "Net-(C08A-R)") (class "Default")
      (node (ref "C08") (pin "A1") (pinfunction "R_A1") (pintype "input"))
      (node (ref "D12") (pin "K2") (pinfunction "OUT_K2") (pintype "output"))
    )
    (net (code "490") (name "Net-(C09J-IN2)") (class "Default")
      (node (ref "C09") (pin "U2") (pinfunction "IN2_U2") (pintype "input"))
      (node (ref "D12") (pin "F1") (pinfunction "OUT_F1") (pintype "output"))
    )
    (net (code "491") (name "Net-(C09J-IN3)") (class "Default")
      (node (ref "C09") (pin "V2") (pinfunction "IN3_V2") (pintype "input"))
      (node (ref "C11") (pin "L1") (pinfunction "OUT_L1") (pintype "output"))
    )
    (net (code "492") (name "Net-(C10G-IN8)") (class "Default")
      (node (ref "C10") (pin "U2") (pinfunction "IN8_U2") (pintype "input"))
      (node (ref "D02") (pin "U1") (pinfunction "OUT_U1") (pintype "output"))
    )
    (net (code "493") (name "Net-(C12F-IN2)") (class "Default")
      (node (ref "C12") (pin "K2") (pinfunction "IN2_K2") (pintype "input"))
      (node (ref "C12") (pin "S2") (pinfunction "OUT_S2") (pintype "output"))
    )
    (net (code "494") (name "Net-(C13F-IN2)") (class "Default")
      (node (ref "C13") (pin "L2") (pinfunction "IN2_L2") (pintype "input"))
      (node (ref "C13") (pin "N2") (pinfunction "IN4_N2") (pintype "input"))
      (node (ref "C14") (pin "V2") (pinfunction "OUT_V2") (pintype "output"))
    )
    (net (code "495") (name "Net-(C13J-OUT)") (class "Default")
      (node (ref "C13") (pin "V2") (pinfunction "OUT_V2") (pintype "output"))
      (node (ref "C15") (pin "A1") (pinfunction "IN1_A1") (pintype "input"))
    )
    (net (code "496") (name "Net-(C14A-OUT)") (class "Default")
      (node (ref "C14") (pin "C1") (pinfunction "OUT_C1") (pintype "output"))
      (node (ref "C14") (pin "D1") (pinfunction "IN1_D1") (pintype "input"))
    )
    (net (code "497") (name "Net-(C15A-IN2)") (class "Default")
      (node (ref "C15") (pin "B1") (pinfunction "IN2_B1") (pintype "input"))
      (node (ref "C15") (pin "K2") (pinfunction "OUT_K2") (pintype "output"))
      (node (ref "D16") (pin "F2") (pinfunction "S_F2") (pintype "input"))
    )
    (net (code "498") (name "Net-(C15A-OUT)") (class "Default")
      (node (ref "C15") (pin "C1") (pinfunction "OUT_C1") (pintype "output"))
      (node (ref "D14") (pin "H2") (pinfunction "H2_H2") (pintype "input"))
    )
    (net (code "499") (name "Net-(C15C-IN1)") (class "Default")
      (node (ref "C15") (pin "D2") (pinfunction "IN1_D2") (pintype "input"))
      (node (ref "D14") (pin "F1") (pinfunction "OUT_F1") (pintype "output"))
    )
    (net (code "500") (name "Net-(C15C-OUT)") (class "Default")
      (node (ref "C15") (pin "F2") (pinfunction "OUT_F2") (pintype "output"))
      (node (ref "D16") (pin "N2") (pinfunction "S_N2") (pintype "input"))
    )
    (net (code "501") (name "Net-(C15F-IN2)") (class "Default")
      (node (ref "C15") (pin "J1") (pinfunction "IN2_J1") (pintype "input"))
      (node (ref "D14") (pin "J1") (pinfunction "OUT_J1") (pintype "output"))
      (node (ref "D15") (pin "H2") (pinfunction "H2_H2") (pintype "input"))
      (node (ref "D17") (pin "M1") (pinfunction "IN1_M1") (pintype "input"))
      (node (ref "D17") (pin "N1") (pinfunction "IN2_N1") (pintype "input"))
    )
    (net (code "502") (name "Net-(C15F-OUT)") (class "Default")
      (node (ref "C15") (pin "K1") (pinfunction "OUT_K1") (pintype "output"))
      (node (ref "D16") (pin "R1") (pinfunction "S_R1") (pintype "input"))
    )
    (net (code "503") (name "Net-(C15H-OUT)") (class "Default")
      (node (ref "C15") (pin "N1") (pinfunction "OUT_N1") (pintype "output"))
      (node (ref "D13") (pin "N1") (pinfunction "IN_N1") (pintype "input"))
    )
    (net (code "504") (name "Net-(C17A-IN)") (class "Default")
      (node (ref "C17") (pin "U2") (pinfunction "IN_U2") (pintype "input"))
      (node (ref "D13") (pin "P1") (pinfunction "OUT_P1") (pintype "output"))
    )
    (net (code "505") (name "Net-(C17C-P)") (class "Default")
      (node (ref "C17") (pin "P2") (pinfunction "P_P2") (pintype "input"))
      (node (ref "D15") (pin "J1") (pinfunction "OUT_J1") (pintype "output"))
      (node (ref "D16") (pin "D2") (pinfunction "C_D2") (pintype "input"))
    )
    (net (code "506") (name "Net-(C20C-P$2)") (class "Default")
      (node (ref "C19") (pin "K2") (pinfunction "K2_K2") (pintype "passive"))
      (node (ref "C20") (pin "C2") (pinfunction "P$2_C2") (pintype "bidirectional"))
    )
    (net (code "507") (name "Net-(C20D-P$2)") (class "Default")
      (node (ref "C19") (pin "J2") (pinfunction "J2_J2") (pintype "passive"))
      (node (ref "C20") (pin "D2") (pinfunction "P$2_D2") (pintype "bidirectional"))
    )
    (net (code "508") (name "Net-(C20E-P$2)") (class "Default")
      (node (ref "C19") (pin "M2") (pinfunction "M2_M2") (pintype "passive"))
      (node (ref "C20") (pin "E2") (pinfunction "P$2_E2") (pintype "bidirectional"))
    )
    (net (code "509") (name "Net-(C20F-P$2)") (class "Default")
      (node (ref "C19") (pin "L2") (pinfunction "L2_L2") (pintype "passive"))
      (node (ref "C20") (pin "F2") (pinfunction "P$2_F2") (pintype "bidirectional"))
    )
    (net (code "510") (name "Net-(C20G-P$2)") (class "Default")
      (node (ref "C19") (pin "P2") (pinfunction "P2_P2") (pintype "passive"))
      (node (ref "C20") (pin "H2") (pinfunction "P$2_H2") (pintype "bidirectional"))
    )
    (net (code "511") (name "Net-(C20H-P$2)") (class "Default")
      (node (ref "C19") (pin "N2") (pinfunction "N2_N2") (pintype "passive"))
      (node (ref "C20") (pin "J2") (pinfunction "P$2_J2") (pintype "bidirectional"))
    )
    (net (code "512") (name "Net-(C20I-P$2)") (class "Default")
      (node (ref "C19") (pin "S2") (pinfunction "S2_S2") (pintype "passive"))
      (node (ref "C20") (pin "K2") (pinfunction "P$2_K2") (pintype "bidirectional"))
    )
    (net (code "513") (name "Net-(C20J-P$2)") (class "Default")
      (node (ref "C19") (pin "R2") (pinfunction "R2_R2") (pintype "passive"))
      (node (ref "C20") (pin "L2") (pinfunction "P$2_L2") (pintype "bidirectional"))
    )
    (net (code "514") (name "Net-(C20K-P$2)") (class "Default")
      (node (ref "C18") (pin "K2") (pinfunction "K2_K2") (pintype "passive"))
      (node (ref "C20") (pin "M2") (pinfunction "P$2_M2") (pintype "bidirectional"))
    )
    (net (code "515") (name "Net-(C20L-P$2)") (class "Default")
      (node (ref "C18") (pin "J2") (pinfunction "J2_J2") (pintype "passive"))
      (node (ref "C20") (pin "N2") (pinfunction "P$2_N2") (pintype "bidirectional"))
    )
    (net (code "516") (name "Net-(C20M-P$2)") (class "Default")
      (node (ref "C18") (pin "M2") (pinfunction "M2_M2") (pintype "passive"))
      (node (ref "C20") (pin "P2") (pinfunction "P$2_P2") (pintype "bidirectional"))
    )
    (net (code "517") (name "Net-(C20N-P$2)") (class "Default")
      (node (ref "C18") (pin "L2") (pinfunction "L2_L2") (pintype "passive"))
      (node (ref "C20") (pin "R2") (pinfunction "P$2_R2") (pintype "bidirectional"))
    )
    (net (code "518") (name "Net-(C20O-P$2)") (class "Default")
      (node (ref "C18") (pin "P2") (pinfunction "P2_P2") (pintype "passive"))
      (node (ref "C20") (pin "S2") (pinfunction "P$2_S2") (pintype "bidirectional"))
    )
    (net (code "519") (name "Net-(C20P-P$2)") (class "Default")
      (node (ref "C18") (pin "N2") (pinfunction "N2_N2") (pintype "passive"))
      (node (ref "C20") (pin "T2") (pinfunction "P$2_T2") (pintype "bidirectional"))
    )
    (net (code "520") (name "Net-(C20Q-P$2)") (class "Default")
      (node (ref "C18") (pin "S2") (pinfunction "S2_S2") (pintype "passive"))
      (node (ref "C20") (pin "U2") (pinfunction "P$2_U2") (pintype "bidirectional"))
    )
    (net (code "521") (name "Net-(C20R-P$2)") (class "Default")
      (node (ref "C18") (pin "R2") (pinfunction "R2_R2") (pintype "passive"))
      (node (ref "C20") (pin "V2") (pinfunction "P$2_V2") (pintype "bidirectional"))
    )
    (net (code "522") (name "Net-(C22C-P$2)") (class "Default")
      (node (ref "C22") (pin "C2") (pinfunction "P$2_C2") (pintype "bidirectional"))
      (node (ref "C24") (pin "K2") (pinfunction "K2_K2") (pintype "passive"))
    )
    (net (code "523") (name "Net-(C22D-P$2)") (class "Default")
      (node (ref "C22") (pin "D2") (pinfunction "P$2_D2") (pintype "bidirectional"))
      (node (ref "C24") (pin "J2") (pinfunction "J2_J2") (pintype "passive"))
    )
    (net (code "524") (name "Net-(C22E-P$2)") (class "Default")
      (node (ref "C22") (pin "E2") (pinfunction "P$2_E2") (pintype "bidirectional"))
      (node (ref "C24") (pin "M2") (pinfunction "M2_M2") (pintype "passive"))
    )
    (net (code "525") (name "Net-(C22F-P$2)") (class "Default")
      (node (ref "C22") (pin "F2") (pinfunction "P$2_F2") (pintype "bidirectional"))
      (node (ref "C24") (pin "L2") (pinfunction "L2_L2") (pintype "passive"))
    )
    (net (code "526") (name "Net-(C22G-P$2)") (class "Default")
      (node (ref "C22") (pin "H2") (pinfunction "P$2_H2") (pintype "bidirectional"))
      (node (ref "C24") (pin "P2") (pinfunction "P2_P2") (pintype "passive"))
    )
    (net (code "527") (name "Net-(C22H-P$2)") (class "Default")
      (node (ref "C22") (pin "J2") (pinfunction "P$2_J2") (pintype "bidirectional"))
      (node (ref "C24") (pin "N2") (pinfunction "N2_N2") (pintype "passive"))
    )
    (net (code "528") (name "Net-(C22I-P$2)") (class "Default")
      (node (ref "C22") (pin "K2") (pinfunction "P$2_K2") (pintype "bidirectional"))
      (node (ref "C24") (pin "S2") (pinfunction "S2_S2") (pintype "passive"))
    )
    (net (code "529") (name "Net-(C22J-P$2)") (class "Default")
      (node (ref "C22") (pin "L2") (pinfunction "P$2_L2") (pintype "bidirectional"))
      (node (ref "C24") (pin "R2") (pinfunction "R2_R2") (pintype "passive"))
    )
    (net (code "530") (name "Net-(C22K-P$2)") (class "Default")
      (node (ref "C22") (pin "M2") (pinfunction "P$2_M2") (pintype "bidirectional"))
      (node (ref "C23") (pin "K2") (pinfunction "K2_K2") (pintype "passive"))
    )
    (net (code "531") (name "Net-(C22L-P$2)") (class "Default")
      (node (ref "C22") (pin "N2") (pinfunction "P$2_N2") (pintype "bidirectional"))
      (node (ref "C23") (pin "J2") (pinfunction "J2_J2") (pintype "passive"))
    )
    (net (code "532") (name "Net-(C22M-P$2)") (class "Default")
      (node (ref "C22") (pin "P2") (pinfunction "P$2_P2") (pintype "bidirectional"))
      (node (ref "C23") (pin "M2") (pinfunction "M2_M2") (pintype "passive"))
    )
    (net (code "533") (name "Net-(C22N-P$2)") (class "Default")
      (node (ref "C22") (pin "R2") (pinfunction "P$2_R2") (pintype "bidirectional"))
      (node (ref "C23") (pin "L2") (pinfunction "L2_L2") (pintype "passive"))
    )
    (net (code "534") (name "Net-(C22O-P$2)") (class "Default")
      (node (ref "C22") (pin "S2") (pinfunction "P$2_S2") (pintype "bidirectional"))
      (node (ref "C23") (pin "P2") (pinfunction "P2_P2") (pintype "passive"))
    )
    (net (code "535") (name "Net-(C22P-P$2)") (class "Default")
      (node (ref "C22") (pin "T2") (pinfunction "P$2_T2") (pintype "bidirectional"))
      (node (ref "C23") (pin "N2") (pinfunction "N2_N2") (pintype "passive"))
    )
    (net (code "536") (name "Net-(C22Q-P$2)") (class "Default")
      (node (ref "C22") (pin "U2") (pinfunction "P$2_U2") (pintype "bidirectional"))
      (node (ref "C23") (pin "S2") (pinfunction "S2_S2") (pintype "passive"))
    )
    (net (code "537") (name "Net-(C22R-P$2)") (class "Default")
      (node (ref "C22") (pin "V2") (pinfunction "P$2_V2") (pintype "bidirectional"))
      (node (ref "C23") (pin "R2") (pinfunction "R2_R2") (pintype "passive"))
    )
    (net (code "538") (name "Net-(C27A-D)") (class "Default")
      (node (ref "C27") (pin "D1") (pinfunction "D_D1") (pintype "open_collector"))
      (node (ref "D30") (pin "K2") (pinfunction "P$1_K2") (pintype "passive"))
      (node (ref "D35") (pin "K2") (pinfunction "P$2_K2") (pintype "bidirectional"))
    )
    (net (code "539") (name "Net-(C27A-E)") (class "Default")
      (node (ref "C27") (pin "E1") (pinfunction "E_E1") (pintype "open_collector"))
      (node (ref "D30") (pin "M2") (pinfunction "P$1_M2") (pintype "passive"))
      (node (ref "D35") (pin "M2") (pinfunction "P$2_M2") (pintype "bidirectional"))
    )
    (net (code "540") (name "Net-(C27F-D)") (class "Default")
      (node (ref "C27") (pin "H2") (pinfunction "D_H2") (pintype "open_collector"))
      (node (ref "D29") (pin "V2") (pinfunction "P$1_V2") (pintype "passive"))
      (node (ref "D34") (pin "S2") (pinfunction "P$2_S2") (pintype "bidirectional"))
    )
    (net (code "541") (name "Net-(C27G-D)") (class "Default")
      (node (ref "C27") (pin "K1") (pinfunction "D_K1") (pintype "open_collector"))
      (node (ref "D30") (pin "P2") (pinfunction "P$1_P2") (pintype "passive"))
      (node (ref "D35") (pin "P2") (pinfunction "P$2_P2") (pintype "bidirectional"))
    )
    (net (code "542") (name "Net-(C27G-E)") (class "Default")
      (node (ref "C27") (pin "L1") (pinfunction "E_L1") (pintype "open_collector"))
      (node (ref "D30") (pin "S2") (pinfunction "P$1_S2") (pintype "passive"))
      (node (ref "D35") (pin "S2") (pinfunction "P$2_S2") (pintype "bidirectional"))
    )
    (net (code "543") (name "Net-(C27I-D)") (class "Default")
      (node (ref "C27") (pin "R1") (pinfunction "D_R1") (pintype "open_collector"))
      (node (ref "D30") (pin "T2") (pinfunction "P$1_T2") (pintype "passive"))
      (node (ref "D35") (pin "T2") (pinfunction "P$2_T2") (pintype "bidirectional"))
    )
    (net (code "544") (name "Net-(C27I-E)") (class "Default")
      (node (ref "C27") (pin "S1") (pinfunction "E_S1") (pintype "open_collector"))
      (node (ref "D30") (pin "V2") (pinfunction "P$1_V2") (pintype "passive"))
      (node (ref "D35") (pin "V2") (pinfunction "P$2_V2") (pintype "bidirectional"))
    )
    (net (code "545") (name "Net-(C29A-OUT)") (class "Default")
      (node (ref "C29") (pin "D2") (pinfunction "OUT_D2") (pintype "output"))
      (node (ref "D36") (pin "K2") (pinfunction "P$2_K2") (pintype "bidirectional"))
    )
    (net (code "546") (name "Net-(C29C-OUT)") (class "Default")
      (node (ref "C29") (pin "K2") (pinfunction "OUT_K2") (pintype "output"))
      (node (ref "D36") (pin "M2") (pinfunction "P$2_M2") (pintype "bidirectional"))
    )
    (net (code "547") (name "Net-(C29D-OUT)") (class "Default")
      (node (ref "C29") (pin "S2") (pinfunction "OUT_S2") (pintype "output"))
      (node (ref "D36") (pin "P2") (pinfunction "P$2_P2") (pintype "bidirectional"))
    )
    (net (code "548") (name "Net-(C30A-OUT)") (class "Default")
      (node (ref "C30") (pin "D2") (pinfunction "OUT_D2") (pintype "output"))
      (node (ref "D36") (pin "S2") (pinfunction "P$2_S2") (pintype "bidirectional"))
    )
    (net (code "549") (name "Net-(C30C-OUT)") (class "Default")
      (node (ref "C30") (pin "K2") (pinfunction "OUT_K2") (pintype "output"))
      (node (ref "D36") (pin "T2") (pinfunction "P$2_T2") (pintype "bidirectional"))
    )
    (net (code "550") (name "Net-(C30D-OUT)") (class "Default")
      (node (ref "C30") (pin "S2") (pinfunction "OUT_S2") (pintype "output"))
      (node (ref "D36") (pin "V2") (pinfunction "P$2_V2") (pintype "bidirectional"))
    )
    (net (code "551") (name "Net-(C32P-P$2)") (class "Default")
      (node (ref "C32") (pin "J2") (pinfunction "P$2_J2") (pintype "bidirectional"))
      (node (ref "C32") (pin "K1") (pinfunction "P$2_K1") (pintype "bidirectional"))
    )
    (net (code "552") (name "Net-(C34AA-P$2)") (class "Default")
      (node (ref "AB31") (pin "AM2") (pinfunction "AM2_AM2") (pintype "output"))
      (node (ref "C34") (pin "R1") (pinfunction "P$2_R1") (pintype "bidirectional"))
    )
    (net (code "553") (name "Net-(C34AC-P$2)") (class "Default")
      (node (ref "AB31") (pin "AN2") (pinfunction "AN2_AN2") (pintype "output"))
      (node (ref "C34") (pin "S1") (pinfunction "P$2_S1") (pintype "bidirectional"))
    )
    (net (code "554") (name "Net-(C34G-P$2)") (class "Default")
      (node (ref "AB31") (pin "AV2") (pinfunction "AV2_AV2") (pintype "input"))
      (node (ref "C34") (pin "D1") (pinfunction "P$2_D1") (pintype "bidirectional"))
    )
    (net (code "555") (name "Net-(C34I-P$2)") (class "Default")
      (node (ref "AB31") (pin "AT2") (pinfunction "AT2_AT2") (pintype "input"))
      (node (ref "C34") (pin "E1") (pinfunction "P$2_E1") (pintype "bidirectional"))
    )
    (net (code "556") (name "Net-(C34M-P$2)") (class "Default")
      (node (ref "AB31") (pin "AK1") (pinfunction "AK1_AK1") (pintype "output"))
      (node (ref "C34") (pin "H1") (pinfunction "P$2_H1") (pintype "bidirectional"))
    )
    (net (code "557") (name "Net-(C34O-P$2)") (class "Default")
      (node (ref "AB31") (pin "AL1") (pinfunction "AL1_AL1") (pintype "output"))
      (node (ref "C34") (pin "J1") (pinfunction "P$2_J1") (pintype "bidirectional"))
    )
    (net (code "558") (name "Net-(C34Q-P$2)") (class "Default")
      (node (ref "AB31") (pin "AM1") (pinfunction "AM1_AM1") (pintype "output"))
      (node (ref "C34") (pin "K1") (pinfunction "P$2_K1") (pintype "bidirectional"))
    )
    (net (code "559") (name "Net-(C34S-P$2)") (class "Default")
      (node (ref "AB31") (pin "AN1") (pinfunction "AN1_AN1") (pintype "output"))
      (node (ref "C34") (pin "L1") (pinfunction "P$2_L1") (pintype "bidirectional"))
    )
    (net (code "560") (name "Net-(C34U-P$2)") (class "Default")
      (node (ref "AB31") (pin "BH2") (pinfunction "BH2_BH2") (pintype "output"))
      (node (ref "C34") (pin "M1") (pinfunction "P$2_M1") (pintype "bidirectional"))
    )
    (net (code "561") (name "Net-(C34W-P$2)") (class "Default")
      (node (ref "AB31") (pin "AK2") (pinfunction "AK2_AK2") (pintype "output"))
      (node (ref "C34") (pin "N1") (pinfunction "P$2_N1") (pintype "bidirectional"))
    )
    (net (code "562") (name "Net-(C34Y-P$2)") (class "Default")
      (node (ref "AB31") (pin "AL2") (pinfunction "AL2_AL2") (pintype "output"))
      (node (ref "C34") (pin "P1") (pinfunction "P$2_P1") (pintype "bidirectional"))
    )
    (net (code "563") (name "Net-(CD03C-CS2)") (class "Default")
      (node (ref "CD03") (pin "AS2") (pinfunction "CS2_AS2") (pintype "input"))
      (node (ref "D01") (pin "N1") (pinfunction "P$2_N1") (pintype "bidirectional"))
    )
    (net (code "564") (name "Net-(D02I-IN)") (class "Default")
      (node (ref "D02") (pin "J1") (pinfunction "IN_J1") (pintype "input"))
      (node (ref "D04") (pin "J1") (pinfunction "OUT_J1") (pintype "output"))
    )
    (net (code "565") (name "Net-(D02N-OUT)") (class "Default")
      (node (ref "D02") (pin "R2") (pinfunction "OUT_R2") (pintype "output"))
      (node (ref "D05") (pin "H2") (pinfunction "H2_H2") (pintype "input"))
    )
    (net (code "566") (name "Net-(D04I-OUT)") (class "Default")
      (node (ref "D04") (pin "U1") (pinfunction "OUT_U1") (pintype "output"))
      (node (ref "D04") (pin "V2") (pinfunction "IN3_V2") (pintype "input"))
    )
    (net (code "567") (name "Net-(D05A-IN)") (class "Default")
      (node (ref "D05") (pin "E1") (pinfunction "IN_E1") (pintype "input"))
      (node (ref "D05") (pin "R2") (pinfunction "R2_R2") (pintype "output"))
    )
    (net (code "568") (name "Net-(D05E-IN)") (class "Default")
      (node (ref "D05") (pin "H1") (pinfunction "IN_H1") (pintype "input"))
      (node (ref "D06") (pin "E1") (pinfunction "IN_E1") (pintype "input"))
      (node (ref "D06") (pin "M2") (pinfunction "M2_M2") (pintype "output"))
    )
    (net (code "569") (name "Net-(D06E-IN)") (class "Default")
      (node (ref "D06") (pin "H1") (pinfunction "IN_H1") (pintype "input"))
      (node (ref "D06") (pin "T2") (pinfunction "T2_T2") (pintype "output"))
      (node (ref "D07") (pin "H1") (pinfunction "IN_H1") (pintype "input"))
    )
    (net (code "570") (name "Net-(D07A-IN)") (class "Default")
      (node (ref "D07") (pin "E1") (pinfunction "IN_E1") (pintype "input"))
      (node (ref "D07") (pin "N2") (pinfunction "N2_N2") (pintype "output"))
    )
    (net (code "571") (name "Net-(D08A-IN)") (class "Default")
      (node (ref "D08") (pin "E1") (pinfunction "IN_E1") (pintype "input"))
      (node (ref "D08") (pin "V2") (pinfunction "V2_V2") (pintype "output"))
    )
    (net (code "572") (name "Net-(D08E-IN)") (class "Default")
      (node (ref "D07") (pin "K2") (pinfunction "K2_K2") (pintype "output"))
      (node (ref "D08") (pin "H1") (pinfunction "IN_H1") (pintype "input"))
    )
    (net (code "573") (name "Net-(D09D-IN3B)") (class "Default")
      (node (ref "D09") (pin "M2") (pinfunction "IN3B_M2") (pintype "input"))
      (node (ref "D09") (pin "V2") (pinfunction "OUT_V2") (pintype "output"))
    )
    (net (code "574") (name "Net-(D10A-S)") (class "Default")
      (node (ref "D10") (pin "D1") (pinfunction "S_D1") (pintype "input"))
      (node (ref "D11") (pin "C1") (pinfunction "OUT_C1") (pintype "output"))
    )
    (net (code "575") (name "Net-(D10D-D)") (class "Default")
      (node (ref "D10") (pin "E2") (pinfunction "D_E2") (pintype "input"))
      (node (ref "D11") (pin "F2") (pinfunction "OUT_F2") (pintype "output"))
    )
    (net (code "576") (name "Net-(D10F-D)") (class "Default")
      (node (ref "D10") (pin "M2") (pinfunction "D_M2") (pintype "input"))
      (node (ref "D11") (pin "N2") (pinfunction "OUT_N2") (pintype "output"))
    )
    (net (code "577") (name "Net-(D11A-IN2)") (class "Default")
      (node (ref "D11") (pin "B1") (pinfunction "IN2_B1") (pintype "input"))
      (node (ref "D11") (pin "F1") (pinfunction "OUT_F1") (pintype "output"))
    )
    (net (code "578") (name "Net-(D11C-IN1)") (class "Default")
      (node (ref "D11") (pin "D2") (pinfunction "IN1_D2") (pintype "input"))
      (node (ref "D11") (pin "K1") (pinfunction "OUT_K1") (pintype "output"))
    )
    (net (code "579") (name "Net-(D11F-IN2)") (class "Default")
      (node (ref "D11") (pin "J1") (pinfunction "IN2_J1") (pintype "input"))
      (node (ref "D11") (pin "K2") (pinfunction "OUT_K2") (pintype "output"))
    )
    (net (code "580") (name "Net-(D12H-OUT)") (class "Default")
      (node (ref "D12") (pin "N1") (pinfunction "OUT_N1") (pintype "output"))
      (node (ref "D13") (pin "C1") (pinfunction "IN_C1") (pintype "input"))
    )
    (net (code "581") (name "Net-(D12I-OUT)") (class "Default")
      (node (ref "D12") (pin "N2") (pinfunction "OUT_N2") (pintype "output"))
      (node (ref "D12") (pin "P1") (pinfunction "IN1_P1") (pintype "input"))
    )
    (net (code "582") (name "Net-(D13D-IN)") (class "Default")
      (node (ref "D13") (pin "E2") (pinfunction "IN_E2") (pintype "input"))
      (node (ref "D29") (pin "K2") (pinfunction "P$1_K2") (pintype "passive"))
      (node (ref "D34") (pin "B1") (pinfunction "P$2_B1") (pintype "bidirectional"))
    )
    (net (code "583") (name "Net-(D13H-IN)") (class "Default")
      (node (ref "D13") (pin "H2") (pinfunction "IN_H2") (pintype "input"))
      (node (ref "D29") (pin "M2") (pinfunction "P$1_M2") (pintype "passive"))
      (node (ref "D34") (pin "D1") (pinfunction "P$2_D1") (pintype "bidirectional"))
    )
    (net (code "584") (name "Net-(D13J-IN)") (class "Default")
      (node (ref "D13") (pin "K2") (pinfunction "IN_K2") (pintype "input"))
      (node (ref "D29") (pin "P2") (pinfunction "P$1_P2") (pintype "passive"))
      (node (ref "D34") (pin "E1") (pinfunction "P$2_E1") (pintype "bidirectional"))
    )
    (net (code "585") (name "Net-(D13L-IN)") (class "Default")
      (node (ref "D13") (pin "M2") (pinfunction "IN_M2") (pintype "input"))
      (node (ref "D29") (pin "S2") (pinfunction "P$1_S2") (pintype "passive"))
      (node (ref "D34") (pin "H1") (pinfunction "P$2_H1") (pintype "bidirectional"))
    )
    (net (code "586") (name "Net-(D14A-IN)") (class "Default")
      (node (ref "D14") (pin "E1") (pinfunction "IN_E1") (pintype "input"))
      (node (ref "D14") (pin "M2") (pinfunction "M2_M2") (pintype "output"))
    )
    (net (code "587") (name "Net-(D14E-IN)") (class "Default")
      (node (ref "D14") (pin "H1") (pinfunction "IN_H1") (pintype "input"))
      (node (ref "D14") (pin "N2") (pinfunction "N2_N2") (pintype "output"))
    )
    (net (code "588") (name "Net-(D15A-IN)") (class "Default")
      (node (ref "D15") (pin "E1") (pinfunction "IN_E1") (pintype "input"))
      (node (ref "D15") (pin "T2") (pinfunction "T2_T2") (pintype "output"))
    )
    (net (code "589") (name "Net-(D15E-IN)") (class "Default")
      (node (ref "D15") (pin "H1") (pinfunction "IN_H1") (pintype "input"))
      (node (ref "D15") (pin "L2") (pinfunction "L2_L2") (pintype "output"))
    )
    (net (code "590") (name "Net-(D16A-0)") (class "Default")
      (node (ref "D16") (pin "F1") (pinfunction "0_F1") (pintype "output"))
      (node (ref "D17") (pin "A1") (pinfunction "IN1_A1") (pintype "input"))
      (node (ref "D17") (pin "B1") (pinfunction "IN2_B1") (pintype "input"))
      (node (ref "D17") (pin "C1") (pinfunction "IN3_C1") (pintype "input"))
      (node (ref "D17") (pin "D1") (pinfunction "IN4_D1") (pintype "input"))
      (node (ref "D17") (pin "F1") (pinfunction "IN1_F1") (pintype "input"))
      (node (ref "D17") (pin "H1") (pinfunction "IN2_H1") (pintype "input"))
      (node (ref "D17") (pin "J1") (pinfunction "IN3_J1") (pintype "input"))
      (node (ref "D17") (pin "K1") (pinfunction "IN4_K1") (pintype "input"))
    )
    (net (code "591") (name "Net-(D20C-P$2)") (class "Default")
      (node (ref "D18") (pin "R2") (pinfunction "R2_R2") (pintype "passive"))
      (node (ref "D20") (pin "C2") (pinfunction "P$2_C2") (pintype "bidirectional"))
    )
    (net (code "592") (name "Net-(D20D-P$2)") (class "Default")
      (node (ref "D18") (pin "S2") (pinfunction "S2_S2") (pintype "passive"))
      (node (ref "D20") (pin "D2") (pinfunction "P$2_D2") (pintype "bidirectional"))
    )
    (net (code "593") (name "Net-(D20E-P$2)") (class "Default")
      (node (ref "D18") (pin "N2") (pinfunction "N2_N2") (pintype "passive"))
      (node (ref "D20") (pin "E2") (pinfunction "P$2_E2") (pintype "bidirectional"))
    )
    (net (code "594") (name "Net-(D20F-P$2)") (class "Default")
      (node (ref "D18") (pin "P2") (pinfunction "P2_P2") (pintype "passive"))
      (node (ref "D20") (pin "F2") (pinfunction "P$2_F2") (pintype "bidirectional"))
    )
    (net (code "595") (name "Net-(D20G-P$2)") (class "Default")
      (node (ref "D18") (pin "L2") (pinfunction "L2_L2") (pintype "passive"))
      (node (ref "D20") (pin "H2") (pinfunction "P$2_H2") (pintype "bidirectional"))
    )
    (net (code "596") (name "Net-(D20H-P$2)") (class "Default")
      (node (ref "D18") (pin "M2") (pinfunction "M2_M2") (pintype "passive"))
      (node (ref "D20") (pin "J2") (pinfunction "P$2_J2") (pintype "bidirectional"))
    )
    (net (code "597") (name "Net-(D20I-P$2)") (class "Default")
      (node (ref "D18") (pin "J2") (pinfunction "J2_J2") (pintype "passive"))
      (node (ref "D20") (pin "K2") (pinfunction "P$2_K2") (pintype "bidirectional"))
    )
    (net (code "598") (name "Net-(D20J-P$2)") (class "Default")
      (node (ref "D18") (pin "K2") (pinfunction "K2_K2") (pintype "passive"))
      (node (ref "D20") (pin "L2") (pinfunction "P$2_L2") (pintype "bidirectional"))
    )
    (net (code "599") (name "Net-(D20K-P$2)") (class "Default")
      (node (ref "D19") (pin "R2") (pinfunction "R2_R2") (pintype "passive"))
      (node (ref "D20") (pin "M2") (pinfunction "P$2_M2") (pintype "bidirectional"))
    )
    (net (code "600") (name "Net-(D20L-P$2)") (class "Default")
      (node (ref "D19") (pin "S2") (pinfunction "S2_S2") (pintype "passive"))
      (node (ref "D20") (pin "N2") (pinfunction "P$2_N2") (pintype "bidirectional"))
    )
    (net (code "601") (name "Net-(D20M-P$2)") (class "Default")
      (node (ref "D19") (pin "N2") (pinfunction "N2_N2") (pintype "passive"))
      (node (ref "D20") (pin "P2") (pinfunction "P$2_P2") (pintype "bidirectional"))
    )
    (net (code "602") (name "Net-(D20N-P$2)") (class "Default")
      (node (ref "D19") (pin "P2") (pinfunction "P2_P2") (pintype "passive"))
      (node (ref "D20") (pin "R2") (pinfunction "P$2_R2") (pintype "bidirectional"))
    )
    (net (code "603") (name "Net-(D20O-P$2)") (class "Default")
      (node (ref "D19") (pin "L2") (pinfunction "L2_L2") (pintype "passive"))
      (node (ref "D20") (pin "S2") (pinfunction "P$2_S2") (pintype "bidirectional"))
    )
    (net (code "604") (name "Net-(D20P-P$2)") (class "Default")
      (node (ref "D19") (pin "M2") (pinfunction "M2_M2") (pintype "passive"))
      (node (ref "D20") (pin "T2") (pinfunction "P$2_T2") (pintype "bidirectional"))
    )
    (net (code "605") (name "Net-(D20Q-P$2)") (class "Default")
      (node (ref "D19") (pin "J2") (pinfunction "J2_J2") (pintype "passive"))
      (node (ref "D20") (pin "U2") (pinfunction "P$2_U2") (pintype "bidirectional"))
    )
    (net (code "606") (name "Net-(D20R-P$2)") (class "Default")
      (node (ref "D19") (pin "K2") (pinfunction "K2_K2") (pintype "passive"))
      (node (ref "D20") (pin "V2") (pinfunction "P$2_V2") (pintype "bidirectional"))
    )
    (net (code "607") (name "Net-(D22C-P$2)") (class "Default")
      (node (ref "D22") (pin "C2") (pinfunction "P$2_C2") (pintype "bidirectional"))
      (node (ref "D23") (pin "R2") (pinfunction "R2_R2") (pintype "passive"))
    )
    (net (code "608") (name "Net-(D22D-P$2)") (class "Default")
      (node (ref "D22") (pin "D2") (pinfunction "P$2_D2") (pintype "bidirectional"))
      (node (ref "D23") (pin "S2") (pinfunction "S2_S2") (pintype "passive"))
    )
    (net (code "609") (name "Net-(D22E-P$2)") (class "Default")
      (node (ref "D22") (pin "E2") (pinfunction "P$2_E2") (pintype "bidirectional"))
      (node (ref "D23") (pin "N2") (pinfunction "N2_N2") (pintype "passive"))
    )
    (net (code "610") (name "Net-(D22F-P$2)") (class "Default")
      (node (ref "D22") (pin "F2") (pinfunction "P$2_F2") (pintype "bidirectional"))
      (node (ref "D23") (pin "P2") (pinfunction "P2_P2") (pintype "passive"))
    )
    (net (code "611") (name "Net-(D22G-P$2)") (class "Default")
      (node (ref "D22") (pin "H2") (pinfunction "P$2_H2") (pintype "bidirectional"))
      (node (ref "D23") (pin "L2") (pinfunction "L2_L2") (pintype "passive"))
    )
    (net (code "612") (name "Net-(D22H-P$2)") (class "Default")
      (node (ref "D22") (pin "J2") (pinfunction "P$2_J2") (pintype "bidirectional"))
      (node (ref "D23") (pin "M2") (pinfunction "M2_M2") (pintype "passive"))
    )
    (net (code "613") (name "Net-(D22I-P$2)") (class "Default")
      (node (ref "D22") (pin "K2") (pinfunction "P$2_K2") (pintype "bidirectional"))
      (node (ref "D23") (pin "J2") (pinfunction "J2_J2") (pintype "passive"))
    )
    (net (code "614") (name "Net-(D22J-P$2)") (class "Default")
      (node (ref "D22") (pin "L2") (pinfunction "P$2_L2") (pintype "bidirectional"))
      (node (ref "D23") (pin "K2") (pinfunction "K2_K2") (pintype "passive"))
    )
    (net (code "615") (name "Net-(D22K-P$2)") (class "Default")
      (node (ref "D22") (pin "M2") (pinfunction "P$2_M2") (pintype "bidirectional"))
      (node (ref "D24") (pin "R2") (pinfunction "R2_R2") (pintype "passive"))
    )
    (net (code "616") (name "Net-(D22L-P$2)") (class "Default")
      (node (ref "D22") (pin "N2") (pinfunction "P$2_N2") (pintype "bidirectional"))
      (node (ref "D24") (pin "S2") (pinfunction "S2_S2") (pintype "passive"))
    )
    (net (code "617") (name "Net-(D22M-P$2)") (class "Default")
      (node (ref "D22") (pin "P2") (pinfunction "P$2_P2") (pintype "bidirectional"))
      (node (ref "D24") (pin "N2") (pinfunction "N2_N2") (pintype "passive"))
    )
    (net (code "618") (name "Net-(D22N-P$2)") (class "Default")
      (node (ref "D22") (pin "R2") (pinfunction "P$2_R2") (pintype "bidirectional"))
      (node (ref "D24") (pin "P2") (pinfunction "P2_P2") (pintype "passive"))
    )
    (net (code "619") (name "Net-(D22O-P$2)") (class "Default")
      (node (ref "D22") (pin "S2") (pinfunction "P$2_S2") (pintype "bidirectional"))
      (node (ref "D24") (pin "L2") (pinfunction "L2_L2") (pintype "passive"))
    )
    (net (code "620") (name "Net-(D22P-P$2)") (class "Default")
      (node (ref "D22") (pin "T2") (pinfunction "P$2_T2") (pintype "bidirectional"))
      (node (ref "D24") (pin "M2") (pinfunction "M2_M2") (pintype "passive"))
    )
    (net (code "621") (name "Net-(D22Q-P$2)") (class "Default")
      (node (ref "D22") (pin "U2") (pinfunction "P$2_U2") (pintype "bidirectional"))
      (node (ref "D24") (pin "J2") (pinfunction "J2_J2") (pintype "passive"))
    )
    (net (code "622") (name "Net-(D22R-P$2)") (class "Default")
      (node (ref "D22") (pin "V2") (pinfunction "P$2_V2") (pintype "bidirectional"))
      (node (ref "D24") (pin "K2") (pinfunction "K2_K2") (pintype "passive"))
    )
    (net (code "623") (name "Net-(D27A-D)") (class "Default")
      (node (ref "D27") (pin "D1") (pinfunction "D_D1") (pintype "open_collector"))
      (node (ref "D29") (pin "B1") (pinfunction "P$1_B1") (pintype "passive"))
      (node (ref "D36") (pin "B1") (pinfunction "P$2_B1") (pintype "bidirectional"))
    )
    (net (code "624") (name "Net-(D27A-E)") (class "Default")
      (node (ref "D27") (pin "E1") (pinfunction "E_E1") (pintype "open_collector"))
      (node (ref "D29") (pin "D1") (pinfunction "P$1_D1") (pintype "passive"))
      (node (ref "D36") (pin "D1") (pinfunction "P$2_D1") (pintype "bidirectional"))
    )
    (net (code "625") (name "Net-(D27F-D)") (class "Default")
      (node (ref "D27") (pin "H2") (pinfunction "D_H2") (pintype "open_collector"))
      (node (ref "D29") (pin "M1") (pinfunction "P$1_M1") (pintype "passive"))
      (node (ref "D36") (pin "M1") (pinfunction "P$2_M1") (pintype "bidirectional"))
    )
    (net (code "626") (name "Net-(D27F-E)") (class "Default")
      (node (ref "D27") (pin "J2") (pinfunction "E_J2") (pintype "open_collector"))
      (node (ref "D29") (pin "P1") (pinfunction "P$1_P1") (pintype "passive"))
      (node (ref "D36") (pin "P1") (pinfunction "P$2_P1") (pintype "bidirectional"))
    )
    (net (code "627") (name "Net-(D27G-D)") (class "Default")
      (node (ref "D27") (pin "K1") (pinfunction "D_K1") (pintype "open_collector"))
      (node (ref "D29") (pin "E1") (pinfunction "P$1_E1") (pintype "passive"))
      (node (ref "D36") (pin "E1") (pinfunction "P$2_E1") (pintype "bidirectional"))
    )
    (net (code "628") (name "Net-(D27G-E)") (class "Default")
      (node (ref "D27") (pin "L1") (pinfunction "E_L1") (pintype "open_collector"))
      (node (ref "D29") (pin "H1") (pinfunction "P$1_H1") (pintype "passive"))
      (node (ref "D36") (pin "H1") (pinfunction "P$2_H1") (pintype "bidirectional"))
    )
    (net (code "629") (name "Net-(D27H-D)") (class "Default")
      (node (ref "D27") (pin "N2") (pinfunction "D_N2") (pintype "open_collector"))
      (node (ref "D29") (pin "S1") (pinfunction "P$1_S1") (pintype "passive"))
      (node (ref "D36") (pin "S1") (pinfunction "P$2_S1") (pintype "bidirectional"))
    )
    (net (code "630") (name "Net-(D27H-E)") (class "Default")
      (node (ref "D27") (pin "P2") (pinfunction "E_P2") (pintype "open_collector"))
      (node (ref "D29") (pin "D2") (pinfunction "P$1_D2") (pintype "passive"))
      (node (ref "D36") (pin "D2") (pinfunction "P$2_D2") (pintype "bidirectional"))
    )
    (net (code "631") (name "Net-(D27I-D)") (class "Default")
      (node (ref "D27") (pin "R1") (pinfunction "D_R1") (pintype "open_collector"))
      (node (ref "D29") (pin "J1") (pinfunction "P$1_J1") (pintype "passive"))
      (node (ref "D36") (pin "J1") (pinfunction "P$2_J1") (pintype "bidirectional"))
    )
    (net (code "632") (name "Net-(D27I-E)") (class "Default")
      (node (ref "D27") (pin "S1") (pinfunction "E_S1") (pintype "open_collector"))
      (node (ref "D29") (pin "L1") (pinfunction "P$1_L1") (pintype "passive"))
      (node (ref "D36") (pin "L1") (pinfunction "P$2_L1") (pintype "bidirectional"))
    )
    (net (code "633") (name "Net-(D27J-D)") (class "Default")
      (node (ref "D27") (pin "U2") (pinfunction "D_U2") (pintype "open_collector"))
      (node (ref "D29") (pin "E2") (pinfunction "P$1_E2") (pintype "passive"))
      (node (ref "D36") (pin "E2") (pinfunction "P$2_E2") (pintype "bidirectional"))
    )
    (net (code "634") (name "Net-(D27J-E)") (class "Default")
      (node (ref "D27") (pin "V2") (pinfunction "E_V2") (pintype "open_collector"))
      (node (ref "D29") (pin "H2") (pinfunction "P$1_H2") (pintype "passive"))
      (node (ref "D36") (pin "H2") (pinfunction "P$2_H2") (pintype "bidirectional"))
    )
    (net (code "635") (name "Net-(D28A-D)") (class "Default")
      (node (ref "D28") (pin "D1") (pinfunction "D_D1") (pintype "open_collector"))
      (node (ref "D30") (pin "B1") (pinfunction "P$1_B1") (pintype "passive"))
      (node (ref "D35") (pin "B1") (pinfunction "P$2_B1") (pintype "bidirectional"))
    )
    (net (code "636") (name "Net-(D28A-E)") (class "Default")
      (node (ref "D28") (pin "E1") (pinfunction "E_E1") (pintype "open_collector"))
      (node (ref "D30") (pin "D1") (pinfunction "P$1_D1") (pintype "passive"))
      (node (ref "D35") (pin "D1") (pinfunction "P$2_D1") (pintype "bidirectional"))
    )
    (net (code "637") (name "Net-(D28F-D)") (class "Default")
      (node (ref "D28") (pin "H2") (pinfunction "D_H2") (pintype "open_collector"))
      (node (ref "D30") (pin "M1") (pinfunction "P$1_M1") (pintype "passive"))
      (node (ref "D35") (pin "M1") (pinfunction "P$2_M1") (pintype "bidirectional"))
    )
    (net (code "638") (name "Net-(D28F-E)") (class "Default")
      (node (ref "D28") (pin "J2") (pinfunction "E_J2") (pintype "open_collector"))
      (node (ref "D30") (pin "P1") (pinfunction "P$1_P1") (pintype "passive"))
      (node (ref "D35") (pin "P1") (pinfunction "P$2_P1") (pintype "bidirectional"))
    )
    (net (code "639") (name "Net-(D28G-D)") (class "Default")
      (node (ref "D28") (pin "K1") (pinfunction "D_K1") (pintype "open_collector"))
      (node (ref "D30") (pin "E1") (pinfunction "P$1_E1") (pintype "passive"))
      (node (ref "D35") (pin "E1") (pinfunction "P$2_E1") (pintype "bidirectional"))
    )
    (net (code "640") (name "Net-(D28G-E)") (class "Default")
      (node (ref "D28") (pin "L1") (pinfunction "E_L1") (pintype "open_collector"))
      (node (ref "D30") (pin "H1") (pinfunction "P$1_H1") (pintype "passive"))
      (node (ref "D35") (pin "H1") (pinfunction "P$2_H1") (pintype "bidirectional"))
    )
    (net (code "641") (name "Net-(D28H-D)") (class "Default")
      (node (ref "D28") (pin "N2") (pinfunction "D_N2") (pintype "open_collector"))
      (node (ref "D30") (pin "S1") (pinfunction "P$1_S1") (pintype "passive"))
      (node (ref "D35") (pin "S1") (pinfunction "P$2_S1") (pintype "bidirectional"))
    )
    (net (code "642") (name "Net-(D28H-E)") (class "Default")
      (node (ref "D28") (pin "P2") (pinfunction "E_P2") (pintype "open_collector"))
      (node (ref "D30") (pin "D2") (pinfunction "P$1_D2") (pintype "passive"))
      (node (ref "D35") (pin "D2") (pinfunction "P$2_D2") (pintype "bidirectional"))
    )
    (net (code "643") (name "Net-(D28I-D)") (class "Default")
      (node (ref "D28") (pin "R1") (pinfunction "D_R1") (pintype "open_collector"))
      (node (ref "D30") (pin "J1") (pinfunction "P$1_J1") (pintype "passive"))
      (node (ref "D35") (pin "J1") (pinfunction "P$2_J1") (pintype "bidirectional"))
    )
    (net (code "644") (name "Net-(D28I-E)") (class "Default")
      (node (ref "D28") (pin "S1") (pinfunction "E_S1") (pintype "open_collector"))
      (node (ref "D30") (pin "L1") (pinfunction "P$1_L1") (pintype "passive"))
      (node (ref "D35") (pin "L1") (pinfunction "P$2_L1") (pintype "bidirectional"))
    )
    (net (code "645") (name "Net-(D28J-D)") (class "Default")
      (node (ref "D28") (pin "U2") (pinfunction "D_U2") (pintype "open_collector"))
      (node (ref "D30") (pin "E2") (pinfunction "P$1_E2") (pintype "passive"))
      (node (ref "D35") (pin "E2") (pinfunction "P$2_E2") (pintype "bidirectional"))
    )
    (net (code "646") (name "Net-(D28J-E)") (class "Default")
      (node (ref "D28") (pin "V2") (pinfunction "E_V2") (pintype "open_collector"))
      (node (ref "D30") (pin "H2") (pinfunction "P$1_H2") (pintype "passive"))
      (node (ref "D35") (pin "H2") (pinfunction "P$2_H2") (pintype "bidirectional"))
    )
    (net (code "647") (name "OP1") (class "Default")
      (node (ref "A09") (pin "C1") (pinfunction "IN3_C1") (pintype "input"))
      (node (ref "A09") (pin "D1") (pinfunction "IN4_D1") (pintype "input"))
      (node (ref "A11") (pin "B1") (pinfunction "IN2_B1") (pintype "input"))
      (node (ref "A11") (pin "E2") (pinfunction "IN2_E2") (pintype "input"))
      (node (ref "A11") (pin "F1") (pinfunction "IN2_F1") (pintype "input"))
      (node (ref "A11") (pin "K2") (pinfunction "IN2_K2") (pintype "input"))
      (node (ref "A11") (pin "L1") (pinfunction "IN2_L1") (pintype "input"))
      (node (ref "A12") (pin "H1") (pinfunction "IN3A_H1") (pintype "input"))
      (node (ref "A12") (pin "U1") (pinfunction "IN1B_U1") (pintype "input"))
      (node (ref "B13") (pin "H1") (pinfunction "IN1_H1") (pintype "input"))
      (node (ref "B13") (pin "H2") (pinfunction "IN1_H2") (pintype "input"))
      (node (ref "C07") (pin "F2") (pinfunction "OUT_F2") (pintype "output"))
      (node (ref "D09") (pin "L2") (pinfunction "IN3A_L2") (pintype "input"))
    )
    (net (code "648") (name "OP2") (class "Default")
      (node (ref "A13") (pin "P2") (pinfunction "IN4B_P2") (pintype "input"))
      (node (ref "C07") (pin "J2") (pinfunction "OUT_J2") (pintype "output"))
      (node (ref "C12") (pin "D2") (pinfunction "IN1_D2") (pintype "input"))
      (node (ref "C14") (pin "J2") (pinfunction "IN2_J2") (pintype "input"))
      (node (ref "D09") (pin "C1") (pinfunction "IN1C_C1") (pintype "input"))
      (node (ref "D09") (pin "F2") (pinfunction "IN1C_F2") (pintype "input"))
    )
    (net (code "649") (name "PANEL_LOCK") (class "Default")
      (node (ref "A28") (pin "T2") (pinfunction "P$2_T2") (pintype "bidirectional"))
      (node (ref "B01") (pin "N2") (pinfunction "P$2_N2") (pintype "bidirectional"))
    )
    (net (code "650") (name "PAUSE") (class "Default")
      (node (ref "C04") (pin "L1") (pinfunction "1_L1") (pintype "output"))
      (node (ref "C28") (pin "A1") (pinfunction "IN1_A1") (pintype "input"))
    )
    (net (code "651") (name "PC00") (class "Default")
      (node (ref "AB07") (pin "AP1") (pinfunction "AP1_AP1") (pintype "output"))
      (node (ref "B01") (pin "C1") (pinfunction "P$2_C1") (pintype "bidirectional"))
    )
    (net (code "652") (name "PC01") (class "Default")
      (node (ref "AB07") (pin "AN1") (pinfunction "AN1_AN1") (pintype "output"))
      (node (ref "B01") (pin "D1") (pinfunction "P$2_D1") (pintype "bidirectional"))
    )
    (net (code "653") (name "PC02") (class "Default")
      (node (ref "AB06") (pin "AP1") (pinfunction "AP1_AP1") (pintype "output"))
      (node (ref "B01") (pin "E1") (pinfunction "P$2_E1") (pintype "bidirectional"))
    )
    (net (code "654") (name "PC03") (class "Default")
      (node (ref "AB06") (pin "AN1") (pinfunction "AN1_AN1") (pintype "output"))
      (node (ref "B01") (pin "F1") (pinfunction "P$2_F1") (pintype "bidirectional"))
    )
    (net (code "655") (name "PC04") (class "Default")
      (node (ref "AB05") (pin "AP1") (pinfunction "AP1_AP1") (pintype "output"))
      (node (ref "B01") (pin "H1") (pinfunction "P$2_H1") (pintype "bidirectional"))
    )
    (net (code "656") (name "PC05") (class "Default")
      (node (ref "AB05") (pin "AN1") (pinfunction "AN1_AN1") (pintype "output"))
      (node (ref "B01") (pin "J1") (pinfunction "P$2_J1") (pintype "bidirectional"))
    )
    (net (code "657") (name "PC06") (class "Default")
      (node (ref "AB04") (pin "AP1") (pinfunction "AP1_AP1") (pintype "output"))
      (node (ref "D01") (pin "C1") (pinfunction "P$2_C1") (pintype "bidirectional"))
    )
    (net (code "658") (name "PC07") (class "Default")
      (node (ref "AB04") (pin "AN1") (pinfunction "AN1_AN1") (pintype "output"))
      (node (ref "D01") (pin "D1") (pinfunction "P$2_D1") (pintype "bidirectional"))
    )
    (net (code "659") (name "PC08") (class "Default")
      (node (ref "AB03") (pin "AP1") (pinfunction "AP1_AP1") (pintype "output"))
      (node (ref "D01") (pin "E1") (pinfunction "P$2_E1") (pintype "bidirectional"))
    )
    (net (code "660") (name "PC09") (class "Default")
      (node (ref "AB03") (pin "AN1") (pinfunction "AN1_AN1") (pintype "output"))
      (node (ref "D01") (pin "F1") (pinfunction "P$2_F1") (pintype "bidirectional"))
    )
    (net (code "661") (name "PC10") (class "Default")
      (node (ref "AB02") (pin "AP1") (pinfunction "AP1_AP1") (pintype "output"))
      (node (ref "D01") (pin "H1") (pinfunction "P$2_H1") (pintype "bidirectional"))
    )
    (net (code "662") (name "PC11") (class "Default")
      (node (ref "AB02") (pin "AN1") (pinfunction "AN1_AN1") (pintype "output"))
      (node (ref "D01") (pin "J1") (pinfunction "P$2_J1") (pintype "bidirectional"))
    )
    (net (code "663") (name "PC_ENABLE") (class "Default")
      (node (ref "A08") (pin "V2") (pinfunction "OUT_V2") (pintype "open_collector"))
      (node (ref "AB02") (pin "BS2") (pinfunction "BS2_BS2") (pintype "input"))
      (node (ref "AB03") (pin "BS2") (pinfunction "BS2_BS2") (pintype "input"))
      (node (ref "AB04") (pin "BS2") (pinfunction "BS2_BS2") (pintype "input"))
      (node (ref "AB05") (pin "BS2") (pinfunction "BS2_BS2") (pintype "input"))
      (node (ref "AB06") (pin "BS2") (pinfunction "BS2_BS2") (pintype "input"))
      (node (ref "AB07") (pin "BS2") (pinfunction "BS2_BS2") (pintype "input"))
    )
    (net (code "664") (name "PC_LOAD") (class "Default")
      (node (ref "AB02") (pin "AN2") (pinfunction "AN2_AN2") (pintype "input"))
      (node (ref "AB03") (pin "AN2") (pinfunction "AN2_AN2") (pintype "input"))
      (node (ref "AB04") (pin "AN2") (pinfunction "AN2_AN2") (pintype "input"))
      (node (ref "AB05") (pin "AN2") (pinfunction "AN2_AN2") (pintype "input"))
      (node (ref "AB06") (pin "AN2") (pinfunction "AN2_AN2") (pintype "input"))
      (node (ref "AB07") (pin "AN2") (pinfunction "AN2_AN2") (pintype "input"))
      (node (ref "B08") (pin "J2") (pinfunction "OUT_J2") (pintype "open_collector"))
      (node (ref "C14") (pin "H1") (pinfunction "IN1_H1") (pintype "input"))
      (node (ref "C14") (pin "J1") (pinfunction "IN2_J1") (pintype "input"))
    )
    (net (code "665") (name "PWR") (class "Default")
      (node (ref "AB30") (pin "BR2") (pinfunction "BR2_BR2") (pintype "output"))
      (node (ref "C34") (pin "U2") (pinfunction "P$2_U2") (pintype "bidirectional"))
    )
    (net (code "666") (name "RDR_FEED_SW") (class "Default")
      (node (ref "AB29") (pin "BP2") (pinfunction "BP_BP2") (pintype "input"))
      (node (ref "AB30") (pin "BM1") (pinfunction "BM1_BM1") (pintype "input"))
      (node (ref "C34") (pin "V2") (pinfunction "P$2_V2") (pintype "bidirectional"))
    )
    (net (code "667") (name "RD_HOLE1") (class "Default")
      (node (ref "AB30") (pin "AD2") (pinfunction "AD2_AD2") (pintype "input"))
      (node (ref "C34") (pin "D2") (pinfunction "P$2_D2") (pintype "bidirectional"))
    )
    (net (code "668") (name "RD_HOLE2") (class "Default")
      (node (ref "AB30") (pin "AD1") (pinfunction "AD1_AD1") (pintype "input"))
      (node (ref "C34") (pin "E2") (pinfunction "P$2_E2") (pintype "bidirectional"))
    )
    (net (code "669") (name "RD_HOLE3") (class "Default")
      (node (ref "AB30") (pin "AE2") (pinfunction "AE2_AE2") (pintype "input"))
      (node (ref "C34") (pin "F2") (pinfunction "P$2_F2") (pintype "bidirectional"))
    )
    (net (code "670") (name "RD_HOLE4") (class "Default")
      (node (ref "AB30") (pin "AE1") (pinfunction "AE1_AE1") (pintype "input"))
      (node (ref "C34") (pin "H2") (pinfunction "P$2_H2") (pintype "bidirectional"))
    )
    (net (code "671") (name "RD_HOLE5") (class "Default")
      (node (ref "AB30") (pin "AH2") (pinfunction "AH2_AH2") (pintype "input"))
      (node (ref "C34") (pin "J2") (pinfunction "P$2_J2") (pintype "bidirectional"))
    )
    (net (code "672") (name "RD_HOLE6") (class "Default")
      (node (ref "AB30") (pin "AH1") (pinfunction "AH1_AH1") (pintype "input"))
      (node (ref "C34") (pin "K2") (pinfunction "P$2_K2") (pintype "bidirectional"))
    )
    (net (code "673") (name "RD_HOLE7") (class "Default")
      (node (ref "AB30") (pin "AF2") (pinfunction "AF2_AF2") (pintype "input"))
      (node (ref "C34") (pin "L2") (pinfunction "P$2_L2") (pintype "bidirectional"))
    )
    (net (code "674") (name "RD_HOLE8") (class "Default")
      (node (ref "AB30") (pin "AF1") (pinfunction "AF1_AF1") (pintype "input"))
      (node (ref "C34") (pin "M2") (pinfunction "P$2_M2") (pintype "bidirectional"))
    )
    (net (code "675") (name "READ") (class "Default")
      (node (ref "C17") (pin "R2") (pinfunction "R_R2") (pintype "input"))
      (node (ref "C25") (pin "D2") (pinfunction "D2_D2") (pintype "input"))
      (node (ref "C25") (pin "M2") (pinfunction "M2_M2") (pintype "input"))
      (node (ref "D16") (pin "L1") (pinfunction "1_L1") (pintype "output"))
      (node (ref "D25") (pin "D1") (pinfunction "D1_D1") (pintype "input"))
      (node (ref "D25") (pin "L1") (pinfunction "L1_L1") (pintype "input"))
    )
    (net (code "676") (name "READER_RUN") (class "Default")
      (node (ref "C32") (pin "U2") (pinfunction "P$2_U2") (pintype "bidirectional"))
      (node (ref "D33") (pin "M2") (pinfunction "P$2_M2") (pintype "bidirectional"))
    )
    (net (code "677") (name "RIGHT_SHIFT") (class "Default")
      (node (ref "AB02") (pin "AD2") (pinfunction "AD2_AD2") (pintype "input"))
      (node (ref "AB03") (pin "AD2") (pinfunction "AD2_AD2") (pintype "input"))
      (node (ref "AB04") (pin "AD2") (pinfunction "AD2_AD2") (pintype "input"))
      (node (ref "AB05") (pin "AD2") (pinfunction "AD2_AD2") (pintype "input"))
      (node (ref "AB06") (pin "AD2") (pinfunction "AD2_AD2") (pintype "input"))
      (node (ref "AB07") (pin "AD2") (pinfunction "AD2_AD2") (pintype "input"))
      (node (ref "B09") (pin "S1") (pinfunction "OUT_S1") (pintype "open_collector"))
      (node (ref "B10") (pin "D1") (pinfunction "IN1D_D1") (pintype "input"))
    )
    (net (code "678") (name "RUN") (class "Default")
      (node (ref "C06") (pin "U1") (pinfunction "0_U1") (pintype "output"))
      (node (ref "D04") (pin "C1") (pinfunction "IN3_C1") (pintype "input"))
    )
    (net (code "679") (name "RXD") (class "Default")
      (node (ref "D32") (pin "M2") (pinfunction "P$2_M2") (pintype "bidirectional"))
      (node (ref "D33") (pin "E2") (pinfunction "P$2_E2") (pintype "bidirectional"))
    )
    (net (code "680") (name "SHIFT") (class "Default")
      (node (ref "AB29") (pin "AS2") (pinfunction "AS_AS2") (pintype "output"))
      (node (ref "AB30") (pin "BJ1") (pinfunction "BJ1_BJ1") (pintype "input"))
    )
    (net (code "681") (name "SKIP") (class "Default")
      (node (ref "A12") (pin "L1") (pinfunction "IN4B_L1") (pintype "input"))
      (node (ref "B11") (pin "U1") (pinfunction "0_U1") (pintype "output"))
    )
    (net (code "682") (name "SLICE") (class "Default")
      (node (ref "A17") (pin "S2") (pinfunction "S2_S2") (pintype "passive"))
      (node (ref "A18") (pin "S2") (pinfunction "S2_S2") (pintype "passive"))
      (node (ref "A19") (pin "S2") (pinfunction "S2_S2") (pintype "passive"))
      (node (ref "A20") (pin "S2") (pinfunction "S2_S2") (pintype "passive"))
      (node (ref "A28") (pin "V2") (pinfunction "P$2_V2") (pintype "bidirectional"))
      (node (ref "B18") (pin "S2") (pinfunction "S2_S2") (pintype "passive"))
      (node (ref "B19") (pin "S2") (pinfunction "S2_S2") (pintype "passive"))
      (node (ref "B20") (pin "S2") (pinfunction "S2_S2") (pintype "passive"))
    )
    (net (code "683") (name "SPIKE_DETECT") (class "Default")
      (node (ref "C32") (pin "M2") (pinfunction "P$2_M2") (pintype "bidirectional"))
      (node (ref "C32") (pin "R1") (pinfunction "P$2_R1") (pintype "bidirectional"))
    )
    (net (code "684") (name "SR00") (class "Default")
      (node (ref "A01") (pin "H2") (pinfunction "P$2_H2") (pintype "bidirectional"))
      (node (ref "AB07") (pin "BE1") (pinfunction "BE1_BE1") (pintype "input"))
    )
    (net (code "685") (name "SR01") (class "Default")
      (node (ref "A01") (pin "F2") (pinfunction "P$2_F2") (pintype "bidirectional"))
      (node (ref "AB07") (pin "BD2") (pinfunction "BD2_BD2") (pintype "input"))
    )
    (net (code "686") (name "SR02") (class "Default")
      (node (ref "A01") (pin "E2") (pinfunction "P$2_E2") (pintype "bidirectional"))
      (node (ref "AB06") (pin "BE1") (pinfunction "BE1_BE1") (pintype "input"))
    )
    (net (code "687") (name "SR03") (class "Default")
      (node (ref "A01") (pin "D2") (pinfunction "P$2_D2") (pintype "bidirectional"))
      (node (ref "AB06") (pin "BD2") (pinfunction "BD2_BD2") (pintype "input"))
    )
    (net (code "688") (name "SR04") (class "Default")
      (node (ref "A01") (pin "D1") (pinfunction "P$2_D1") (pintype "bidirectional"))
      (node (ref "AB05") (pin "BE1") (pinfunction "BE1_BE1") (pintype "input"))
    )
    (net (code "689") (name "SR05") (class "Default")
      (node (ref "AB05") (pin "BD2") (pinfunction "BD2_BD2") (pintype "input"))
      (node (ref "C01") (pin "L2") (pinfunction "P$2_L2") (pintype "bidirectional"))
    )
    (net (code "690") (name "SR06") (class "Default")
      (node (ref "AB04") (pin "BE1") (pinfunction "BE1_BE1") (pintype "input"))
      (node (ref "C01") (pin "K2") (pinfunction "P$2_K2") (pintype "bidirectional"))
    )
    (net (code "691") (name "SR07") (class "Default")
      (node (ref "AB04") (pin "BD2") (pinfunction "BD2_BD2") (pintype "input"))
      (node (ref "C01") (pin "J2") (pinfunction "P$2_J2") (pintype "bidirectional"))
    )
    (net (code "692") (name "SR08") (class "Default")
      (node (ref "AB03") (pin "BE1") (pinfunction "BE1_BE1") (pintype "input"))
      (node (ref "C01") (pin "H2") (pinfunction "P$2_H2") (pintype "bidirectional"))
    )
    (net (code "693") (name "SR09") (class "Default")
      (node (ref "AB03") (pin "BD2") (pinfunction "BD2_BD2") (pintype "input"))
      (node (ref "C01") (pin "E2") (pinfunction "P$2_E2") (pintype "bidirectional"))
    )
    (net (code "694") (name "SR10") (class "Default")
      (node (ref "AB02") (pin "BE1") (pinfunction "BE1_BE1") (pintype "input"))
      (node (ref "C01") (pin "F2") (pinfunction "P$2_F2") (pintype "bidirectional"))
    )
    (net (code "695") (name "SR11") (class "Default")
      (node (ref "AB02") (pin "BD2") (pinfunction "BD2_BD2") (pintype "input"))
      (node (ref "D01") (pin "M2") (pinfunction "P$2_M2") (pintype "bidirectional"))
    )
    (net (code "696") (name "SR_ENABLE") (class "Default")
      (node (ref "A08") (pin "E1") (pinfunction "OUT_E1") (pintype "open_collector"))
      (node (ref "AB02") (pin "BC1") (pinfunction "BC1_BC1") (pintype "input"))
      (node (ref "AB03") (pin "BC1") (pinfunction "BC1_BC1") (pintype "input"))
      (node (ref "AB04") (pin "BC1") (pinfunction "BC1_BC1") (pintype "input"))
      (node (ref "AB05") (pin "BC1") (pinfunction "BC1_BC1") (pintype "input"))
      (node (ref "AB06") (pin "BC1") (pinfunction "BC1_BC1") (pintype "input"))
      (node (ref "AB07") (pin "BC1") (pinfunction "BC1_BC1") (pintype "input"))
    )
    (net (code "697") (name "STOP_COMPLETE") (class "Default")
      (node (ref "AB29") (pin "BR2") (pinfunction "BR_BR2") (pintype "output"))
      (node (ref "AB30") (pin "BN2") (pinfunction "BN2_BN2") (pintype "input"))
    )
    (net (code "698") (name "STOP_OK") (class "Default")
      (node (ref "A27") (pin "H2") (pinfunction "P$2_H2") (pintype "bidirectional"))
      (node (ref "A36") (pin "P2") (pinfunction "P$2_P2") (pintype "bidirectional"))
      (node (ref "D09") (pin "K1") (pinfunction "IN4A_K1") (pintype "input"))
    )
    (net (code "699") (name "STROBE_FIELD0") (class "Default")
      (node (ref "A17") (pin "D1") (pinfunction "D1_D1") (pintype "input"))
      (node (ref "A17") (pin "R1") (pinfunction "R1_R1") (pintype "input"))
      (node (ref "A18") (pin "D1") (pinfunction "D1_D1") (pintype "input"))
      (node (ref "A18") (pin "R1") (pinfunction "R1_R1") (pintype "input"))
      (node (ref "A19") (pin "D1") (pinfunction "D1_D1") (pintype "input"))
      (node (ref "A19") (pin "R1") (pinfunction "R1_R1") (pintype "input"))
      (node (ref "A20") (pin "D1") (pinfunction "D1_D1") (pintype "input"))
      (node (ref "A20") (pin "R1") (pinfunction "R1_R1") (pintype "input"))
      (node (ref "B18") (pin "D1") (pinfunction "D1_D1") (pintype "input"))
      (node (ref "B18") (pin "R1") (pinfunction "R1_R1") (pintype "input"))
      (node (ref "B19") (pin "D1") (pinfunction "D1_D1") (pintype "input"))
      (node (ref "B19") (pin "R1") (pinfunction "R1_R1") (pintype "input"))
      (node (ref "B20") (pin "D1") (pinfunction "D1_D1") (pintype "input"))
      (node (ref "B20") (pin "R1") (pinfunction "R1_R1") (pintype "input"))
      (node (ref "C17") (pin "S2") (pinfunction "S_S2") (pintype "output"))
    )
    (net (code "700") (name "SYNC") (class "Default")
      (node (ref "B11") (pin "V1") (pinfunction "0_V1") (pintype "output"))
      (node (ref "C11") (pin "E2") (pinfunction "IN2_E2") (pintype "input"))
    )
    (net (code "701") (name "TAD") (class "Default")
      (node (ref "C07") (pin "H1") (pinfunction "OUT_H1") (pintype "output"))
      (node (ref "C12") (pin "A1") (pinfunction "IN1_A1") (pintype "input"))
    )
    (net (code "702") (name "TP1") (class "Default")
      (node (ref "A13") (pin "E1") (pinfunction "IN2A_E1") (pintype "input"))
      (node (ref "B11") (pin "S2") (pinfunction "C_S2") (pintype "input"))
      (node (ref "B13") (pin "T2") (pinfunction "IN1_T2") (pintype "input"))
      (node (ref "D02") (pin "M1") (pinfunction "OUT_M1") (pintype "output"))
      (node (ref "D06") (pin "H2") (pinfunction "H2_H2") (pintype "input"))
    )
    (net (code "703") (name "TP2") (class "Default")
      (node (ref "C04") (pin "L2") (pinfunction "C_L2") (pintype "input"))
      (node (ref "C06") (pin "S2") (pinfunction "C_S2") (pintype "input"))
      (node (ref "C14") (pin "D2") (pinfunction "IN1_D2") (pintype "input"))
      (node (ref "D02") (pin "N1") (pinfunction "IN_N1") (pintype "input"))
      (node (ref "D06") (pin "F1") (pinfunction "OUT_F1") (pintype "output"))
      (node (ref "D10") (pin "D2") (pinfunction "C_D2") (pintype "input"))
      (node (ref "D12") (pin "H1") (pinfunction "IN1_H1") (pintype "input"))
    )
    (net (code "704") (name "TP3") (class "Default")
      (node (ref "A13") (pin "A1") (pinfunction "IN1A_A1") (pintype "input"))
      (node (ref "A13") (pin "H1") (pinfunction "IN3A_H1") (pintype "input"))
      (node (ref "A13") (pin "M1") (pinfunction "IN5A_M1") (pintype "input"))
      (node (ref "A14") (pin "S1") (pinfunction "IN3_S1") (pintype "input"))
      (node (ref "C04") (pin "N1") (pinfunction "C_N1") (pintype "input"))
      (node (ref "C05") (pin "A1") (pinfunction "IN1_A1") (pintype "input"))
      (node (ref "C05") (pin "D2") (pinfunction "IN1_D2") (pintype "input"))
      (node (ref "C06") (pin "N1") (pinfunction "C_N1") (pintype "input"))
      (node (ref "C12") (pin "J2") (pinfunction "IN1_J2") (pintype "input"))
      (node (ref "C14") (pin "E1") (pinfunction "IN2_E1") (pintype "input"))
      (node (ref "D06") (pin "J1") (pinfunction "OUT_J1") (pintype "output"))
    )
    (net (code "705") (name "TP4") (class "Default")
      (node (ref "B12") (pin "U2") (pinfunction "IN_U2") (pintype "input"))
      (node (ref "C02") (pin "S1") (pinfunction "OUT_S1") (pintype "output"))
      (node (ref "C04") (pin "B1") (pinfunction "C_B1") (pintype "input"))
      (node (ref "C04") (pin "S2") (pinfunction "C_S2") (pintype "input"))
      (node (ref "C08") (pin "L2") (pinfunction "C_L2") (pintype "input"))
      (node (ref "C08") (pin "N1") (pinfunction "C_N1") (pintype "input"))
      (node (ref "C08") (pin "S2") (pinfunction "C_S2") (pintype "input"))
      (node (ref "D10") (pin "B1") (pinfunction "C_B1") (pintype "input"))
      (node (ref "D10") (pin "L2") (pinfunction "C_L2") (pintype "input"))
      (node (ref "D10") (pin "N1") (pinfunction "C_N1") (pintype "input"))
      (node (ref "D10") (pin "S2") (pinfunction "C_S2") (pintype "input"))
      (node (ref "D12") (pin "H2") (pinfunction "IN1_H2") (pintype "input"))
    )
    (net (code "706") (name "TS1") (class "Default")
      (node (ref "A12") (pin "E1") (pinfunction "IN2A_E1") (pintype "input"))
      (node (ref "B10") (pin "J2") (pinfunction "IN2A_J2") (pintype "input"))
      (node (ref "C04") (pin "E1") (pinfunction "1_E1") (pintype "output"))
    )
    (net (code "707") (name "TS2") (class "Default")
      (node (ref "A10") (pin "E1") (pinfunction "IN2A_E1") (pintype "input"))
      (node (ref "A12") (pin "D2") (pinfunction "IN1A_D2") (pintype "input"))
      (node (ref "A12") (pin "P2") (pinfunction "IN4B_P2") (pintype "input"))
      (node (ref "A13") (pin "D2") (pinfunction "IN1A_D2") (pintype "input"))
      (node (ref "C04") (pin "P2") (pinfunction "1_P2") (pintype "output"))
      (node (ref "C11") (pin "K2") (pinfunction "IN1_K2") (pintype "input"))
      (node (ref "C11") (pin "R2") (pinfunction "IN1_R2") (pintype "input"))
      (node (ref "D04") (pin "U2") (pinfunction "IN2_U2") (pintype "input"))
      (node (ref "D09") (pin "P2") (pinfunction "IN4B_P2") (pintype "input"))
    )
    (net (code "708") (name "TS3") (class "Default")
      (node (ref "A10") (pin "A1") (pinfunction "IN1A_A1") (pintype "input"))
      (node (ref "A11") (pin "R1") (pinfunction "IN2_R1") (pintype "input"))
      (node (ref "A12") (pin "M1") (pinfunction "IN5A_M1") (pintype "input"))
      (node (ref "B10") (pin "E2") (pinfunction "IN1B_E2") (pintype "input"))
      (node (ref "C04") (pin "S1") (pinfunction "1_S1") (pintype "output"))
      (node (ref "C10") (pin "D2") (pinfunction "IN5_D2") (pintype "input"))
      (node (ref "C10") (pin "K2") (pinfunction "IN5_K2") (pintype "input"))
      (node (ref "C12") (pin "B1") (pinfunction "IN2_B1") (pintype "input"))
      (node (ref "C13") (pin "A1") (pinfunction "IN1_A1") (pintype "input"))
    )
    (net (code "709") (name "TS4") (class "Default")
      (node (ref "A10") (pin "K1") (pinfunction "IN4A_K1") (pintype "input"))
      (node (ref "A10") (pin "M1") (pinfunction "IN5A_M1") (pintype "input"))
      (node (ref "B10") (pin "N2") (pinfunction "IN4A_N2") (pintype "input"))
      (node (ref "B13") (pin "D1") (pinfunction "IN1_D1") (pintype "input"))
      (node (ref "C04") (pin "V2") (pinfunction "1_V2") (pintype "output"))
      (node (ref "C13") (pin "F1") (pinfunction "IN1_F1") (pintype "input"))
      (node (ref "C15") (pin "M2") (pinfunction "IN2_M2") (pintype "input"))
      (node (ref "D11") (pin "L1") (pinfunction "IN1_L1") (pintype "input"))
    )
    (net (code "710") (name "TTI_CLOCK") (class "Default")
      (node (ref "C32") (pin "N1") (pinfunction "P$2_N1") (pintype "bidirectional"))
      (node (ref "C33") (pin "R2") (pinfunction "P$2_R2") (pintype "bidirectional"))
    )
    (net (code "711") (name "TTO_ENABLE") (class "Default")
      (node (ref "C31") (pin "K1") (pinfunction "P$2_K1") (pintype "bidirectional"))
      (node (ref "C31") (pin "K2") (pinfunction "P$2_K2") (pintype "bidirectional"))
    )
    (net (code "712") (name "TXD") (class "Default")
      (node (ref "C31") (pin "V2") (pinfunction "P$2_V2") (pintype "bidirectional"))
      (node (ref "D33") (pin "H2") (pinfunction "P$2_H2") (pintype "bidirectional"))
    )
    (net (code "713") (name "VCC") (class "Default")
      (node (ref "A01") (pin "A2") (pinfunction "P$2_A2") (pintype "bidirectional"))
      (node (ref "A28") (pin "A2") (pinfunction "P$2_A2") (pintype "bidirectional"))
      (node (ref "A36") (pin "A2") (pinfunction "P$2_A2") (pintype "bidirectional"))
      (node (ref "B01") (pin "A2") (pinfunction "P$2_A2") (pintype "bidirectional"))
      (node (ref "B28") (pin "A2") (pinfunction "P$2_A2") (pintype "bidirectional"))
      (node (ref "C01") (pin "A2") (pinfunction "P$2_A2") (pintype "bidirectional"))
      (node (ref "C31") (pin "A2") (pinfunction "P$2_A2") (pintype "bidirectional"))
      (node (ref "C32") (pin "A2") (pinfunction "P$2_A2") (pintype "bidirectional"))
      (node (ref "C33") (pin "A2") (pinfunction "P$2_A2") (pintype "bidirectional"))
      (node (ref "D01") (pin "A2") (pinfunction "P$2_A2") (pintype "bidirectional"))
      (node (ref "D31") (pin "A2") (pinfunction "P$2_A2") (pintype "bidirectional"))
      (node (ref "D32") (pin "A2") (pinfunction "P$2_A2") (pintype "bidirectional"))
      (node (ref "D33") (pin "A2") (pinfunction "P$2_A2") (pintype "bidirectional"))
    )
    (net (code "714") (name "WORD_COUNT") (class "Default")
      (node (ref "D10") (pin "P1") (pinfunction "D_P1") (pintype "input"))
      (node (ref "D10") (pin "P2") (pinfunction "1_P2") (pintype "output"))
    )
    (net (code "715") (name "WRITE") (class "Default")
      (node (ref "C25") (pin "D1") (pinfunction "D1_D1") (pintype "input"))
      (node (ref "C25") (pin "L1") (pinfunction "L1_L1") (pintype "input"))
      (node (ref "D16") (pin "S1") (pinfunction "1_S1") (pintype "output"))
      (node (ref "D16") (pin "S2") (pinfunction "C_S2") (pintype "input"))
      (node (ref "D25") (pin "D2") (pinfunction "D2_D2") (pintype "input"))
      (node (ref "D25") (pin "M2") (pinfunction "M2_M2") (pintype "input"))
    )
    (net (code "716") (name "X_R{slash}W_RETURN") (class "Default")
      (node (ref "B26") (pin "D2") (pinfunction "P$2_D2") (pintype "passive"))
      (node (ref "D18") (pin "T2") (pinfunction "T2_T2") (pintype "input"))
      (node (ref "D19") (pin "T2") (pinfunction "T2_T2") (pintype "input"))
      (node (ref "D25") (pin "F2") (pinfunction "F2_F2") (pintype "passive"))
      (node (ref "D25") (pin "K1") (pinfunction "K1_K1") (pintype "passive"))
    )
    (net (code "717") (name "X_R{slash}W_SOURCE") (class "Default")
      (node (ref "A26") (pin "D2") (pinfunction "P$2_D2") (pintype "passive"))
      (node (ref "C23") (pin "T2") (pinfunction "T2_T2") (pintype "input"))
      (node (ref "C24") (pin "T2") (pinfunction "T2_T2") (pintype "input"))
      (node (ref "C25") (pin "F2") (pinfunction "F2_F2") (pintype "passive"))
      (node (ref "C25") (pin "K1") (pinfunction "K1_K1") (pintype "passive"))
    )
    (net (code "718") (name "Y_R{slash}W_RETURN") (class "Default")
      (node (ref "A25") (pin "D2") (pinfunction "P$2_D2") (pintype "passive"))
      (node (ref "D23") (pin "T2") (pinfunction "T2_T2") (pintype "input"))
      (node (ref "D24") (pin "T2") (pinfunction "T2_T2") (pintype "input"))
      (node (ref "D25") (pin "P2") (pinfunction "P2_P2") (pintype "passive"))
      (node (ref "D25") (pin "S1") (pinfunction "S1_S1") (pintype "passive"))
    )
    (net (code "719") (name "Y_R{slash}W_SOURCE") (class "Default")
      (node (ref "B25") (pin "D2") (pinfunction "P$2_D2") (pintype "passive"))
      (node (ref "C18") (pin "T2") (pinfunction "T2_T2") (pintype "input"))
      (node (ref "C19") (pin "T2") (pinfunction "T2_T2") (pintype "input"))
      (node (ref "C25") (pin "P2") (pinfunction "P2_P2") (pintype "passive"))
      (node (ref "C25") (pin "S1") (pinfunction "S1_S1") (pintype "passive"))
    )
    (net (code "720") (name "unconnected-(A16C-ODD-PadK1)") (class "Default")
      (node (ref "A16") (pin "K1") (pinfunction "ODD_K1") (pintype "output"))
    )
    (net (code "721") (name "unconnected-(A17-PadC1)") (class "Default")
      (node (ref "A17") (pin "C1") (pinfunction "C1_C1") (pintype "output"))
    )
    (net (code "722") (name "unconnected-(A17-PadE1)") (class "Default")
      (node (ref "A17") (pin "E1") (pinfunction "E1_E1") (pintype "output"))
    )
    (net (code "723") (name "unconnected-(A17-PadK2)") (class "Default")
      (node (ref "A17") (pin "K2") (pinfunction "K2_K2") (pintype "output"))
    )
    (net (code "724") (name "unconnected-(A17-PadS1)") (class "Default")
      (node (ref "A17") (pin "S1") (pinfunction "S1_S1") (pintype "output"))
    )
    (net (code "725") (name "unconnected-(A17-PadU2)") (class "Default")
      (node (ref "A17") (pin "U2") (pinfunction "U2_U2") (pintype "open_collector"))
    )
    (net (code "726") (name "unconnected-(A18-PadC1)") (class "Default")
      (node (ref "A18") (pin "C1") (pinfunction "C1_C1") (pintype "output"))
    )
    (net (code "727") (name "unconnected-(A18-PadE1)") (class "Default")
      (node (ref "A18") (pin "E1") (pinfunction "E1_E1") (pintype "output"))
    )
    (net (code "728") (name "unconnected-(A18-PadK2)") (class "Default")
      (node (ref "A18") (pin "K2") (pinfunction "K2_K2") (pintype "output"))
    )
    (net (code "729") (name "unconnected-(A18-PadS1)") (class "Default")
      (node (ref "A18") (pin "S1") (pinfunction "S1_S1") (pintype "output"))
    )
    (net (code "730") (name "unconnected-(A19-PadC1)") (class "Default")
      (node (ref "A19") (pin "C1") (pinfunction "C1_C1") (pintype "output"))
    )
    (net (code "731") (name "unconnected-(A19-PadE1)") (class "Default")
      (node (ref "A19") (pin "E1") (pinfunction "E1_E1") (pintype "output"))
    )
    (net (code "732") (name "unconnected-(A19-PadK2)") (class "Default")
      (node (ref "A19") (pin "K2") (pinfunction "K2_K2") (pintype "output"))
    )
    (net (code "733") (name "unconnected-(A19-PadS1)") (class "Default")
      (node (ref "A19") (pin "S1") (pinfunction "S1_S1") (pintype "output"))
    )
    (net (code "734") (name "unconnected-(A20-PadC1)") (class "Default")
      (node (ref "A20") (pin "C1") (pinfunction "C1_C1") (pintype "output"))
    )
    (net (code "735") (name "unconnected-(A20-PadE1)") (class "Default")
      (node (ref "A20") (pin "E1") (pinfunction "E1_E1") (pintype "output"))
    )
    (net (code "736") (name "unconnected-(A20-PadK2)") (class "Default")
      (node (ref "A20") (pin "K2") (pinfunction "K2_K2") (pintype "output"))
    )
    (net (code "737") (name "unconnected-(A20-PadS1)") (class "Default")
      (node (ref "A20") (pin "S1") (pinfunction "S1_S1") (pintype "output"))
    )
    (net (code "738") (name "unconnected-(A24-PadE1)") (class "Default")
      (node (ref "A24") (pin "E1") (pinfunction "E1_E1") (pintype "passive"))
    )
    (net (code "739") (name "unconnected-(A24-PadK1)") (class "Default")
      (node (ref "A24") (pin "K1") (pinfunction "K1_K1") (pintype "passive"))
    )
    (net (code "740") (name "unconnected-(A24-PadM1)") (class "Default")
      (node (ref "A24") (pin "M1") (pinfunction "M1_M1") (pintype "passive"))
    )
    (net (code "741") (name "unconnected-(A24-PadP2)") (class "Default")
      (node (ref "A24") (pin "P2") (pinfunction "P2_P2") (pintype "passive"))
    )
    (net (code "742") (name "unconnected-(A24-PadS1)") (class "Default")
      (node (ref "A24") (pin "S1") (pinfunction "S1_S1") (pintype "passive"))
    )
    (net (code "743") (name "unconnected-(A24-PadU2)") (class "Default")
      (node (ref "A24") (pin "U2") (pinfunction "U2_U2") (pintype "passive"))
    )
    (net (code "744") (name "unconnected-(AB02-PadAJ1)") (class "Default")
      (node (ref "AB02") (pin "AJ1") (pinfunction "AJ1_AJ1") (pintype "output"))
    )
    (net (code "745") (name "unconnected-(AB02-PadAK2)") (class "Default")
      (node (ref "AB02") (pin "AK2") (pinfunction "AK2_AK2") (pintype "output"))
    )
    (net (code "746") (name "unconnected-(AB02-PadAP2)") (class "Default")
      (node (ref "AB02") (pin "AP2") (pinfunction "AP2_AP2") (pintype "output"))
    )
    (net (code "747") (name "unconnected-(AB02-PadAR2)") (class "Default")
      (node (ref "AB02") (pin "AR2") (pinfunction "AR2_AR2") (pintype "output"))
    )
    (net (code "748") (name "unconnected-(AB03-PadAJ1)") (class "Default")
      (node (ref "AB03") (pin "AJ1") (pinfunction "AJ1_AJ1") (pintype "output"))
    )
    (net (code "749") (name "unconnected-(AB03-PadAK2)") (class "Default")
      (node (ref "AB03") (pin "AK2") (pinfunction "AK2_AK2") (pintype "output"))
    )
    (net (code "750") (name "unconnected-(AB03-PadAP2)") (class "Default")
      (node (ref "AB03") (pin "AP2") (pinfunction "AP2_AP2") (pintype "output"))
    )
    (net (code "751") (name "unconnected-(AB03-PadAR2)") (class "Default")
      (node (ref "AB03") (pin "AR2") (pinfunction "AR2_AR2") (pintype "output"))
    )
    (net (code "752") (name "unconnected-(AB04-PadAJ1)") (class "Default")
      (node (ref "AB04") (pin "AJ1") (pinfunction "AJ1_AJ1") (pintype "output"))
    )
    (net (code "753") (name "unconnected-(AB04-PadAK2)") (class "Default")
      (node (ref "AB04") (pin "AK2") (pinfunction "AK2_AK2") (pintype "output"))
    )
    (net (code "754") (name "unconnected-(AB04-PadAP2)") (class "Default")
      (node (ref "AB04") (pin "AP2") (pinfunction "AP2_AP2") (pintype "output"))
    )
    (net (code "755") (name "unconnected-(AB04-PadAR2)") (class "Default")
      (node (ref "AB04") (pin "AR2") (pinfunction "AR2_AR2") (pintype "output"))
    )
    (net (code "756") (name "unconnected-(AB05-PadAJ1)") (class "Default")
      (node (ref "AB05") (pin "AJ1") (pinfunction "AJ1_AJ1") (pintype "output"))
    )
    (net (code "757") (name "unconnected-(AB05-PadAK2)") (class "Default")
      (node (ref "AB05") (pin "AK2") (pinfunction "AK2_AK2") (pintype "output"))
    )
    (net (code "758") (name "unconnected-(AB05-PadAP2)") (class "Default")
      (node (ref "AB05") (pin "AP2") (pinfunction "AP2_AP2") (pintype "output"))
    )
    (net (code "759") (name "unconnected-(AB05-PadAR2)") (class "Default")
      (node (ref "AB05") (pin "AR2") (pinfunction "AR2_AR2") (pintype "output"))
    )
    (net (code "760") (name "unconnected-(AB06-PadAJ1)") (class "Default")
      (node (ref "AB06") (pin "AJ1") (pinfunction "AJ1_AJ1") (pintype "output"))
    )
    (net (code "761") (name "unconnected-(AB06-PadAK2)") (class "Default")
      (node (ref "AB06") (pin "AK2") (pinfunction "AK2_AK2") (pintype "output"))
    )
    (net (code "762") (name "unconnected-(AB06-PadAP2)") (class "Default")
      (node (ref "AB06") (pin "AP2") (pinfunction "AP2_AP2") (pintype "output"))
    )
    (net (code "763") (name "unconnected-(AB06-PadAR2)") (class "Default")
      (node (ref "AB06") (pin "AR2") (pinfunction "AR2_AR2") (pintype "output"))
    )
    (net (code "764") (name "unconnected-(AB07-PadAJ1)") (class "Default")
      (node (ref "AB07") (pin "AJ1") (pinfunction "AJ1_AJ1") (pintype "output"))
    )
    (net (code "765") (name "unconnected-(AB07-PadAK2)") (class "Default")
      (node (ref "AB07") (pin "AK2") (pinfunction "AK2_AK2") (pintype "output"))
    )
    (net (code "766") (name "unconnected-(AB07-PadAP2)") (class "Default")
      (node (ref "AB07") (pin "AP2") (pinfunction "AP2_AP2") (pintype "output"))
    )
    (net (code "767") (name "unconnected-(AB07-PadAR2)") (class "Default")
      (node (ref "AB07") (pin "AR2") (pinfunction "AR2_AR2") (pintype "output"))
    )
    (net (code "768") (name "unconnected-(AB29D-AM-PadAM2)") (class "Default")
      (node (ref "AB29") (pin "AM2") (pinfunction "AM_AM2") (pintype "output"))
    )
    (net (code "769") (name "unconnected-(AB29D-AP-PadAP2)") (class "Default")
      (node (ref "AB29") (pin "AP2") (pinfunction "AP_AP2") (pintype "output"))
    )
    (net (code "770") (name "unconnected-(AB30-PadAJ1)") (class "Default")
      (node (ref "AB30") (pin "AJ1") (pinfunction "AJ1_AJ1") (pintype "output"))
    )
    (net (code "771") (name "unconnected-(AB30-PadAJ2)") (class "Default")
      (node (ref "AB30") (pin "AJ2") (pinfunction "AJ2_AJ2") (pintype "output"))
    )
    (net (code "772") (name "unconnected-(AB30-PadAM2)") (class "Default")
      (node (ref "AB30") (pin "AM2") (pinfunction "AM2_AM2") (pintype "output"))
    )
    (net (code "773") (name "unconnected-(AB30-PadAT2)") (class "Default")
      (node (ref "AB30") (pin "AT2") (pinfunction "AT2_AT2") (pintype "output"))
    )
    (net (code "774") (name "unconnected-(AB31-PadAJ1)") (class "Default")
      (node (ref "AB31") (pin "AJ1") (pinfunction "AJ1_AJ1") (pintype "output"))
    )
    (net (code "775") (name "unconnected-(AB31-PadAJ2)") (class "Default")
      (node (ref "AB31") (pin "AJ2") (pinfunction "AJ2_AJ2") (pintype "output"))
    )
    (net (code "776") (name "unconnected-(AB31-PadAS1)") (class "Default")
      (node (ref "AB31") (pin "AS1") (pinfunction "AS1_AS1") (pintype "output"))
    )
    (net (code "777") (name "unconnected-(AB31-PadAU2)") (class "Default")
      (node (ref "AB31") (pin "AU2") (pinfunction "AU2_AU2") (pintype "output"))
    )
    (net (code "778") (name "unconnected-(B11D-1-PadH2)") (class "Default")
      (node (ref "B11") (pin "H2") (pinfunction "1_H2") (pintype "output"))
    )
    (net (code "779") (name "unconnected-(B11E-1-PadL1)") (class "Default")
      (node (ref "B11") (pin "L1") (pinfunction "1_L1") (pintype "output"))
    )
    (net (code "780") (name "unconnected-(B11H-1-PadV2)") (class "Default")
      (node (ref "B11") (pin "V2") (pinfunction "1_V2") (pintype "output"))
    )
    (net (code "781") (name "unconnected-(B17C-EVEN-PadL1)") (class "Default")
      (node (ref "B17") (pin "L1") (pinfunction "EVEN_L1") (pintype "output"))
    )
    (net (code "782") (name "unconnected-(B18-PadC1)") (class "Default")
      (node (ref "B18") (pin "C1") (pinfunction "C1_C1") (pintype "output"))
    )
    (net (code "783") (name "unconnected-(B18-PadE1)") (class "Default")
      (node (ref "B18") (pin "E1") (pinfunction "E1_E1") (pintype "output"))
    )
    (net (code "784") (name "unconnected-(B18-PadK2)") (class "Default")
      (node (ref "B18") (pin "K2") (pinfunction "K2_K2") (pintype "output"))
    )
    (net (code "785") (name "unconnected-(B18-PadS1)") (class "Default")
      (node (ref "B18") (pin "S1") (pinfunction "S1_S1") (pintype "output"))
    )
    (net (code "786") (name "unconnected-(B19-PadC1)") (class "Default")
      (node (ref "B19") (pin "C1") (pinfunction "C1_C1") (pintype "output"))
    )
    (net (code "787") (name "unconnected-(B19-PadE1)") (class "Default")
      (node (ref "B19") (pin "E1") (pinfunction "E1_E1") (pintype "output"))
    )
    (net (code "788") (name "unconnected-(B19-PadK2)") (class "Default")
      (node (ref "B19") (pin "K2") (pinfunction "K2_K2") (pintype "output"))
    )
    (net (code "789") (name "unconnected-(B19-PadS1)") (class "Default")
      (node (ref "B19") (pin "S1") (pinfunction "S1_S1") (pintype "output"))
    )
    (net (code "790") (name "unconnected-(B20-PadC1)") (class "Default")
      (node (ref "B20") (pin "C1") (pinfunction "C1_C1") (pintype "output"))
    )
    (net (code "791") (name "unconnected-(B20-PadE1)") (class "Default")
      (node (ref "B20") (pin "E1") (pinfunction "E1_E1") (pintype "output"))
    )
    (net (code "792") (name "unconnected-(B20-PadK2)") (class "Default")
      (node (ref "B20") (pin "K2") (pinfunction "K2_K2") (pintype "output"))
    )
    (net (code "793") (name "unconnected-(B20-PadS1)") (class "Default")
      (node (ref "B20") (pin "S1") (pinfunction "S1_S1") (pintype "output"))
    )
    (net (code "794") (name "unconnected-(C04D-0-PadJ2)") (class "Default")
      (node (ref "C04") (pin "J2") (pinfunction "0_J2") (pintype "output"))
    )
    (net (code "795") (name "unconnected-(C04F-0-PadR2)") (class "Default")
      (node (ref "C04") (pin "R2") (pinfunction "0_R2") (pintype "output"))
    )
    (net (code "796") (name "unconnected-(C06E-0-PadM1)") (class "Default")
      (node (ref "C06") (pin "M1") (pinfunction "0_M1") (pintype "output"))
    )
    (net (code "797") (name "unconnected-(C06H-0-PadV1)") (class "Default")
      (node (ref "C06") (pin "V1") (pinfunction "0_V1") (pintype "output"))
    )
    (net (code "798") (name "unconnected-(C27F-E-PadJ2)") (class "Default")
      (node (ref "C27") (pin "J2") (pinfunction "E_J2") (pintype "open_collector"))
    )
    (net (code "799") (name "unconnected-(CD03C-CN2-PadAN2)") (class "Default")
      (node (ref "CD03") (pin "AN2") (pinfunction "CN2_AN2") (pintype "output"))
    )
    (net (code "800") (name "unconnected-(D05-PadJ2)") (class "Default")
      (node (ref "D05") (pin "J2") (pinfunction "J2_J2") (pintype "output"))
    )
    (net (code "801") (name "unconnected-(D05-PadK2)") (class "Default")
      (node (ref "D05") (pin "K2") (pinfunction "K2_K2") (pintype "output"))
    )
    (net (code "802") (name "unconnected-(D05-PadL2)") (class "Default")
      (node (ref "D05") (pin "L2") (pinfunction "L2_L2") (pintype "output"))
    )
    (net (code "803") (name "unconnected-(D05-PadM2)") (class "Default")
      (node (ref "D05") (pin "M2") (pinfunction "M2_M2") (pintype "output"))
    )
    (net (code "804") (name "unconnected-(D05-PadN2)") (class "Default")
      (node (ref "D05") (pin "N2") (pinfunction "N2_N2") (pintype "output"))
    )
    (net (code "805") (name "unconnected-(D05-PadP2)") (class "Default")
      (node (ref "D05") (pin "P2") (pinfunction "P2_P2") (pintype "output"))
    )
    (net (code "806") (name "unconnected-(D05-PadS2)") (class "Default")
      (node (ref "D05") (pin "S2") (pinfunction "S2_S2") (pintype "output"))
    )
    (net (code "807") (name "unconnected-(D05-PadT2)") (class "Default")
      (node (ref "D05") (pin "T2") (pinfunction "T2_T2") (pintype "output"))
    )
    (net (code "808") (name "unconnected-(D05-PadU2)") (class "Default")
      (node (ref "D05") (pin "U2") (pinfunction "U2_U2") (pintype "output"))
    )
    (net (code "809") (name "unconnected-(D05-PadV2)") (class "Default")
      (node (ref "D05") (pin "V2") (pinfunction "V2_V2") (pintype "output"))
    )
    (net (code "810") (name "unconnected-(D06-PadJ2)") (class "Default")
      (node (ref "D06") (pin "J2") (pinfunction "J2_J2") (pintype "output"))
    )
    (net (code "811") (name "unconnected-(D06-PadK2)") (class "Default")
      (node (ref "D06") (pin "K2") (pinfunction "K2_K2") (pintype "output"))
    )
    (net (code "812") (name "unconnected-(D06-PadL2)") (class "Default")
      (node (ref "D06") (pin "L2") (pinfunction "L2_L2") (pintype "output"))
    )
    (net (code "813") (name "unconnected-(D06-PadN2)") (class "Default")
      (node (ref "D06") (pin "N2") (pinfunction "N2_N2") (pintype "output"))
    )
    (net (code "814") (name "unconnected-(D06-PadP2)") (class "Default")
      (node (ref "D06") (pin "P2") (pinfunction "P2_P2") (pintype "output"))
    )
    (net (code "815") (name "unconnected-(D06-PadR2)") (class "Default")
      (node (ref "D06") (pin "R2") (pinfunction "R2_R2") (pintype "output"))
    )
    (net (code "816") (name "unconnected-(D06-PadS2)") (class "Default")
      (node (ref "D06") (pin "S2") (pinfunction "S2_S2") (pintype "output"))
    )
    (net (code "817") (name "unconnected-(D06-PadU2)") (class "Default")
      (node (ref "D06") (pin "U2") (pinfunction "U2_U2") (pintype "output"))
    )
    (net (code "818") (name "unconnected-(D06-PadV2)") (class "Default")
      (node (ref "D06") (pin "V2") (pinfunction "V2_V2") (pintype "output"))
    )
    (net (code "819") (name "unconnected-(D07-PadJ2)") (class "Default")
      (node (ref "D07") (pin "J2") (pinfunction "J2_J2") (pintype "output"))
    )
    (net (code "820") (name "unconnected-(D07-PadL2)") (class "Default")
      (node (ref "D07") (pin "L2") (pinfunction "L2_L2") (pintype "output"))
    )
    (net (code "821") (name "unconnected-(D07-PadM2)") (class "Default")
      (node (ref "D07") (pin "M2") (pinfunction "M2_M2") (pintype "output"))
    )
    (net (code "822") (name "unconnected-(D07-PadP2)") (class "Default")
      (node (ref "D07") (pin "P2") (pinfunction "P2_P2") (pintype "output"))
    )
    (net (code "823") (name "unconnected-(D07-PadR2)") (class "Default")
      (node (ref "D07") (pin "R2") (pinfunction "R2_R2") (pintype "output"))
    )
    (net (code "824") (name "unconnected-(D07-PadS2)") (class "Default")
      (node (ref "D07") (pin "S2") (pinfunction "S2_S2") (pintype "output"))
    )
    (net (code "825") (name "unconnected-(D07-PadT2)") (class "Default")
      (node (ref "D07") (pin "T2") (pinfunction "T2_T2") (pintype "output"))
    )
    (net (code "826") (name "unconnected-(D07-PadU2)") (class "Default")
      (node (ref "D07") (pin "U2") (pinfunction "U2_U2") (pintype "output"))
    )
    (net (code "827") (name "unconnected-(D07-PadV2)") (class "Default")
      (node (ref "D07") (pin "V2") (pinfunction "V2_V2") (pintype "output"))
    )
    (net (code "828") (name "unconnected-(D08-PadJ2)") (class "Default")
      (node (ref "D08") (pin "J2") (pinfunction "J2_J2") (pintype "output"))
    )
    (net (code "829") (name "unconnected-(D08-PadK2)") (class "Default")
      (node (ref "D08") (pin "K2") (pinfunction "K2_K2") (pintype "output"))
    )
    (net (code "830") (name "unconnected-(D08-PadL2)") (class "Default")
      (node (ref "D08") (pin "L2") (pinfunction "L2_L2") (pintype "output"))
    )
    (net (code "831") (name "unconnected-(D08-PadM2)") (class "Default")
      (node (ref "D08") (pin "M2") (pinfunction "M2_M2") (pintype "output"))
    )
    (net (code "832") (name "unconnected-(D08-PadN2)") (class "Default")
      (node (ref "D08") (pin "N2") (pinfunction "N2_N2") (pintype "output"))
    )
    (net (code "833") (name "unconnected-(D08-PadP2)") (class "Default")
      (node (ref "D08") (pin "P2") (pinfunction "P2_P2") (pintype "output"))
    )
    (net (code "834") (name "unconnected-(D08-PadR2)") (class "Default")
      (node (ref "D08") (pin "R2") (pinfunction "R2_R2") (pintype "output"))
    )
    (net (code "835") (name "unconnected-(D08-PadS2)") (class "Default")
      (node (ref "D08") (pin "S2") (pinfunction "S2_S2") (pintype "output"))
    )
    (net (code "836") (name "unconnected-(D08-PadT2)") (class "Default")
      (node (ref "D08") (pin "T2") (pinfunction "T2_T2") (pintype "output"))
    )
    (net (code "837") (name "unconnected-(D08-PadU2)") (class "Default")
      (node (ref "D08") (pin "U2") (pinfunction "U2_U2") (pintype "output"))
    )
    (net (code "838") (name "unconnected-(D10A-0-PadF1)") (class "Default")
      (node (ref "D10") (pin "F1") (pinfunction "0_F1") (pintype "output"))
    )
    (net (code "839") (name "unconnected-(D10D-0-PadJ2)") (class "Default")
      (node (ref "D10") (pin "J2") (pinfunction "0_J2") (pintype "output"))
    )
    (net (code "840") (name "unconnected-(D10G-1-PadS1)") (class "Default")
      (node (ref "D10") (pin "S1") (pinfunction "1_S1") (pintype "output"))
    )
    (net (code "841") (name "unconnected-(D14-PadJ2)") (class "Default")
      (node (ref "D14") (pin "J2") (pinfunction "J2_J2") (pintype "output"))
    )
    (net (code "842") (name "unconnected-(D14-PadK2)") (class "Default")
      (node (ref "D14") (pin "K2") (pinfunction "K2_K2") (pintype "output"))
    )
    (net (code "843") (name "unconnected-(D14-PadL2)") (class "Default")
      (node (ref "D14") (pin "L2") (pinfunction "L2_L2") (pintype "output"))
    )
    (net (code "844") (name "unconnected-(D14-PadP2)") (class "Default")
      (node (ref "D14") (pin "P2") (pinfunction "P2_P2") (pintype "output"))
    )
    (net (code "845") (name "unconnected-(D14-PadR2)") (class "Default")
      (node (ref "D14") (pin "R2") (pinfunction "R2_R2") (pintype "output"))
    )
    (net (code "846") (name "unconnected-(D14-PadS2)") (class "Default")
      (node (ref "D14") (pin "S2") (pinfunction "S2_S2") (pintype "output"))
    )
    (net (code "847") (name "unconnected-(D14-PadT2)") (class "Default")
      (node (ref "D14") (pin "T2") (pinfunction "T2_T2") (pintype "output"))
    )
    (net (code "848") (name "unconnected-(D14-PadU2)") (class "Default")
      (node (ref "D14") (pin "U2") (pinfunction "U2_U2") (pintype "output"))
    )
    (net (code "849") (name "unconnected-(D14-PadV2)") (class "Default")
      (node (ref "D14") (pin "V2") (pinfunction "V2_V2") (pintype "output"))
    )
    (net (code "850") (name "unconnected-(D15-PadJ2)") (class "Default")
      (node (ref "D15") (pin "J2") (pinfunction "J2_J2") (pintype "output"))
    )
    (net (code "851") (name "unconnected-(D15-PadK2)") (class "Default")
      (node (ref "D15") (pin "K2") (pinfunction "K2_K2") (pintype "output"))
    )
    (net (code "852") (name "unconnected-(D15-PadM2)") (class "Default")
      (node (ref "D15") (pin "M2") (pinfunction "M2_M2") (pintype "output"))
    )
    (net (code "853") (name "unconnected-(D15-PadN2)") (class "Default")
      (node (ref "D15") (pin "N2") (pinfunction "N2_N2") (pintype "output"))
    )
    (net (code "854") (name "unconnected-(D15-PadP2)") (class "Default")
      (node (ref "D15") (pin "P2") (pinfunction "P2_P2") (pintype "output"))
    )
    (net (code "855") (name "unconnected-(D15-PadR2)") (class "Default")
      (node (ref "D15") (pin "R2") (pinfunction "R2_R2") (pintype "output"))
    )
    (net (code "856") (name "unconnected-(D15-PadS2)") (class "Default")
      (node (ref "D15") (pin "S2") (pinfunction "S2_S2") (pintype "output"))
    )
    (net (code "857") (name "unconnected-(D15-PadU2)") (class "Default")
      (node (ref "D15") (pin "U2") (pinfunction "U2_U2") (pintype "output"))
    )
    (net (code "858") (name "unconnected-(D15-PadV2)") (class "Default")
      (node (ref "D15") (pin "V2") (pinfunction "V2_V2") (pintype "output"))
    )
    (net (code "859") (name "unconnected-(D16A-1-PadE1)") (class "Default")
      (node (ref "D16") (pin "E1") (pinfunction "1_E1") (pintype "output"))
    )
    (net (code "860") (name "unconnected-(D16D-0-PadJ2)") (class "Default")
      (node (ref "D16") (pin "J2") (pinfunction "0_J2") (pintype "output"))
    )
    (net (code "861") (name "unconnected-(D16E-0-PadM1)") (class "Default")
      (node (ref "D16") (pin "M1") (pinfunction "0_M1") (pintype "output"))
    )
    (net (code "862") (name "unconnected-(D16G-0-PadU1)") (class "Default")
      (node (ref "D16") (pin "U1") (pinfunction "0_U1") (pintype "output"))
    )
    (net (code "863") (name "~{(IOT+OPR})") (class "Default")
      (node (ref "C09") (pin "N2") (pinfunction "IN1_N2") (pintype "input"))
      (node (ref "C11") (pin "F1") (pinfunction "IN1_F1") (pintype "input"))
      (node (ref "D12") (pin "F2") (pinfunction "OUT_F2") (pintype "output"))
    )
    (net (code "864") (name "~{AC00}") (class "Default")
      (node (ref "A01") (pin "J2") (pinfunction "P$2_J2") (pintype "bidirectional"))
      (node (ref "AB07") (pin "BB1") (pinfunction "BB1_BB1") (pintype "output"))
      (node (ref "B14") (pin "F1") (pinfunction "IN1_F1") (pintype "input"))
    )
    (net (code "865") (name "~{AC01}") (class "Default")
      (node (ref "A01") (pin "L2") (pinfunction "P$2_L2") (pintype "bidirectional"))
      (node (ref "AB07") (pin "AV2") (pinfunction "AV2_AV2") (pintype "output"))
      (node (ref "B14") (pin "H1") (pinfunction "IN2_H1") (pintype "input"))
    )
    (net (code "866") (name "~{AC02}") (class "Default")
      (node (ref "A01") (pin "L1") (pinfunction "P$2_L1") (pintype "bidirectional"))
      (node (ref "AB06") (pin "BB1") (pinfunction "BB1_BB1") (pintype "output"))
      (node (ref "B14") (pin "J1") (pinfunction "IN3_J1") (pintype "input"))
    )
    (net (code "867") (name "~{AC03}") (class "Default")
      (node (ref "A01") (pin "K1") (pinfunction "P$2_K1") (pintype "bidirectional"))
      (node (ref "AB06") (pin "AV2") (pinfunction "AV2_AV2") (pintype "output"))
      (node (ref "B14") (pin "K1") (pinfunction "IN4_K1") (pintype "input"))
    )
    (net (code "868") (name "~{AC04}") (class "Default")
      (node (ref "AB05") (pin "BB1") (pinfunction "BB1_BB1") (pintype "output"))
      (node (ref "B01") (pin "D2") (pinfunction "P$2_D2") (pintype "bidirectional"))
      (node (ref "B14") (pin "K2") (pinfunction "IN5_K2") (pintype "input"))
    )
    (net (code "869") (name "~{AC05}") (class "Default")
      (node (ref "AB05") (pin "AV2") (pinfunction "AV2_AV2") (pintype "output"))
      (node (ref "B01") (pin "E2") (pinfunction "P$2_E2") (pintype "bidirectional"))
      (node (ref "B14") (pin "L2") (pinfunction "IN6_L2") (pintype "input"))
    )
    (net (code "870") (name "~{AC06}") (class "Default")
      (node (ref "AB04") (pin "BB1") (pinfunction "BB1_BB1") (pintype "output"))
      (node (ref "B01") (pin "J2") (pinfunction "P$2_J2") (pintype "bidirectional"))
      (node (ref "B14") (pin "M2") (pinfunction "IN7_M2") (pintype "input"))
    )
    (net (code "871") (name "~{AC07}") (class "Default")
      (node (ref "AB04") (pin "AV2") (pinfunction "AV2_AV2") (pintype "output"))
      (node (ref "B01") (pin "K2") (pinfunction "P$2_K2") (pintype "bidirectional"))
      (node (ref "B14") (pin "N2") (pinfunction "IN8_N2") (pintype "input"))
    )
    (net (code "872") (name "~{AC08}") (class "Default")
      (node (ref "AB03") (pin "BB1") (pinfunction "BB1_BB1") (pintype "output"))
      (node (ref "B01") (pin "U2") (pinfunction "P$2_U2") (pintype "bidirectional"))
      (node (ref "C13") (pin "M1") (pinfunction "IN1_M1") (pintype "input"))
    )
    (net (code "873") (name "~{AC09}") (class "Default")
      (node (ref "AB03") (pin "AV2") (pinfunction "AV2_AV2") (pintype "output"))
      (node (ref "B01") (pin "V2") (pinfunction "P$2_V2") (pintype "bidirectional"))
      (node (ref "C13") (pin "N1") (pinfunction "IN2_N1") (pintype "input"))
    )
    (net (code "874") (name "~{AC10}") (class "Default")
      (node (ref "AB02") (pin "BB1") (pinfunction "BB1_BB1") (pintype "output"))
      (node (ref "C01") (pin "H1") (pinfunction "P$2_H1") (pintype "bidirectional"))
      (node (ref "C13") (pin "P1") (pinfunction "IN3_P1") (pintype "input"))
    )
    (net (code "875") (name "~{AC11}") (class "Default")
      (node (ref "AB02") (pin "AV2") (pinfunction "AV2_AV2") (pintype "output"))
      (node (ref "C01") (pin "F1") (pinfunction "P$2_F1") (pintype "bidirectional"))
      (node (ref "C13") (pin "R1") (pinfunction "IN4_R1") (pintype "input"))
    )
    (net (code "876") (name "~{AC_CLEAR}") (class "Default")
      (node (ref "D09") (pin "K2") (pinfunction "IN2B_K2") (pintype "input"))
      (node (ref "D13") (pin "H1") (pinfunction "OUT_H1") (pintype "output"))
    )
    (net (code "877") (name "~{AC_ENABLE}") (class "Default")
      (node (ref "A08") (pin "L1") (pinfunction "OUT_L1") (pintype "open_collector"))
      (node (ref "AB02") (pin "BJ2") (pinfunction "BJ2_BJ2") (pintype "input"))
      (node (ref "AB03") (pin "BJ2") (pinfunction "BJ2_BJ2") (pintype "input"))
      (node (ref "AB04") (pin "BJ2") (pinfunction "BJ2_BJ2") (pintype "input"))
      (node (ref "AB05") (pin "BJ2") (pinfunction "BJ2_BJ2") (pintype "input"))
      (node (ref "AB06") (pin "BJ2") (pinfunction "BJ2_BJ2") (pintype "input"))
      (node (ref "AB07") (pin "BJ2") (pinfunction "BJ2_BJ2") (pintype "input"))
    )
    (net (code "878") (name "~{ADDER_L}") (class "Default")
      (node (ref "AB02") (pin "AH2") (pinfunction "AH2_AH2") (pintype "input"))
      (node (ref "AB07") (pin "AC1") (pinfunction "AC1_AC1") (pintype "input"))
      (node (ref "B10") (pin "H1") (pinfunction "IN3A_H1") (pintype "input"))
      (node (ref "B10") (pin "V2") (pinfunction "OUT_V2") (pintype "output"))
    )
    (net (code "879") (name "~{ADD_ACCEPTED}") (class "Default")
      (node (ref "C27") (pin "R2") (pinfunction "A_R2") (pintype "input"))
      (node (ref "D10") (pin "E1") (pinfunction "1_E1") (pintype "output"))
    )
    (net (code "880") (name "~{ADD}") (class "Default")
      (node (ref "A08") (pin "K2") (pinfunction "IN1_K2") (pintype "input"))
      (node (ref "A09") (pin "K1") (pinfunction "IN4_K1") (pintype "input"))
      (node (ref "C12") (pin "D1") (pinfunction "OUT_D1") (pintype "output"))
    )
    (net (code "881") (name "~{AND_ENABLE}") (class "Default")
      (node (ref "A09") (pin "F1") (pinfunction "IN1_F1") (pintype "input"))
      (node (ref "A11") (pin "U1") (pinfunction "OUT_U1") (pintype "output"))
      (node (ref "B08") (pin "F1") (pinfunction "IN1_F1") (pintype "input"))
      (node (ref "B08") (pin "H1") (pinfunction "IN2_H1") (pintype "input"))
      (node (ref "B08") (pin "J1") (pinfunction "IN3_J1") (pintype "input"))
      (node (ref "B08") (pin "K1") (pinfunction "IN4_K1") (pintype "input"))
    )
    (net (code "882") (name "~{AND}") (class "Default")
      (node (ref "C07") (pin "D1") (pinfunction "IN_D1") (pintype "input"))
      (node (ref "C09") (pin "H2") (pinfunction "OUT_H2") (pintype "output"))
      (node (ref "C12") (pin "N2") (pinfunction "IN1_N2") (pintype "input"))
    )
    (net (code "883") (name "~{A}") (class "Default")
      (node (ref "AB30") (pin "BP2") (pinfunction "BP2_BP2") (pintype "output"))
      (node (ref "C34") (pin "R2") (pinfunction "P$2_R2") (pintype "bidirectional"))
    )
    (net (code "884") (name "~{BREAK_OK}") (class "Default")
      (node (ref "C11") (pin "B1") (pinfunction "IN2_B1") (pintype "input"))
      (node (ref "C11") (pin "J2") (pinfunction "OUT_J2") (pintype "output"))
      (node (ref "D10") (pin "C1") (pinfunction "D_C1") (pintype "input"))
      (node (ref "D13") (pin "D1") (pinfunction "IN_D1") (pintype "input"))
    )
    (net (code "885") (name "~{BREAK}") (class "Default")
      (node (ref "C07") (pin "U2") (pinfunction "IN_U2") (pintype "input"))
      (node (ref "C26") (pin "J2") (pinfunction "P$1_J2") (pintype "passive"))
      (node (ref "C27") (pin "L2") (pinfunction "B_L2") (pintype "input"))
      (node (ref "D01") (pin "L2") (pinfunction "P$2_L2") (pintype "bidirectional"))
      (node (ref "D10") (pin "V1") (pinfunction "0_V1") (pintype "output"))
    )
    (net (code "886") (name "~{BRK_RQST}") (class "Default")
      (node (ref "B11") (pin "T2") (pinfunction "D_T2") (pintype "input"))
      (node (ref "C36") (pin "K2") (pinfunction "P$2_K2") (pintype "bidirectional"))
      (node (ref "D29") (pin "T2") (pinfunction "P$1_T2") (pintype "passive"))
    )
    (net (code "887") (name "~{B}") (class "Default")
      (node (ref "AB30") (pin "BR1") (pinfunction "BR1_BR1") (pintype "output"))
      (node (ref "C34") (pin "S2") (pinfunction "P$2_S2") (pintype "bidirectional"))
    )
    (net (code "888") (name "~{CARRYOUT0}") (class "Default")
      (node (ref "AB07") (pin "BK2") (pinfunction "BK2_BK2") (pintype "output"))
      (node (ref "B10") (pin "U2") (pinfunction "IN2B_U2") (pintype "input"))
      (node (ref "B12") (pin "C1") (pinfunction "IN_C1") (pintype "input"))
    )
    (net (code "889") (name "~{CARRYOUT6}") (class "Default")
      (node (ref "AB04") (pin "BK2") (pinfunction "BK2_BK2") (pintype "output"))
      (node (ref "AB05") (pin "BJ1") (pinfunction "BJ1_BJ1") (pintype "input"))
    )
    (net (code "890") (name "~{CLR_PARITY_ERROR}") (class "Default")
      (node (ref "A14") (pin "M1") (pinfunction "IN3_M1") (pintype "input"))
      (node (ref "B15") (pin "J2") (pinfunction "OUT_J2") (pintype "output"))
    )
    (net (code "891") (name "~{CURRENT_ADDR}") (class "Default")
      (node (ref "C26") (pin "H2") (pinfunction "P$1_H2") (pintype "passive"))
      (node (ref "D01") (pin "K2") (pinfunction "P$2_K2") (pintype "bidirectional"))
      (node (ref "D02") (pin "U2") (pinfunction "IN_U2") (pintype "input"))
      (node (ref "D10") (pin "U1") (pinfunction "0_U1") (pintype "output"))
      (node (ref "D12") (pin "L1") (pinfunction "IN1_L1") (pintype "input"))
      (node (ref "D12") (pin "R1") (pinfunction "IN2_R1") (pintype "input"))
    )
    (net (code "892") (name "~{DCA}") (class "Default")
      (node (ref "C07") (pin "L1") (pinfunction "IN_L1") (pintype "input"))
      (node (ref "C09") (pin "M2") (pinfunction "OUT_M2") (pintype "output"))
      (node (ref "C12") (pin "R2") (pinfunction "IN3_R2") (pintype "input"))
    )
    (net (code "893") (name "~{DEFER}") (class "Default")
      (node (ref "C08") (pin "U1") (pinfunction "0_U1") (pintype "output"))
      (node (ref "D01") (pin "E2") (pinfunction "P$2_E2") (pintype "bidirectional"))
      (node (ref "D12") (pin "D1") (pinfunction "IN1_D1") (pintype "input"))
    )
    (net (code "894") (name "~{D_SET}") (class "Default")
      (node (ref "B13") (pin "A1") (pinfunction "IN1_A1") (pintype "input"))
      (node (ref "C07") (pin "P2") (pinfunction "IN_P2") (pintype "input"))
      (node (ref "C09") (pin "S2") (pinfunction "OUT_S2") (pintype "output"))
      (node (ref "C11") (pin "D1") (pinfunction "IN4_D1") (pintype "input"))
      (node (ref "C11") (pin "H2") (pinfunction "IN4_H2") (pintype "input"))
    )
    (net (code "895") (name "~{EA}") (class "Default")
      (node (ref "B34") (pin "B1") (pinfunction "P$2_B1") (pintype "bidirectional"))
      (node (ref "C13") (pin "R2") (pinfunction "IN1_R2") (pintype "input"))
      (node (ref "C26") (pin "D2") (pinfunction "P$1_D2") (pintype "passive"))
      (node (ref "D16") (pin "C1") (pinfunction "D_C1") (pintype "input"))
    )
    (net (code "896") (name "~{EMA}") (class "Default")
      (node (ref "A01") (pin "F1") (pinfunction "P$2_F1") (pintype "bidirectional"))
      (node (ref "B35") (pin "V2") (pinfunction "P$2_V2") (pintype "bidirectional"))
    )
    (net (code "897") (name "~{ENABLE}") (class "Default")
      (node (ref "AB29") (pin "AK2") (pinfunction "AK_AK2") (pintype "input"))
      (node (ref "AB30") (pin "BK2") (pinfunction "BK2_BK2") (pintype "output"))
    )
    (net (code "898") (name "~{EXECUTE}") (class "Default")
      (node (ref "C01") (pin "U2") (pinfunction "P$2_U2") (pintype "bidirectional"))
      (node (ref "C08") (pin "V1") (pinfunction "0_V1") (pintype "output"))
    )
    (net (code "899") (name "~{E_SET}") (class "Default")
      (node (ref "B13") (pin "B1") (pinfunction "IN2_B1") (pintype "input"))
      (node (ref "C07") (pin "T2") (pinfunction "OUT_T2") (pintype "output"))
      (node (ref "C11") (pin "C1") (pinfunction "IN3_C1") (pintype "input"))
      (node (ref "C11") (pin "D2") (pinfunction "IN1_D2") (pintype "input"))
      (node (ref "D17") (pin "T2") (pinfunction "IN3_T2") (pintype "input"))
      (node (ref "D17") (pin "U2") (pinfunction "IN4_U2") (pintype "input"))
    )
    (net (code "900") (name "~{FETCH}") (class "Default")
      (node (ref "C01") (pin "P2") (pinfunction "P$2_P2") (pintype "bidirectional"))
      (node (ref "C08") (pin "R2") (pinfunction "0_R2") (pintype "output"))
    )
    (net (code "901") (name "~{F_SET}") (class "Default")
      (node (ref "C07") (pin "M2") (pinfunction "IN_M2") (pintype "input"))
      (node (ref "C11") (pin "E1") (pinfunction "OUT_E1") (pintype "output"))
      (node (ref "D17") (pin "R2") (pinfunction "IN1_R2") (pintype "input"))
      (node (ref "D17") (pin "S2") (pinfunction "IN2_S2") (pintype "input"))
    )
    (net (code "902") (name "~{GO}") (class "Default")
      (node (ref "B08") (pin "T2") (pinfunction "IN3_T2") (pintype "input"))
      (node (ref "B13") (pin "R2") (pinfunction "IN2_R2") (pintype "input"))
      (node (ref "C08") (pin "N2") (pinfunction "S_N2") (pintype "input"))
      (node (ref "D12") (pin "C1") (pinfunction "OUT_C1") (pintype "output"))
    )
    (net (code "903") (name "~{HSR_RUN}") (class "Default")
      (node (ref "AB29") (pin "BS2") (pinfunction "BS_BS2") (pintype "input"))
      (node (ref "AB30") (pin "AK1") (pinfunction "AK1_AK1") (pintype "output"))
    )
    (net (code "904") (name "~{ILLEGAL_REF}") (class "Default")
      (node (ref "A13") (pin "D1") (pinfunction "IN1D_D1") (pintype "input"))
      (node (ref "C02") (pin "D2") (pinfunction "IN1_D2") (pintype "input"))
      (node (ref "C06") (pin "V2") (pinfunction "1_V2") (pintype "output"))
      (node (ref "D01") (pin "F2") (pinfunction "P$2_F2") (pintype "bidirectional"))
    )
    (net (code "905") (name "~{INHIBIT}") (class "Default")
      (node (ref "D16") (pin "R2") (pinfunction "0_R2") (pintype "output"))
      (node (ref "D17") (pin "D2") (pinfunction "IN1_D2") (pintype "input"))
      (node (ref "D17") (pin "E2") (pinfunction "IN2_E2") (pintype "input"))
      (node (ref "D17") (pin "F2") (pinfunction "IN3_F2") (pintype "input"))
      (node (ref "D17") (pin "H2") (pinfunction "IN4_H2") (pintype "input"))
      (node (ref "D17") (pin "P1") (pinfunction "IN3_P1") (pintype "input"))
      (node (ref "D17") (pin "R1") (pinfunction "IN4_R1") (pintype "input"))
    )
    (net (code "906") (name "~{INITIALIZE}") (class "Default")
      (node (ref "AB30") (pin "BP1") (pinfunction "BP1_BP1") (pintype "input"))
      (node (ref "AB31") (pin "AS2") (pinfunction "AS2_AS2") (pintype "input"))
      (node (ref "C06") (pin "A1") (pinfunction "R_A1") (pintype "input"))
      (node (ref "C06") (pin "N2") (pinfunction "S_N2") (pintype "input"))
      (node (ref "C30") (pin "U2") (pinfunction "IN1_U2") (pintype "input"))
      (node (ref "C30") (pin "V2") (pinfunction "IN2_V2") (pintype "input"))
      (node (ref "D02") (pin "N2") (pinfunction "OUT_N2") (pintype "output"))
    )
    (net (code "907") (name "~{INT_ENABLE}") (class "Default")
      (node (ref "B11") (pin "E1") (pinfunction "1_E1") (pintype "output"))
      (node (ref "B11") (pin "E2") (pinfunction "D_E2") (pintype "input"))
      (node (ref "C01") (pin "S2") (pinfunction "P$2_S2") (pintype "bidirectional"))
    )
    (net (code "908") (name "~{INT_INHIBIT}") (class "Default")
      (node (ref "B36") (pin "L1") (pinfunction "P$2_L1") (pintype "bidirectional"))
      (node (ref "C13") (pin "F2") (pinfunction "IN3_F2") (pintype "input"))
      (node (ref "C26") (pin "E2") (pinfunction "P$1_E2") (pintype "passive"))
    )
    (net (code "909") (name "~{INT_IO_BUS4}") (class "Default")
      (node (ref "A32") (pin "B1") (pinfunction "IN2_B1") (pintype "bidirectional"))
      (node (ref "A32") (pin "D1") (pinfunction "IN4_D1") (pintype "input"))
      (node (ref "AB30") (pin "AP2") (pinfunction "AP2_AP2") (pintype "open_collector"))
    )
    (net (code "910") (name "~{INT_IO_BUS5}") (class "Default")
      (node (ref "A32") (pin "E2") (pinfunction "IN2_E2") (pintype "bidirectional"))
      (node (ref "A32") (pin "H2") (pinfunction "IN4_H2") (pintype "input"))
      (node (ref "AB30") (pin "AS2") (pinfunction "AS2_AS2") (pintype "open_collector"))
    )
    (net (code "911") (name "~{INT_IO_BUS6}") (class "Default")
      (node (ref "A32") (pin "H1") (pinfunction "IN2_H1") (pintype "bidirectional"))
      (node (ref "A32") (pin "K1") (pinfunction "IN4_K1") (pintype "input"))
      (node (ref "AB30") (pin "AR1") (pinfunction "AR1_AR1") (pintype "open_collector"))
    )
    (net (code "912") (name "~{INT_IO_BUS7}") (class "Default")
      (node (ref "A32") (pin "L2") (pinfunction "IN2_L2") (pintype "bidirectional"))
      (node (ref "A32") (pin "N2") (pinfunction "IN4_N2") (pintype "input"))
      (node (ref "AB30") (pin "AN2") (pinfunction "AN2_AN2") (pintype "open_collector"))
    )
    (net (code "913") (name "~{INT_IO_BUS8}") (class "Default")
      (node (ref "A32") (pin "N1") (pinfunction "IN2_N1") (pintype "bidirectional"))
      (node (ref "A32") (pin "R1") (pinfunction "IN4_R1") (pintype "input"))
      (node (ref "AB30") (pin "AS1") (pinfunction "AS1_AS1") (pintype "open_collector"))
    )
    (net (code "914") (name "~{INT_IO_BUS9}") (class "Default")
      (node (ref "A32") (pin "S2") (pinfunction "IN2_S2") (pintype "bidirectional"))
      (node (ref "A32") (pin "U2") (pinfunction "IN4_U2") (pintype "input"))
      (node (ref "AB30") (pin "AP1") (pinfunction "AP1_AP1") (pintype "open_collector"))
    )
    (net (code "915") (name "~{INT_IO_BUS10}") (class "Default")
      (node (ref "A33") (pin "B1") (pinfunction "IN2_B1") (pintype "bidirectional"))
      (node (ref "A33") (pin "D1") (pinfunction "IN4_D1") (pintype "input"))
      (node (ref "AB30") (pin "AR2") (pinfunction "AR2_AR2") (pintype "open_collector"))
    )
    (net (code "916") (name "~{INT_IO_BUS11}") (class "Default")
      (node (ref "A33") (pin "E2") (pinfunction "IN2_E2") (pintype "bidirectional"))
      (node (ref "A33") (pin "H2") (pinfunction "IN4_H2") (pintype "input"))
      (node (ref "AB30") (pin "AN1") (pinfunction "AN1_AN1") (pintype "open_collector"))
    )
    (net (code "917") (name "~{INT_OK}") (class "Default")
      (node (ref "B12") (pin "M2") (pinfunction "IN_M2") (pintype "input"))
      (node (ref "C09") (pin "T2") (pinfunction "IN1_T2") (pintype "input"))
      (node (ref "C13") (pin "J1") (pinfunction "IN3_J1") (pintype "input"))
      (node (ref "C13") (pin "J2") (pinfunction "OUT_J2") (pintype "output"))
    )
    (net (code "918") (name "~{INT_SKIP_EN}") (class "Default")
      (node (ref "A08") (pin "S2") (pinfunction "IN2_S2") (pintype "input"))
      (node (ref "A14") (pin "T2") (pinfunction "IN1_T2") (pintype "input"))
      (node (ref "C11") (pin "V2") (pinfunction "OUT_V2") (pintype "output"))
    )
    (net (code "919") (name "~{IN_STOP2}") (class "Default")
      (node (ref "D32") (pin "R2") (pinfunction "P$2_R2") (pintype "bidirectional"))
      (node (ref "D32") (pin "V2") (pinfunction "P$2_V2") (pintype "bidirectional"))
    )
    (net (code "920") (name "~{IOP1}") (class "Default")
      (node (ref "A08") (pin "P1") (pinfunction "IN3_P1") (pintype "input"))
      (node (ref "C29") (pin "H2") (pinfunction "IN1_H2") (pintype "input"))
      (node (ref "C29") (pin "J2") (pinfunction "IN2_J2") (pintype "input"))
      (node (ref "D02") (pin "E2") (pinfunction "IN_E2") (pintype "input"))
      (node (ref "D04") (pin "H2") (pinfunction "OUT_H2") (pintype "output"))
    )
    (net (code "921") (name "~{IOP2}") (class "Default")
      (node (ref "A08") (pin "N1") (pinfunction "IN2_N1") (pintype "input"))
      (node (ref "C29") (pin "N2") (pinfunction "IN1_N2") (pintype "input"))
      (node (ref "C29") (pin "P2") (pinfunction "IN2_P2") (pintype "input"))
      (node (ref "D02") (pin "H2") (pinfunction "IN_H2") (pintype "input"))
      (node (ref "D04") (pin "M2") (pinfunction "OUT_M2") (pintype "output"))
    )
    (net (code "922") (name "~{IOP4}") (class "Default")
      (node (ref "A08") (pin "M1") (pinfunction "IN1_M1") (pintype "input"))
      (node (ref "C29") (pin "U2") (pinfunction "IN1_U2") (pintype "input"))
      (node (ref "C29") (pin "V2") (pinfunction "IN2_V2") (pintype "input"))
      (node (ref "D02") (pin "K2") (pinfunction "IN_K2") (pintype "input"))
      (node (ref "D04") (pin "S2") (pinfunction "OUT_S2") (pintype "output"))
    )
    (net (code "923") (name "~{IOP_A}") (class "Default")
      (node (ref "C06") (pin "F1") (pinfunction "0_F1") (pintype "output"))
      (node (ref "C06") (pin "M2") (pinfunction "D_M2") (pintype "input"))
    )
    (net (code "924") (name "~{IOP_B}") (class "Default")
      (node (ref "C06") (pin "E2") (pinfunction "D_E2") (pintype "input"))
      (node (ref "C06") (pin "P2") (pinfunction "1_P2") (pintype "output"))
    )
    (net (code "925") (name "~{IOP_C}") (class "Default")
      (node (ref "C05") (pin "J2") (pinfunction "IN2_J2") (pintype "input"))
      (node (ref "C06") (pin "H2") (pinfunction "1_H2") (pintype "output"))
    )
    (net (code "926") (name "~{IOT}") (class "Default")
      (node (ref "C05") (pin "B1") (pinfunction "IN2_B1") (pintype "input"))
      (node (ref "C07") (pin "V1") (pinfunction "IN_V1") (pintype "input"))
      (node (ref "C11") (pin "S1") (pinfunction "OUT_S1") (pintype "output"))
    )
    (net (code "927") (name "~{IO_END}") (class "Default")
      (node (ref "C05") (pin "E1") (pinfunction "IN2_E1") (pintype "input"))
      (node (ref "C05") (pin "K1") (pinfunction "OUT_K1") (pintype "output"))
      (node (ref "D02") (pin "P2") (pinfunction "IN_P2") (pintype "input"))
    )
    (net (code "928") (name "~{IO_PC_ENABLE}") (class "Default")
      (node (ref "A08") (pin "U2") (pinfunction "IN4_U2") (pintype "input"))
      (node (ref "A14") (pin "U2") (pinfunction "IN2_U2") (pintype "input"))
      (node (ref "C28") (pin "D1") (pinfunction "OUT_D1") (pintype "output"))
    )
    (net (code "929") (name "~{IO_RECYCLE}") (class "Default")
      (node (ref "C05") (pin "K2") (pinfunction "OUT_K2") (pintype "output"))
      (node (ref "C05") (pin "P1") (pinfunction "IN1_P1") (pintype "input"))
    )
    (net (code "930") (name "~{IO_ROT}") (class "Default")
      (node (ref "C06") (pin "B1") (pinfunction "C_B1") (pintype "input"))
      (node (ref "C06") (pin "D2") (pinfunction "C_D2") (pintype "input"))
      (node (ref "C06") (pin "L2") (pinfunction "C_L2") (pintype "input"))
      (node (ref "D08") (pin "J1") (pinfunction "OUT_J1") (pintype "output"))
    )
    (net (code "931") (name "~{IO_START}") (class "Default")
      (node (ref "C04") (pin "K1") (pinfunction "S_K1") (pintype "input"))
      (node (ref "C05") (pin "F2") (pinfunction "OUT_F2") (pintype "output"))
      (node (ref "C05") (pin "R1") (pinfunction "IN2_R1") (pintype "input"))
    )
    (net (code "932") (name "~{IR0}") (class "Default")
      (node (ref "C01") (pin "R2") (pinfunction "P$2_R2") (pintype "bidirectional"))
      (node (ref "C08") (pin "E1") (pinfunction "1_E1") (pintype "output"))
      (node (ref "C09") (pin "A1") (pinfunction "IN1_A1") (pintype "input"))
      (node (ref "C09") (pin "D2") (pinfunction "IN1_D2") (pintype "input"))
      (node (ref "C09") (pin "E1") (pinfunction "IN1_E1") (pintype "input"))
      (node (ref "C09") (pin "J2") (pinfunction "IN1_J2") (pintype "input"))
      (node (ref "C15") (pin "R1") (pinfunction "IN2_R1") (pintype "input"))
    )
    (net (code "933") (name "~{IR1}") (class "Default")
      (node (ref "C01") (pin "V2") (pinfunction "P$2_V2") (pintype "bidirectional"))
      (node (ref "C08") (pin "J2") (pinfunction "0_J2") (pintype "output"))
      (node (ref "C09") (pin "B1") (pinfunction "IN2_B1") (pintype "input"))
      (node (ref "C09") (pin "E2") (pinfunction "IN2_E2") (pintype "input"))
      (node (ref "C09") (pin "L1") (pinfunction "IN2_L1") (pintype "input"))
      (node (ref "C09") (pin "R1") (pinfunction "IN2_R1") (pintype "input"))
    )
    (net (code "934") (name "~{IR2}") (class "Default")
      (node (ref "C08") (pin "M1") (pinfunction "0_M1") (pintype "output"))
      (node (ref "C09") (pin "F2") (pinfunction "IN3_F2") (pintype "input"))
      (node (ref "C09") (pin "H1") (pinfunction "IN3_H1") (pintype "input"))
      (node (ref "C09") (pin "M1") (pinfunction "IN3_M1") (pintype "input"))
      (node (ref "C11") (pin "P1") (pinfunction "IN3_P1") (pintype "input"))
      (node (ref "D01") (pin "D2") (pinfunction "P$2_D2") (pintype "bidirectional"))
    )
    (net (code "935") (name "~{ISZ}") (class "Default")
      (node (ref "C07") (pin "J1") (pinfunction "IN_J1") (pintype "input"))
      (node (ref "C09") (pin "J1") (pinfunction "OUT_J1") (pintype "output"))
    )
    (net (code "936") (name "~{JMP_DIRECT}") (class "Default")
      (node (ref "A09") (pin "K2") (pinfunction "IN1_K2") (pintype "input"))
      (node (ref "A09") (pin "L2") (pinfunction "IN2_L2") (pintype "input"))
      (node (ref "B12") (pin "N1") (pinfunction "IN_N1") (pintype "input"))
      (node (ref "C13") (pin "E1") (pinfunction "OUT_E1") (pintype "output"))
    )
    (net (code "937") (name "~{JMP}") (class "Default")
      (node (ref "A10") (pin "P1") (pinfunction "IN5C_P1") (pintype "input"))
      (node (ref "C07") (pin "R1") (pinfunction "IN_R1") (pintype "input"))
      (node (ref "C09") (pin "U1") (pinfunction "OUT_U1") (pintype "output"))
      (node (ref "C11") (pin "J1") (pinfunction "IN3_J1") (pintype "input"))
      (node (ref "C15") (pin "R2") (pinfunction "IN2_R2") (pintype "input"))
      (node (ref "D12") (pin "E1") (pinfunction "IN2_E1") (pintype "input"))
    )
    (net (code "938") (name "~{JMS}") (class "Default")
      (node (ref "C07") (pin "N1") (pinfunction "IN_N1") (pintype "input"))
      (node (ref "C09") (pin "N1") (pinfunction "OUT_N1") (pintype "output"))
      (node (ref "C15") (pin "P2") (pinfunction "IN1_P2") (pintype "input"))
    )
    (net (code "939") (name "~{KCC}") (class "Default")
      (node (ref "C32") (pin "E2") (pinfunction "P$2_E2") (pintype "bidirectional"))
      (node (ref "C32") (pin "V2") (pinfunction "P$2_V2") (pintype "bidirectional"))
    )
    (net (code "940") (name "~{KEY_CONT}") (class "Default")
      (node (ref "B08") (pin "A1") (pinfunction "IN1_A1") (pintype "input"))
      (node (ref "C05") (pin "R2") (pinfunction "IN2_R2") (pintype "input"))
      (node (ref "D01") (pin "P2") (pinfunction "P$2_P2") (pintype "bidirectional"))
      (node (ref "D01") (pin "S1") (pinfunction "P$2_S1") (pintype "bidirectional"))
      (node (ref "D02") (pin "F1") (pinfunction "IN_F1") (pintype "input"))
    )
    (net (code "941") (name "~{KEY_DP}") (class "Default")
      (node (ref "C02") (pin "D1") (pinfunction "IN1_D1") (pintype "input"))
      (node (ref "D01") (pin "V2") (pinfunction "P$2_V2") (pintype "bidirectional"))
      (node (ref "D02") (pin "C1") (pinfunction "IN_C1") (pintype "input"))
    )
    (net (code "942") (name "~{KEY_EX+DP}") (class "Default")
      (node (ref "C02") (pin "H2") (pinfunction "IN1_H2") (pintype "input"))
      (node (ref "D01") (pin "P1") (pinfunction "P$2_P1") (pintype "bidirectional"))
      (node (ref "D02") (pin "E1") (pinfunction "OUT_E1") (pintype "output"))
      (node (ref "D04") (pin "M1") (pinfunction "IN3_M1") (pintype "input"))
    )
    (net (code "943") (name "~{KEY_EX}") (class "Default")
      (node (ref "C02") (pin "E1") (pinfunction "IN2_E1") (pintype "input"))
      (node (ref "D01") (pin "U2") (pinfunction "P$2_U2") (pintype "bidirectional"))
    )
    (net (code "944") (name "~{KEY_LA+EX+DP}") (class "Default")
      (node (ref "C14") (pin "S1") (pinfunction "OUT_S1") (pintype "output"))
      (node (ref "C28") (pin "E2") (pinfunction "IN2_E2") (pintype "input"))
    )
    (net (code "945") (name "~{KEY_LA}") (class "Default")
      (node (ref "C02") (pin "J2") (pinfunction "IN2_J2") (pintype "input"))
      (node (ref "C05") (pin "U2") (pinfunction "IN2_U2") (pintype "input"))
      (node (ref "D01") (pin "S2") (pinfunction "P$2_S2") (pintype "bidirectional"))
      (node (ref "D01") (pin "U1") (pinfunction "P$2_U1") (pintype "bidirectional"))
      (node (ref "D02") (pin "A1") (pinfunction "IN_A1") (pintype "input"))
    )
    (net (code "946") (name "~{KEY_PROTECT}") (class "Default")
      (node (ref "A01") (pin "A1") (pinfunction "P$2_A1") (pintype "bidirectional"))
      (node (ref "D02") (pin "V1") (pinfunction "IN_V1") (pintype "input"))
    )
    (net (code "947") (name "~{KEY_SS}") (class "Default")
      (node (ref "C02") (pin "E2") (pinfunction "IN2_E2") (pintype "input"))
      (node (ref "D01") (pin "T2") (pinfunction "P$2_T2") (pintype "bidirectional"))
    )
    (net (code "948") (name "~{KEY_STOP}") (class "Default")
      (node (ref "C02") (pin "H1") (pinfunction "IN1_H1") (pintype "input"))
      (node (ref "D01") (pin "N2") (pinfunction "P$2_N2") (pintype "bidirectional"))
    )
    (net (code "949") (name "~{KEY_ST}") (class "Default")
      (node (ref "C02") (pin "A1") (pinfunction "IN1_A1") (pintype "input"))
      (node (ref "D01") (pin "R1") (pinfunction "P$2_R1") (pintype "bidirectional"))
      (node (ref "D01") (pin "R2") (pinfunction "P$2_R2") (pintype "bidirectional"))
      (node (ref "D04") (pin "K1") (pinfunction "IN1_K1") (pintype "input"))
    )
    (net (code "950") (name "~{LINK}") (class "Default")
      (node (ref "A01") (pin "E1") (pinfunction "P$2_E1") (pintype "bidirectional"))
      (node (ref "A10") (pin "V1") (pinfunction "IN2A_V1") (pintype "input"))
      (node (ref "B11") (pin "R2") (pinfunction "0_R2") (pintype "output"))
    )
    (net (code "951") (name "~{LOCK}") (class "Default")
      (node (ref "C13") (pin "S2") (pinfunction "IN2_S2") (pintype "input"))
      (node (ref "C13") (pin "T2") (pinfunction "IN3_T2") (pintype "input"))
      (node (ref "C15") (pin "L1") (pinfunction "IN1_L1") (pintype "input"))
      (node (ref "D16") (pin "V1") (pinfunction "0_V1") (pintype "output"))
    )
    (net (code "952") (name "~{L_ENABLE}") (class "Default")
      (node (ref "A10") (pin "U2") (pinfunction "IN2B_U2") (pintype "input"))
      (node (ref "B12") (pin "H1") (pinfunction "OUT_H1") (pintype "output"))
    )
    (net (code "953") (name "~{MA00}") (class "Default")
      (node (ref "A01") (pin "M2") (pinfunction "P$2_M2") (pintype "bidirectional"))
      (node (ref "A35") (pin "J1") (pinfunction "IN_J1") (pintype "input"))
      (node (ref "AB07") (pin "AM1") (pinfunction "AM1_AM1") (pintype "output"))
      (node (ref "B14") (pin "A1") (pinfunction "IN1_A1") (pintype "input"))
      (node (ref "C24") (pin "E2") (pinfunction "E2_E2") (pintype "input"))
    )
    (net (code "954") (name "~{MA01}") (class "Default")
      (node (ref "A01") (pin "J1") (pinfunction "P$2_J1") (pintype "bidirectional"))
      (node (ref "A35") (pin "L1") (pinfunction "IN_L1") (pintype "input"))
      (node (ref "AB07") (pin "AL1") (pinfunction "AL1_AL1") (pintype "output"))
      (node (ref "B14") (pin "B1") (pinfunction "IN2_B1") (pintype "input"))
    )
    (net (code "955") (name "~{MA02}") (class "Default")
      (node (ref "A01") (pin "P2") (pinfunction "P$2_P2") (pintype "bidirectional"))
      (node (ref "A35") (pin "N1") (pinfunction "IN_N1") (pintype "input"))
      (node (ref "AB06") (pin "AM1") (pinfunction "AM1_AM1") (pintype "output"))
      (node (ref "B14") (pin "C1") (pinfunction "IN3_C1") (pintype "input"))
    )
    (net (code "956") (name "~{MA03}") (class "Default")
      (node (ref "A01") (pin "S2") (pinfunction "P$2_S2") (pintype "bidirectional"))
      (node (ref "A35") (pin "R1") (pinfunction "IN_R1") (pintype "input"))
      (node (ref "AB06") (pin "AL1") (pinfunction "AL1_AL1") (pintype "output"))
      (node (ref "B14") (pin "D1") (pinfunction "IN4_D1") (pintype "input"))
      (node (ref "D18") (pin "E2") (pinfunction "E2_E2") (pintype "input"))
    )
    (net (code "957") (name "~{MA04}") (class "Default")
      (node (ref "A01") (pin "U2") (pinfunction "P$2_U2") (pintype "bidirectional"))
      (node (ref "A35") (pin "V1") (pinfunction "IN_V1") (pintype "input"))
      (node (ref "AB05") (pin "AM1") (pinfunction "AM1_AM1") (pintype "output"))
      (node (ref "B14") (pin "D2") (pinfunction "IN5_D2") (pintype "input"))
    )
    (net (code "958") (name "~{MA05}") (class "Default")
      (node (ref "A35") (pin "E2") (pinfunction "IN_E2") (pintype "input"))
      (node (ref "AB05") (pin "AL1") (pinfunction "AL1_AL1") (pintype "output"))
      (node (ref "B01") (pin "H2") (pinfunction "P$2_H2") (pintype "bidirectional"))
      (node (ref "B14") (pin "E2") (pinfunction "IN6_E2") (pintype "input"))
    )
    (net (code "959") (name "~{MA06}") (class "Default")
      (node (ref "A35") (pin "H2") (pinfunction "IN_H2") (pintype "input"))
      (node (ref "AB04") (pin "AM1") (pinfunction "AM1_AM1") (pintype "output"))
      (node (ref "B01") (pin "M2") (pinfunction "P$2_M2") (pintype "bidirectional"))
      (node (ref "B14") (pin "F2") (pinfunction "IN7_F2") (pintype "input"))
      (node (ref "C19") (pin "E2") (pinfunction "E2_E2") (pintype "input"))
    )
    (net (code "960") (name "~{MA07}") (class "Default")
      (node (ref "A35") (pin "K2") (pinfunction "IN_K2") (pintype "input"))
      (node (ref "AB04") (pin "AL1") (pinfunction "AL1_AL1") (pintype "output"))
      (node (ref "B01") (pin "P2") (pinfunction "P$2_P2") (pintype "bidirectional"))
      (node (ref "B14") (pin "H2") (pinfunction "IN8_H2") (pintype "input"))
    )
    (net (code "961") (name "~{MA08}") (class "Default")
      (node (ref "A35") (pin "M2") (pinfunction "IN_M2") (pintype "input"))
      (node (ref "AB03") (pin "AM1") (pinfunction "AM1_AM1") (pintype "output"))
      (node (ref "B01") (pin "T2") (pinfunction "P$2_T2") (pintype "bidirectional"))
    )
    (net (code "962") (name "~{MA09}") (class "Default")
      (node (ref "A35") (pin "P2") (pinfunction "IN_P2") (pintype "input"))
      (node (ref "AB03") (pin "AL1") (pinfunction "AL1_AL1") (pintype "output"))
      (node (ref "C01") (pin "E1") (pinfunction "P$2_E1") (pintype "bidirectional"))
      (node (ref "D23") (pin "E2") (pinfunction "E2_E2") (pintype "input"))
    )
    (net (code "963") (name "~{MA10}") (class "Default")
      (node (ref "A35") (pin "S2") (pinfunction "IN_S2") (pintype "input"))
      (node (ref "AB02") (pin "AM1") (pinfunction "AM1_AM1") (pintype "output"))
      (node (ref "C01") (pin "J1") (pinfunction "P$2_J1") (pintype "bidirectional"))
    )
    (net (code "964") (name "~{MA11}") (class "Default")
      (node (ref "A35") (pin "U2") (pinfunction "IN_U2") (pintype "input"))
      (node (ref "AB02") (pin "AL1") (pinfunction "AL1_AL1") (pintype "output"))
      (node (ref "C01") (pin "N2") (pinfunction "P$2_N2") (pintype "bidirectional"))
    )
    (net (code "965") (name "~{MANUAL_PRESET}") (class "Default")
      (node (ref "B08") (pin "E1") (pinfunction "OUT_E1") (pintype "open_collector"))
      (node (ref "B11") (pin "K1") (pinfunction "S_K1") (pintype "input"))
      (node (ref "B11") (pin "U2") (pinfunction "S_U2") (pintype "input"))
      (node (ref "C04") (pin "D1") (pinfunction "S_D1") (pintype "input"))
      (node (ref "C04") (pin "K2") (pinfunction "R_K2") (pintype "input"))
      (node (ref "C06") (pin "U2") (pinfunction "S_U2") (pintype "input"))
      (node (ref "C08") (pin "K2") (pinfunction "R_K2") (pintype "input"))
      (node (ref "D10") (pin "K2") (pinfunction "R_K2") (pintype "input"))
      (node (ref "D11") (pin "E1") (pinfunction "IN2_E1") (pintype "input"))
    )
    (net (code "966") (name "~{MB00}") (class "Default")
      (node (ref "A01") (pin "K2") (pinfunction "P$2_K2") (pintype "bidirectional"))
      (node (ref "A23") (pin "D2") (pinfunction "D2_D2") (pintype "input"))
      (node (ref "AB07") (pin "AU2") (pinfunction "AU2_AU2") (pintype "output"))
      (node (ref "B16") (pin "A1") (pinfunction "1B_A1") (pintype "input"))
    )
    (net (code "967") (name "~{MB01}") (class "Default")
      (node (ref "A01") (pin "H1") (pinfunction "P$2_H1") (pintype "bidirectional"))
      (node (ref "A23") (pin "D1") (pinfunction "D1_D1") (pintype "input"))
      (node (ref "AB07") (pin "AS1") (pinfunction "AS1_AS1") (pintype "output"))
      (node (ref "B16") (pin "B1") (pinfunction "2B_B1") (pintype "input"))
    )
    (net (code "968") (name "~{MB02}") (class "Default")
      (node (ref "A01") (pin "N2") (pinfunction "P$2_N2") (pintype "bidirectional"))
      (node (ref "A23") (pin "M2") (pinfunction "M2_M2") (pintype "input"))
      (node (ref "AB06") (pin "AU2") (pinfunction "AU2_AU2") (pintype "output"))
      (node (ref "B16") (pin "C1") (pinfunction "4B_C1") (pintype "input"))
    )
    (net (code "969") (name "~{MB03}") (class "Default")
      (node (ref "A01") (pin "R2") (pinfunction "P$2_R2") (pintype "bidirectional"))
      (node (ref "A23") (pin "L1") (pinfunction "L1_L1") (pintype "input"))
      (node (ref "A36") (pin "D2") (pinfunction "P$2_D2") (pintype "bidirectional"))
      (node (ref "AB06") (pin "AS1") (pinfunction "AS1_AS1") (pintype "output"))
      (node (ref "AB30") (pin "BD2") (pinfunction "BD2_BD2") (pintype "input"))
      (node (ref "AB31") (pin "BF2") (pinfunction "BF2_BF2") (pintype "input"))
      (node (ref "B14") (pin "N1") (pinfunction "IN2_N1") (pintype "input"))
      (node (ref "B15") (pin "H2") (pinfunction "IN8_H2") (pintype "input"))
      (node (ref "B15") (pin "N2") (pinfunction "IN8_N2") (pintype "input"))
      (node (ref "B16") (pin "D1") (pinfunction "8B_D1") (pintype "input"))
      (node (ref "C10") (pin "E2") (pinfunction "IN6_E2") (pintype "input"))
      (node (ref "C11") (pin "K1") (pinfunction "IN4_K1") (pintype "input"))
      (node (ref "C13") (pin "D1") (pinfunction "IN4_D1") (pintype "input"))
      (node (ref "C31") (pin "E2") (pinfunction "P$2_E2") (pintype "bidirectional"))
      (node (ref "C32") (pin "D2") (pinfunction "P$2_D2") (pintype "bidirectional"))
      (node (ref "D28") (pin "H1") (pinfunction "B_H1") (pintype "input"))
    )
    (net (code "970") (name "~{MB04}") (class "Default")
      (node (ref "A01") (pin "T2") (pinfunction "P$2_T2") (pintype "bidirectional"))
      (node (ref "A36") (pin "E2") (pinfunction "P$2_E2") (pintype "bidirectional"))
      (node (ref "AB05") (pin "AU2") (pinfunction "AU2_AU2") (pintype "output"))
      (node (ref "AB30") (pin "BE2") (pinfunction "BE2_BE2") (pintype "input"))
      (node (ref "AB31") (pin "BD1") (pinfunction "BD1_BD1") (pintype "input"))
      (node (ref "B14") (pin "P1") (pinfunction "IN3_P1") (pintype "input"))
      (node (ref "B15") (pin "F2") (pinfunction "IN7_F2") (pintype "input"))
      (node (ref "B15") (pin "M2") (pinfunction "IN7_M2") (pintype "input"))
      (node (ref "B17") (pin "K2") (pinfunction "1B_K2") (pintype "input"))
      (node (ref "B23") (pin "D2") (pinfunction "D2_D2") (pintype "input"))
      (node (ref "C31") (pin "E1") (pinfunction "P$2_E1") (pintype "bidirectional"))
      (node (ref "C32") (pin "E1") (pinfunction "P$2_E1") (pintype "bidirectional"))
      (node (ref "D09") (pin "H2") (pinfunction "IN1D_H2") (pintype "input"))
      (node (ref "D09") (pin "S1") (pinfunction "IN1A_S1") (pintype "input"))
      (node (ref "D28") (pin "N1") (pinfunction "B_N1") (pintype "input"))
    )
    (net (code "971") (name "~{MB05}") (class "Default")
      (node (ref "A13") (pin "S1") (pinfunction "IN1A_S1") (pintype "input"))
      (node (ref "AB05") (pin "AS1") (pinfunction "AS1_AS1") (pintype "output"))
      (node (ref "AB30") (pin "BE1") (pinfunction "BE1_BE1") (pintype "input"))
      (node (ref "AB31") (pin "BD2") (pinfunction "BD2_BD2") (pintype "input"))
      (node (ref "B01") (pin "F2") (pinfunction "P$2_F2") (pintype "bidirectional"))
      (node (ref "B14") (pin "R1") (pinfunction "IN4_R1") (pintype "input"))
      (node (ref "B17") (pin "L2") (pinfunction "2B_L2") (pintype "input"))
      (node (ref "B23") (pin "D1") (pinfunction "D1_D1") (pintype "input"))
      (node (ref "C31") (pin "F2") (pinfunction "P$2_F2") (pintype "bidirectional"))
      (node (ref "C32") (pin "F1") (pinfunction "P$2_F1") (pintype "bidirectional"))
      (node (ref "D28") (pin "E2") (pinfunction "B_E2") (pintype "input"))
    )
    (net (code "972") (name "~{MB06}") (class "Default")
      (node (ref "A36") (pin "H2") (pinfunction "P$2_H2") (pintype "bidirectional"))
      (node (ref "AB04") (pin "AU2") (pinfunction "AU2_AU2") (pintype "output"))
      (node (ref "AB30") (pin "BF2") (pinfunction "BF2_BF2") (pintype "input"))
      (node (ref "AB31") (pin "BE1") (pinfunction "BE1_BE1") (pintype "input"))
      (node (ref "B01") (pin "L2") (pinfunction "P$2_L2") (pintype "bidirectional"))
      (node (ref "B14") (pin "R2") (pinfunction "IN5_R2") (pintype "input"))
      (node (ref "B15") (pin "D2") (pinfunction "IN5_D2") (pintype "input"))
      (node (ref "B15") (pin "K2") (pinfunction "IN5_K2") (pintype "input"))
      (node (ref "B17") (pin "M2") (pinfunction "4B_M2") (pintype "input"))
      (node (ref "B23") (pin "M2") (pinfunction "M2_M2") (pintype "input"))
      (node (ref "C32") (pin "H1") (pinfunction "P$2_H1") (pintype "bidirectional"))
      (node (ref "D09") (pin "U2") (pinfunction "IN2B_U2") (pintype "input"))
      (node (ref "D28") (pin "L2") (pinfunction "B_L2") (pintype "input"))
    )
    (net (code "973") (name "~{MB07}") (class "Default")
      (node (ref "A13") (pin "U1") (pinfunction "IN1B_U1") (pintype "input"))
      (node (ref "A36") (pin "J2") (pinfunction "P$2_J2") (pintype "bidirectional"))
      (node (ref "AB04") (pin "AS1") (pinfunction "AS1_AS1") (pintype "output"))
      (node (ref "AB30") (pin "BF1") (pinfunction "BF1_BF1") (pintype "input"))
      (node (ref "B01") (pin "R2") (pinfunction "P$2_R2") (pintype "bidirectional"))
      (node (ref "B14") (pin "S2") (pinfunction "IN6_S2") (pintype "input"))
      (node (ref "B15") (pin "D1") (pinfunction "IN4_D1") (pintype "input"))
      (node (ref "B15") (pin "K1") (pinfunction "IN4_K1") (pintype "input"))
      (node (ref "B17") (pin "N2") (pinfunction "8B_N2") (pintype "input"))
      (node (ref "B23") (pin "L1") (pinfunction "L1_L1") (pintype "input"))
      (node (ref "C31") (pin "H2") (pinfunction "P$2_H2") (pintype "bidirectional"))
      (node (ref "D28") (pin "S2") (pinfunction "B_S2") (pintype "input"))
    )
    (net (code "974") (name "~{MB08}") (class "Default")
      (node (ref "A11") (pin "K1") (pinfunction "IN1_K1") (pintype "input"))
      (node (ref "A13") (pin "M2") (pinfunction "IN3B_M2") (pintype "input"))
      (node (ref "A36") (pin "K2") (pinfunction "P$2_K2") (pintype "bidirectional"))
      (node (ref "AB03") (pin "AU2") (pinfunction "AU2_AU2") (pintype "output"))
      (node (ref "AB31") (pin "BF1") (pinfunction "BF1_BF1") (pintype "input"))
      (node (ref "B01") (pin "S2") (pinfunction "P$2_S2") (pintype "bidirectional"))
      (node (ref "B14") (pin "T2") (pinfunction "IN7_T2") (pintype "input"))
      (node (ref "B15") (pin "C1") (pinfunction "IN3_C1") (pintype "input"))
      (node (ref "B15") (pin "J1") (pinfunction "IN3_J1") (pintype "input"))
      (node (ref "B16") (pin "K2") (pinfunction "1B_K2") (pintype "input"))
      (node (ref "B24") (pin "D2") (pinfunction "D2_D2") (pintype "input"))
      (node (ref "C27") (pin "B1") (pinfunction "B_B1") (pintype "input"))
      (node (ref "C31") (pin "J2") (pinfunction "P$2_J2") (pintype "bidirectional"))
    )
    (net (code "975") (name "~{MB09}") (class "Default")
      (node (ref "A11") (pin "M1") (pinfunction "IN3_M1") (pintype "input"))
      (node (ref "AB03") (pin "AS1") (pinfunction "AS1_AS1") (pintype "output"))
      (node (ref "B16") (pin "L2") (pinfunction "2B_L2") (pintype "input"))
      (node (ref "B24") (pin "D1") (pinfunction "D1_D1") (pintype "input"))
      (node (ref "C01") (pin "D1") (pinfunction "P$2_D1") (pintype "bidirectional"))
    )
    (net (code "976") (name "~{MB10}") (class "Default")
      (node (ref "A11") (pin "H1") (pinfunction "IN3_H1") (pintype "input"))
      (node (ref "A11") (pin "L2") (pinfunction "IN3_L2") (pintype "input"))
      (node (ref "AB02") (pin "AU2") (pinfunction "AU2_AU2") (pintype "output"))
      (node (ref "B16") (pin "M2") (pinfunction "4B_M2") (pintype "input"))
      (node (ref "B24") (pin "M2") (pinfunction "M2_M2") (pintype "input"))
      (node (ref "C01") (pin "K1") (pinfunction "P$2_K1") (pintype "bidirectional"))
      (node (ref "C14") (pin "T2") (pinfunction "IN1_T2") (pintype "input"))
    )
    (net (code "977") (name "~{MB11}") (class "Default")
      (node (ref "AB02") (pin "AS1") (pinfunction "AS1_AS1") (pintype "output"))
      (node (ref "B11") (pin "C1") (pinfunction "D_C1") (pintype "input"))
      (node (ref "B16") (pin "N2") (pinfunction "8B_N2") (pintype "input"))
      (node (ref "B24") (pin "L1") (pinfunction "L1_L1") (pintype "input"))
      (node (ref "C01") (pin "M2") (pinfunction "P$2_M2") (pintype "bidirectional"))
      (node (ref "C10") (pin "M2") (pinfunction "IN7_M2") (pintype "input"))
      (node (ref "C12") (pin "E2") (pinfunction "IN2_E2") (pintype "input"))
      (node (ref "C14") (pin "U2") (pinfunction "IN2_U2") (pintype "input"))
      (node (ref "D09") (pin "B1") (pinfunction "IN1B_B1") (pintype "input"))
    )
    (net (code "978") (name "~{MEM00}") (class "Default")
      (node (ref "A15") (pin "A1") (pinfunction "1B_A1") (pintype "input"))
      (node (ref "C16") (pin "D2") (pinfunction "OUT_D2") (pintype "output"))
    )
    (net (code "979") (name "~{MEM01}") (class "Default")
      (node (ref "A15") (pin "B1") (pinfunction "2B_B1") (pintype "input"))
      (node (ref "C16") (pin "E1") (pinfunction "OUT_E1") (pintype "output"))
    )
    (net (code "980") (name "~{MEM02}") (class "Default")
      (node (ref "A15") (pin "C1") (pinfunction "4B_C1") (pintype "input"))
      (node (ref "C16") (pin "F2") (pinfunction "OUT_F2") (pintype "output"))
    )
    (net (code "981") (name "~{MEM03}") (class "Default")
      (node (ref "A15") (pin "D1") (pinfunction "8B_D1") (pintype "input"))
      (node (ref "C16") (pin "H1") (pinfunction "OUT_H1") (pintype "output"))
    )
    (net (code "982") (name "~{MEM04}") (class "Default")
      (node (ref "A16") (pin "K2") (pinfunction "1B_K2") (pintype "input"))
      (node (ref "C16") (pin "J2") (pinfunction "OUT_J2") (pintype "output"))
    )
    (net (code "983") (name "~{MEM05}") (class "Default")
      (node (ref "A16") (pin "L2") (pinfunction "2B_L2") (pintype "input"))
      (node (ref "C16") (pin "K1") (pinfunction "OUT_K1") (pintype "output"))
    )
    (net (code "984") (name "~{MEM06}") (class "Default")
      (node (ref "A16") (pin "M2") (pinfunction "4B_M2") (pintype "input"))
      (node (ref "C16") (pin "L2") (pinfunction "OUT_L2") (pintype "output"))
    )
    (net (code "985") (name "~{MEM07}") (class "Default")
      (node (ref "A16") (pin "N2") (pinfunction "8B_N2") (pintype "input"))
      (node (ref "C16") (pin "M1") (pinfunction "OUT_M1") (pintype "output"))
    )
    (net (code "986") (name "~{MEM08}") (class "Default")
      (node (ref "A15") (pin "K2") (pinfunction "1B_K2") (pintype "input"))
      (node (ref "C16") (pin "N2") (pinfunction "OUT_N2") (pintype "output"))
    )
    (net (code "987") (name "~{MEM09}") (class "Default")
      (node (ref "A15") (pin "L2") (pinfunction "2B_L2") (pintype "input"))
      (node (ref "C16") (pin "P1") (pinfunction "OUT_P1") (pintype "output"))
    )
    (net (code "988") (name "~{MEM10}") (class "Default")
      (node (ref "A15") (pin "M2") (pinfunction "4B_M2") (pintype "input"))
      (node (ref "C16") (pin "R2") (pinfunction "OUT_R2") (pintype "output"))
    )
    (net (code "989") (name "~{MEM11}") (class "Default")
      (node (ref "A15") (pin "N2") (pinfunction "8B_N2") (pintype "input"))
      (node (ref "C16") (pin "S1") (pinfunction "OUT_S1") (pintype "output"))
    )
    (net (code "990") (name "~{MEM_ALT1}") (class "Default")
      (node (ref "A10") (pin "F1") (pinfunction "IN2B_F1") (pintype "input"))
      (node (ref "A10") (pin "T2") (pinfunction "OUT_T2") (pintype "output"))
      (node (ref "D04") (pin "P1") (pinfunction "IN1_P1") (pintype "input"))
    )
    (net (code "991") (name "~{MEM_ALT2}") (class "Default")
      (node (ref "A11") (pin "P2") (pinfunction "IN2_P2") (pintype "input"))
      (node (ref "A12") (pin "T2") (pinfunction "OUT_T2") (pintype "output"))
      (node (ref "D04") (pin "R1") (pinfunction "IN2_R1") (pintype "input"))
    )
    (net (code "992") (name "~{MEM_BEGIN}") (class "Default")
      (node (ref "A17") (pin "B1") (pinfunction "B1_B1") (pintype "input"))
      (node (ref "A18") (pin "B1") (pinfunction "B1_B1") (pintype "input"))
      (node (ref "A19") (pin "B1") (pinfunction "B1_B1") (pintype "input"))
      (node (ref "A20") (pin "B1") (pinfunction "B1_B1") (pintype "input"))
      (node (ref "B18") (pin "B1") (pinfunction "B1_B1") (pintype "input"))
      (node (ref "B19") (pin "B1") (pinfunction "B1_B1") (pintype "input"))
      (node (ref "B20") (pin "B1") (pinfunction "B1_B1") (pintype "input"))
      (node (ref "D16") (pin "K1") (pinfunction "S_K1") (pintype "input"))
      (node (ref "D16") (pin "U2") (pinfunction "S_U2") (pintype "input"))
      (node (ref "D17") (pin "S1") (pinfunction "OUT_S1") (pintype "open_collector"))
    )
    (net (code "993") (name "~{MEM_DONE}") (class "Default")
      (node (ref "B34") (pin "V2") (pinfunction "P$2_V2") (pintype "bidirectional"))
      (node (ref "C04") (pin "F2") (pinfunction "S_F2") (pintype "input"))
      (node (ref "C17") (pin "V2") (pinfunction "OUT_V2") (pintype "open_collector"))
      (node (ref "CD03") (pin "BF2") (pinfunction "P$1_BF2") (pintype "passive"))
      (node (ref "D10") (pin "F2") (pinfunction "S_F2") (pintype "input"))
    )
    (net (code "994") (name "~{MEM_P}") (class "Default")
      (node (ref "A16") (pin "D1") (pinfunction "8B_D1") (pintype "input"))
      (node (ref "C16") (pin "B1") (pinfunction "OUT_B1") (pintype "output"))
    )
    (net (code "995") (name "~{MFTS1}") (class "Default")
      (node (ref "C15") (pin "D1") (pinfunction "IN1_D1") (pintype "input"))
      (node (ref "CD03") (pin "AK2") (pinfunction "CK2_AK2") (pintype "output"))
      (node (ref "D04") (pin "F1") (pinfunction "IN2_F1") (pintype "input"))
    )
    (net (code "996") (name "~{MFTS2}") (class "Default")
      (node (ref "C15") (pin "E1") (pinfunction "IN2_E1") (pintype "input"))
      (node (ref "CD03") (pin "AH2") (pinfunction "CH2_AH2") (pintype "output"))
      (node (ref "D04") (pin "H1") (pinfunction "IN3_H1") (pintype "input"))
    )
    (net (code "997") (name "~{MP_INT}") (class "Default")
      (node (ref "A14") (pin "F2") (pinfunction "IN3_F2") (pintype "input"))
      (node (ref "B15") (pin "F1") (pinfunction "IN1_F1") (pintype "input"))
      (node (ref "C16") (pin "T2") (pinfunction "OUT_T2") (pintype "output"))
      (node (ref "C26") (pin "V2") (pinfunction "P$1_V2") (pintype "passive"))
    )
    (net (code "998") (name "~{MP_SKIP}") (class "Default")
      (node (ref "A14") (pin "R2") (pinfunction "IN3_R2") (pintype "input"))
      (node (ref "B15") (pin "P2") (pinfunction "OUT_P2") (pintype "output"))
      (node (ref "C26") (pin "R2") (pinfunction "P$1_R2") (pintype "passive"))
    )
    (net (code "999") (name "~{OP1}") (class "Default")
      (node (ref "C07") (pin "E2") (pinfunction "IN_E2") (pintype "input"))
      (node (ref "C10") (pin "J2") (pinfunction "OUT_J2") (pintype "output"))
      (node (ref "C14") (pin "A1") (pinfunction "IN1_A1") (pintype "input"))
    )
    (net (code "1000") (name "~{OP2}") (class "Default")
      (node (ref "C07") (pin "H2") (pinfunction "IN_H2") (pintype "input"))
      (node (ref "C10") (pin "P2") (pinfunction "OUT_P2") (pintype "output"))
      (node (ref "C14") (pin "B1") (pinfunction "IN2_B1") (pintype "input"))
    )
    (net (code "1001") (name "~{OP_STROBE}") (class "Default")
      (node (ref "A11") (pin "T2") (pinfunction "IN1_T2") (pintype "input"))
      (node (ref "B08") (pin "U2") (pinfunction "IN4_U2") (pintype "input"))
      (node (ref "C14") (pin "F1") (pinfunction "OUT_F1") (pintype "output"))
    )
    (net (code "1002") (name "~{OUT_STOP2}") (class "Default")
      (node (ref "D31") (pin "N1") (pinfunction "P$2_N1") (pintype "bidirectional"))
      (node (ref "D31") (pin "N2") (pinfunction "P$2_N2") (pintype "bidirectional"))
    )
    (net (code "1003") (name "~{PAUSE}") (class "Default")
      (node (ref "C04") (pin "M1") (pinfunction "0_M1") (pintype "output"))
      (node (ref "D04") (pin "B1") (pinfunction "IN2_B1") (pintype "input"))
    )
    (net (code "1004") (name "~{PC_ENABLE}") (class "Default")
      (node (ref "A08") (pin "T2") (pinfunction "IN3_T2") (pintype "input"))
      (node (ref "A14") (pin "V2") (pinfunction "IN3_V2") (pintype "input"))
      (node (ref "B13") (pin "F1") (pinfunction "OUT_F1") (pintype "output"))
      (node (ref "C13") (pin "K1") (pinfunction "IN4_K1") (pintype "input"))
    )
    (net (code "1005") (name "~{POWER_CLEAR}") (class "Default")
      (node (ref "A27") (pin "S2") (pinfunction "P$2_S2") (pintype "bidirectional"))
      (node (ref "C05") (pin "M1") (pinfunction "IN2_M1") (pintype "input"))
      (node (ref "C06") (pin "R1") (pinfunction "S_R1") (pintype "input"))
      (node (ref "CD03") (pin "AL2") (pinfunction "CL2_AL2") (pintype "input"))
      (node (ref "D16") (pin "A1") (pinfunction "R_A1") (pintype "input"))
      (node (ref "D16") (pin "K2") (pinfunction "R_K2") (pintype "input"))
    )
    (net (code "1006") (name "~{POWER_OK}") (class "Default")
      (node (ref "A27") (pin "J2") (pinfunction "P$2_J2") (pintype "bidirectional"))
      (node (ref "D09") (pin "L1") (pinfunction "IN4B_L1") (pintype "input"))
    )
    (net (code "1007") (name "~{PROTECT}") (class "Default")
      (node (ref "A08") (pin "N2") (pinfunction "IN4_N2") (pintype "input"))
      (node (ref "B13") (pin "M2") (pinfunction "IN2_M2") (pintype "input"))
      (node (ref "C06") (pin "T2") (pinfunction "D_T2") (pintype "input"))
      (node (ref "C11") (pin "L2") (pinfunction "IN2_L2") (pintype "input"))
      (node (ref "C11") (pin "T2") (pinfunction "IN3_T2") (pintype "input"))
      (node (ref "C12") (pin "R1") (pinfunction "IN2_R1") (pintype "input"))
      (node (ref "D04") (pin "V1") (pinfunction "OUT_V1") (pintype "output"))
      (node (ref "D09") (pin "N2") (pinfunction "IN4A_N2") (pintype "input"))
    )
    (net (code "1008") (name "~{PWR_LOW}") (class "Default")
      (node (ref "A33") (pin "N2") (pinfunction "IN4_N2") (pintype "input"))
      (node (ref "A36") (pin "R2") (pinfunction "P$2_R2") (pintype "bidirectional"))
      (node (ref "C26") (pin "S2") (pinfunction "P$1_S2") (pintype "passive"))
    )
    (net (code "1009") (name "~{PWR_SKP}") (class "Default")
      (node (ref "A33") (pin "K1") (pinfunction "IN4_K1") (pintype "input"))
      (node (ref "A36") (pin "L2") (pinfunction "P$2_L2") (pintype "bidirectional"))
    )
    (net (code "1010") (name "~{RDR_INT}") (class "Default")
      (node (ref "A33") (pin "L2") (pinfunction "IN2_L2") (pintype "bidirectional"))
      (node (ref "AB30") (pin "AL2") (pinfunction "AL2_AL2") (pintype "open_collector"))
      (node (ref "AB31") (pin "BS2") (pinfunction "BS2_BS2") (pintype "open_collector"))
    )
    (net (code "1011") (name "~{RDR_SKP}") (class "Default")
      (node (ref "A33") (pin "H1") (pinfunction "IN2_H1") (pintype "bidirectional"))
      (node (ref "AB30") (pin "AK2") (pinfunction "AK2_AK2") (pintype "open_collector"))
      (node (ref "AB31") (pin "BN2") (pinfunction "BN2_BN2") (pintype "open_collector"))
    )
    (net (code "1012") (name "~{RESTART}") (class "Default")
      (node (ref "A36") (pin "U1") (pinfunction "P$2_U1") (pintype "bidirectional"))
      (node (ref "C02") (pin "B1") (pinfunction "IN2_B1") (pintype "input"))
      (node (ref "C05") (pin "T2") (pinfunction "IN1_T2") (pintype "input"))
      (node (ref "C12") (pin "K1") (pinfunction "IN1_K1") (pintype "input"))
      (node (ref "C26") (pin "U2") (pinfunction "P$1_U2") (pintype "passive"))
      (node (ref "CD03") (pin "AR2") (pinfunction "CR2_AR2") (pintype "input"))
      (node (ref "D04") (pin "L1") (pinfunction "IN2_L1") (pintype "input"))
    )
    (net (code "1013") (name "~{RUN}") (class "Default")
      (node (ref "C06") (pin "S1") (pinfunction "1_S1") (pintype "output"))
      (node (ref "C27") (pin "D2") (pinfunction "A_D2") (pintype "input"))
      (node (ref "CD03") (pin "AP2") (pinfunction "CP2_AP2") (pintype "input"))
      (node (ref "D01") (pin "H2") (pinfunction "P$2_H2") (pintype "bidirectional"))
    )
    (net (code "1014") (name "~{SET_IO_ON}") (class "Default")
      (node (ref "B08") (pin "H2") (pinfunction "IN4_H2") (pintype "input"))
      (node (ref "C05") (pin "N2") (pinfunction "OUT_N2") (pintype "output"))
      (node (ref "C06") (pin "K1") (pinfunction "S_K1") (pintype "input"))
    )
    (net (code "1015") (name "~{SHIFT}") (class "Default")
      (node (ref "AB29") (pin "AT2") (pinfunction "AT_AT2") (pintype "output"))
      (node (ref "AB30") (pin "BD1") (pinfunction "BD1_BD1") (pintype "input"))
    )
    (net (code "1016") (name "~{SHUT_DOWN}") (class "Default")
      (node (ref "A27") (pin "F2") (pinfunction "P$2_F2") (pintype "bidirectional"))
      (node (ref "A36") (pin "U2") (pinfunction "P$2_U2") (pintype "bidirectional"))
    )
    (net (code "1017") (name "~{SKIP}") (class "Default")
      (node (ref "B11") (pin "S1") (pinfunction "1_S1") (pintype "output"))
      (node (ref "C12") (pin "V2") (pinfunction "IN3_V2") (pintype "input"))
    )
    (net (code "1018") (name "~{SPECIAL_CYCLE}") (class "Default")
      (node (ref "C11") (pin "A1") (pinfunction "IN1_A1") (pintype "input"))
      (node (ref "C11") (pin "F2") (pinfunction "IN3_F2") (pintype "input"))
      (node (ref "D13") (pin "D2") (pinfunction "OUT_D2") (pintype "output"))
    )
    (net (code "1019") (name "~{STROBE}") (class "Default")
      (node (ref "B34") (pin "S2") (pinfunction "P$2_S2") (pintype "bidirectional"))
      (node (ref "C04") (pin "A1") (pinfunction "R_A1") (pintype "input"))
      (node (ref "C04") (pin "N2") (pinfunction "S_N2") (pintype "input"))
      (node (ref "C17") (pin "T2") (pinfunction "T_T2") (pintype "open_collector"))
      (node (ref "CD03") (pin "BE2") (pinfunction "P$1_BE2") (pintype "passive"))
      (node (ref "D02") (pin "L1") (pinfunction "IN_L1") (pintype "input"))
      (node (ref "D11") (pin "D1") (pinfunction "IN1_D1") (pintype "input"))
    )
    (net (code "1020") (name "~{TAD}") (class "Default")
      (node (ref "C07") (pin "F1") (pinfunction "IN_F1") (pintype "input"))
      (node (ref "C09") (pin "D1") (pinfunction "OUT_D1") (pintype "output"))
      (node (ref "C12") (pin "P2") (pinfunction "IN2_P2") (pintype "input"))
    )
    (net (code "1021") (name "~{TP2}") (class "Default")
      (node (ref "B08") (pin "M2") (pinfunction "IN3_M2") (pintype "input"))
      (node (ref "B08") (pin "N2") (pinfunction "IN4_N2") (pintype "input"))
      (node (ref "C04") (pin "R1") (pinfunction "S_R1") (pintype "input"))
      (node (ref "D02") (pin "P1") (pinfunction "OUT_P1") (pintype "output"))
    )
    (net (code "1022") (name "~{TS1}") (class "Default")
      (node (ref "C04") (pin "F1") (pinfunction "0_F1") (pintype "output"))
      (node (ref "C30") (pin "N2") (pinfunction "IN1_N2") (pintype "input"))
      (node (ref "C30") (pin "P2") (pinfunction "IN2_P2") (pintype "input"))
    )
    (net (code "1023") (name "~{TS3}") (class "Default")
      (node (ref "C04") (pin "U1") (pinfunction "0_U1") (pintype "output"))
      (node (ref "C30") (pin "H2") (pinfunction "IN1_H2") (pintype "input"))
      (node (ref "C30") (pin "J2") (pinfunction "IN2_J2") (pintype "input"))
    )
    (net (code "1024") (name "~{TS4}") (class "Default")
      (node (ref "C04") (pin "V1") (pinfunction "0_V1") (pintype "output"))
      (node (ref "C28") (pin "B1") (pinfunction "IN2_B1") (pintype "input"))
    )
    (net (code "1025") (name "~{TT0}") (class "Default")
      (node (ref "A32") (pin "C1") (pinfunction "IN3_C1") (pintype "input"))
      (node (ref "C32") (pin "K2") (pinfunction "P$2_K2") (pintype "bidirectional"))
    )
    (net (code "1026") (name "~{TT1}") (class "Default")
      (node (ref "A32") (pin "F2") (pinfunction "IN3_F2") (pintype "input"))
      (node (ref "C32") (pin "R2") (pinfunction "P$2_R2") (pintype "bidirectional"))
    )
    (net (code "1027") (name "~{TT2}") (class "Default")
      (node (ref "A32") (pin "J1") (pinfunction "IN3_J1") (pintype "input"))
      (node (ref "C32") (pin "S2") (pinfunction "P$2_S2") (pintype "bidirectional"))
    )
    (net (code "1028") (name "~{TT3}") (class "Default")
      (node (ref "A32") (pin "M2") (pinfunction "IN3_M2") (pintype "input"))
      (node (ref "C32") (pin "L1") (pinfunction "P$2_L1") (pintype "bidirectional"))
    )
    (net (code "1029") (name "~{TT4}") (class "Default")
      (node (ref "A32") (pin "P1") (pinfunction "IN3_P1") (pintype "input"))
      (node (ref "C32") (pin "M1") (pinfunction "P$2_M1") (pintype "bidirectional"))
    )
    (net (code "1030") (name "~{TT5}") (class "Default")
      (node (ref "A32") (pin "T2") (pinfunction "IN3_T2") (pintype "input"))
      (node (ref "C32") (pin "P2") (pinfunction "P$2_P2") (pintype "bidirectional"))
    )
    (net (code "1031") (name "~{TT6}") (class "Default")
      (node (ref "A33") (pin "C1") (pinfunction "IN3_C1") (pintype "input"))
      (node (ref "C32") (pin "T2") (pinfunction "P$2_T2") (pintype "bidirectional"))
    )
    (net (code "1032") (name "~{TT7}") (class "Default")
      (node (ref "A33") (pin "F2") (pinfunction "IN3_F2") (pintype "input"))
      (node (ref "C32") (pin "N2") (pinfunction "P$2_N2") (pintype "bidirectional"))
    )
    (net (code "1033") (name "~{TTI_FLAG}") (class "Default")
      (node (ref "A14") (pin "D2") (pinfunction "IN1_D2") (pintype "input"))
      (node (ref "C32") (pin "F2") (pinfunction "P$2_F2") (pintype "bidirectional"))
    )
    (net (code "1034") (name "~{TTI_SKIP}") (class "Default")
      (node (ref "A14") (pin "N2") (pinfunction "IN1_N2") (pintype "input"))
      (node (ref "D32") (pin "H2") (pinfunction "P$2_H2") (pintype "bidirectional"))
    )
    (net (code "1035") (name "~{TTO_CLOCK}") (class "Default")
      (node (ref "C33") (pin "K2") (pinfunction "P$2_K2") (pintype "bidirectional"))
      (node (ref "D31") (pin "P2") (pinfunction "P$2_P2") (pintype "bidirectional"))
    )
    (net (code "1036") (name "~{TTO_ENABLE}") (class "Default")
      (node (ref "C31") (pin "H1") (pinfunction "P$2_H1") (pintype "bidirectional"))
      (node (ref "C31") (pin "L1") (pinfunction "P$2_L1") (pintype "bidirectional"))
    )
    (net (code "1037") (name "~{TTO_FLAG}") (class "Default")
      (node (ref "A14") (pin "E2") (pinfunction "IN2_E2") (pintype "input"))
      (node (ref "D31") (pin "K2") (pinfunction "P$2_K2") (pintype "bidirectional"))
    )
    (net (code "1038") (name "~{TTO_SKIP}") (class "Default")
      (node (ref "A14") (pin "P2") (pinfunction "IN2_P2") (pintype "input"))
      (node (ref "D31") (pin "J2") (pinfunction "P$2_J2") (pintype "bidirectional"))
    )
    (net (code "1039") (name "~{TT_AC_CLEAR}") (class "Default")
      (node (ref "A33") (pin "N1") (pinfunction "IN2_N1") (pintype "bidirectional"))
      (node (ref "A33") (pin "P1") (pinfunction "IN3_P1") (pintype "input"))
      (node (ref "A33") (pin "R1") (pinfunction "IN4_R1") (pintype "input"))
      (node (ref "D32") (pin "E2") (pinfunction "P$2_E2") (pintype "bidirectional"))
    )
    (net (code "1040") (name "~{TT_INT}") (class "Default")
      (node (ref "A33") (pin "M2") (pinfunction "IN3_M2") (pintype "input"))
      (node (ref "D13") (pin "M1") (pinfunction "OUT_M1") (pintype "output"))
    )
    (net (code "1041") (name "~{TT_SKIP}") (class "Default")
      (node (ref "A33") (pin "J1") (pinfunction "IN3_J1") (pintype "input"))
      (node (ref "D13") (pin "U1") (pinfunction "OUT_U1") (pintype "output"))
    )
    (net (code "1042") (name "~{WC_OVERFLOW}") (class "Default")
      (node (ref "C27") (pin "K2") (pinfunction "A_K2") (pintype "input"))
      (node (ref "D10") (pin "H2") (pinfunction "1_H2") (pintype "output"))
    )
    (net (code "1043") (name "~{WC_SET}") (class "Default")
      (node (ref "C26") (pin "T2") (pinfunction "P$1_T2") (pintype "passive"))
      (node (ref "D11") (pin "M2") (pinfunction "IN2_M2") (pintype "input"))
      (node (ref "D12") (pin "M2") (pinfunction "IN2_M2") (pintype "input"))
      (node (ref "D12") (pin "S2") (pinfunction "OUT_S2") (pintype "output"))
      (node (ref "D12") (pin "T2") (pinfunction "IN1_T2") (pintype "input"))
    )
    (net (code "1044") (name "~{WORD_COUNT}") (class "Default")
      (node (ref "A11") (pin "R2") (pinfunction "IN3_R2") (pintype "input"))
      (node (ref "C26") (pin "F2") (pinfunction "P$1_F2") (pintype "passive"))
      (node (ref "D01") (pin "J2") (pinfunction "P$2_J2") (pintype "bidirectional"))
      (node (ref "D02") (pin "S2") (pinfunction "IN_S2") (pintype "input"))
      (node (ref "D04") (pin "S1") (pinfunction "IN3_S1") (pintype "input"))
      (node (ref "D10") (pin "R2") (pinfunction "0_R2") (pintype "output"))
      (node (ref "D11") (pin "H1") (pinfunction "IN1_H1") (pintype "input"))
      (node (ref "D12") (pin "M1") (pinfunction "IN2_M1") (pintype "input"))
      (node (ref "D12") (pin "U2") (pinfunction "IN2_U2") (pintype "input"))
    )
  )
)
